# debug_backplane.net
KiCad netlist of a schematic drawn in EAGLE
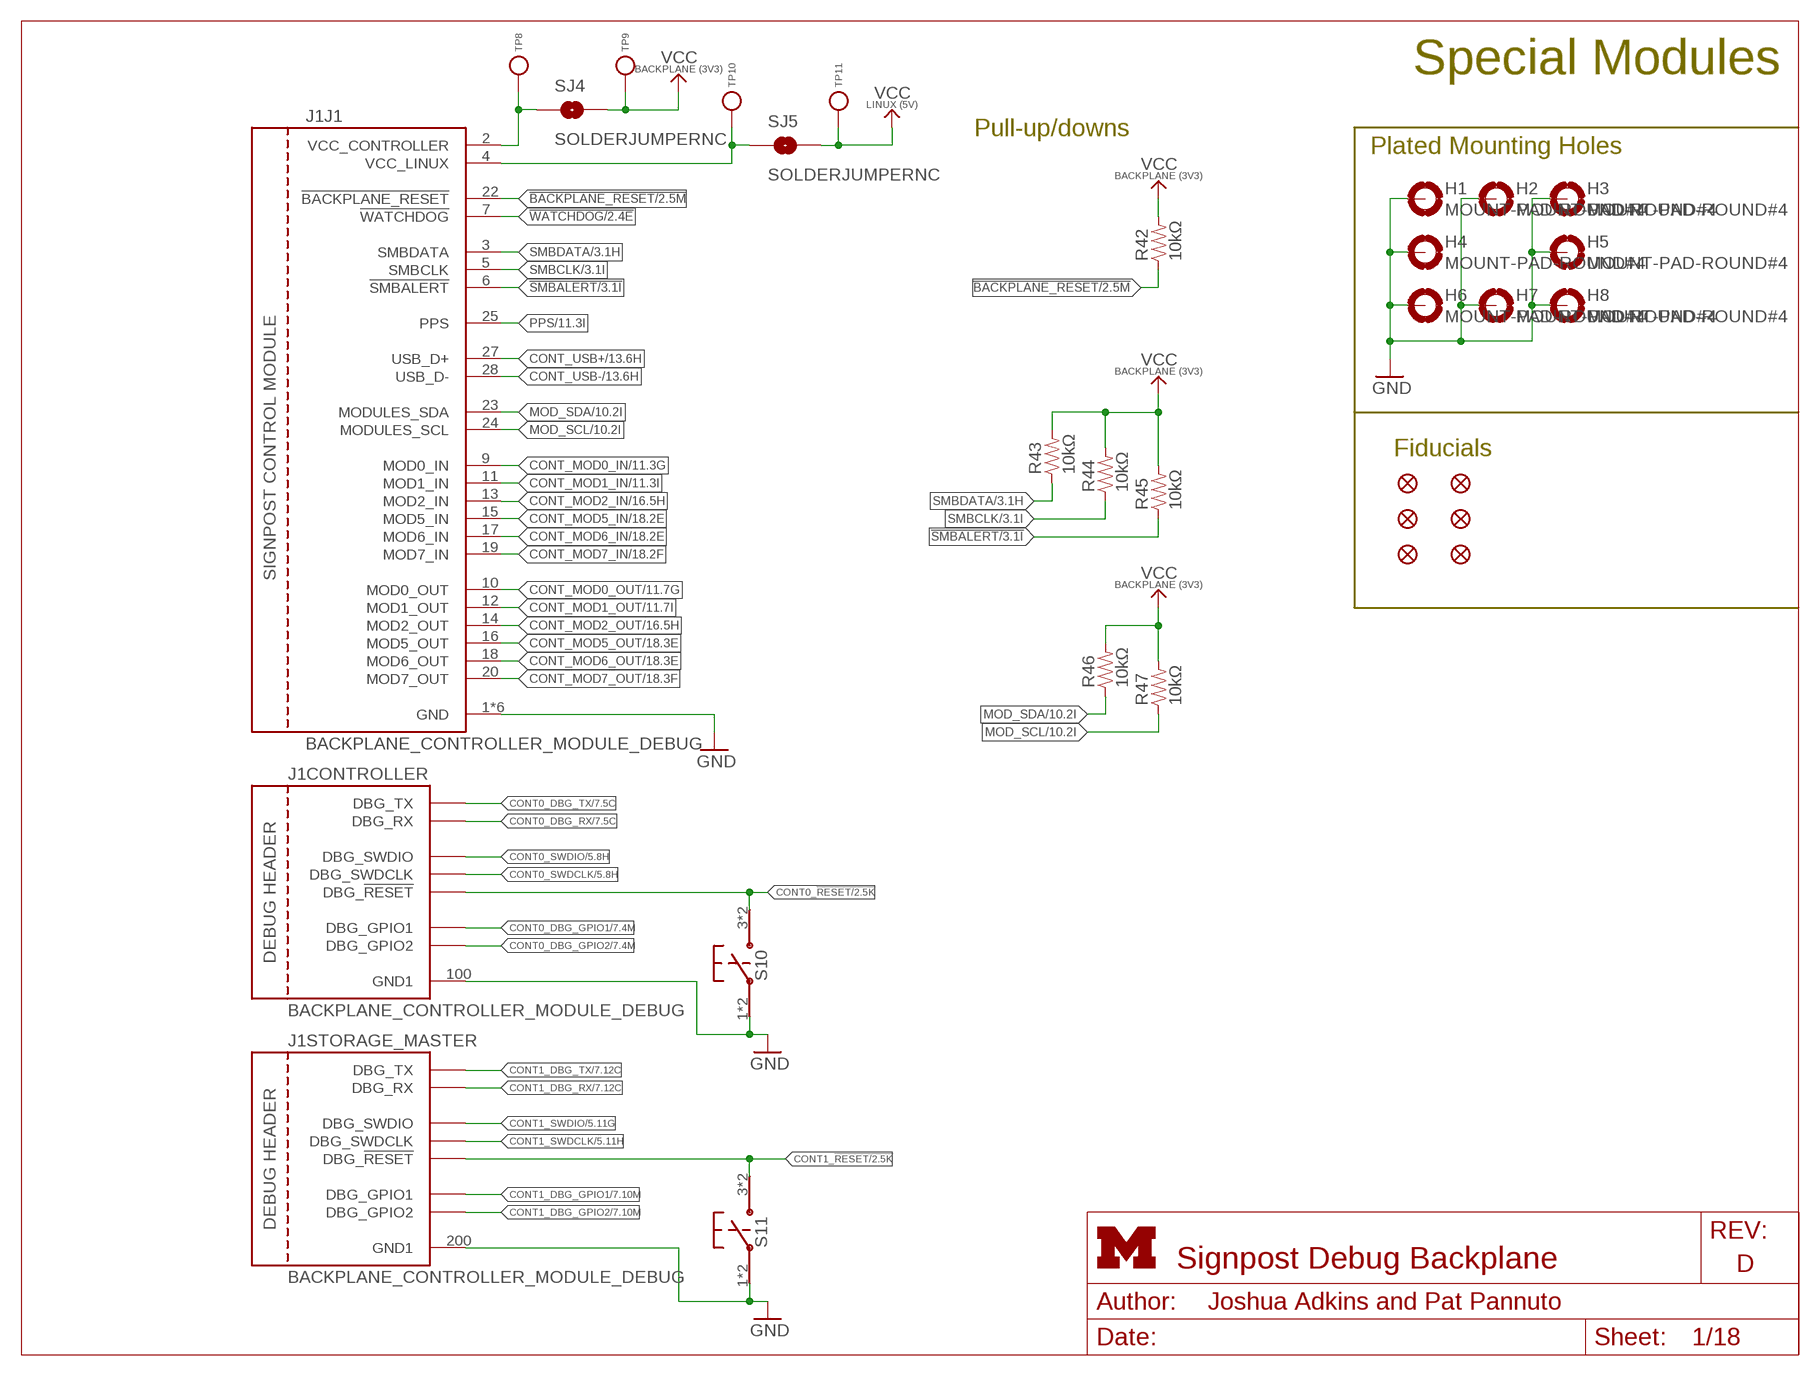
[diagram p0: schematic, sheet 1]
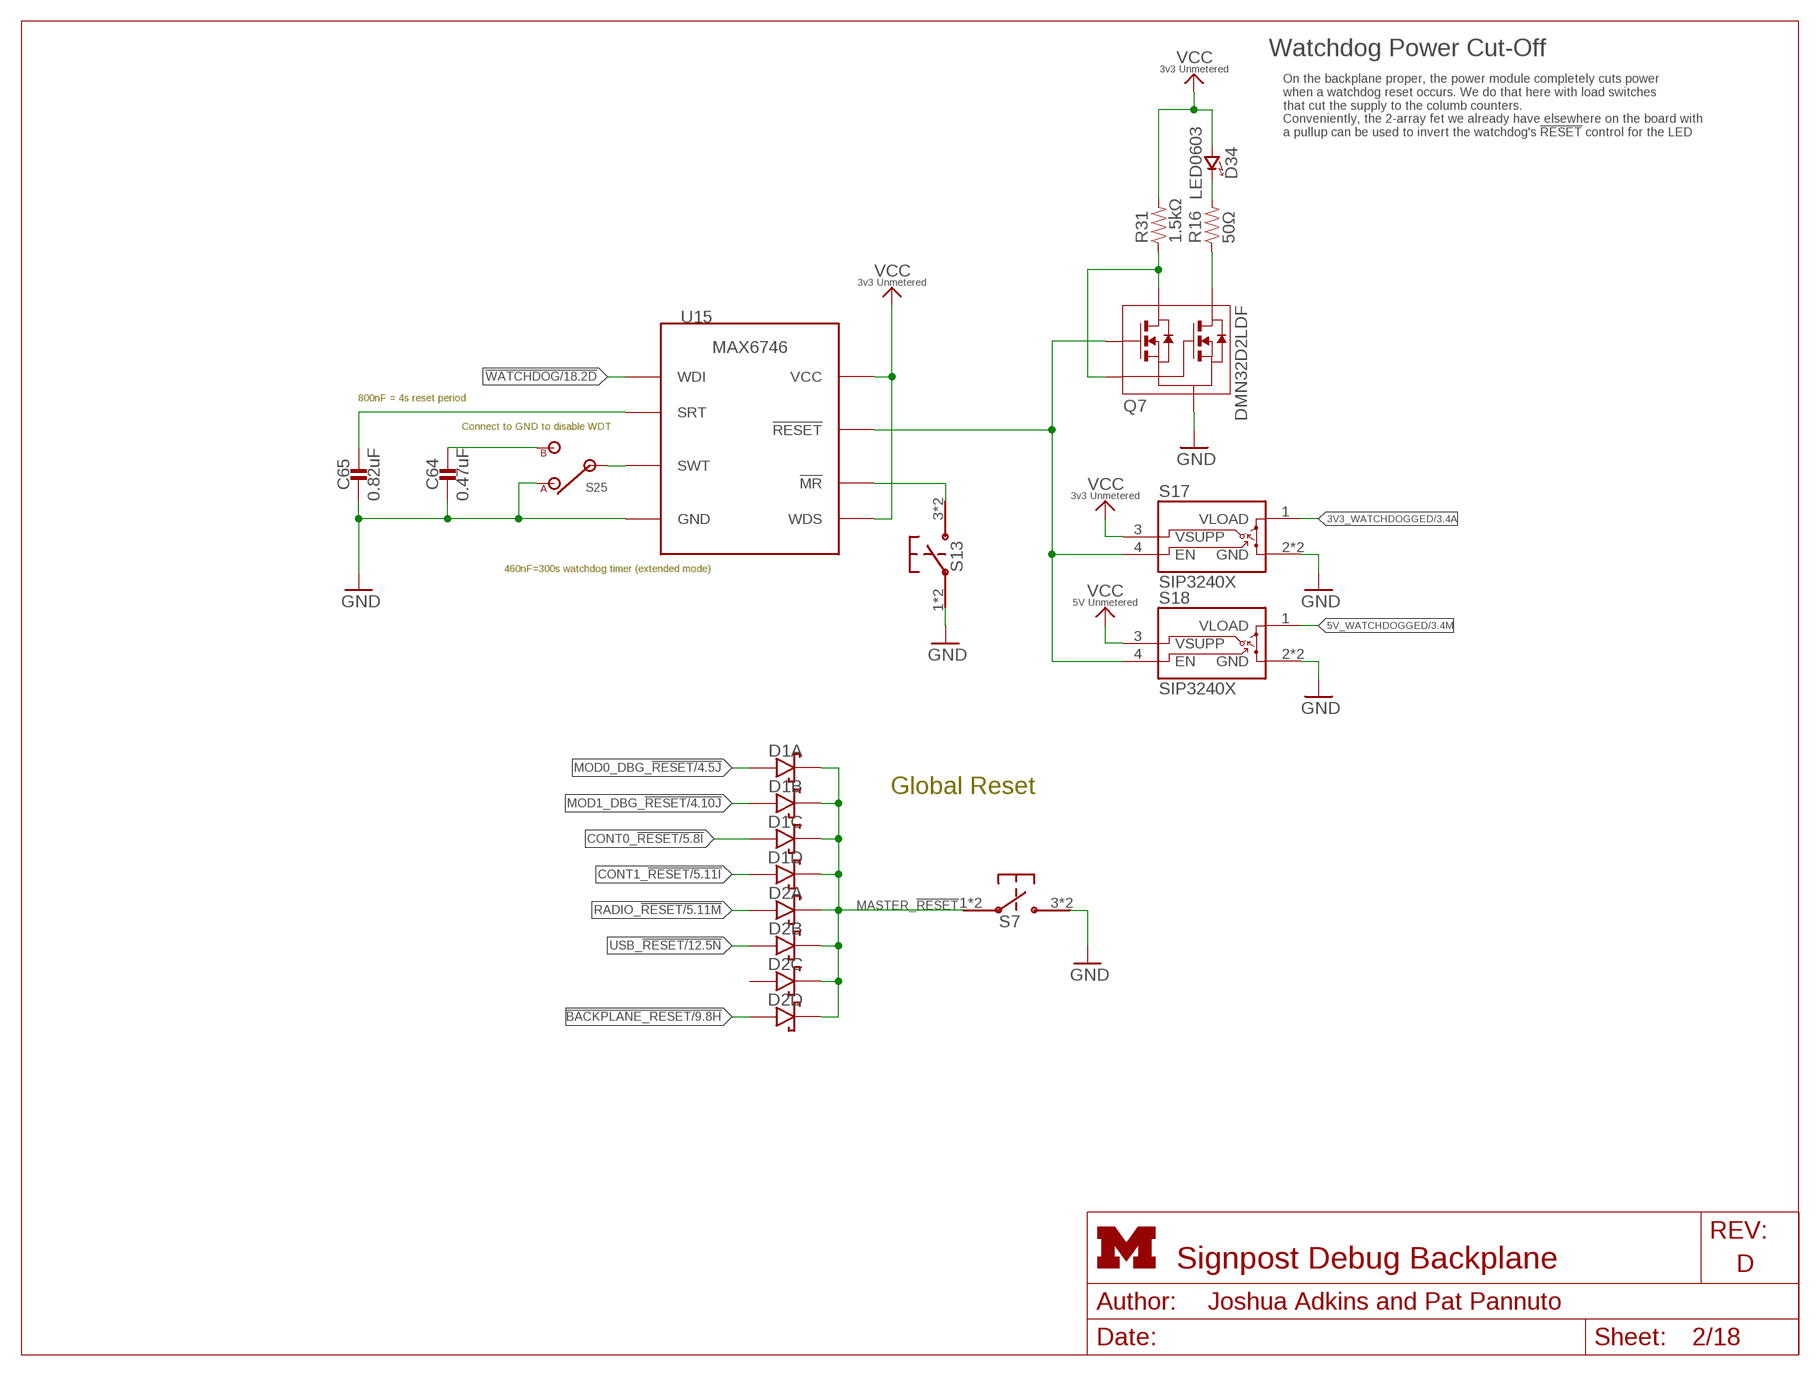
[diagram p1: schematic, sheet 2]
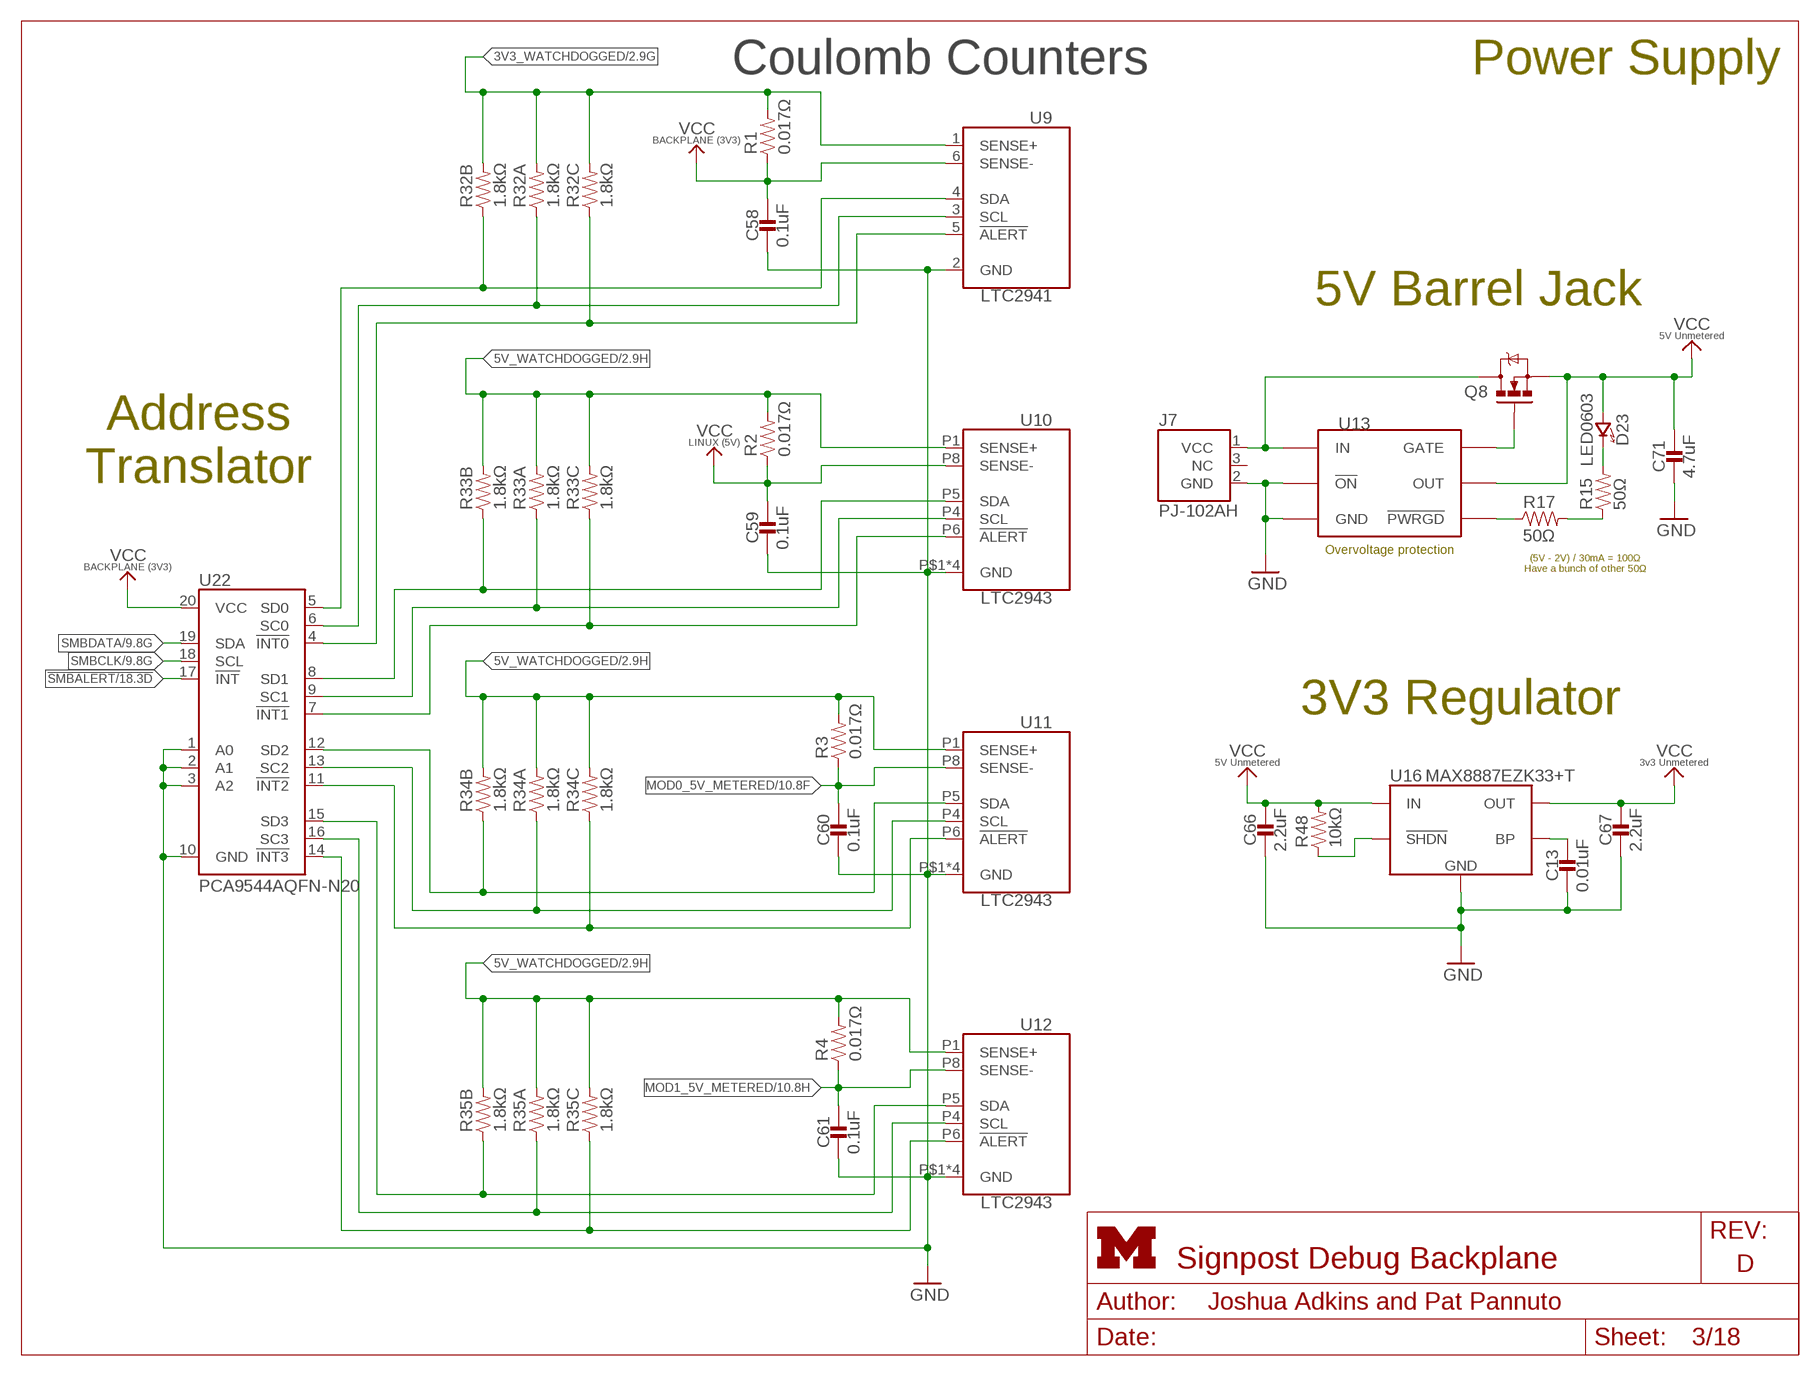
[diagram p2: schematic, sheet 3]
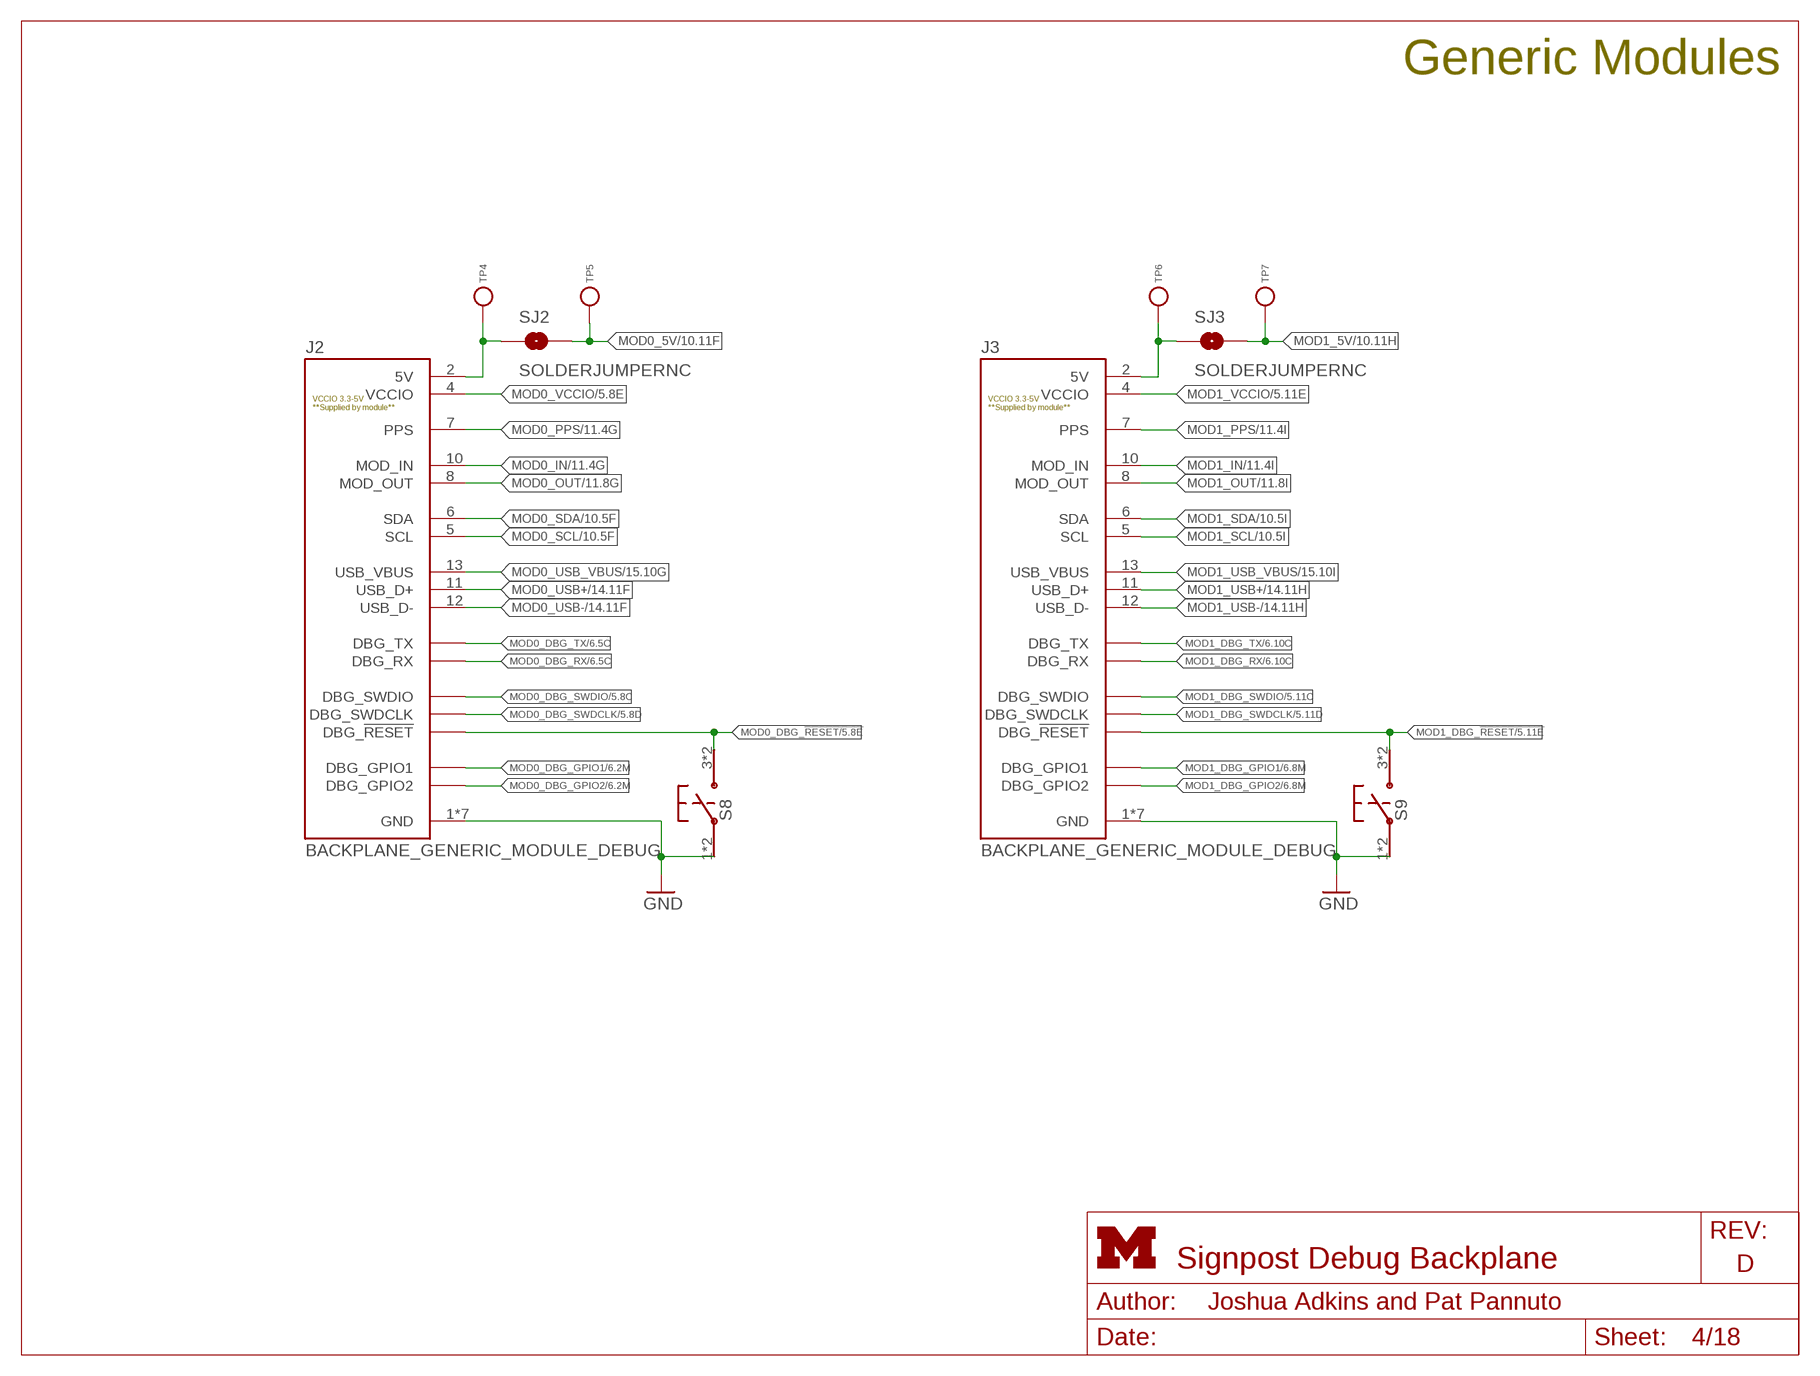
[diagram p3: schematic, sheet 4]
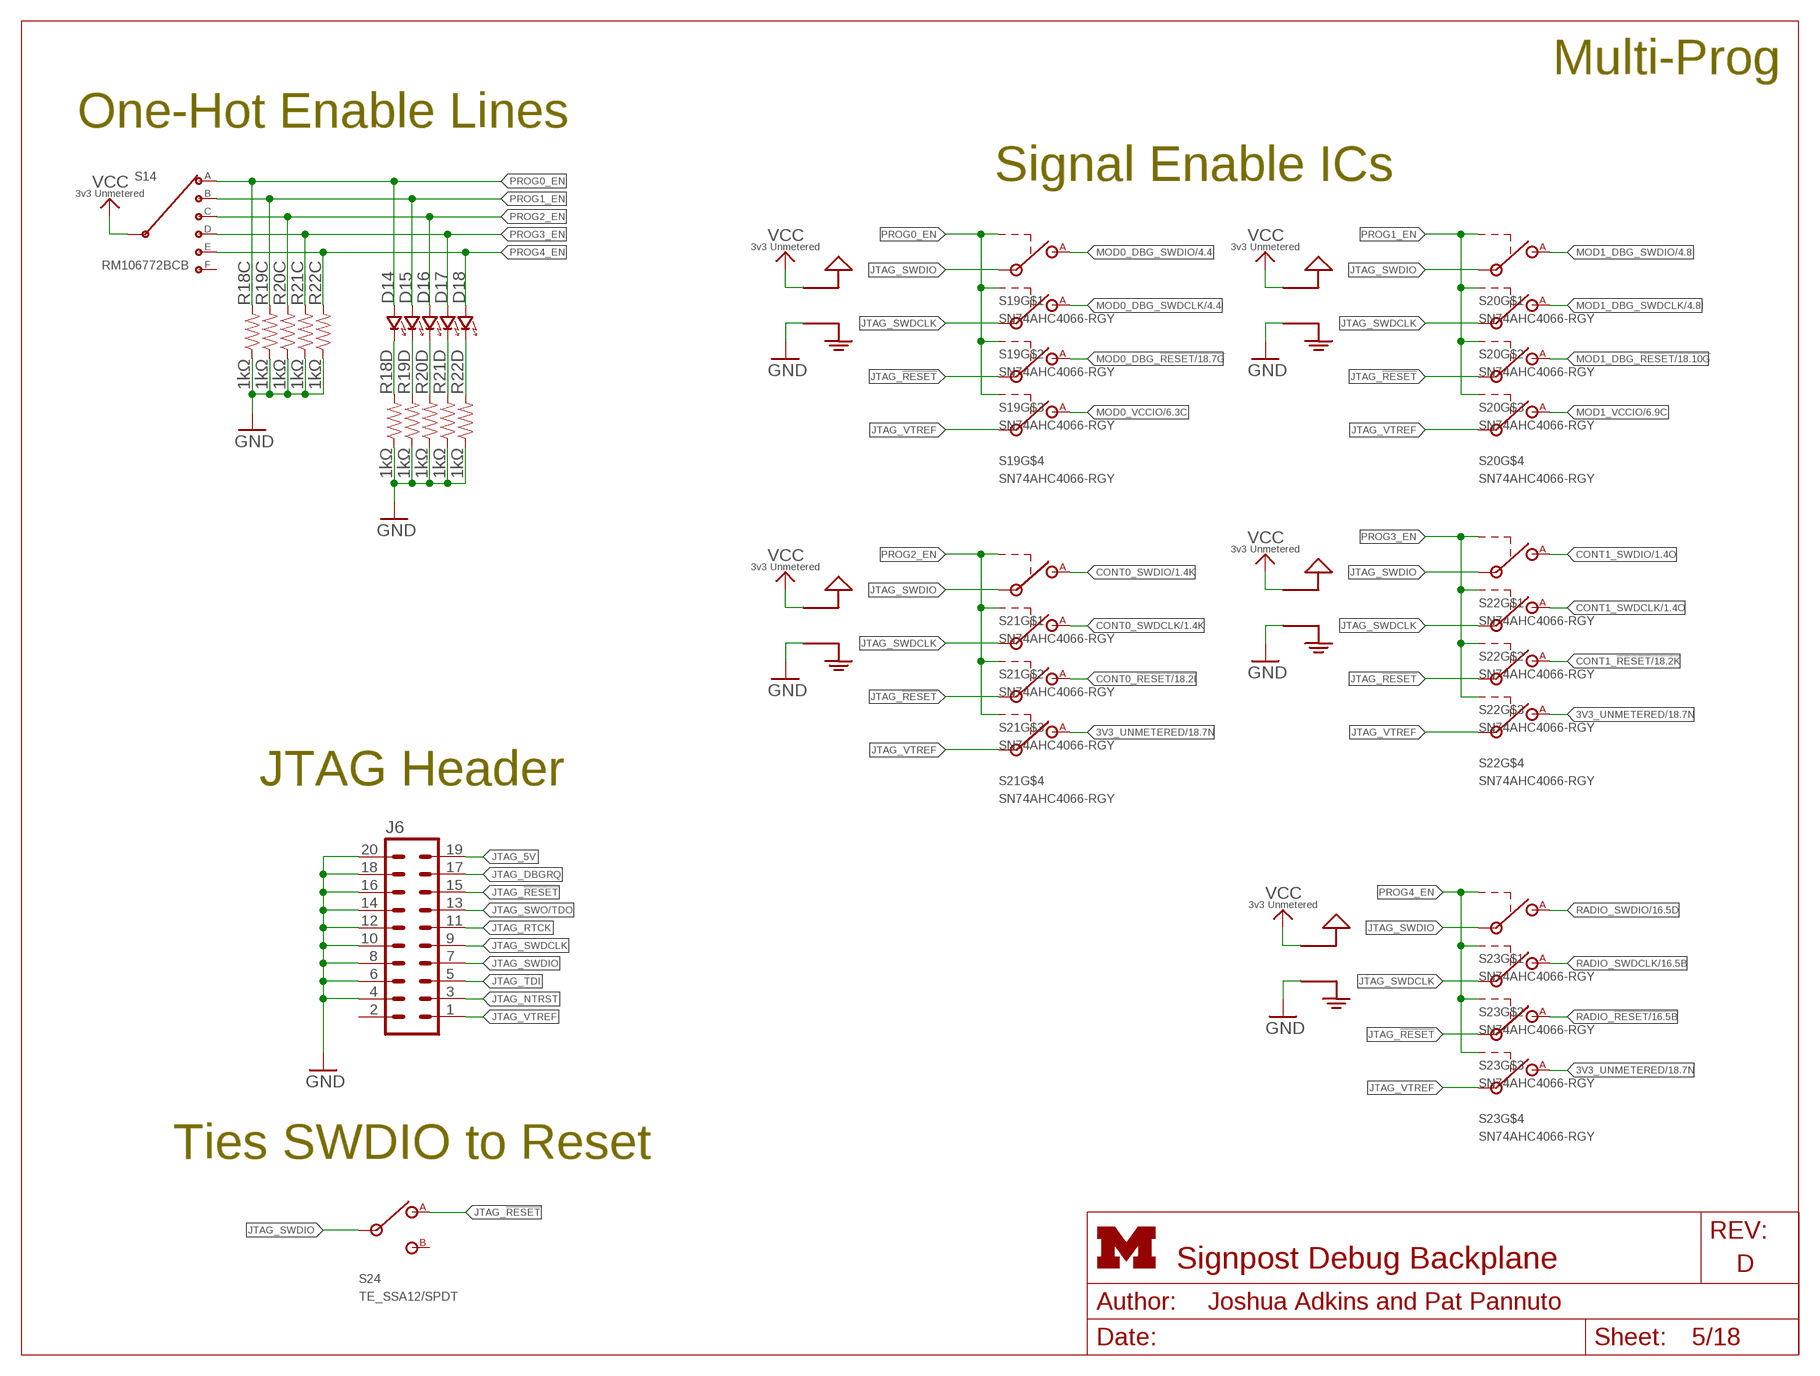
[diagram p4: schematic, sheet 5]
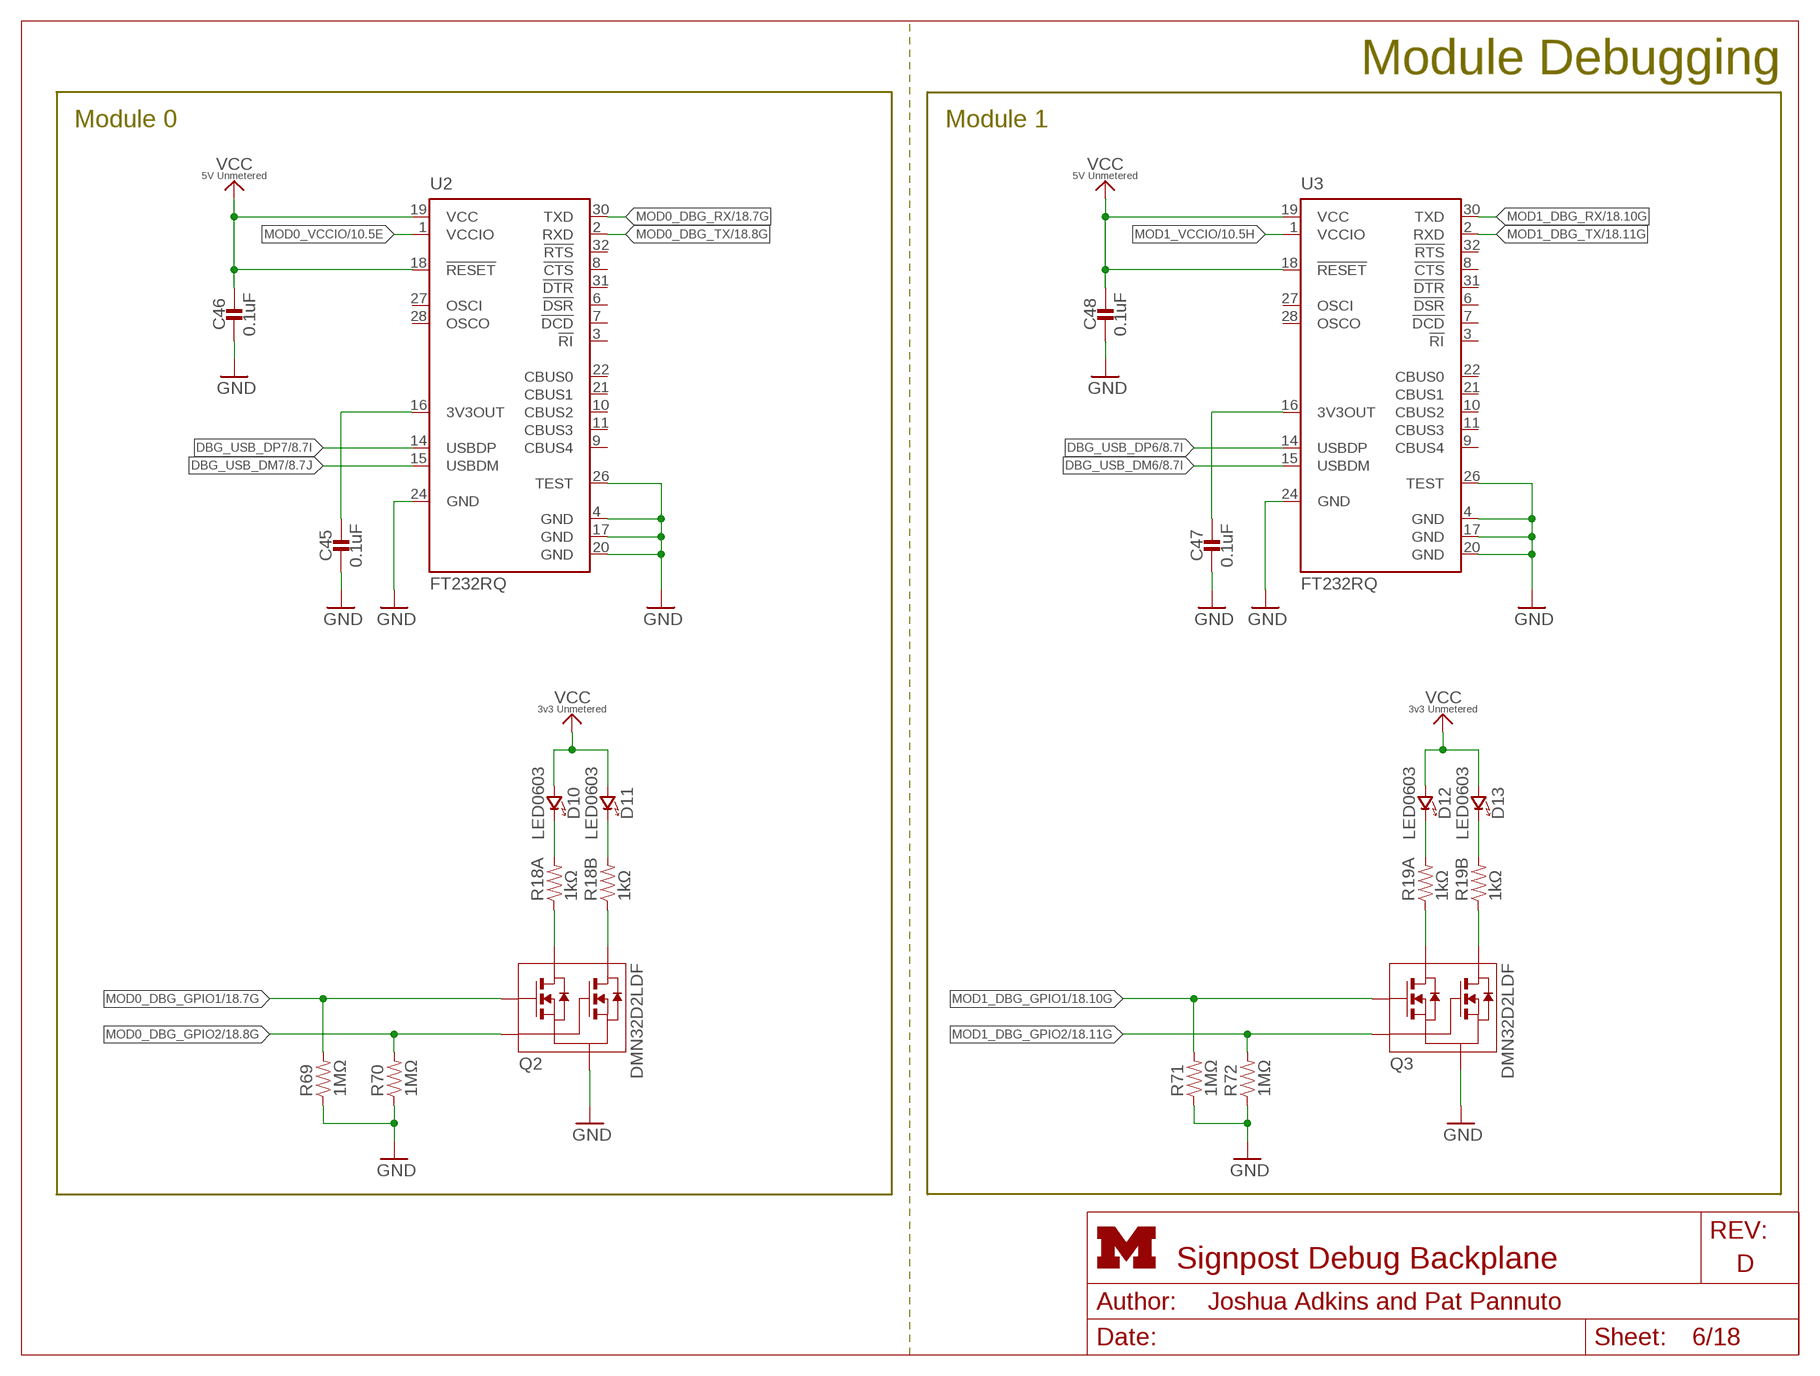
[diagram p5: schematic, sheet 6]
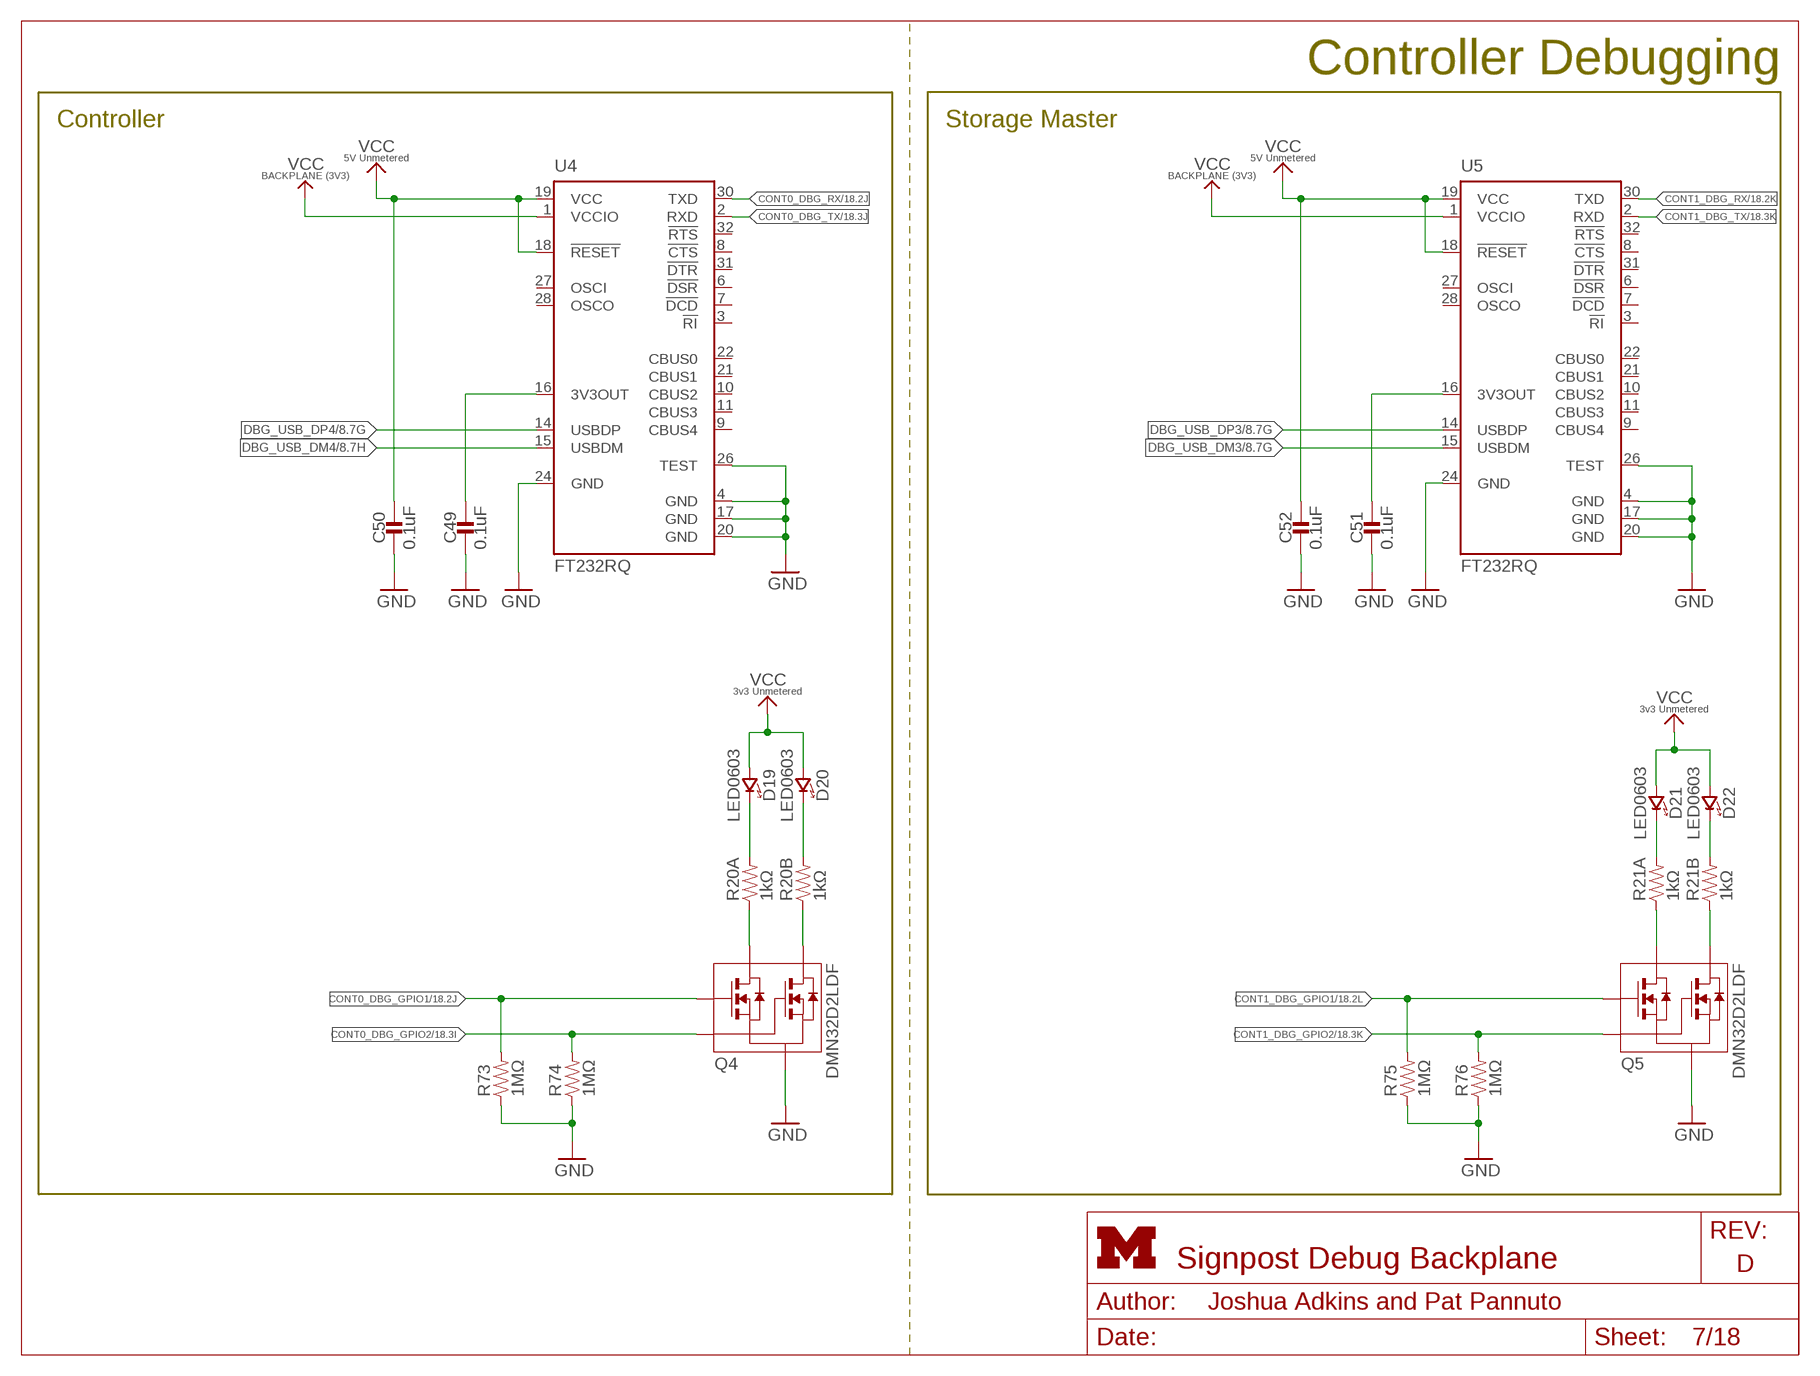
[diagram p6: schematic, sheet 7]
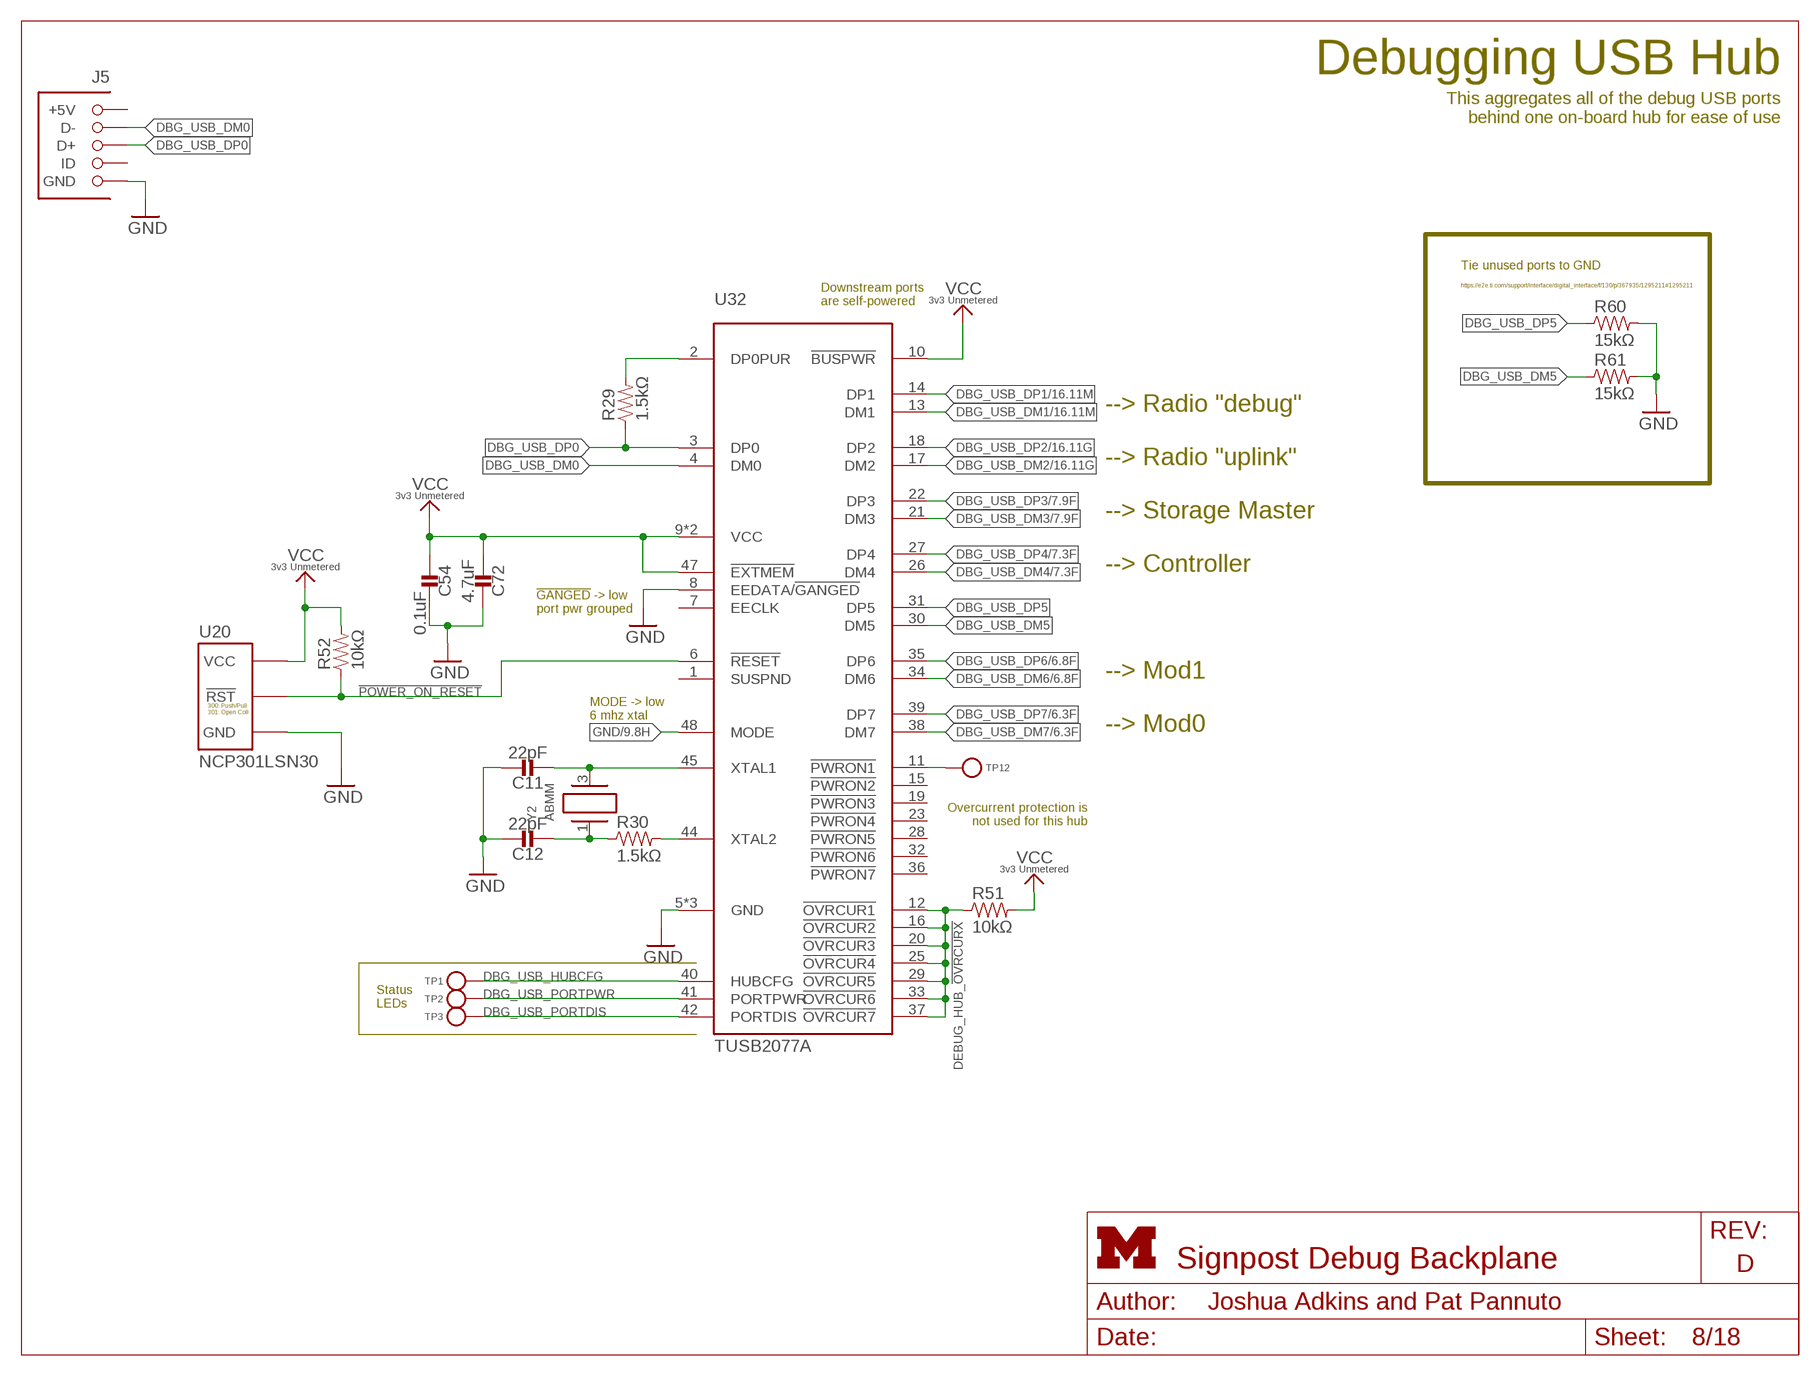
[diagram p7: schematic, sheet 8]
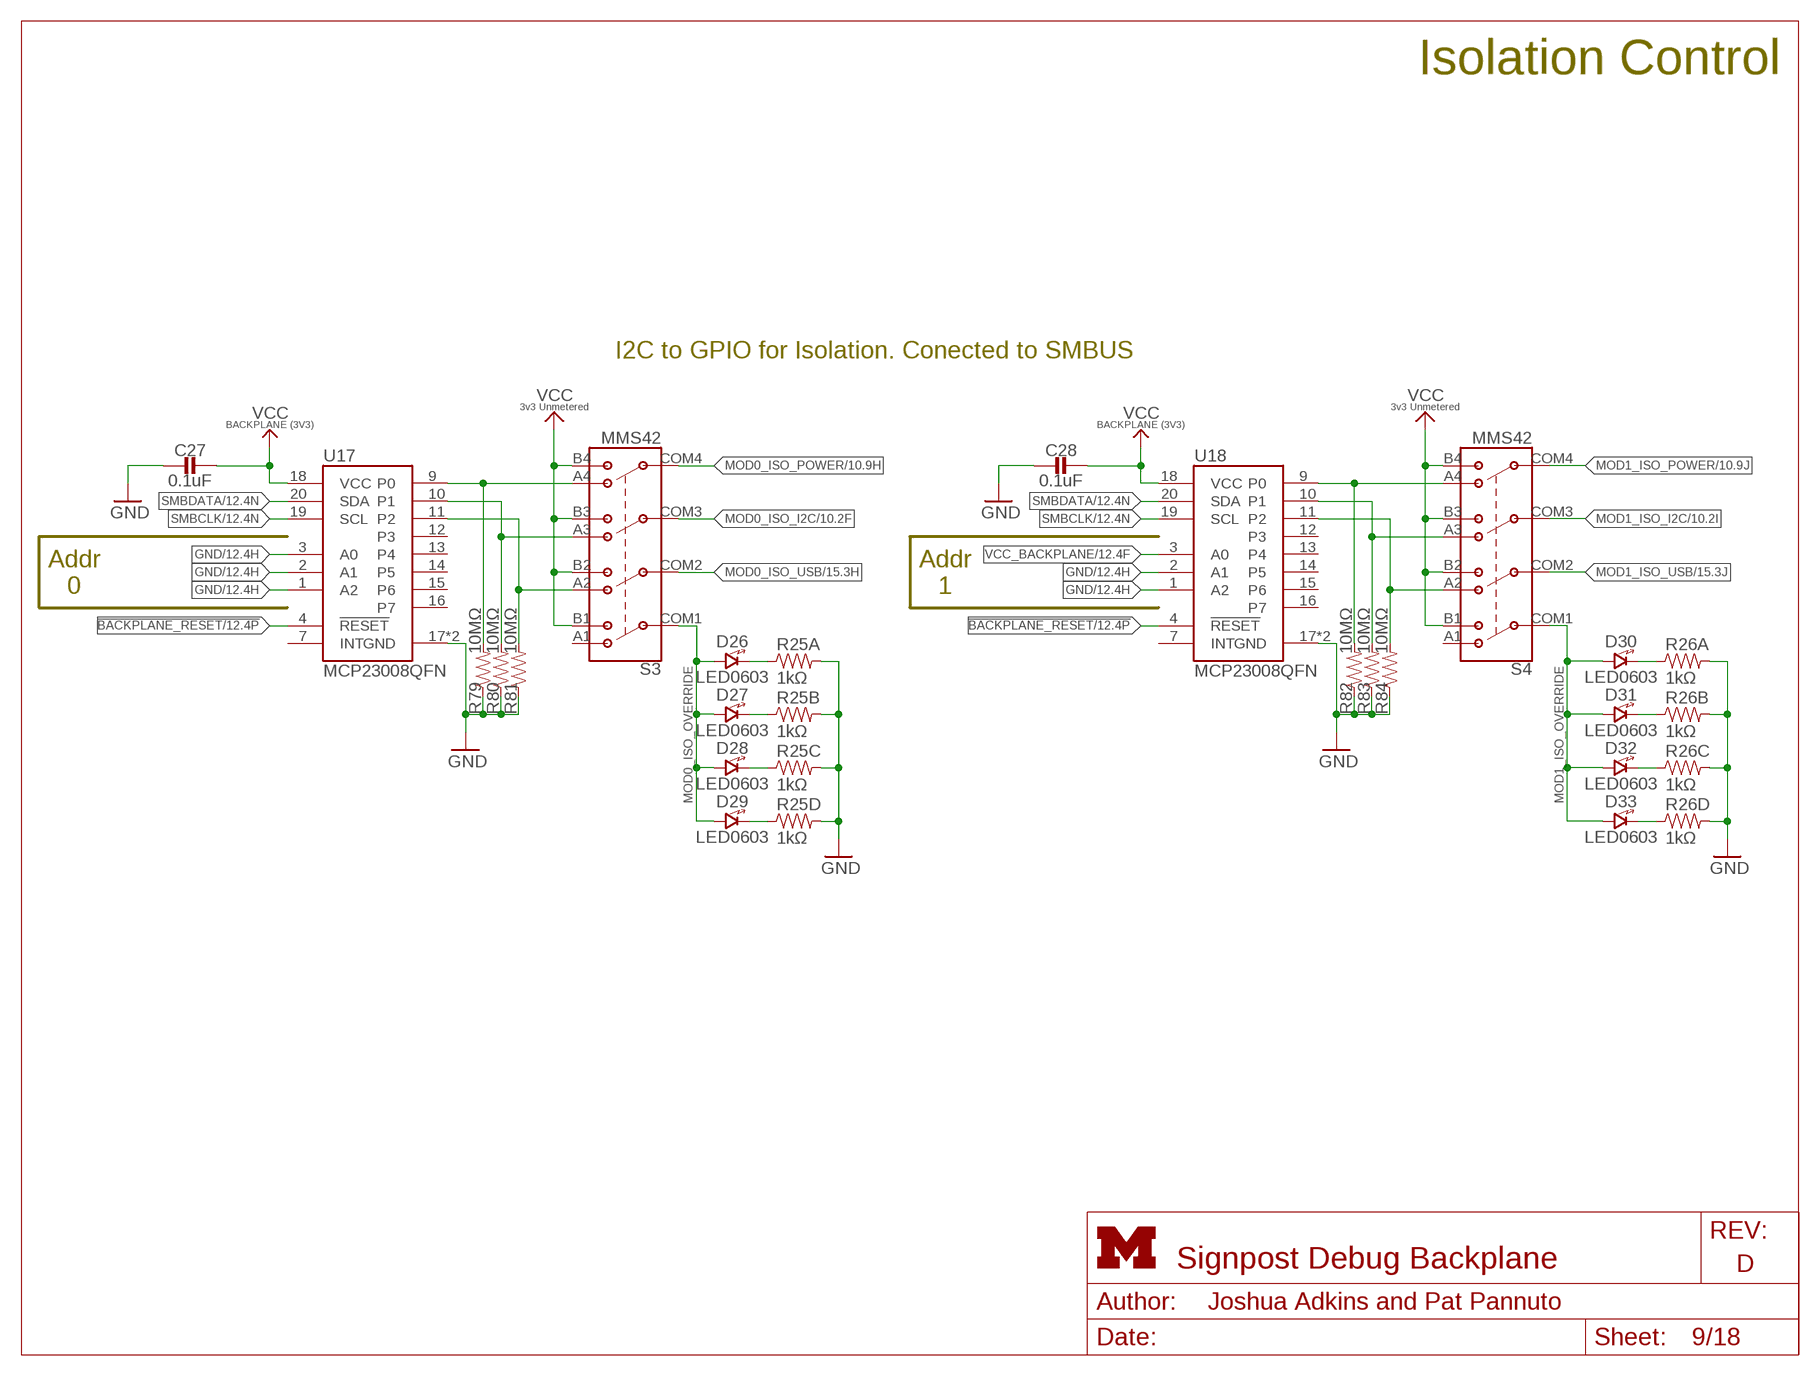
[diagram p8: schematic, sheet 9]
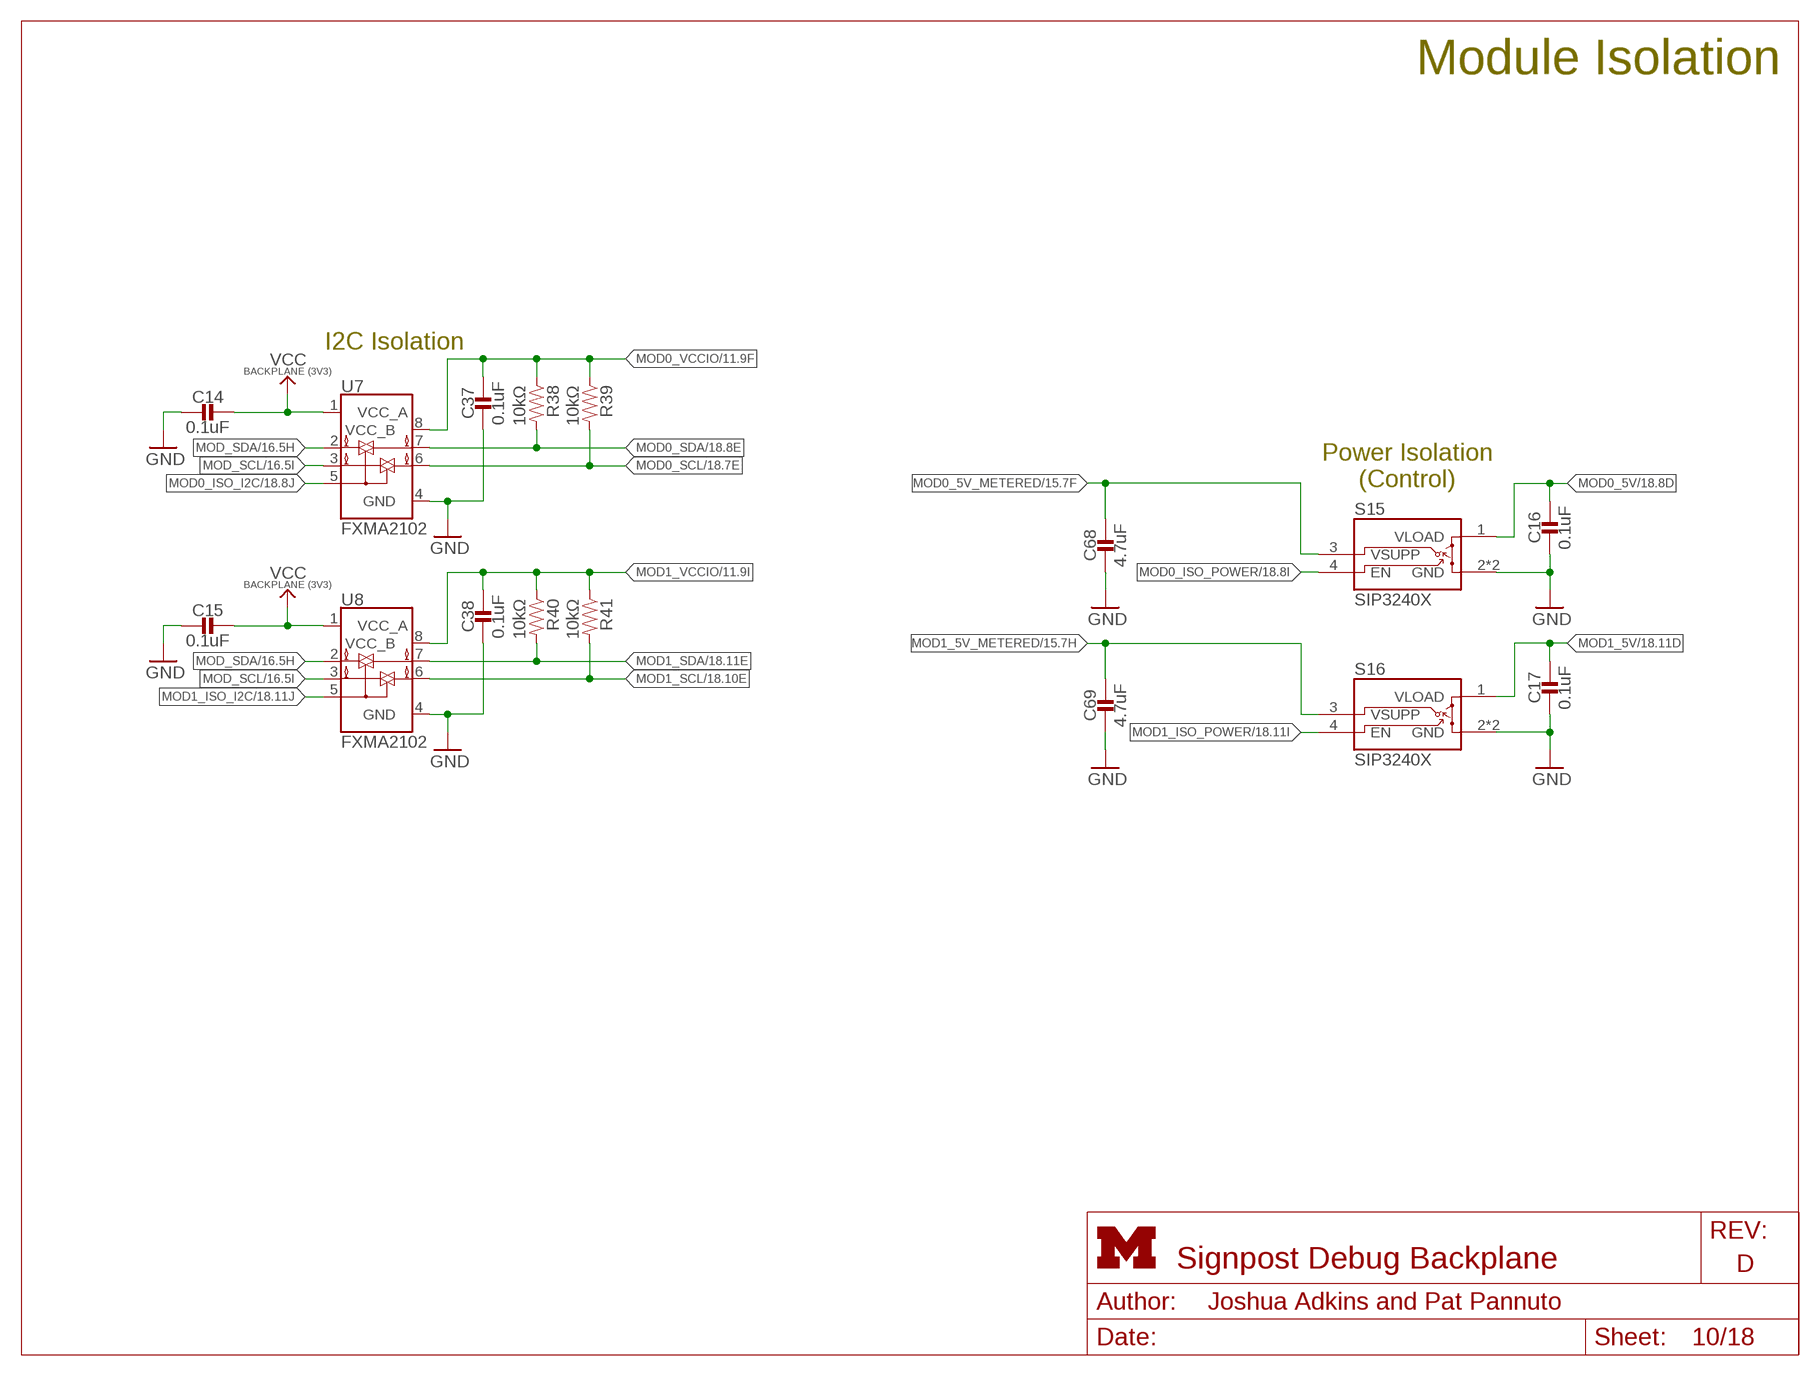
[diagram p9: schematic, sheet 10]
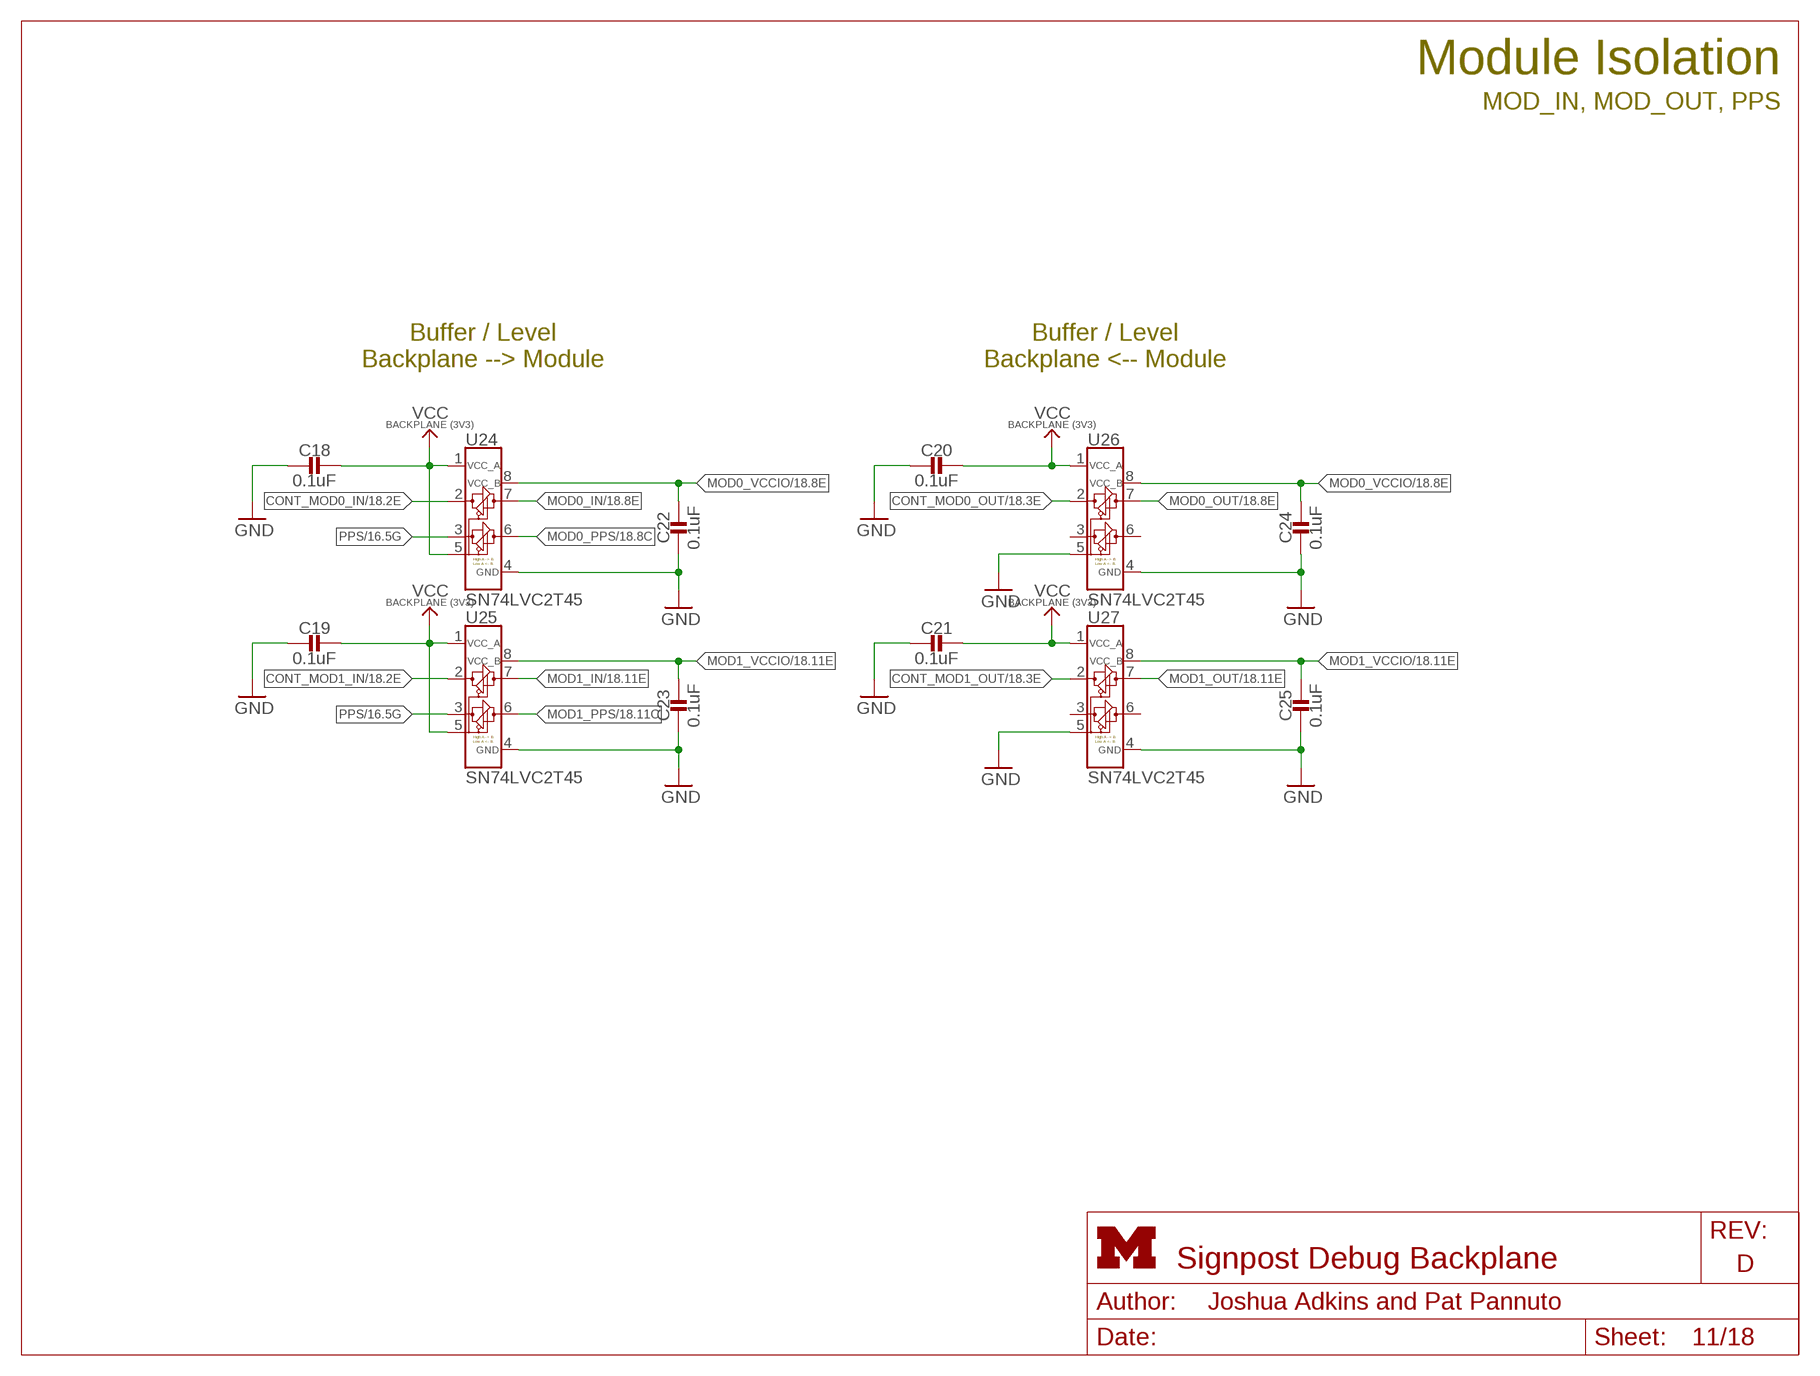
[diagram p10: schematic, sheet 11]
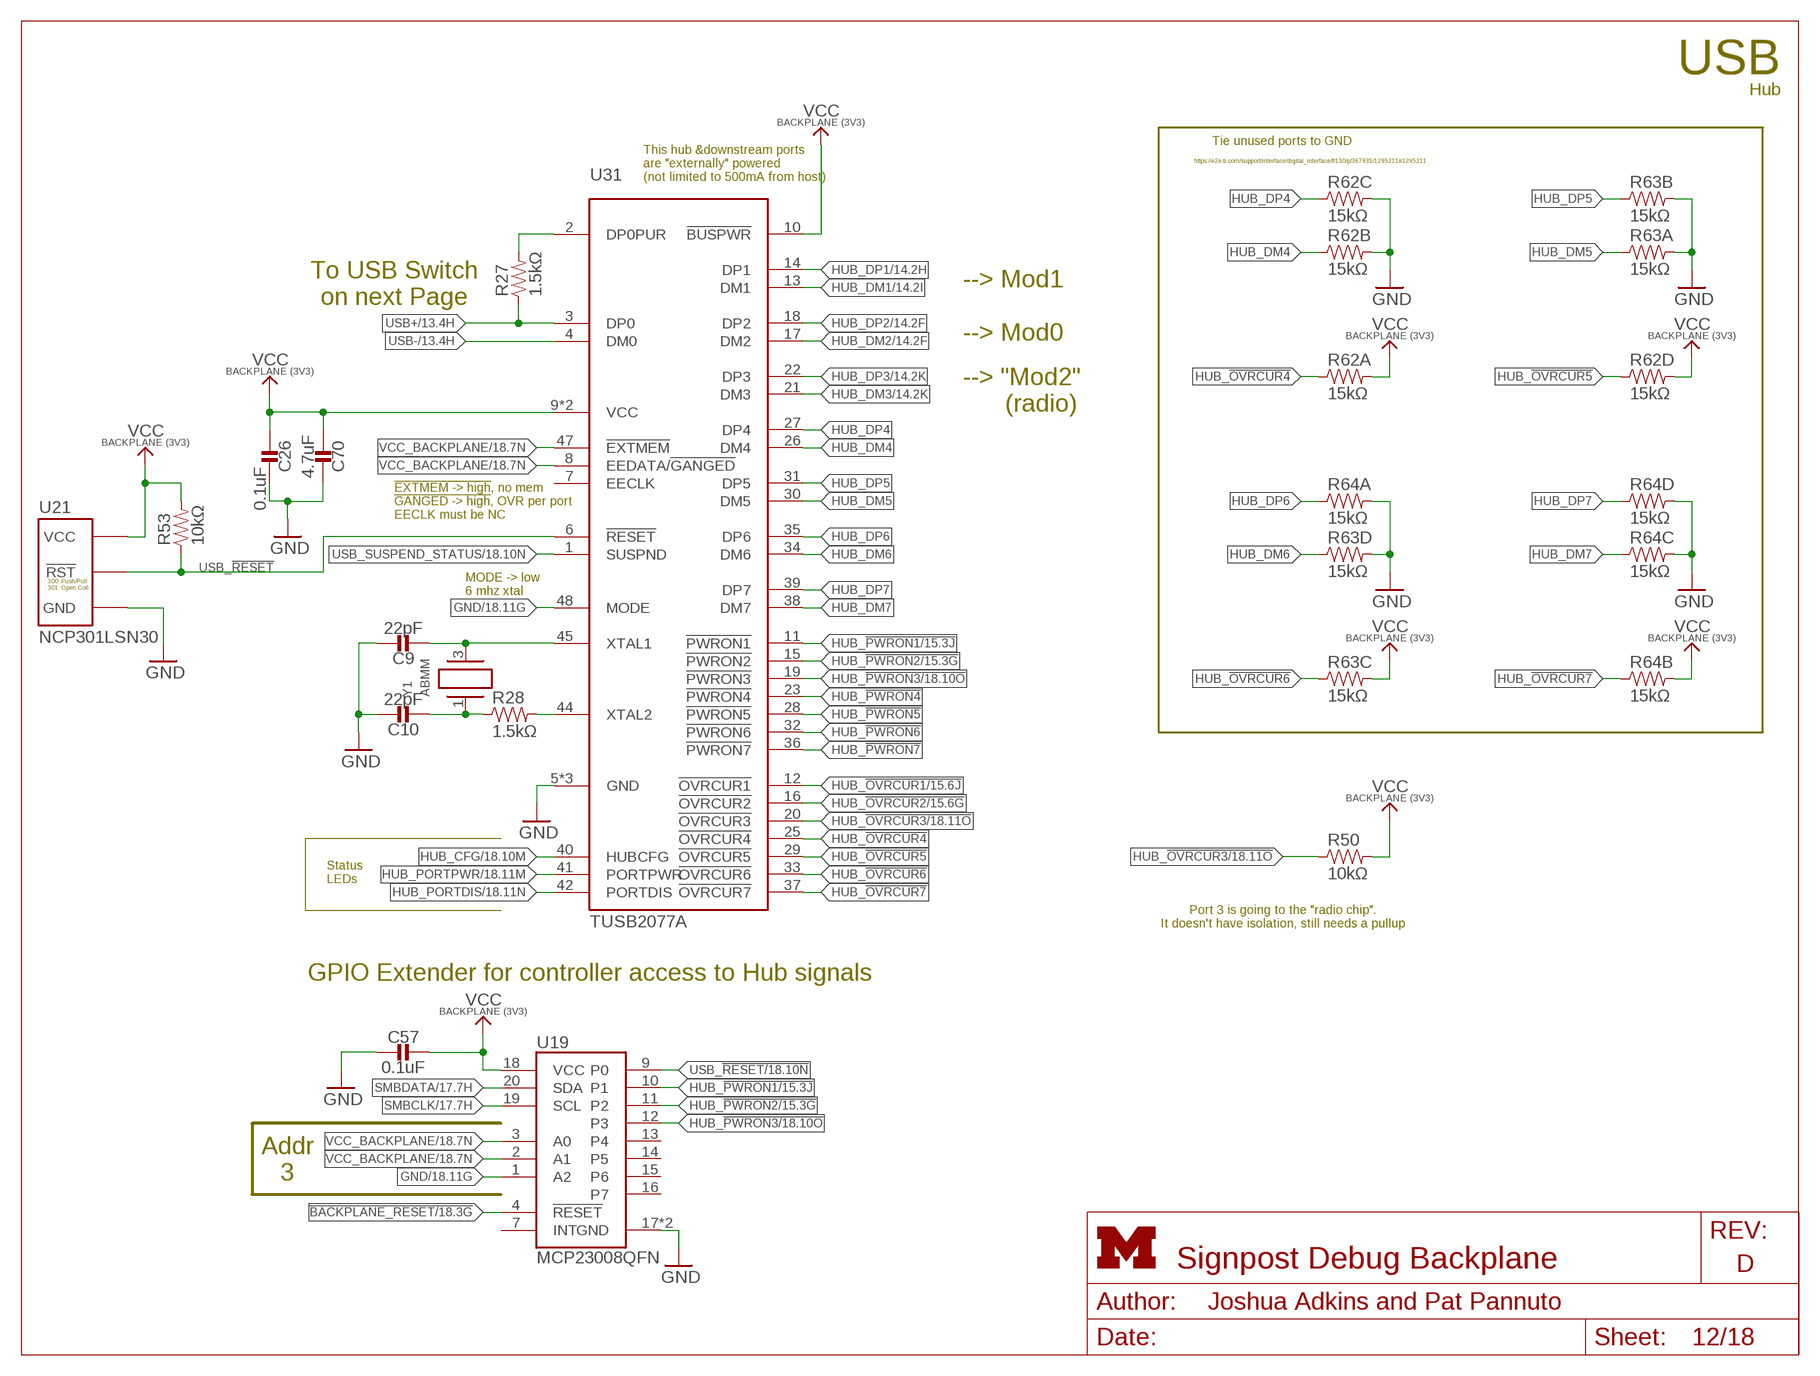
[diagram p11: schematic, sheet 12]
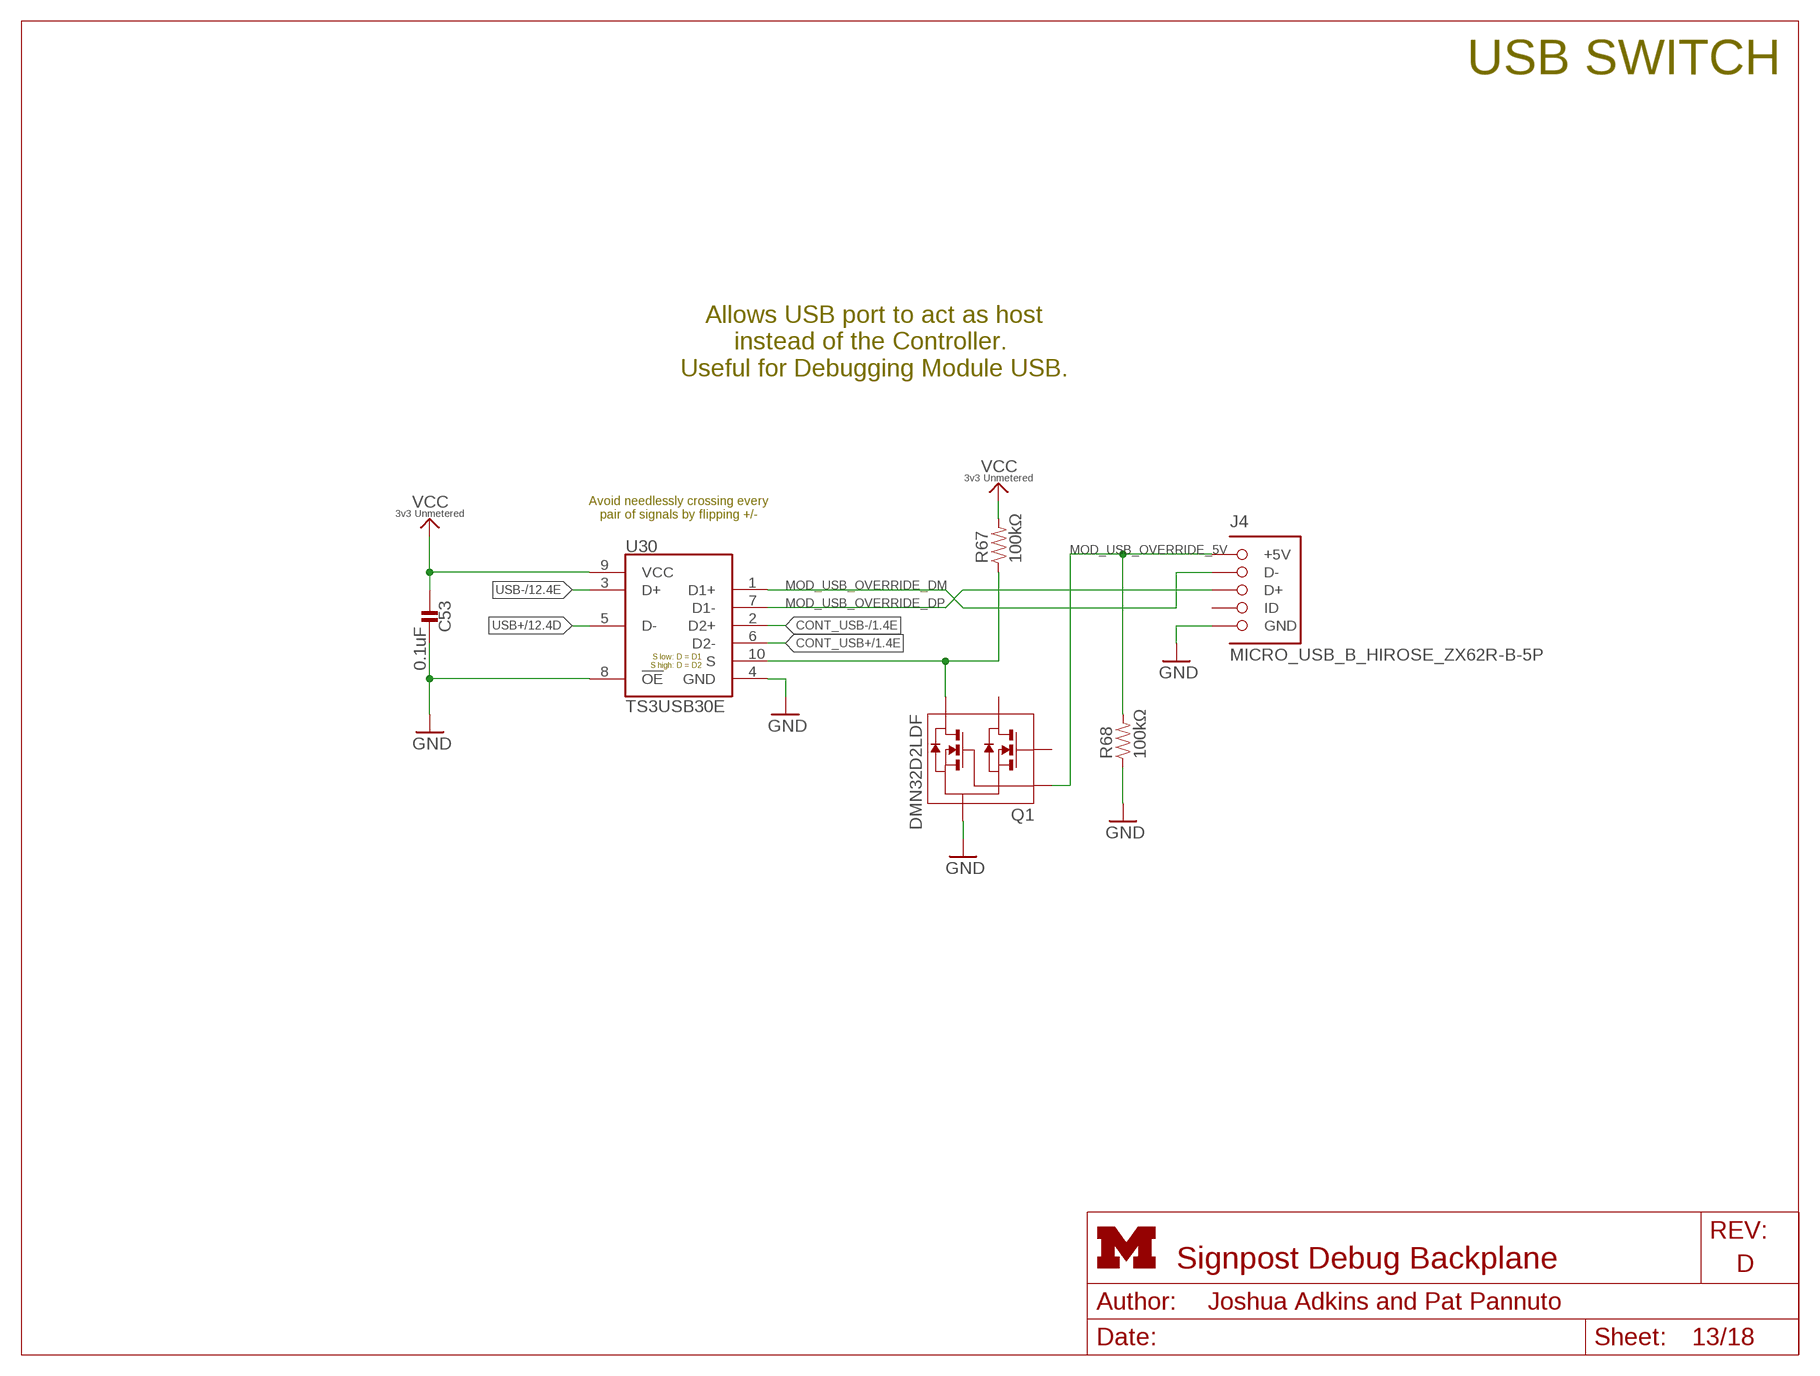
[diagram p12: schematic, sheet 13]
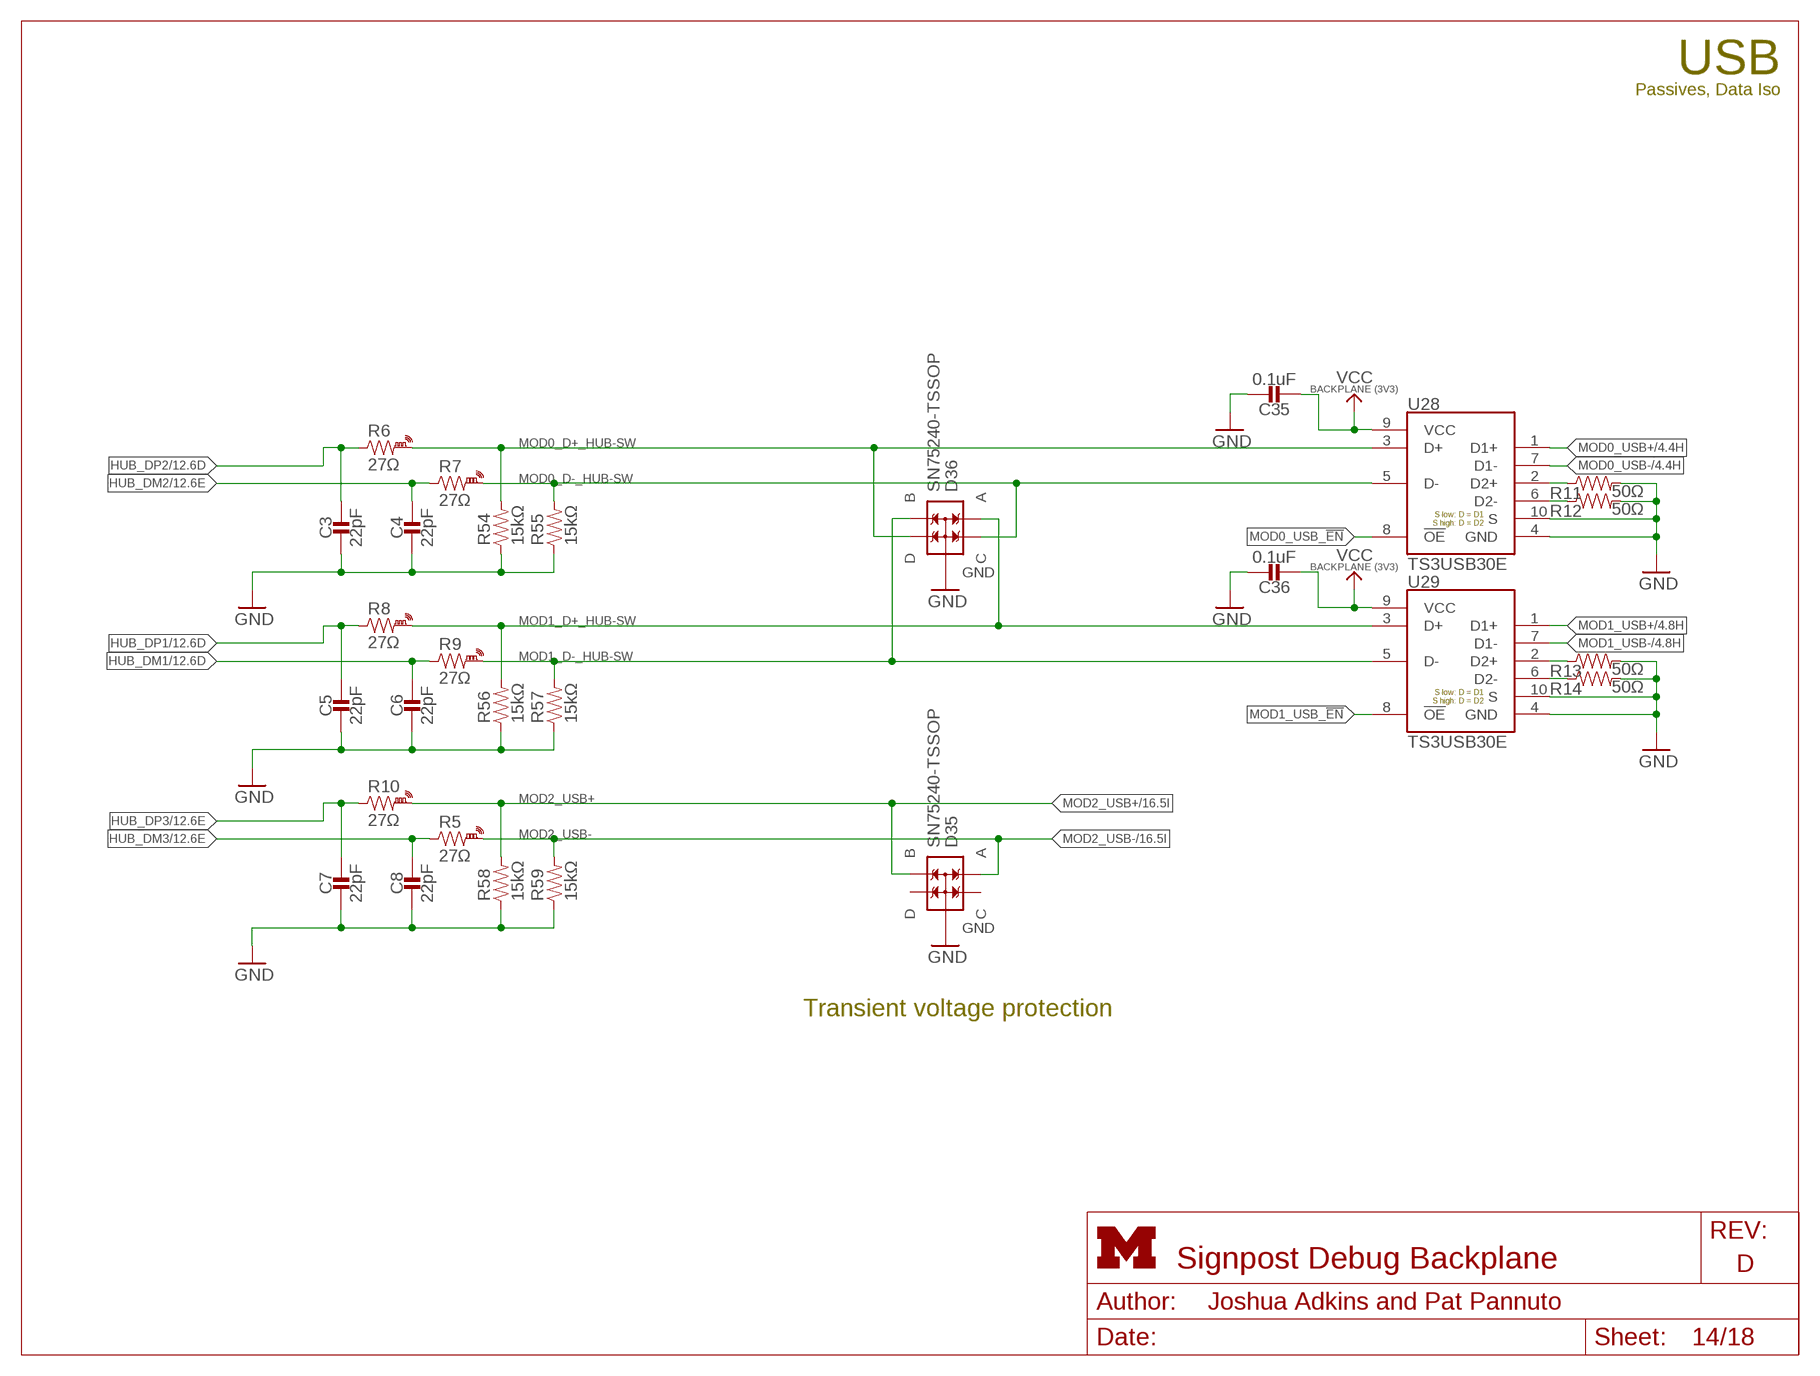
[diagram p13: schematic, sheet 14]
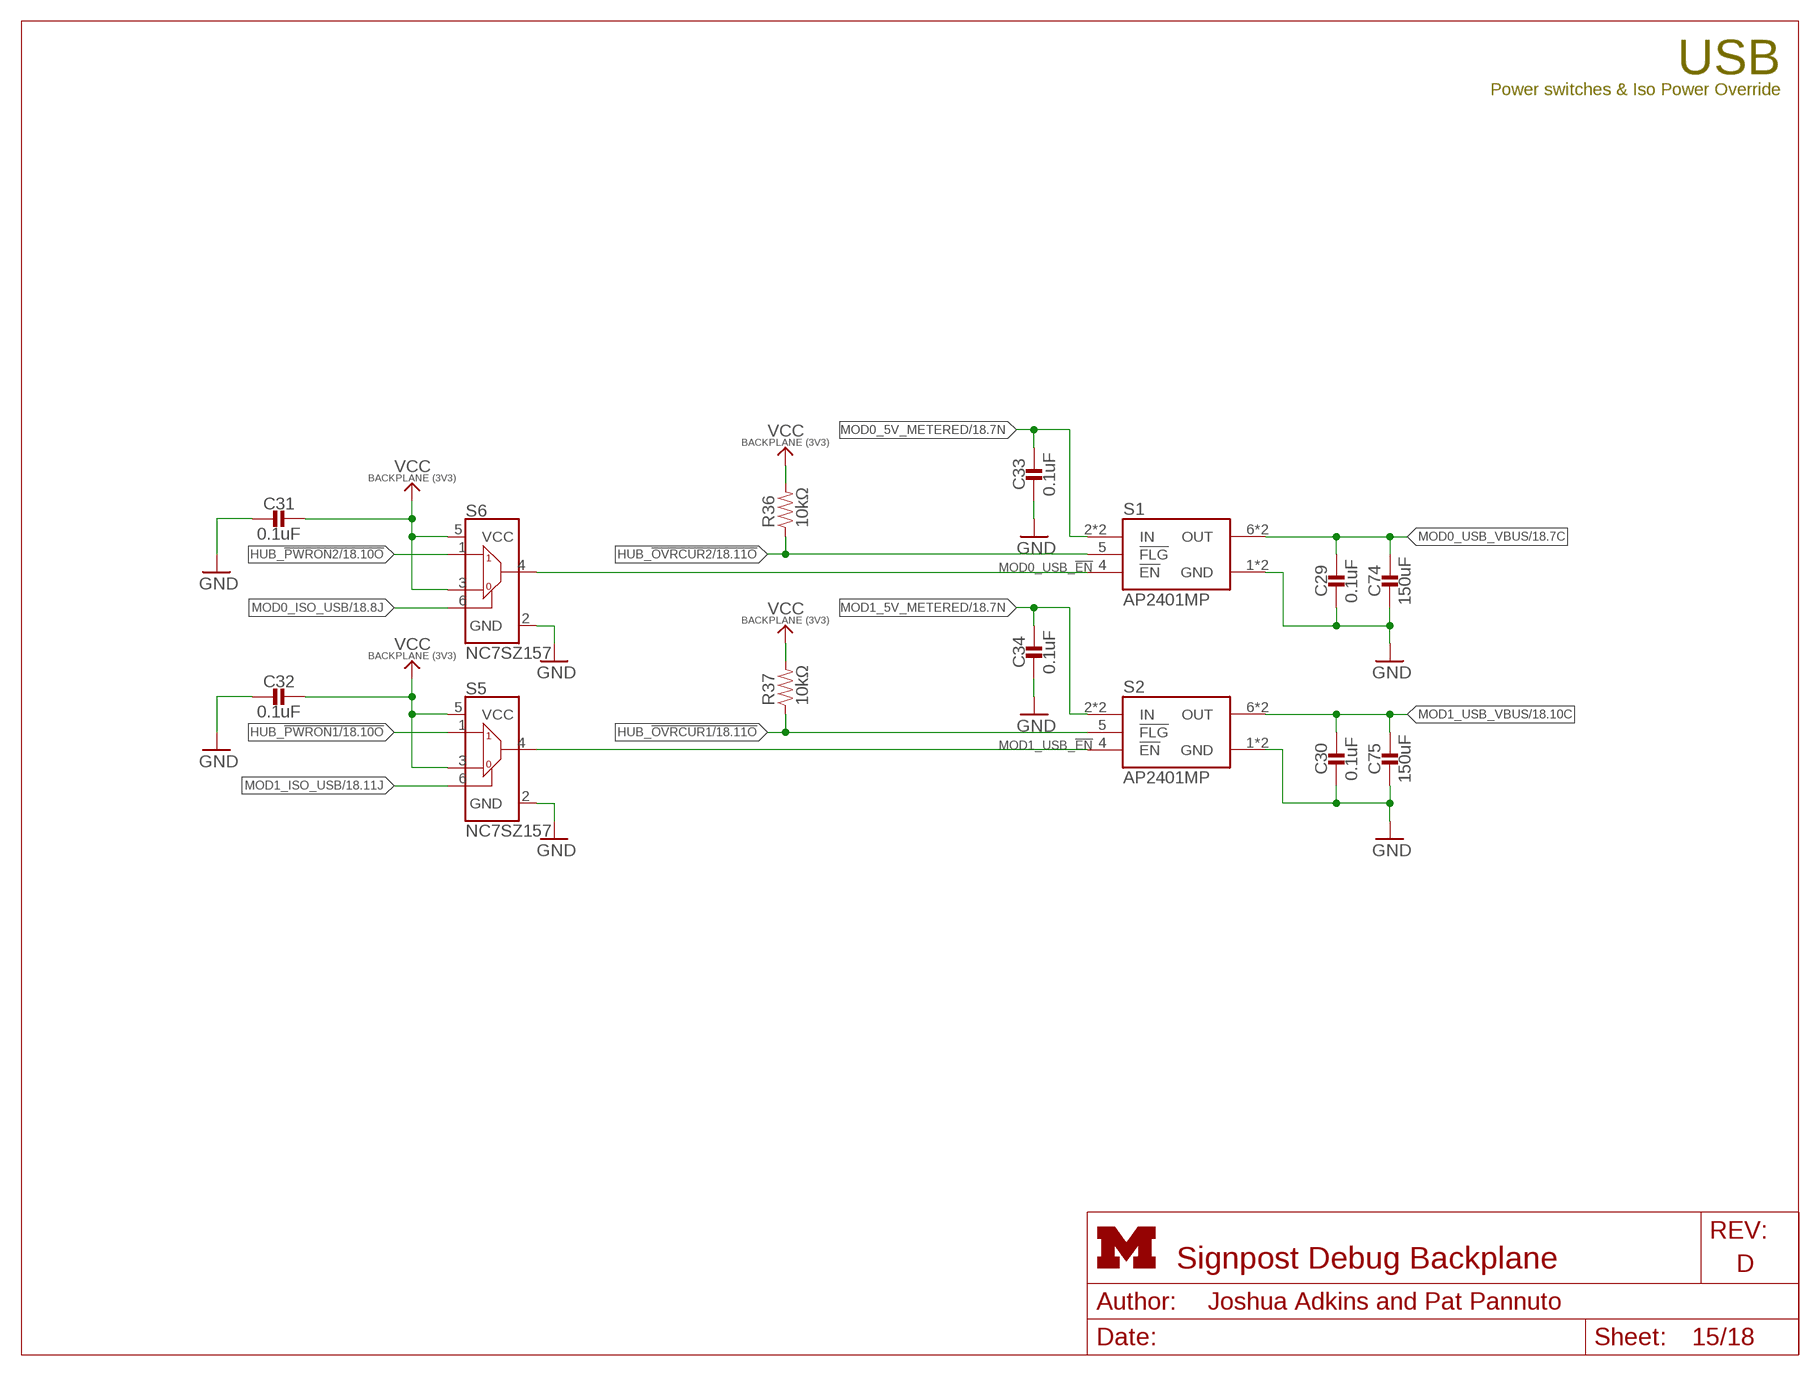
[diagram p14: schematic, sheet 15]
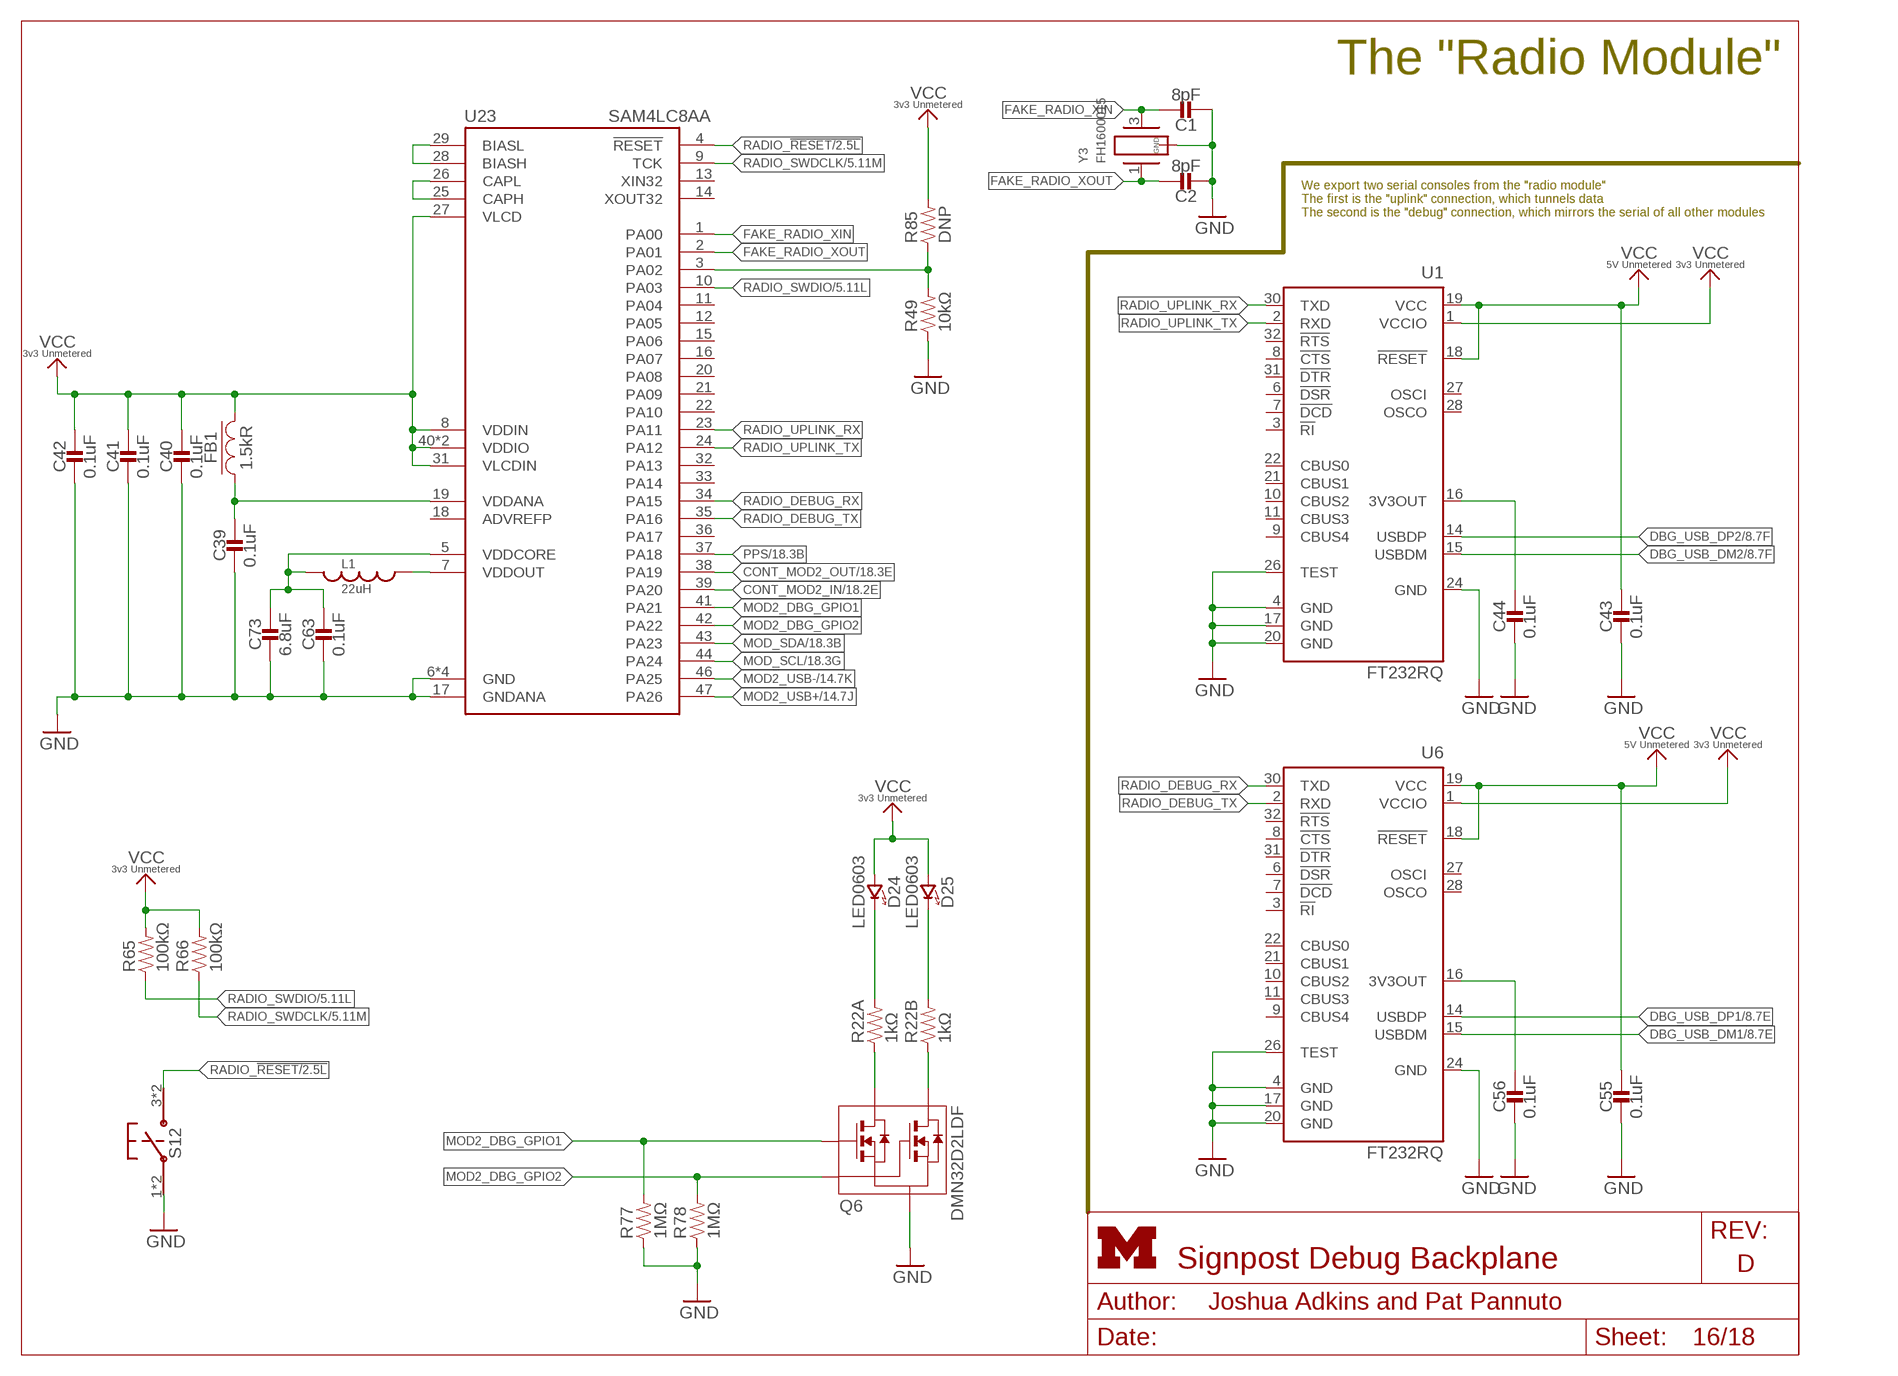
[diagram p15: schematic, sheet 16]
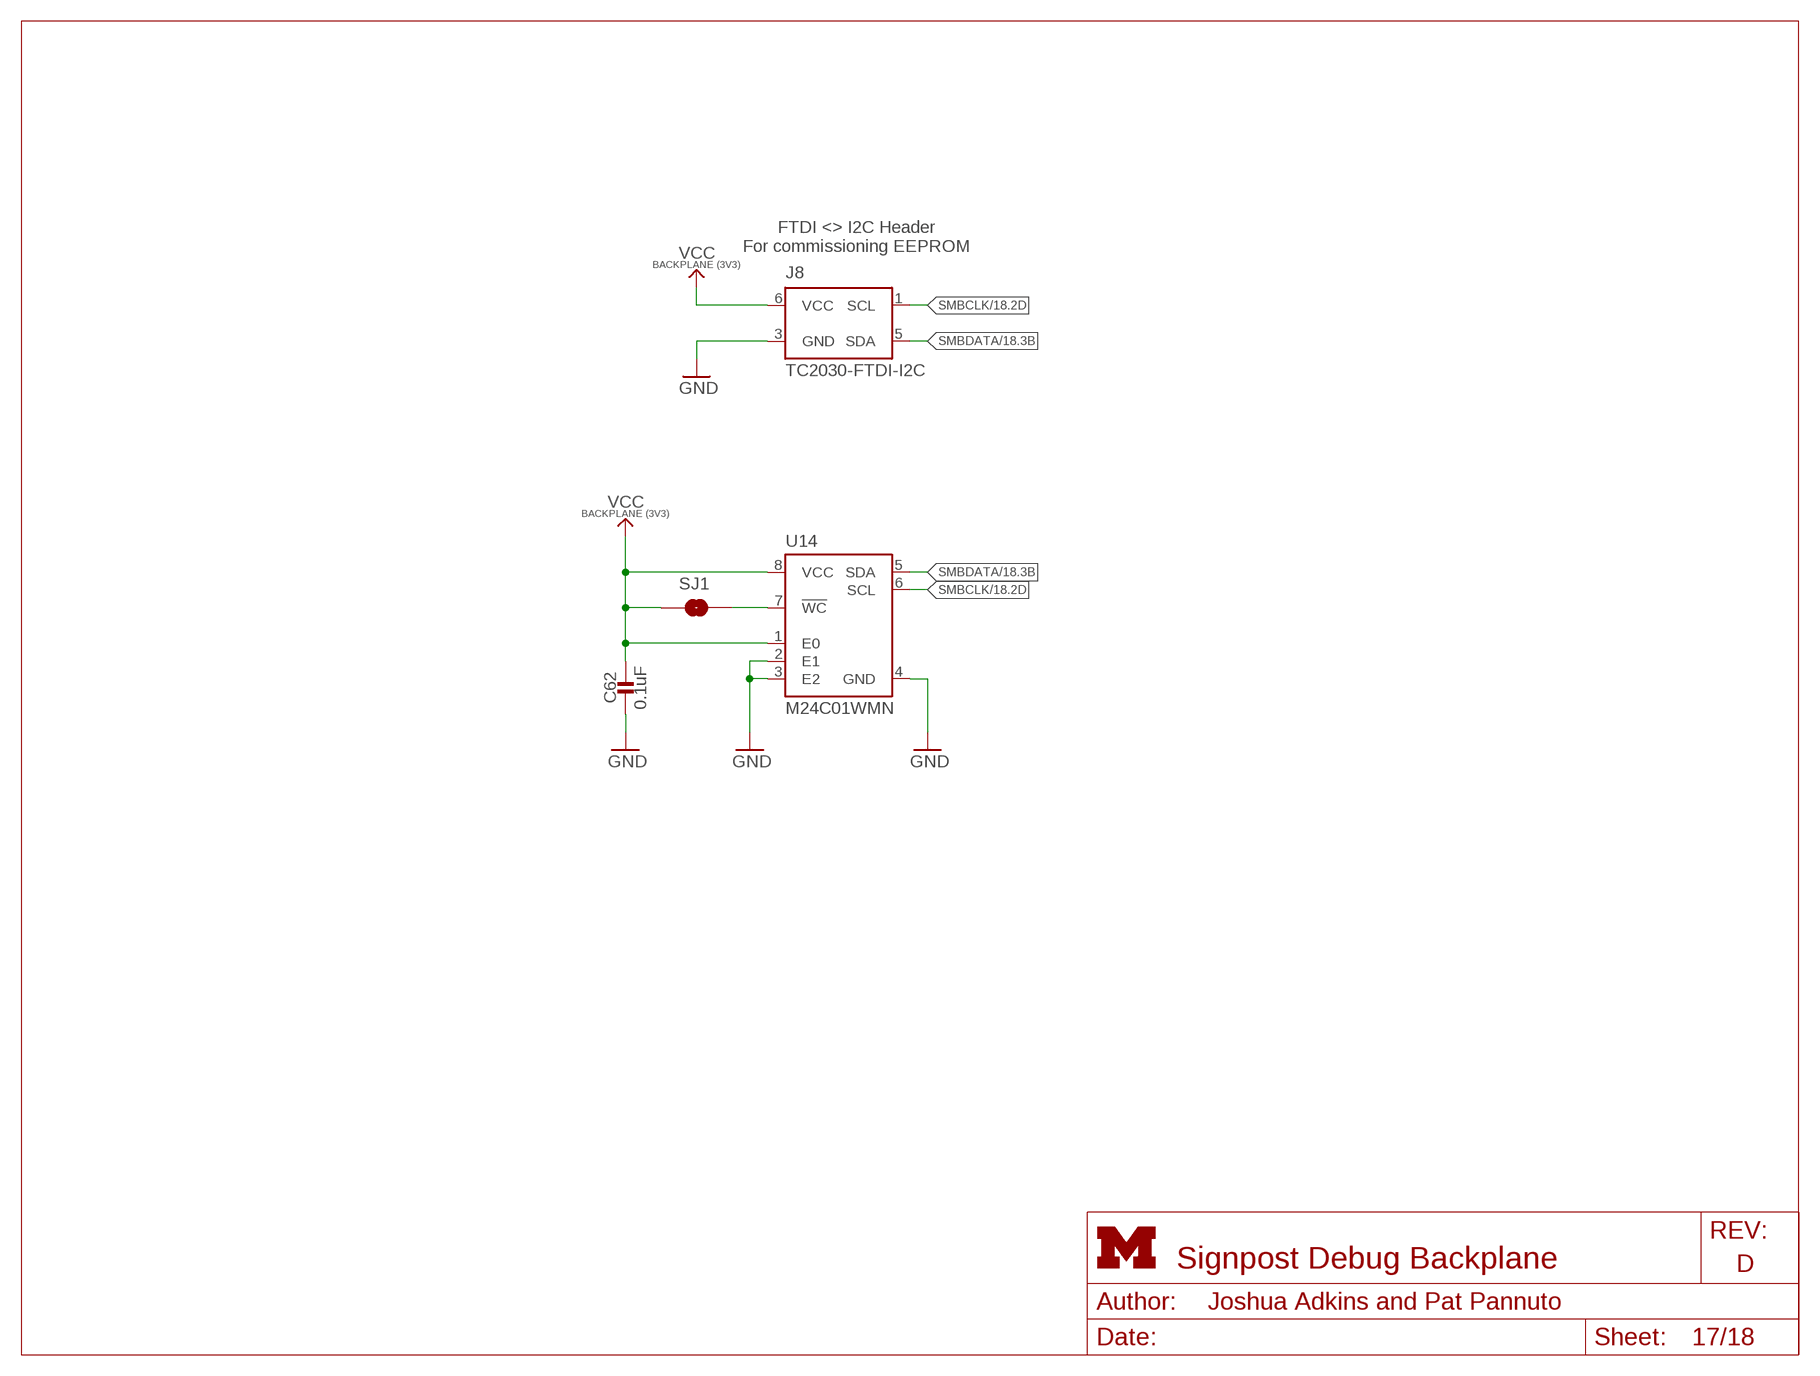
[diagram p16: schematic, sheet 17]
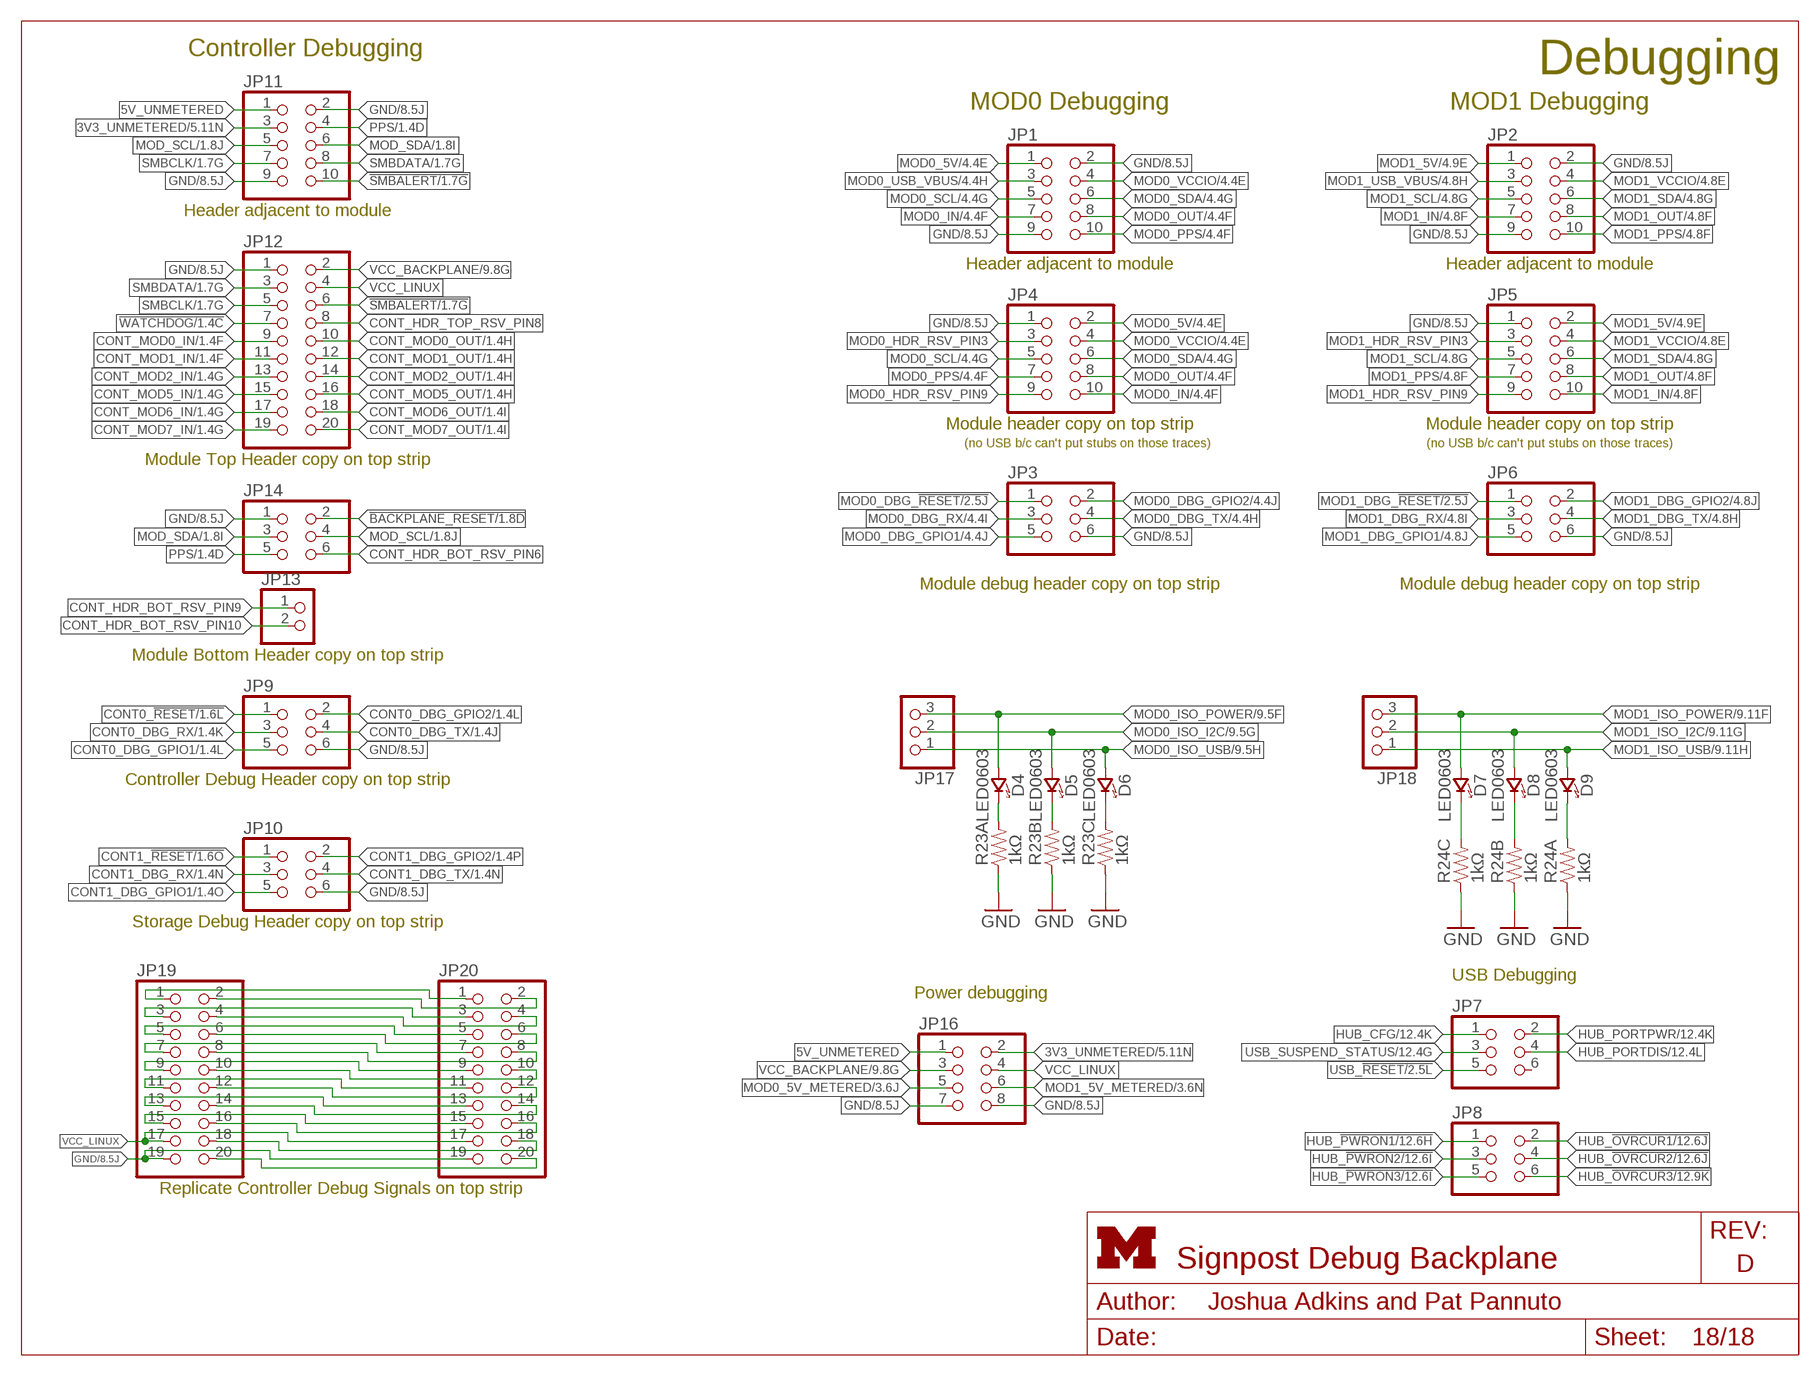
[diagram p17: schematic, sheet 18]

(export (version "E")
  (design (tool "Eeschema 10.0.6"))
  (components
    (comp (ref "C14")
      (value "0.1uF")
      (footprint "eagle-import:0603_CAP")
      (description "CAP CER 0.1UF 16V X7R 0603")
      (fields
        (field (name "DIGIKEY") "490-1532-1-ND")
        (field (name "MANUFACTURER") "Murata")
        (field (name "MPN") "GRM188R71C104KA01D")
      )
      (libsource (lib "eagle-import") (part "CAPACITOR0603_CAP"))
    )
    (comp (ref "C15")
      (value "0.1uF")
      (footprint "eagle-import:0603_CAP")
      (description "CAP CER 0.1UF 16V X7R 0603")
      (fields
        (field (name "DIGIKEY") "490-1532-1-ND")
        (field (name "MANUFACTURER") "Murata")
        (field (name "MPN") "GRM188R71C104KA01D")
      )
      (libsource (lib "eagle-import") (part "CAPACITOR0603_CAP"))
    )
    (comp (ref "C16")
      (value "0.1uF")
      (footprint "eagle-import:0603_CAP")
      (description "CAP CER 0.1UF 16V X7R 0603")
      (fields
        (field (name "DIGIKEY") "490-1532-1-ND")
        (field (name "MANUFACTURER") "Murata")
        (field (name "MPN") "GRM188R71C104KA01D")
      )
      (libsource (lib "eagle-import") (part "CAPACITOR0603_CAP"))
    )
    (comp (ref "C17")
      (value "0.1uF")
      (footprint "eagle-import:0603_CAP")
      (description "CAP CER 0.1UF 16V X7R 0603")
      (fields
        (field (name "DIGIKEY") "490-1532-1-ND")
        (field (name "MANUFACTURER") "Murata")
        (field (name "MPN") "GRM188R71C104KA01D")
      )
      (libsource (lib "eagle-import") (part "CAPACITOR0603_CAP"))
    )
    (comp (ref "C37")
      (value "0.1uF")
      (footprint "eagle-import:0603_CAP")
      (description "CAP CER 0.1UF 16V X7R 0603")
      (fields
        (field (name "DIGIKEY") "490-1532-1-ND")
        (field (name "MANUFACTURER") "Murata")
        (field (name "MPN") "GRM188R71C104KA01D")
      )
      (libsource (lib "eagle-import") (part "CAPACITOR0603_CAP"))
    )
    (comp (ref "C38")
      (value "0.1uF")
      (footprint "eagle-import:0603_CAP")
      (description "CAP CER 0.1UF 16V X7R 0603")
      (fields
        (field (name "DIGIKEY") "490-1532-1-ND")
        (field (name "MANUFACTURER") "Murata")
        (field (name "MPN") "GRM188R71C104KA01D")
      )
      (libsource (lib "eagle-import") (part "CAPACITOR0603_CAP"))
    )
    (comp (ref "C68")
      (value "4.7uF")
      (footprint "eagle-import:0603_CAP")
      (description "CAP CER 4.7UF 6.3V X7R 0603")
      (fields (field (name "MANUFACTURER") "Samsung") (field (name "MPN") "CL10B475KQ8NQNC"))
      (libsource (lib "eagle-import") (part "CAPACITOR0603_CAP"))
    )
    (comp (ref "C69")
      (value "4.7uF")
      (footprint "eagle-import:0603_CAP")
      (description "CAP CER 4.7UF 6.3V X7R 0603")
      (fields
        (field (name "DIGIKEY") "1276-2087-1-ND")
        (field (name "MANUFACTURER") "Samsung")
        (field (name "MPN") "CL10B475KQ8NQNC")
      )
      (libsource (lib "eagle-import") (part "CAPACITOR0603_CAP"))
    )
    (comp (ref "R38")
      (value "10kΩ")
      (footprint "eagle-import:0603-RES")
      (description "RES SMD 10K OHM 5% 1/10W 0603")
      (fields
        (field (name "DIGIKEY") "P10KGCT-ND")
        (field (name "MANUFACTURER") "Panasonic")
        (field (name "MPN") "ERJ-3GEYJ103V")
      )
      (libsource (lib "eagle-import") (part "RESISTOR0603_RES"))
    )
    (comp (ref "R39")
      (value "10kΩ")
      (footprint "eagle-import:0603-RES")
      (description "RES SMD 10K OHM 5% 1/10W 0603")
      (fields
        (field (name "DIGIKEY") "P10KGCT-ND")
        (field (name "MANUFACTURER") "Panasonic")
        (field (name "MPN") "ERJ-3GEYJ103V")
      )
      (libsource (lib "eagle-import") (part "RESISTOR0603_RES"))
    )
    (comp (ref "R40")
      (value "10kΩ")
      (footprint "eagle-import:0603-RES")
      (description "RES SMD 10K OHM 5% 1/10W 0603")
      (fields
        (field (name "DIGIKEY") "P10KGCT-ND")
        (field (name "MANUFACTURER") "Panasonic")
        (field (name "MPN") "ERJ-3GEYJ103V")
      )
      (libsource (lib "eagle-import") (part "RESISTOR0603_RES"))
    )
    (comp (ref "R41")
      (value "10kΩ")
      (footprint "eagle-import:0603-RES")
      (description "RES SMD 10K OHM 5% 1/10W 0603")
      (fields
        (field (name "DIGIKEY") "P10KGCT-ND")
        (field (name "MANUFACTURER") "Panasonic")
        (field (name "MPN") "ERJ-3GEYJ103V")
      )
      (libsource (lib "eagle-import") (part "RESISTOR0603_RES"))
    )
    (comp (ref "S15")
      (value "SIP3240X")
      (footprint "eagle-import:TDFN4")
      (libsource (lib "eagle-import") (part "SIP3240X"))
    )
    (comp (ref "S16")
      (value "SIP3240X")
      (footprint "eagle-import:TDFN4")
      (libsource (lib "eagle-import") (part "SIP3240X"))
    )
    (comp (ref "U7")
      (value "FXMA2102")
      (footprint "eagle-import:UMLP-8")
      (libsource (lib "eagle-import") (part "FXMA2102"))
    )
    (comp (ref "U8")
      (value "FXMA2102")
      (footprint "eagle-import:UMLP-8")
      (libsource (lib "eagle-import") (part "FXMA2102"))
    )
    (comp (ref "D14")
      (value "LED0603")
      (footprint "eagle-import:LED-0603")
      (description "LED BLUE CLEAR 0603 SMD")
      (fields (field (name "MANUFACTURER") "Lite-On") (field (name "MPN") "LTST-C193TBKT-5A"))
      (libsource (lib "eagle-import") (part "LED0603"))
    )
    (comp (ref "D15")
      (value "LED0603")
      (footprint "eagle-import:LED-0603")
      (description "LED BLUE CLEAR 0603 SMD")
      (fields (field (name "MANUFACTURER") "Lite-On") (field (name "MPN") "LTST-C193TBKT-5A"))
      (libsource (lib "eagle-import") (part "LED0603"))
    )
    (comp (ref "D16")
      (value "LED0603")
      (footprint "eagle-import:LED-0603")
      (description "LED BLUE CLEAR 0603 SMD")
      (fields (field (name "MANUFACTURER") "Lite-On") (field (name "MPN") "LTST-C193TBKT-5A"))
      (libsource (lib "eagle-import") (part "LED0603"))
    )
    (comp (ref "D17")
      (value "LED0603")
      (footprint "eagle-import:LED-0603")
      (description "LED BLUE CLEAR 0603 SMD")
      (fields (field (name "MANUFACTURER") "Lite-On") (field (name "MPN") "LTST-C193TBKT-5A"))
      (libsource (lib "eagle-import") (part "LED0603"))
    )
    (comp (ref "D18")
      (value "LED0603")
      (footprint "eagle-import:LED-0603")
      (description "LED BLUE CLEAR 0603 SMD")
      (fields (field (name "MANUFACTURER") "Lite-On") (field (name "MPN") "LTST-C193TBKT-5A"))
      (libsource (lib "eagle-import") (part "LED0603"))
    )
    (comp (ref "J6")
      (value "ML20")
      (footprint "eagle-import:ML20")
      (libsource (lib "eagle-import") (part "ML20"))
    )
    (comp (ref "R18")
      (value "1kΩ")
      (footprint "eagle-import:ARRAY-CONVEX-0603-4")
      (description "RES ARRAY 4 RES 1K OHM 1206")
      (fields
        (field (name "DIGIKEY") "Y9102CT-ND")
        (field (name "MANUFACTURER") "Panasonic")
        (field (name "MPN") "EXB-38V102JV")
      )
      (libsource (lib "eagle-import") (part "RESISTOR-ARRAY-41206"))
    )
    (comp (ref "R19")
      (value "1kΩ")
      (footprint "eagle-import:ARRAY-CONVEX-0603-4")
      (description "RES ARRAY 4 RES 1K OHM 1206")
      (fields
        (field (name "DIGIKEY") "Y9102CT-ND")
        (field (name "MANUFACTURER") "Panasonic")
        (field (name "MPN") "EXB-38V102JV")
      )
      (libsource (lib "eagle-import") (part "RESISTOR-ARRAY-41206"))
    )
    (comp (ref "R20")
      (value "1kΩ")
      (footprint "eagle-import:ARRAY-CONVEX-0603-4")
      (description "RES ARRAY 4 RES 1K OHM 1206")
      (fields
        (field (name "DIGIKEY") "Y9102CT-ND")
        (field (name "MANUFACTURER") "Panasonic")
        (field (name "MPN") "EXB-38V102JV")
      )
      (libsource (lib "eagle-import") (part "RESISTOR-ARRAY-41206"))
    )
    (comp (ref "R21")
      (value "1kΩ")
      (footprint "eagle-import:ARRAY-CONVEX-0603-4")
      (description "RES ARRAY 4 RES 1K OHM 1206")
      (fields
        (field (name "DIGIKEY") "Y9102CT-ND")
        (field (name "MANUFACTURER") "Panasonic")
        (field (name "MPN") "EXB-38V102JV")
      )
      (libsource (lib "eagle-import") (part "RESISTOR-ARRAY-41206"))
    )
    (comp (ref "R22")
      (value "1kΩ")
      (footprint "eagle-import:ARRAY-CONVEX-0603-4")
      (description "RES ARRAY 4 RES 1K OHM 1206")
      (fields
        (field (name "DIGIKEY") "Y9102CT-ND")
        (field (name "MANUFACTURER") "Panasonic")
        (field (name "MPN") "EXB-38V102JV")
      )
      (libsource (lib "eagle-import") (part "RESISTOR-ARRAY-41206"))
    )
    (comp (ref "S14")
      (value "RM106772BCB")
      (footprint "eagle-import:RM-SWITCH")
      (libsource (lib "eagle-import") (part "RM106772BCB"))
    )
    (comp (ref "S19")
      (value "SN74AHC4066-RGY")
      (footprint "eagle-import:S-PVQFN-N14-3.5MM")
      (libsource (lib "eagle-import") (part "SN74AHC4066-RGY"))
    )
    (comp (ref "S20")
      (value "SN74AHC4066-RGY")
      (footprint "eagle-import:S-PVQFN-N14-3.5MM")
      (libsource (lib "eagle-import") (part "SN74AHC4066-RGY"))
    )
    (comp (ref "S21")
      (value "SN74AHC4066-RGY")
      (footprint "eagle-import:S-PVQFN-N14-3.5MM")
      (libsource (lib "eagle-import") (part "SN74AHC4066-RGY"))
    )
    (comp (ref "S22")
      (value "SN74AHC4066-RGY")
      (footprint "eagle-import:S-PVQFN-N14-3.5MM")
      (libsource (lib "eagle-import") (part "SN74AHC4066-RGY"))
    )
    (comp (ref "S23")
      (value "SN74AHC4066-RGY")
      (footprint "eagle-import:S-PVQFN-N14-3.5MM")
      (libsource (lib "eagle-import") (part "SN74AHC4066-RGY"))
    )
    (comp (ref "S24")
      (value "TE_SSA12/SPDT")
      (footprint "eagle-import:TE_SSA12_SPDT")
      (libsource (lib "eagle-import") (part "TE_SSA12/SPDT"))
    )
    (comp (ref "J2")
      (value "BACKPLANE_GENERIC_MODULE_DEBUG")
      (footprint "eagle-import:BACKPLANE_MODULE_14PIN_8PIN")
      (libsource (lib "eagle-import") (part "BACKPLANE_GENERIC_MODULE_DEBUG"))
    )
    (comp (ref "J3")
      (value "BACKPLANE_GENERIC_MODULE_DEBUG")
      (footprint "eagle-import:BACKPLANE_MODULE_14PIN_8PIN")
      (libsource (lib "eagle-import") (part "BACKPLANE_GENERIC_MODULE_DEBUG"))
    )
    (comp (ref "S8")
      (value "PTS645SM43SMTR92")
      (footprint "eagle-import:PTS645")
      (libsource (lib "eagle-import") (part "PTS645SM43SMTR92"))
    )
    (comp (ref "S9")
      (value "PTS645SM43SMTR92")
      (footprint "eagle-import:PTS645")
      (libsource (lib "eagle-import") (part "PTS645SM43SMTR92"))
    )
    (comp (ref "SJ2")
      (value "SOLDERJUMPERNC")
      (footprint "eagle-import:SJ_2S")
      (libsource (lib "eagle-import") (part "SOLDERJUMPERNC"))
    )
    (comp (ref "SJ3")
      (value "SOLDERJUMPERNC")
      (footprint "eagle-import:SJ_2S")
      (libsource (lib "eagle-import") (part "SOLDERJUMPERNC"))
    )
    (comp (ref "TP4")
      (value "TEST_POINT_0.040IN")
      (footprint "eagle-import:TESTPOINT_0.040IN")
      (libsource (lib "eagle-import") (part "TEST_POINT_0.040IN"))
    )
    (comp (ref "TP5")
      (value "TEST_POINT_0.040IN")
      (footprint "eagle-import:TESTPOINT_0.040IN")
      (libsource (lib "eagle-import") (part "TEST_POINT_0.040IN"))
    )
    (comp (ref "TP6")
      (value "TEST_POINT_0.040IN")
      (footprint "eagle-import:TESTPOINT_0.040IN")
      (libsource (lib "eagle-import") (part "TEST_POINT_0.040IN"))
    )
    (comp (ref "TP7")
      (value "TEST_POINT_0.040IN")
      (footprint "eagle-import:TESTPOINT_0.040IN")
      (libsource (lib "eagle-import") (part "TEST_POINT_0.040IN"))
    )
    (comp (ref "C13")
      (value "0.01uF")
      (footprint "eagle-import:0603_CAP")
      (description "CAP CER 10000PF 50V X7R 0603")
      (fields (field (name "MANUFACTURER") "Murata") (field (name "MPN") "GRM188R71H103KA01D"))
      (libsource (lib "eagle-import") (part "CAPACITOR0603_CAP"))
    )
    (comp (ref "C58")
      (value "0.1uF")
      (footprint "eagle-import:0603_CAP")
      (description "CAP CER 0.1UF 16V X7R 0603")
      (fields
        (field (name "DIGIKEY") "490-1532-1-ND")
        (field (name "MANUFACTURER") "Murata")
        (field (name "MPN") "GRM188R71C104KA01D")
      )
      (libsource (lib "eagle-import") (part "CAPACITOR0603_CAP"))
    )
    (comp (ref "C59")
      (value "0.1uF")
      (footprint "eagle-import:0603_CAP")
      (description "CAP CER 0.1UF 16V X7R 0603")
      (fields
        (field (name "DIGIKEY") "490-1532-1-ND")
        (field (name "MANUFACTURER") "Murata")
        (field (name "MPN") "GRM188R71C104KA01D")
      )
      (libsource (lib "eagle-import") (part "CAPACITOR0603_CAP"))
    )
    (comp (ref "C60")
      (value "0.1uF")
      (footprint "eagle-import:0603_CAP")
      (description "CAP CER 0.1UF 16V X7R 0603")
      (fields
        (field (name "DIGIKEY") "490-1532-1-ND")
        (field (name "MANUFACTURER") "Murata")
        (field (name "MPN") "GRM188R71C104KA01D")
      )
      (libsource (lib "eagle-import") (part "CAPACITOR0603_CAP"))
    )
    (comp (ref "C61")
      (value "0.1uF")
      (footprint "eagle-import:0603_CAP")
      (description "CAP CER 0.1UF 16V X7R 0603")
      (fields
        (field (name "DIGIKEY") "490-1532-1-ND")
        (field (name "MANUFACTURER") "Murata")
        (field (name "MPN") "GRM188R71C104KA01D")
      )
      (libsource (lib "eagle-import") (part "CAPACITOR0603_CAP"))
    )
    (comp (ref "C66")
      (value "2.2uF")
      (footprint "eagle-import:0603_CAP")
      (description "CAP CER 2.2UF 16V 10% X5R 0603")
      (fields (field (name "MANUFACTURER") "Murata") (field (name "MPN") "GRM188R61C225KE15D"))
      (libsource (lib "eagle-import") (part "CAPACITOR0603_CAP"))
    )
    (comp (ref "C67")
      (value "2.2uF")
      (footprint "eagle-import:0603_CAP")
      (description "CAP CER 2.2UF 16V 10% X5R 0603")
      (fields (field (name "MANUFACTURER") "Murata") (field (name "MPN") "GRM188R61C225KE15D"))
      (libsource (lib "eagle-import") (part "CAPACITOR0603_CAP"))
    )
    (comp (ref "C71")
      (value "4.7uF")
      (footprint "eagle-import:0603_CAP")
      (description "CAP CER 4.7UF 6.3V X7R 0603")
      (fields
        (field (name "DIGIKEY") "1276-2087-1-ND")
        (field (name "MANUFACTURER") "Samsung")
        (field (name "MPN") "CL10B475KQ8NQNC")
      )
      (libsource (lib "eagle-import") (part "CAPACITOR0603_CAP"))
    )
    (comp (ref "D23")
      (value "LED0603")
      (footprint "eagle-import:LED-0603")
      (description "LED GREEN CLEAR 0603 SMD")
      (fields (field (name "MANUFACTURER") "Lite-On") (field (name "MPN") "LTST-C191KGKT"))
      (libsource (lib "eagle-import") (part "LED0603"))
    )
    (comp (ref "J7")
      (value "PJ-102AH")
      (footprint "eagle-import:PJ-102AH")
      (libsource (lib "eagle-import") (part "PJ-102AH"))
    )
    (comp (ref "Q8")
      (value "MOSFET-NCHANNELSMD")
      (footprint "eagle-import:SOT23-3")
      (description "MOSFET N-CH 20V 2.6A SOT-23")
      (fields (field (name "MANUFACTURER") "Vishay Siliconix") (field (name "MPN") "SI2302CDS-T1-E3"))
      (libsource (lib "eagle-import") (part "MOSFET-NCHANNELSMD"))
    )
    (comp (ref "R1")
      (value "0.017Ω")
      (footprint "eagle-import:0805_RES")
      (description "RES SMD 0.017 OHM 1% 1/2W 0805")
      (fields (field (name "MANUFACTURER") "Vishay Dale") (field (name "MPN") "WSLP0805R0170FEB"))
      (libsource (lib "eagle-import") (part "RESISTOR0805_RES"))
    )
    (comp (ref "R2")
      (value "0.017Ω")
      (footprint "eagle-import:0805_RES")
      (description "RES SMD 0.017 OHM 1% 1/2W 0805")
      (fields
        (field (name "DIGIKEY") "WSLPB-.017CT-ND")
        (field (name "MANUFACTURER") "Vishay Dale")
        (field (name "MPN") "WSLP0805R0170FEB")
      )
      (libsource (lib "eagle-import") (part "RESISTOR0805_RES"))
    )
    (comp (ref "R3")
      (value "0.017Ω")
      (footprint "eagle-import:0805_RES")
      (description "RES SMD 0.017 OHM 1% 1/2W 0805")
      (fields
        (field (name "DIGIKEY") "WSLPB-.017CT-ND")
        (field (name "MANUFACTURER") "Vishay Dale")
        (field (name "MPN") "WSLP0805R0170FEB")
      )
      (libsource (lib "eagle-import") (part "RESISTOR0805_RES"))
    )
    (comp (ref "R4")
      (value "0.017Ω")
      (footprint "eagle-import:0805_RES")
      (description "RES SMD 0.017 OHM 1% 1/2W 0805")
      (fields
        (field (name "DIGIKEY") "WSLPB-.017CT-ND")
        (field (name "MANUFACTURER") "Vishay Dale")
        (field (name "MPN") "WSLP0805R0170FEB")
      )
      (libsource (lib "eagle-import") (part "RESISTOR0805_RES"))
    )
    (comp (ref "R15")
      (value "50Ω")
      (footprint "eagle-import:0603-RES")
      (description "RES SMD 49.9 OHM 1% 1/10W 0603")
      (fields
        (field (name "DIGIKEY") "RHM49.9BJCT-ND")
        (field (name "MANUFACTURER") "Rohm")
        (field (name "MPN") "TRR03EZPF49R9")
      )
      (libsource (lib "eagle-import") (part "RESISTOR0603_RES"))
    )
    (comp (ref "R17")
      (value "50Ω")
      (footprint "eagle-import:0603-RES")
      (description "RES SMD 49.9 OHM 1% 1/10W 0603")
      (fields
        (field (name "DIGIKEY") "RHM49.9BJCT-ND")
        (field (name "MANUFACTURER") "Rohm")
        (field (name "MPN") "TRR03EZPF49R9")
      )
      (libsource (lib "eagle-import") (part "RESISTOR0603_RES"))
    )
    (comp (ref "R32")
      (value "1.8kΩ")
      (footprint "eagle-import:ARRAY-CONVEX-0603-4")
      (description "RES ARRAY 4 RES 1.8K OHM 1206")
      (fields
        (field (name "DIGIKEY") "Y9182CT-ND")
        (field (name "MANUFACTURER") "Panasonic")
        (field (name "MPN") "EXB-38V182JV")
      )
      (libsource (lib "eagle-import") (part "RESISTOR-ARRAY-41206"))
    )
    (comp (ref "R33")
      (value "1.8kΩ")
      (footprint "eagle-import:ARRAY-CONVEX-0603-4")
      (description "RES ARRAY 4 RES 1.8K OHM 1206")
      (fields
        (field (name "MANUFACTURER") "Panasonic")
        (field (name "MPN") "EXB-38V182JV")
        (field (name "DIGIKEY") "Y9182CT-ND")
      )
      (libsource (lib "eagle-import") (part "RESISTOR-ARRAY-41206"))
    )
    (comp (ref "R34")
      (value "1.8kΩ")
      (footprint "eagle-import:ARRAY-CONVEX-0603-4")
      (description "RES ARRAY 4 RES 1.8K OHM 1206")
      (fields
        (field (name "DIGIKEY") "Y9182CT-ND")
        (field (name "MANUFACTURER") "Panasonic")
        (field (name "MPN") "EXB-38V182JV")
      )
      (libsource (lib "eagle-import") (part "RESISTOR-ARRAY-41206"))
    )
    (comp (ref "R35")
      (value "1.8kΩ")
      (footprint "eagle-import:ARRAY-CONVEX-0603-4")
      (description "RES ARRAY 4 RES 1.8K OHM 1206")
      (fields
        (field (name "MANUFACTURER") "Panasonic")
        (field (name "MPN") "EXB-38V182JV")
        (field (name "DIGIKEY") "Y9182CT-ND")
      )
      (libsource (lib "eagle-import") (part "RESISTOR-ARRAY-41206"))
    )
    (comp (ref "R48")
      (value "10kΩ")
      (footprint "eagle-import:0603-RES")
      (description "RES SMD 10K OHM 5% 1/10W 0603")
      (fields
        (field (name "DIGIKEY") "P10KGCT-ND")
        (field (name "MANUFACTURER") "Panasonic")
        (field (name "MPN") "ERJ-3GEYJ103V")
      )
      (libsource (lib "eagle-import") (part "RESISTOR0603_RES"))
    )
    (comp (ref "U9")
      (value "LTC2941")
      (footprint "eagle-import:DFN-6-2MMX3MM")
      (libsource (lib "eagle-import") (part "LTC2941"))
    )
    (comp (ref "U10")
      (value "LTC2943")
      (footprint "eagle-import:DFN-8")
      (libsource (lib "eagle-import") (part "LTC2943"))
    )
    (comp (ref "U11")
      (value "LTC2943")
      (footprint "eagle-import:DFN-8")
      (libsource (lib "eagle-import") (part "LTC2943"))
    )
    (comp (ref "U12")
      (value "LTC2943")
      (footprint "eagle-import:DFN-8")
      (libsource (lib "eagle-import") (part "LTC2943"))
    )
    (comp (ref "U13")
      (value "LTC4360")
      (footprint "eagle-import:SC70-8")
      (libsource (lib "eagle-import") (part "LTC4360"))
    )
    (comp (ref "U16")
      (value "MAX8887EZK33+T")
      (footprint "eagle-import:SOT-23-5")
      (libsource (lib "eagle-import") (part "MAX8887EZK33+T"))
    )
    (comp (ref "U22")
      (value "PCA9544AQFN-N20")
      (footprint "eagle-import:QFN-N20")
      (libsource (lib "eagle-import") (part "PCA9544AQFN-N20"))
    )
    (comp (ref "C49")
      (value "0.1uF")
      (footprint "eagle-import:0603_CAP")
      (description "CAP CER 0.1UF 16V X7R 0603")
      (fields
        (field (name "DIGIKEY") "490-1532-1-ND")
        (field (name "MANUFACTURER") "Murata")
        (field (name "MPN") "GRM188R71C104KA01D")
      )
      (libsource (lib "eagle-import") (part "CAPACITOR0603_CAP"))
    )
    (comp (ref "C50")
      (value "0.1uF")
      (footprint "eagle-import:0603_CAP")
      (description "CAP CER 0.1UF 16V X7R 0603")
      (fields
        (field (name "DIGIKEY") "490-1532-1-ND")
        (field (name "MANUFACTURER") "Murata")
        (field (name "MPN") "GRM188R71C104KA01D")
      )
      (libsource (lib "eagle-import") (part "CAPACITOR0603_CAP"))
    )
    (comp (ref "C51")
      (value "0.1uF")
      (footprint "eagle-import:0603_CAP")
      (description "CAP CER 0.1UF 16V X7R 0603")
      (fields
        (field (name "DIGIKEY") "490-1532-1-ND")
        (field (name "MANUFACTURER") "Murata")
        (field (name "MPN") "GRM188R71C104KA01D")
      )
      (libsource (lib "eagle-import") (part "CAPACITOR0603_CAP"))
    )
    (comp (ref "C52")
      (value "0.1uF")
      (footprint "eagle-import:0603_CAP")
      (description "CAP CER 0.1UF 16V X7R 0603")
      (fields
        (field (name "DIGIKEY") "490-1532-1-ND")
        (field (name "MANUFACTURER") "Murata")
        (field (name "MPN") "GRM188R71C104KA01D")
      )
      (libsource (lib "eagle-import") (part "CAPACITOR0603_CAP"))
    )
    (comp (ref "D19")
      (value "LED0603")
      (footprint "eagle-import:LED-0603")
      (description "LED RED CLEAR 0603 SMD")
      (fields (field (name "MANUFACTURER") "Lite-On") (field (name "MPN") "LTST-C191KRKT"))
      (libsource (lib "eagle-import") (part "LED0603"))
    )
    (comp (ref "D20")
      (value "LED0603")
      (footprint "eagle-import:LED-0603")
      (description "LED GREEN CLEAR 0603 SMD")
      (fields (field (name "MANUFACTURER") "Lite-On") (field (name "MPN") "LTST-C191KGKT"))
      (libsource (lib "eagle-import") (part "LED0603"))
    )
    (comp (ref "D21")
      (value "LED0603")
      (footprint "eagle-import:LED-0603")
      (description "LED RED CLEAR 0603 SMD")
      (fields (field (name "MANUFACTURER") "Lite-On") (field (name "MPN") "LTST-C191KRKT"))
      (libsource (lib "eagle-import") (part "LED0603"))
    )
    (comp (ref "D22")
      (value "LED0603")
      (footprint "eagle-import:LED-0603")
      (description "LED GREEN CLEAR 0603 SMD")
      (fields (field (name "MANUFACTURER") "Lite-On") (field (name "MPN") "LTST-C191KGKT"))
      (libsource (lib "eagle-import") (part "LED0603"))
    )
    (comp (ref "Q4")
      (value "DMN32D2LDF")
      (footprint "eagle-import:SOT353")
      (fields (field (name "MANUFACTURER") "Diodes Incorporated") (field (name "MPN") "DMN32D2LDF-7"))
      (libsource (lib "eagle-import") (part "DMN32D2LDF"))
    )
    (comp (ref "Q5")
      (value "DMN32D2LDF")
      (footprint "eagle-import:SOT353")
      (fields (field (name "MANUFACTURER") "Diodes Incorporated") (field (name "MPN") "DMN32D2LDF-7"))
      (libsource (lib "eagle-import") (part "DMN32D2LDF"))
    )
    (comp (ref "R73")
      (value "1MΩ")
      (footprint "eagle-import:0603-RES")
      (description "RES SMD 1M OHM 5% 1/4W 0603")
      (fields
        (field (name "DIGIKEY") "RHM1MDCT-ND")
        (field (name "MANUFACTURER") "Rohm")
        (field (name "MPN") "ESR03EZPJ105")
      )
      (libsource (lib "eagle-import") (part "RESISTOR0603_RES"))
    )
    (comp (ref "R74")
      (value "1MΩ")
      (footprint "eagle-import:0603-RES")
      (description "RES SMD 1M OHM 5% 1/4W 0603")
      (fields
        (field (name "DIGIKEY") "RHM1MDCT-ND")
        (field (name "MANUFACTURER") "Rohm")
        (field (name "MPN") "ESR03EZPJ105")
      )
      (libsource (lib "eagle-import") (part "RESISTOR0603_RES"))
    )
    (comp (ref "R75")
      (value "1MΩ")
      (footprint "eagle-import:0603-RES")
      (description "RES SMD 1M OHM 5% 1/4W 0603")
      (fields
        (field (name "DIGIKEY") "RHM1MDCT-ND")
        (field (name "MANUFACTURER") "Rohm")
        (field (name "MPN") "ESR03EZPJ105")
      )
      (libsource (lib "eagle-import") (part "RESISTOR0603_RES"))
    )
    (comp (ref "R76")
      (value "1MΩ")
      (footprint "eagle-import:0603-RES")
      (description "RES SMD 1M OHM 5% 1/4W 0603")
      (fields
        (field (name "DIGIKEY") "RHM1MDCT-ND")
        (field (name "MANUFACTURER") "Rohm")
        (field (name "MPN") "ESR03EZPJ105")
      )
      (libsource (lib "eagle-import") (part "RESISTOR0603_RES"))
    )
    (comp (ref "U4")
      (value "FT232RQ")
      (footprint "eagle-import:QFN32")
      (libsource (lib "eagle-import") (part "FT232RQ"))
    )
    (comp (ref "U5")
      (value "FT232RQ")
      (footprint "eagle-import:QFN32")
      (libsource (lib "eagle-import") (part "FT232RQ"))
    )
    (comp (ref "C1")
      (value "8pF")
      (footprint "eagle-import:0603_CAP")
      (description "CAP CER 8PF 50V C0G/NP0 0603")
      (fields (field (name "MANUFACTURER") "Murata") (field (name "MPN") "GRM1885C1H8R0DA01D"))
      (libsource (lib "eagle-import") (part "CAPACITOR0603_CAP"))
    )
    (comp (ref "C2")
      (value "8pF")
      (footprint "eagle-import:0603_CAP")
      (description "CAP CER 8PF 50V C0G/NP0 0603")
      (fields (field (name "MANUFACTURER") "Murata") (field (name "MPN") "GRM1885C1H8R0DA01D"))
      (libsource (lib "eagle-import") (part "CAPACITOR0603_CAP"))
    )
    (comp (ref "C39")
      (value "0.1uF")
      (footprint "eagle-import:0603_CAP")
      (description "CAP CER 0.1UF 16V X7R 0603")
      (fields (field (name "MANUFACTURER") "Murata") (field (name "MPN") "GRM188R71C104KA01D"))
      (libsource (lib "eagle-import") (part "CAPACITOR0603_CAP"))
    )
    (comp (ref "C40")
      (value "0.1uF")
      (footprint "eagle-import:0603_CAP")
      (description "CAP CER 0.1UF 16V X7R 0603")
      (fields (field (name "MANUFACTURER") "Murata") (field (name "MPN") "GRM188R71C104KA01D"))
      (libsource (lib "eagle-import") (part "CAPACITOR0603_CAP"))
    )
    (comp (ref "C41")
      (value "0.1uF")
      (footprint "eagle-import:0603_CAP")
      (description "CAP CER 0.1UF 16V X7R 0603")
      (fields (field (name "MANUFACTURER") "Murata") (field (name "MPN") "GRM188R71C104KA01D"))
      (libsource (lib "eagle-import") (part "CAPACITOR0603_CAP"))
    )
    (comp (ref "C42")
      (value "0.1uF")
      (footprint "eagle-import:0603_CAP")
      (description "CAP CER 0.1UF 16V X7R 0603")
      (fields (field (name "MANUFACTURER") "Murata") (field (name "MPN") "GRM188R71C104KA01D"))
      (libsource (lib "eagle-import") (part "CAPACITOR0603_CAP"))
    )
    (comp (ref "C43")
      (value "0.1uF")
      (footprint "eagle-import:0603_CAP")
      (description "CAP CER 0.1UF 16V X7R 0603")
      (fields (field (name "MANUFACTURER") "Murata") (field (name "MPN") "GRM188R71C104KA01D"))
      (libsource (lib "eagle-import") (part "CAPACITOR0603_CAP"))
    )
    (comp (ref "C44")
      (value "0.1uF")
      (footprint "eagle-import:0603_CAP")
      (description "CAP CER 0.1UF 16V X7R 0603")
      (fields (field (name "MANUFACTURER") "Murata") (field (name "MPN") "GRM188R71C104KA01D"))
      (libsource (lib "eagle-import") (part "CAPACITOR0603_CAP"))
    )
    (comp (ref "C55")
      (value "0.1uF")
      (footprint "eagle-import:0603_CAP")
      (description "CAP CER 0.1UF 16V X7R 0603")
      (fields (field (name "MANUFACTURER") "Murata") (field (name "MPN") "GRM188R71C104KA01D"))
      (libsource (lib "eagle-import") (part "CAPACITOR0603_CAP"))
    )
    (comp (ref "C56")
      (value "0.1uF")
      (footprint "eagle-import:0603_CAP")
      (description "CAP CER 0.1UF 16V X7R 0603")
      (fields (field (name "MANUFACTURER") "Murata") (field (name "MPN") "GRM188R71C104KA01D"))
      (libsource (lib "eagle-import") (part "CAPACITOR0603_CAP"))
    )
    (comp (ref "C63")
      (value "0.1uF")
      (footprint "eagle-import:0603_CAP")
      (description "CAP CER 0.1UF 16V X7R 0603")
      (fields (field (name "MANUFACTURER") "Murata") (field (name "MPN") "GRM188R71C104KA01D"))
      (libsource (lib "eagle-import") (part "CAPACITOR0603_CAP"))
    )
    (comp (ref "C73")
      (value "6.8uF")
      (footprint "eagle-import:0603_CAP")
      (description "CAP CER 6.8UF 6.3V X5R 0603")
      (fields (field (name "MANUFACTURER") "TDK") (field (name "MPN") "C1608X5R0J685K080AB"))
      (libsource (lib "eagle-import") (part "CAPACITOR0603_CAP"))
    )
    (comp (ref "D24")
      (value "LED0603")
      (footprint "eagle-import:LED-0603")
      (description "LED RED CLEAR 0603 SMD")
      (fields (field (name "MANUFACTURER") "Lite-On") (field (name "MPN") "LTST-C191KRKT"))
      (libsource (lib "eagle-import") (part "LED0603"))
    )
    (comp (ref "D25")
      (value "LED0603")
      (footprint "eagle-import:LED-0603")
      (description "LED GREEN CLEAR 0603 SMD")
      (fields (field (name "MANUFACTURER") "Lite-On") (field (name "MPN") "LTST-C191KGKT"))
      (libsource (lib "eagle-import") (part "LED0603"))
    )
    (comp (ref "FB1")
      (value "1.5kR")
      (footprint "eagle-import:0603_CAP")
      (description "FERRITE BEAD 1.5 KOHM 0603 1LN")
      (fields (field (name "MANUFACTURER") "Murata") (field (name "MPN") "BLM18HE152SN1D"))
      (libsource (lib "eagle-import") (part "FERRITE_BEAD0603"))
    )
    (comp (ref "L1")
      (value "22uH")
      (footprint "eagle-import:1212")
      (fields (field (name "MANUFACTURER") "Murata") (field (name "MPN") "LQH3NPN220MJ0L"))
      (libsource (lib "eagle-import") (part "LHQ3NP"))
    )
    (comp (ref "Q6")
      (value "DMN32D2LDF")
      (footprint "eagle-import:SOT353")
      (fields (field (name "MANUFACTURER") "Diodes Incorporated") (field (name "MPN") "DMN32D2LDF-7"))
      (libsource (lib "eagle-import") (part "DMN32D2LDF"))
    )
    (comp (ref "R49")
      (value "10kΩ")
      (footprint "eagle-import:0603-RES")
      (description "RES SMD 10K OHM 5% 1/10W 0603")
      (fields (field (name "MANUFACTURER") "Panasonic") (field (name "MPN") "ERJ-3GEYJ103V"))
      (libsource (lib "eagle-import") (part "RESISTOR0603_RES"))
    )
    (comp (ref "R65")
      (value "100kΩ")
      (footprint "eagle-import:0603-RES")
      (description "RES SMD 100K OHM 1% 1/16W 0402")
      (fields (field (name "MANUFACTURER") "Samsung") (field (name "MPN") "RC1005F104CS"))
      (libsource (lib "eagle-import") (part "RESISTOR0603_RES"))
    )
    (comp (ref "R66")
      (value "100kΩ")
      (footprint "eagle-import:0603-RES")
      (description "RES SMD 100K OHM 1% 1/16W 0402")
      (fields (field (name "MANUFACTURER") "Samsung") (field (name "MPN") "RC1005F104CS"))
      (libsource (lib "eagle-import") (part "RESISTOR0603_RES"))
    )
    (comp (ref "R77")
      (value "1MΩ")
      (footprint "eagle-import:0603-RES")
      (description "RES SMD 1M OHM 5% 1/4W 0603")
      (fields
        (field (name "DIGIKEY") "RHM1MDCT-ND")
        (field (name "MANUFACTURER") "Rohm")
        (field (name "MPN") "ESR03EZPJ105")
      )
      (libsource (lib "eagle-import") (part "RESISTOR0603_RES"))
    )
    (comp (ref "R78")
      (value "1MΩ")
      (footprint "eagle-import:0603-RES")
      (description "RES SMD 1M OHM 5% 1/4W 0603")
      (fields
        (field (name "DIGIKEY") "RHM1MDCT-ND")
        (field (name "MANUFACTURER") "Rohm")
        (field (name "MPN") "ESR03EZPJ105")
      )
      (libsource (lib "eagle-import") (part "RESISTOR0603_RES"))
    )
    (comp (ref "R85")
      (value "DNP")
      (footprint "eagle-import:0603-RES")
      (libsource (lib "eagle-import") (part "RESISTOR0603_RES"))
    )
    (comp (ref "S12")
      (value "PTS645SM43SMTR92")
      (footprint "eagle-import:PTS645")
      (libsource (lib "eagle-import") (part "PTS645SM43SMTR92"))
    )
    (comp (ref "U1")
      (value "FT232RQ")
      (footprint "eagle-import:QFN32")
      (libsource (lib "eagle-import") (part "FT232RQ"))
    )
    (comp (ref "U6")
      (value "FT232RQ")
      (footprint "eagle-import:QFN32")
      (libsource (lib "eagle-import") (part "FT232RQ"))
    )
    (comp (ref "U23")
      (value "SAM4LC8AA")
      (footprint "eagle-import:QFN-48-7MM")
      (libsource (lib "eagle-import") (part "SAM4LC8AA"))
    )
    (comp (ref "Y3")
      (value "FH1600015")
      (footprint "eagle-import:FHXXX")
      (fields (field (name "MANUFACTURER") "Diodes Incorporated"))
      (libsource (lib "eagle-import") (part "FH1600015"))
    )
    (comp (ref "C53")
      (value "0.1uF")
      (footprint "eagle-import:0603_CAP")
      (description "CAP CER 0.1UF 16V X7R 0603")
      (fields
        (field (name "DIGIKEY") "490-1532-1-ND")
        (field (name "MANUFACTURER") "Murata")
        (field (name "MPN") "GRM188R71C104KA01D")
      )
      (libsource (lib "eagle-import") (part "CAPACITOR0603_CAP"))
    )
    (comp (ref "J4")
      (value "MICRO_USB_B_HIROSE_ZX62R-B-5P")
      (footprint "eagle-import:USB_MICRO_B-HIROSE-ZX62R-B-5P")
      (libsource (lib "eagle-import") (part "MICRO_USB_B_HIROSE_ZX62R-B-5P"))
    )
    (comp (ref "Q1")
      (value "DMN32D2LDF")
      (footprint "eagle-import:SOT353")
      (fields (field (name "MANUFACTURER") "Diodes Incorporated") (field (name "MPN") "DMN32D2LDF-7"))
      (libsource (lib "eagle-import") (part "DMN32D2LDF"))
    )
    (comp (ref "R67")
      (value "100kΩ")
      (footprint "eagle-import:0603-RES")
      (description "RES SMD 100K OHM 1% 1/16W 0402")
      (fields
        (field (name "DIGIKEY") "1276-3432-1-ND")
        (field (name "MANUFACTURER") "Samsung")
        (field (name "MPN") "RC1005F104CS")
      )
      (libsource (lib "eagle-import") (part "RESISTOR0603_RES"))
    )
    (comp (ref "R68")
      (value "100kΩ")
      (footprint "eagle-import:0603-RES")
      (description "RES SMD 100K OHM 1% 1/16W 0402")
      (fields
        (field (name "DIGIKEY") "1276-3432-1-ND")
        (field (name "MANUFACTURER") "Samsung")
        (field (name "MPN") "RC1005F104CS")
      )
      (libsource (lib "eagle-import") (part "RESISTOR0603_RES"))
    )
    (comp (ref "U30")
      (value "TS3USB30E")
      (footprint "eagle-import:UQFN-10")
      (libsource (lib "eagle-import") (part "TS3USB30E"))
    )
    (comp (ref "C45")
      (value "0.1uF")
      (footprint "eagle-import:0603_CAP")
      (description "CAP CER 0.1UF 16V X7R 0603")
      (fields
        (field (name "DIGIKEY") "490-1532-1-ND")
        (field (name "MANUFACTURER") "Murata")
        (field (name "MPN") "GRM188R71C104KA01D")
      )
      (libsource (lib "eagle-import") (part "CAPACITOR0603_CAP"))
    )
    (comp (ref "C46")
      (value "0.1uF")
      (footprint "eagle-import:0603_CAP")
      (description "CAP CER 0.1UF 16V X7R 0603")
      (fields
        (field (name "DIGIKEY") "490-1532-1-ND")
        (field (name "MANUFACTURER") "Murata")
        (field (name "MPN") "GRM188R71C104KA01D")
      )
      (libsource (lib "eagle-import") (part "CAPACITOR0603_CAP"))
    )
    (comp (ref "C47")
      (value "0.1uF")
      (footprint "eagle-import:0603_CAP")
      (description "CAP CER 0.1UF 16V X7R 0603")
      (fields
        (field (name "DIGIKEY") "490-1532-1-ND")
        (field (name "MANUFACTURER") "Murata")
        (field (name "MPN") "GRM188R71C104KA01D")
      )
      (libsource (lib "eagle-import") (part "CAPACITOR0603_CAP"))
    )
    (comp (ref "C48")
      (value "0.1uF")
      (footprint "eagle-import:0603_CAP")
      (description "CAP CER 0.1UF 16V X7R 0603")
      (fields
        (field (name "DIGIKEY") "490-1532-1-ND")
        (field (name "MANUFACTURER") "Murata")
        (field (name "MPN") "GRM188R71C104KA01D")
      )
      (libsource (lib "eagle-import") (part "CAPACITOR0603_CAP"))
    )
    (comp (ref "D10")
      (value "LED0603")
      (footprint "eagle-import:LED-0603")
      (description "LED RED CLEAR 0603 SMD")
      (fields (field (name "MANUFACTURER") "Lite-On") (field (name "MPN") "LTST-C191KRKT"))
      (libsource (lib "eagle-import") (part "LED0603"))
    )
    (comp (ref "D11")
      (value "LED0603")
      (footprint "eagle-import:LED-0603")
      (description "LED GREEN CLEAR 0603 SMD")
      (fields (field (name "MANUFACTURER") "Lite-On") (field (name "MPN") "LTST-C191KGKT"))
      (libsource (lib "eagle-import") (part "LED0603"))
    )
    (comp (ref "D12")
      (value "LED0603")
      (footprint "eagle-import:LED-0603")
      (description "LED RED CLEAR 0603 SMD")
      (fields (field (name "MANUFACTURER") "Lite-On") (field (name "MPN") "LTST-C191KRKT"))
      (libsource (lib "eagle-import") (part "LED0603"))
    )
    (comp (ref "D13")
      (value "LED0603")
      (footprint "eagle-import:LED-0603")
      (description "LED GREEN CLEAR 0603 SMD")
      (fields (field (name "MANUFACTURER") "Lite-On") (field (name "MPN") "LTST-C191KGKT"))
      (libsource (lib "eagle-import") (part "LED0603"))
    )
    (comp (ref "Q2")
      (value "DMN32D2LDF")
      (footprint "eagle-import:SOT353")
      (fields (field (name "MANUFACTURER") "Diodes Incorporated") (field (name "MPN") "DMN32D2LDF-7"))
      (libsource (lib "eagle-import") (part "DMN32D2LDF"))
    )
    (comp (ref "Q3")
      (value "DMN32D2LDF")
      (footprint "eagle-import:SOT353")
      (fields (field (name "MANUFACTURER") "Diodes Incorporated") (field (name "MPN") "DMN32D2LDF-7"))
      (libsource (lib "eagle-import") (part "DMN32D2LDF"))
    )
    (comp (ref "R69")
      (value "1MΩ")
      (footprint "eagle-import:0603-RES")
      (description "RES SMD 1M OHM 5% 1/4W 0603")
      (fields (field (name "MANUFACTURER") "Rohm") (field (name "MPN") "ESR03EZPJ105"))
      (libsource (lib "eagle-import") (part "RESISTOR0603_RES"))
    )
    (comp (ref "R70")
      (value "1MΩ")
      (footprint "eagle-import:0603-RES")
      (description "RES SMD 1M OHM 5% 1/4W 0603")
      (fields
        (field (name "DIGIKEY") "RHM1MDCT-ND")
        (field (name "MANUFACTURER") "Rohm")
        (field (name "MPN") "ESR03EZPJ105")
      )
      (libsource (lib "eagle-import") (part "RESISTOR0603_RES"))
    )
    (comp (ref "R71")
      (value "1MΩ")
      (footprint "eagle-import:0603-RES")
      (description "RES SMD 1M OHM 5% 1/4W 0603")
      (fields
        (field (name "DIGIKEY") "RHM1MDCT-ND")
        (field (name "MANUFACTURER") "Rohm")
        (field (name "MPN") "ESR03EZPJ105")
      )
      (libsource (lib "eagle-import") (part "RESISTOR0603_RES"))
    )
    (comp (ref "R72")
      (value "1MΩ")
      (footprint "eagle-import:0603-RES")
      (description "RES SMD 1M OHM 5% 1/4W 0603")
      (fields
        (field (name "DIGIKEY") "RHM1MDCT-ND")
        (field (name "MANUFACTURER") "Rohm")
        (field (name "MPN") "ESR03EZPJ105")
      )
      (libsource (lib "eagle-import") (part "RESISTOR0603_RES"))
    )
    (comp (ref "U2")
      (value "FT232RQ")
      (footprint "eagle-import:QFN32")
      (libsource (lib "eagle-import") (part "FT232RQ"))
    )
    (comp (ref "U3")
      (value "FT232RQ")
      (footprint "eagle-import:QFN32")
      (libsource (lib "eagle-import") (part "FT232RQ"))
    )
    (comp (ref "C11")
      (value "22pF")
      (footprint "eagle-import:0603_CAP")
      (description "CAP CER 22PF 50V C0G/NP0 0603")
      (fields (field (name "MANUFACTURER") "Samsung") (field (name "MPN") "CL10C220JB8NNNC"))
      (libsource (lib "eagle-import") (part "CAPACITOR0603_CAP"))
    )
    (comp (ref "C12")
      (value "22pF")
      (footprint "eagle-import:0603_CAP")
      (description "CAP CER 22PF 50V C0G/NP0 0603")
      (fields (field (name "MANUFACTURER") "Samsung") (field (name "MPN") "CL10C220JB8NNNC"))
      (libsource (lib "eagle-import") (part "CAPACITOR0603_CAP"))
    )
    (comp (ref "C54")
      (value "0.1uF")
      (footprint "eagle-import:0603_CAP")
      (description "CAP CER 0.1UF 16V X7R 0603")
      (fields
        (field (name "DIGIKEY") "490-1532-1-ND")
        (field (name "MANUFACTURER") "Murata")
        (field (name "MPN") "GRM188R71C104KA01D")
      )
      (libsource (lib "eagle-import") (part "CAPACITOR0603_CAP"))
    )
    (comp (ref "C72")
      (value "4.7uF")
      (footprint "eagle-import:0603_CAP")
      (description "CAP CER 4.7UF 6.3V X7R 0603")
      (fields
        (field (name "DIGIKEY") "1276-2087-1-ND")
        (field (name "MANUFACTURER") "Samsung")
        (field (name "MPN") "CL10B475KQ8NQNC")
      )
      (libsource (lib "eagle-import") (part "CAPACITOR0603_CAP"))
    )
    (comp (ref "J5")
      (value "MICRO_USB_B_HIROSE_ZX62R-B-5P")
      (footprint "eagle-import:USB_MICRO_B-HIROSE-ZX62R-B-5P")
      (libsource (lib "eagle-import") (part "MICRO_USB_B_HIROSE_ZX62R-B-5P"))
    )
    (comp (ref "R29")
      (value "1.5kΩ")
      (footprint "eagle-import:0603-RES")
      (description "RES SMD 1.5K OHM 5% 1/10W 0603")
      (fields
        (field (name "DIGIKEY") "311-1.5KGRCT-ND")
        (field (name "MANUFACTURER") "Yageo")
        (field (name "MPN") "RC0603JR-071K5L")
      )
      (libsource (lib "eagle-import") (part "RESISTOR0603_RES"))
    )
    (comp (ref "R30")
      (value "1.5kΩ")
      (footprint "eagle-import:0603-RES")
      (description "RES SMD 1.5K OHM 5% 1/10W 0603")
      (fields
        (field (name "DIGIKEY") "311-1.5KGRCT-ND")
        (field (name "MANUFACTURER") "Yageo")
        (field (name "MPN") "RC0603JR-071K5L")
      )
      (libsource (lib "eagle-import") (part "RESISTOR0603_RES"))
    )
    (comp (ref "R51")
      (value "10kΩ")
      (footprint "eagle-import:0603-RES")
      (description "RES SMD 10K OHM 5% 1/10W 0603")
      (fields
        (field (name "DIGIKEY") "P10KGCT-ND")
        (field (name "MANUFACTURER") "Panasonic")
        (field (name "MPN") "ERJ-3GEYJ103V")
      )
      (libsource (lib "eagle-import") (part "RESISTOR0603_RES"))
    )
    (comp (ref "R52")
      (value "10kΩ")
      (footprint "eagle-import:0603-RES")
      (description "RES SMD 10K OHM 5% 1/10W 0603")
      (fields
        (field (name "DIGIKEY") "P10KGCT-ND")
        (field (name "MANUFACTURER") "Panasonic")
        (field (name "MPN") "ERJ-3GEYJ103V")
      )
      (libsource (lib "eagle-import") (part "RESISTOR0603_RES"))
    )
    (comp (ref "R60")
      (value "15kΩ")
      (footprint "eagle-import:0603-RES")
      (description "RES SMD 15K OHM 1% 1/10W 0603")
      (fields
        (field (name "DIGIKEY") "RHM15.0KCFCT-ND")
        (field (name "MANUFACTURER") "Rohm")
        (field (name "MPN") "MCR03ERTF1502")
      )
      (libsource (lib "eagle-import") (part "RESISTOR0603_RES"))
    )
    (comp (ref "R61")
      (value "15kΩ")
      (footprint "eagle-import:0603-RES")
      (description "RES SMD 15K OHM 1% 1/10W 0603")
      (fields
        (field (name "DIGIKEY") "RHM15.0KCFCT-ND")
        (field (name "MANUFACTURER") "Rohm")
        (field (name "MPN") "MCR03ERTF1502")
      )
      (libsource (lib "eagle-import") (part "RESISTOR0603_RES"))
    )
    (comp (ref "TP1")
      (value "TEST_POINT_0.040IN")
      (footprint "eagle-import:TESTPOINT_0.040IN")
      (libsource (lib "eagle-import") (part "TEST_POINT_0.040IN"))
    )
    (comp (ref "TP2")
      (value "TEST_POINT_0.040IN")
      (footprint "eagle-import:TESTPOINT_0.040IN")
      (libsource (lib "eagle-import") (part "TEST_POINT_0.040IN"))
    )
    (comp (ref "TP3")
      (value "TEST_POINT_0.040IN")
      (footprint "eagle-import:TESTPOINT_0.040IN")
      (libsource (lib "eagle-import") (part "TEST_POINT_0.040IN"))
    )
    (comp (ref "TP12")
      (value "TEST_POINT_0.040IN")
      (footprint "eagle-import:TESTPOINT_0.040IN")
      (libsource (lib "eagle-import") (part "TEST_POINT_0.040IN"))
    )
    (comp (ref "U20")
      (value "NCP301LSN30")
      (footprint "eagle-import:SOT23-5")
      (libsource (lib "eagle-import") (part "NCP301LSN30"))
    )
    (comp (ref "U32")
      (value "TUSB2077A")
      (footprint "eagle-import:LQFP-48")
      (libsource (lib "eagle-import") (part "TUSB2077A"))
    )
    (comp (ref "Y2")
      (value "ABMM")
      (footprint "eagle-import:ABMM")
      (fields (field (name "MANUFACTURER") "Abracon LLC") (field (name "MPN") "ABMM-6.000MHZ-B2-T"))
      (libsource (lib "eagle-import") (part "ABMM"))
    )
    (comp (ref "H1")
      (value "MOUNT-PAD-ROUND#4")
      (footprint "eagle-import:#4-PAD")
      (libsource (lib "eagle-import") (part "MOUNT-PAD-ROUND#4"))
    )
    (comp (ref "H2")
      (value "MOUNT-PAD-ROUND#4")
      (footprint "eagle-import:#4-PAD")
      (libsource (lib "eagle-import") (part "MOUNT-PAD-ROUND#4"))
    )
    (comp (ref "H3")
      (value "MOUNT-PAD-ROUND#4")
      (footprint "eagle-import:#4-PAD")
      (libsource (lib "eagle-import") (part "MOUNT-PAD-ROUND#4"))
    )
    (comp (ref "H4")
      (value "MOUNT-PAD-ROUND#4")
      (footprint "eagle-import:#4-PAD")
      (libsource (lib "eagle-import") (part "MOUNT-PAD-ROUND#4"))
    )
    (comp (ref "H5")
      (value "MOUNT-PAD-ROUND#4")
      (footprint "eagle-import:#4-PAD")
      (libsource (lib "eagle-import") (part "MOUNT-PAD-ROUND#4"))
    )
    (comp (ref "H6")
      (value "MOUNT-PAD-ROUND#4")
      (footprint "eagle-import:#4-PAD")
      (libsource (lib "eagle-import") (part "MOUNT-PAD-ROUND#4"))
    )
    (comp (ref "H7")
      (value "MOUNT-PAD-ROUND#4")
      (footprint "eagle-import:#4-PAD")
      (libsource (lib "eagle-import") (part "MOUNT-PAD-ROUND#4"))
    )
    (comp (ref "H8")
      (value "MOUNT-PAD-ROUND#4")
      (footprint "eagle-import:#4-PAD")
      (libsource (lib "eagle-import") (part "MOUNT-PAD-ROUND#4"))
    )
    (comp (ref "J1")
      (value "BACKPLANE_CONTROLLER_MODULE_DEBUG")
      (footprint "eagle-import:BACKPLANE_MODULE_20PIN_10PIN_DEBUG")
      (libsource (lib "eagle-import") (part "BACKPLANE_CONTROLLER_MODULE_DEBUG"))
    )
    (comp (ref "JP15")
      (value "FIDUCIAL1X2")
      (footprint "eagle-import:FIDUCIAL-1X2")
      (libsource (lib "eagle-import") (part "FIDUCIAL1X2"))
    )
    (comp (ref "JP21")
      (value "FIDUCIAL1X2")
      (footprint "eagle-import:FIDUCIAL-1X2")
      (libsource (lib "eagle-import") (part "FIDUCIAL1X2"))
    )
    (comp (ref "JP22")
      (value "FIDUCIAL1X2")
      (footprint "eagle-import:FIDUCIAL-1X2")
      (libsource (lib "eagle-import") (part "FIDUCIAL1X2"))
    )
    (comp (ref "JP23")
      (value "FIDUCIAL1X2")
      (footprint "eagle-import:FIDUCIAL-1X2")
      (libsource (lib "eagle-import") (part "FIDUCIAL1X2"))
    )
    (comp (ref "JP24")
      (value "FIDUCIAL1X2")
      (footprint "eagle-import:FIDUCIAL-1X2")
      (libsource (lib "eagle-import") (part "FIDUCIAL1X2"))
    )
    (comp (ref "JP25")
      (value "FIDUCIAL1X2")
      (footprint "eagle-import:FIDUCIAL-1X2")
      (libsource (lib "eagle-import") (part "FIDUCIAL1X2"))
    )
    (comp (ref "R42")
      (value "10kΩ")
      (footprint "eagle-import:0603-RES")
      (description "RES SMD 10K OHM 5% 1/10W 0603")
      (fields
        (field (name "DIGIKEY") "P10KGCT-ND")
        (field (name "MANUFACTURER") "Panasonic")
        (field (name "MPN") "ERJ-3GEYJ103V")
      )
      (libsource (lib "eagle-import") (part "RESISTOR0603_RES"))
    )
    (comp (ref "R43")
      (value "10kΩ")
      (footprint "eagle-import:0603-RES")
      (description "RES SMD 10K OHM 5% 1/10W 0603")
      (fields
        (field (name "DIGIKEY") "P10KGCT-ND")
        (field (name "MANUFACTURER") "Panasonic")
        (field (name "MPN") "ERJ-3GEYJ103V")
      )
      (libsource (lib "eagle-import") (part "RESISTOR0603_RES"))
    )
    (comp (ref "R44")
      (value "10kΩ")
      (footprint "eagle-import:0603-RES")
      (description "RES SMD 10K OHM 5% 1/10W 0603")
      (fields
        (field (name "DIGIKEY") "P10KGCT-ND")
        (field (name "MANUFACTURER") "Panasonic")
        (field (name "MPN") "ERJ-3GEYJ103V")
      )
      (libsource (lib "eagle-import") (part "RESISTOR0603_RES"))
    )
    (comp (ref "R45")
      (value "10kΩ")
      (footprint "eagle-import:0603-RES")
      (description "RES SMD 10K OHM 5% 1/10W 0603")
      (fields
        (field (name "DIGIKEY") "P10KGCT-ND")
        (field (name "MANUFACTURER") "Panasonic")
        (field (name "MPN") "ERJ-3GEYJ103V")
      )
      (libsource (lib "eagle-import") (part "RESISTOR0603_RES"))
    )
    (comp (ref "R46")
      (value "10kΩ")
      (footprint "eagle-import:0603-RES")
      (description "RES SMD 10K OHM 5% 1/10W 0603")
      (fields
        (field (name "DIGIKEY") "P10KGCT-ND")
        (field (name "MANUFACTURER") "Panasonic")
        (field (name "MPN") "ERJ-3GEYJ103V")
      )
      (libsource (lib "eagle-import") (part "RESISTOR0603_RES"))
    )
    (comp (ref "R47")
      (value "10kΩ")
      (footprint "eagle-import:0603-RES")
      (description "RES SMD 10K OHM 5% 1/10W 0603")
      (fields
        (field (name "DIGIKEY") "P10KGCT-ND")
        (field (name "MANUFACTURER") "Panasonic")
        (field (name "MPN") "ERJ-3GEYJ103V")
      )
      (libsource (lib "eagle-import") (part "RESISTOR0603_RES"))
    )
    (comp (ref "S10")
      (value "PTS645SM43SMTR92")
      (footprint "eagle-import:PTS645")
      (libsource (lib "eagle-import") (part "PTS645SM43SMTR92"))
    )
    (comp (ref "S11")
      (value "PTS645SM43SMTR92")
      (footprint "eagle-import:PTS645")
      (libsource (lib "eagle-import") (part "PTS645SM43SMTR92"))
    )
    (comp (ref "SJ4")
      (value "SOLDERJUMPERNC")
      (footprint "eagle-import:SJ_2S")
      (libsource (lib "eagle-import") (part "SOLDERJUMPERNC"))
    )
    (comp (ref "SJ5")
      (value "SOLDERJUMPERNC")
      (footprint "eagle-import:SJ_2S")
      (libsource (lib "eagle-import") (part "SOLDERJUMPERNC"))
    )
    (comp (ref "TP8")
      (value "TEST_POINT_0.040IN")
      (footprint "eagle-import:TESTPOINT_0.040IN")
      (libsource (lib "eagle-import") (part "TEST_POINT_0.040IN"))
    )
    (comp (ref "TP9")
      (value "TEST_POINT_0.040IN")
      (footprint "eagle-import:TESTPOINT_0.040IN")
      (libsource (lib "eagle-import") (part "TEST_POINT_0.040IN"))
    )
    (comp (ref "TP10")
      (value "TEST_POINT_0.040IN")
      (footprint "eagle-import:TESTPOINT_0.040IN")
      (libsource (lib "eagle-import") (part "TEST_POINT_0.040IN"))
    )
    (comp (ref "TP11")
      (value "TEST_POINT_0.040IN")
      (footprint "eagle-import:TESTPOINT_0.040IN")
      (libsource (lib "eagle-import") (part "TEST_POINT_0.040IN"))
    )
    (comp (ref "C3")
      (value "22pF")
      (footprint "eagle-import:0402_CAP")
      (description "CAP CER 22PF 50V C0G/NP0 0402")
      (fields (field (name "MANUFACTURER") "Murata") (field (name "MPN") "GRM1555C1H220JA01D"))
      (libsource (lib "eagle-import") (part "CAPACITOR0402_CAP"))
    )
    (comp (ref "C4")
      (value "22pF")
      (footprint "eagle-import:0402_CAP")
      (description "CAP CER 22PF 50V C0G/NP0 0402")
      (fields
        (field (name "DIGIKEY") "490-5868-1-ND")
        (field (name "MANUFACTURER") "Murata")
        (field (name "MPN") "GRM1555C1H220JA01D")
      )
      (libsource (lib "eagle-import") (part "CAPACITOR0402_CAP"))
    )
    (comp (ref "C5")
      (value "22pF")
      (footprint "eagle-import:0402_CAP")
      (description "CAP CER 22PF 50V C0G/NP0 0402")
      (fields
        (field (name "DIGIKEY") "490-5868-1-ND")
        (field (name "MANUFACTURER") "Murata")
        (field (name "MPN") "GRM1555C1H220JA01D")
      )
      (libsource (lib "eagle-import") (part "CAPACITOR0402_CAP"))
    )
    (comp (ref "C6")
      (value "22pF")
      (footprint "eagle-import:0402_CAP")
      (description "CAP CER 22PF 50V C0G/NP0 0402")
      (fields
        (field (name "DIGIKEY") "490-5868-1-ND")
        (field (name "MANUFACTURER") "Murata")
        (field (name "MPN") "GRM1555C1H220JA01D")
      )
      (libsource (lib "eagle-import") (part "CAPACITOR0402_CAP"))
    )
    (comp (ref "C7")
      (value "22pF")
      (footprint "eagle-import:0402_CAP")
      (description "CAP CER 22PF 50V C0G/NP0 0402")
      (fields
        (field (name "DIGIKEY") "490-5868-1-ND")
        (field (name "MANUFACTURER") "Murata")
        (field (name "MPN") "GRM1555C1H220JA01D")
      )
      (libsource (lib "eagle-import") (part "CAPACITOR0402_CAP"))
    )
    (comp (ref "C8")
      (value "22pF")
      (footprint "eagle-import:0402_CAP")
      (description "CAP CER 22PF 50V C0G/NP0 0402")
      (fields
        (field (name "DIGIKEY") "490-5868-1-ND")
        (field (name "MANUFACTURER") "Murata")
        (field (name "MPN") "GRM1555C1H220JA01D")
      )
      (libsource (lib "eagle-import") (part "CAPACITOR0402_CAP"))
    )
    (comp (ref "C35")
      (value "0.1uF")
      (footprint "eagle-import:0603_CAP")
      (description "CAP CER 0.1UF 16V X7R 0603")
      (fields
        (field (name "DIGIKEY") "490-1532-1-ND")
        (field (name "MANUFACTURER") "Murata")
        (field (name "MPN") "GRM188R71C104KA01D")
      )
      (libsource (lib "eagle-import") (part "CAPACITOR0603_CAP"))
    )
    (comp (ref "C36")
      (value "0.1uF")
      (footprint "eagle-import:0603_CAP")
      (description "CAP CER 0.1UF 16V X7R 0603")
      (fields
        (field (name "DIGIKEY") "490-1532-1-ND")
        (field (name "MANUFACTURER") "Murata")
        (field (name "MPN") "GRM188R71C104KA01D")
      )
      (libsource (lib "eagle-import") (part "CAPACITOR0603_CAP"))
    )
    (comp (ref "D35")
      (value "SN75240-TSSOP")
      (footprint "eagle-import:TSSOP-8")
      (fields (field (name "MANUFACTURER") "Texas Instruments") (field (name "MPN") "SN75240PWR"))
      (libsource (lib "eagle-import") (part "SN75240-TSSOP"))
    )
    (comp (ref "D36")
      (value "SN75240-TSSOP")
      (footprint "eagle-import:TSSOP-8")
      (fields (field (name "MANUFACTURER") "Texas Instruments") (field (name "MPN") "SN75240PWR"))
      (libsource (lib "eagle-import") (part "SN75240-TSSOP"))
    )
    (comp (ref "R5")
      (value "27Ω")
      (footprint "eagle-import:0402_RES-HIGH_SPEED")
      (description "RES SMD 27 OHM 5% 1/16W 0402")
      (fields
        (field (name "DIGIKEY") "541-27JCT-ND")
        (field (name "MANUFACTURER") "Vishay Dale")
        (field (name "MPN") "CRCW040227R0JNED")
      )
      (libsource (lib "eagle-import") (part "RESISTOR-HIGH_SPEED0402"))
    )
    (comp (ref "R6")
      (value "27Ω")
      (footprint "eagle-import:0402_RES-HIGH_SPEED")
      (description "RES SMD 27 OHM 5% 1/16W 0402")
      (fields (field (name "MANUFACTURER") "Vishay Dale") (field (name "MPN") "CRCW040227R0JNED"))
      (libsource (lib "eagle-import") (part "RESISTOR-HIGH_SPEED0402"))
    )
    (comp (ref "R7")
      (value "27Ω")
      (footprint "eagle-import:0402_RES-HIGH_SPEED")
      (description "RES SMD 27 OHM 5% 1/16W 0402")
      (fields
        (field (name "DIGIKEY") "541-27JCT-ND")
        (field (name "MANUFACTURER") "Vishay Dale")
        (field (name "MPN") "CRCW040227R0JNED")
      )
      (libsource (lib "eagle-import") (part "RESISTOR-HIGH_SPEED0402"))
    )
    (comp (ref "R8")
      (value "27Ω")
      (footprint "eagle-import:0402_RES-HIGH_SPEED")
      (description "RES SMD 27 OHM 5% 1/16W 0402")
      (fields
        (field (name "DIGIKEY") "541-27JCT-ND")
        (field (name "MANUFACTURER") "Vishay Dale")
        (field (name "MPN") "CRCW040227R0JNED")
      )
      (libsource (lib "eagle-import") (part "RESISTOR-HIGH_SPEED0402"))
    )
    (comp (ref "R9")
      (value "27Ω")
      (footprint "eagle-import:0402_RES-HIGH_SPEED")
      (description "RES SMD 27 OHM 5% 1/16W 0402")
      (fields
        (field (name "DIGIKEY") "541-27JCT-ND")
        (field (name "MANUFACTURER") "Vishay Dale")
        (field (name "MPN") "CRCW040227R0JNED")
      )
      (libsource (lib "eagle-import") (part "RESISTOR-HIGH_SPEED0402"))
    )
    (comp (ref "R10")
      (value "27Ω")
      (footprint "eagle-import:0402_RES-HIGH_SPEED")
      (description "RES SMD 27 OHM 5% 1/16W 0402")
      (fields
        (field (name "DIGIKEY") "541-27JCT-ND")
        (field (name "MANUFACTURER") "Vishay Dale")
        (field (name "MPN") "CRCW040227R0JNED")
      )
      (libsource (lib "eagle-import") (part "RESISTOR-HIGH_SPEED0402"))
    )
    (comp (ref "R11")
      (value "50Ω")
      (footprint "eagle-import:0603-RES")
      (description "RES SMD 49.9 OHM 1% 1/10W 0603")
      (fields (field (name "MANUFACTURER") "Rohm") (field (name "MPN") "TRR03EZPF49R9"))
      (libsource (lib "eagle-import") (part "RESISTOR0603_RES"))
    )
    (comp (ref "R12")
      (value "50Ω")
      (footprint "eagle-import:0603-RES")
      (description "RES SMD 49.9 OHM 1% 1/10W 0603")
      (fields
        (field (name "DIGIKEY") "RHM49.9BJCT-ND")
        (field (name "MANUFACTURER") "Rohm")
        (field (name "MPN") "TRR03EZPF49R9")
      )
      (libsource (lib "eagle-import") (part "RESISTOR0603_RES"))
    )
    (comp (ref "R13")
      (value "50Ω")
      (footprint "eagle-import:0603-RES")
      (description "RES SMD 49.9 OHM 1% 1/10W 0603")
      (fields
        (field (name "DIGIKEY") "RHM49.9BJCT-ND")
        (field (name "MANUFACTURER") "Rohm")
        (field (name "MPN") "TRR03EZPF49R9")
      )
      (libsource (lib "eagle-import") (part "RESISTOR0603_RES"))
    )
    (comp (ref "R14")
      (value "50Ω")
      (footprint "eagle-import:0603-RES")
      (description "RES SMD 49.9 OHM 1% 1/10W 0603")
      (fields
        (field (name "DIGIKEY") "RHM49.9BJCT-ND")
        (field (name "MANUFACTURER") "Rohm")
        (field (name "MPN") "TRR03EZPF49R9")
      )
      (libsource (lib "eagle-import") (part "RESISTOR0603_RES"))
    )
    (comp (ref "R54")
      (value "15kΩ")
      (footprint "eagle-import:0603-RES")
      (description "RES SMD 15K OHM 1% 1/10W 0603")
      (fields (field (name "MANUFACTURER") "Rohm") (field (name "MPN") "MCR03ERTF1502"))
      (libsource (lib "eagle-import") (part "RESISTOR0603_RES"))
    )
    (comp (ref "R55")
      (value "15kΩ")
      (footprint "eagle-import:0603-RES")
      (description "RES SMD 15K OHM 1% 1/10W 0603")
      (fields
        (field (name "DIGIKEY") "RHM15.0KCFCT-ND")
        (field (name "MANUFACTURER") "Rohm")
        (field (name "MPN") "MCR03ERTF1502")
      )
      (libsource (lib "eagle-import") (part "RESISTOR0603_RES"))
    )
    (comp (ref "R56")
      (value "15kΩ")
      (footprint "eagle-import:0603-RES")
      (description "RES SMD 15K OHM 1% 1/10W 0603")
      (fields
        (field (name "DIGIKEY") "RHM15.0KCFCT-ND")
        (field (name "MANUFACTURER") "Rohm")
        (field (name "MPN") "MCR03ERTF1502")
      )
      (libsource (lib "eagle-import") (part "RESISTOR0603_RES"))
    )
    (comp (ref "R57")
      (value "15kΩ")
      (footprint "eagle-import:0603-RES")
      (description "RES SMD 15K OHM 1% 1/10W 0603")
      (fields
        (field (name "DIGIKEY") "RHM15.0KCFCT-ND")
        (field (name "MANUFACTURER") "Rohm")
        (field (name "MPN") "MCR03ERTF1502")
      )
      (libsource (lib "eagle-import") (part "RESISTOR0603_RES"))
    )
    (comp (ref "R58")
      (value "15kΩ")
      (footprint "eagle-import:0603-RES")
      (description "RES SMD 15K OHM 1% 1/10W 0603")
      (fields
        (field (name "DIGIKEY") "RHM15.0KCFCT-ND")
        (field (name "MANUFACTURER") "Rohm")
        (field (name "MPN") "MCR03ERTF1502")
      )
      (libsource (lib "eagle-import") (part "RESISTOR0603_RES"))
    )
    (comp (ref "R59")
      (value "15kΩ")
      (footprint "eagle-import:0603-RES")
      (description "RES SMD 15K OHM 1% 1/10W 0603")
      (fields
        (field (name "DIGIKEY") "RHM15.0KCFCT-ND")
        (field (name "MANUFACTURER") "Rohm")
        (field (name "MPN") "MCR03ERTF1502")
      )
      (libsource (lib "eagle-import") (part "RESISTOR0603_RES"))
    )
    (comp (ref "U28")
      (value "TS3USB30E")
      (footprint "eagle-import:UQFN-10")
      (libsource (lib "eagle-import") (part "TS3USB30E"))
    )
    (comp (ref "U29")
      (value "TS3USB30E")
      (footprint "eagle-import:UQFN-10")
      (libsource (lib "eagle-import") (part "TS3USB30E"))
    )
    (comp (ref "C64")
      (value "0.47uF")
      (footprint "eagle-import:0603_CAP")
      (description "CAP CER 0.47UF 10V X5R 0603")
      (fields (field (name "MANUFACTURER") "Murata") (field (name "MPN") "GRM188R61A474KA61D"))
      (libsource (lib "eagle-import") (part "CAPACITOR0603_CAP"))
    )
    (comp (ref "C65")
      (value "0.82uF")
      (footprint "eagle-import:0603_CAP")
      (description "CAP CER 0.82UF 6.3V X5R 0603")
      (fields (field (name "MANUFACTURER") "Murata") (field (name "MPN") "GRM188R60J824KA01D"))
      (libsource (lib "eagle-import") (part "CAPACITOR0603_CAP"))
    )
    (comp (ref "D1")
      (value "DIODE_SCHOTTKY_ARRAY-4HMD8")
      (footprint "eagle-import:HMD8")
      (fields (field (name "MANUFACTURER") "Rohm Semiconductor") (field (name "MPN") "RB521ZS8A30TE61"))
      (libsource (lib "eagle-import") (part "DIODE_SCHOTTKY_ARRAY-4HMD8"))
    )
    (comp (ref "D2")
      (value "DIODE_SCHOTTKY_ARRAY-4HMD8")
      (footprint "eagle-import:HMD8")
      (fields (field (name "MANUFACTURER") "Rohm Semiconductor") (field (name "MPN") "RB521ZS8A30TE61"))
      (libsource (lib "eagle-import") (part "DIODE_SCHOTTKY_ARRAY-4HMD8"))
    )
    (comp (ref "D34")
      (value "LED0603")
      (footprint "eagle-import:LED-0603")
      (description "LED RED CLEAR 0603 SMD")
      (fields (field (name "MANUFACTURER") "Lite-On") (field (name "MPN") "LTST-C191KRKT"))
      (libsource (lib "eagle-import") (part "LED0603"))
    )
    (comp (ref "Q7")
      (value "DMN32D2LDF")
      (footprint "eagle-import:SOT353")
      (fields (field (name "MANUFACTURER") "Diodes Incorporated") (field (name "MPN") "DMN32D2LDF-7"))
      (libsource (lib "eagle-import") (part "DMN32D2LDF"))
    )
    (comp (ref "R16")
      (value "50Ω")
      (footprint "eagle-import:0603-RES")
      (description "RES SMD 49.9 OHM 1% 1/10W 0603")
      (fields
        (field (name "DIGIKEY") "RHM49.9BJCT-ND")
        (field (name "MANUFACTURER") "Rohm")
        (field (name "MPN") "TRR03EZPF49R9")
      )
      (libsource (lib "eagle-import") (part "RESISTOR0603_RES"))
    )
    (comp (ref "R31")
      (value "1.5kΩ")
      (footprint "eagle-import:0603-RES")
      (description "RES SMD 1.5K OHM 5% 1/10W 0603")
      (fields (field (name "MANUFACTURER") "Yageo") (field (name "MPN") "RC0603JR-071K5L"))
      (libsource (lib "eagle-import") (part "RESISTOR0603_RES"))
    )
    (comp (ref "S7")
      (value "PTS645SM43SMTR92")
      (footprint "eagle-import:PTS645")
      (libsource (lib "eagle-import") (part "PTS645SM43SMTR92"))
    )
    (comp (ref "S13")
      (value "PTS645SM43SMTR92")
      (footprint "eagle-import:PTS645")
      (libsource (lib "eagle-import") (part "PTS645SM43SMTR92"))
    )
    (comp (ref "S17")
      (value "SIP3240X")
      (footprint "eagle-import:TDFN4")
      (libsource (lib "eagle-import") (part "SIP3240X"))
    )
    (comp (ref "S18")
      (value "SIP3240X")
      (footprint "eagle-import:TDFN4")
      (libsource (lib "eagle-import") (part "SIP3240X"))
    )
    (comp (ref "S25")
      (value "TE_SSA12/SPDT")
      (footprint "eagle-import:TE_SSA12_SPDT")
      (libsource (lib "eagle-import") (part "TE_SSA12/SPDT"))
    )
    (comp (ref "U15")
      (value "MAX6746")
      (footprint "eagle-import:SOT-23-8")
      (libsource (lib "eagle-import") (part "MAX6746"))
    )
    (comp (ref "C29")
      (value "0.1uF")
      (footprint "eagle-import:0603_CAP")
      (description "CAP CER 0.1UF 16V X7R 0603")
      (fields
        (field (name "DIGIKEY") "490-1532-1-ND")
        (field (name "MANUFACTURER") "Murata")
        (field (name "MPN") "GRM188R71C104KA01D")
      )
      (libsource (lib "eagle-import") (part "CAPACITOR0603_CAP"))
    )
    (comp (ref "C30")
      (value "0.1uF")
      (footprint "eagle-import:0603_CAP")
      (description "CAP CER 0.1UF 16V X7R 0603")
      (fields
        (field (name "DIGIKEY") "490-1532-1-ND")
        (field (name "MANUFACTURER") "Murata")
        (field (name "MPN") "GRM188R71C104KA01D")
      )
      (libsource (lib "eagle-import") (part "CAPACITOR0603_CAP"))
    )
    (comp (ref "C31")
      (value "0.1uF")
      (footprint "eagle-import:0603_CAP")
      (description "CAP CER 0.1UF 16V X7R 0603")
      (fields
        (field (name "DIGIKEY") "490-1532-1-ND")
        (field (name "MANUFACTURER") "Murata")
        (field (name "MPN") "GRM188R71C104KA01D")
      )
      (libsource (lib "eagle-import") (part "CAPACITOR0603_CAP"))
    )
    (comp (ref "C32")
      (value "0.1uF")
      (footprint "eagle-import:0603_CAP")
      (description "CAP CER 0.1UF 16V X7R 0603")
      (fields
        (field (name "DIGIKEY") "490-1532-1-ND")
        (field (name "MANUFACTURER") "Murata")
        (field (name "MPN") "GRM188R71C104KA01D")
      )
      (libsource (lib "eagle-import") (part "CAPACITOR0603_CAP"))
    )
    (comp (ref "C33")
      (value "0.1uF")
      (footprint "eagle-import:0603_CAP")
      (description "CAP CER 0.1UF 16V X7R 0603")
      (fields
        (field (name "DIGIKEY") "490-1532-1-ND")
        (field (name "MANUFACTURER") "Murata")
        (field (name "MPN") "GRM188R71C104KA01D")
      )
      (libsource (lib "eagle-import") (part "CAPACITOR0603_CAP"))
    )
    (comp (ref "C34")
      (value "0.1uF")
      (footprint "eagle-import:0603_CAP")
      (description "CAP CER 0.1UF 16V X7R 0603")
      (fields
        (field (name "DIGIKEY") "490-1532-1-ND")
        (field (name "MANUFACTURER") "Murata")
        (field (name "MPN") "GRM188R71C104KA01D")
      )
      (libsource (lib "eagle-import") (part "CAPACITOR0603_CAP"))
    )
    (comp (ref "C74")
      (value "150uF")
      (footprint "eagle-import:1210_CAP")
      (description "CAP CER 150UF 6.3V X5R 1210")
      (fields (field (name "MANUFACTURER") "Samsung") (field (name "MPN") "CL32A157MQVNNNE"))
      (libsource (lib "eagle-import") (part "CAPACITOR1210_CAP"))
    )
    (comp (ref "C75")
      (value "150uF")
      (footprint "eagle-import:1210_CAP")
      (description "CAP CER 150UF 6.3V X5R 1210")
      (fields (field (name "MANUFACTURER") "Samsung") (field (name "MPN") "CL32A157MQVNNNE"))
      (libsource (lib "eagle-import") (part "CAPACITOR1210_CAP"))
    )
    (comp (ref "R36")
      (value "10kΩ")
      (footprint "eagle-import:0603-RES")
      (description "RES SMD 10K OHM 5% 1/10W 0603")
      (fields
        (field (name "DIGIKEY") "P10KGCT-ND")
        (field (name "MANUFACTURER") "Panasonic")
        (field (name "MPN") "ERJ-3GEYJ103V")
      )
      (libsource (lib "eagle-import") (part "RESISTOR0603_RES"))
    )
    (comp (ref "R37")
      (value "10kΩ")
      (footprint "eagle-import:0603-RES")
      (description "RES SMD 10K OHM 5% 1/10W 0603")
      (fields
        (field (name "DIGIKEY") "P10KGCT-ND")
        (field (name "MANUFACTURER") "Panasonic")
        (field (name "MPN") "ERJ-3GEYJ103V")
      )
      (libsource (lib "eagle-import") (part "RESISTOR0603_RES"))
    )
    (comp (ref "S1")
      (value "AP2401MP")
      (footprint "eagle-import:MSOP-8EP")
      (libsource (lib "eagle-import") (part "AP2401MP"))
    )
    (comp (ref "S2")
      (value "AP2401MP")
      (footprint "eagle-import:MSOP-8EP")
      (libsource (lib "eagle-import") (part "AP2401MP"))
    )
    (comp (ref "S5")
      (value "NC7SZ157")
      (footprint "eagle-import:SC70-6")
      (libsource (lib "eagle-import") (part "NC7SZ157"))
    )
    (comp (ref "S6")
      (value "NC7SZ157")
      (footprint "eagle-import:SC70-6")
      (libsource (lib "eagle-import") (part "NC7SZ157"))
    )
    (comp (ref "C27")
      (value "0.1uF")
      (footprint "eagle-import:0603_CAP")
      (description "CAP CER 0.1UF 16V X7R 0603")
      (fields
        (field (name "DIGIKEY") "490-1532-1-ND")
        (field (name "MANUFACTURER") "Murata")
        (field (name "MPN") "GRM188R71C104KA01D")
      )
      (libsource (lib "eagle-import") (part "CAPACITOR0603_CAP"))
    )
    (comp (ref "C28")
      (value "0.1uF")
      (footprint "eagle-import:0603_CAP")
      (description "CAP CER 0.1UF 16V X7R 0603")
      (fields
        (field (name "DIGIKEY") "490-1532-1-ND")
        (field (name "MANUFACTURER") "Murata")
        (field (name "MPN") "GRM188R71C104KA01D")
      )
      (libsource (lib "eagle-import") (part "CAPACITOR0603_CAP"))
    )
    (comp (ref "D26")
      (value "LED0603")
      (footprint "eagle-import:LED-0603")
      (description "LED BLUE CLEAR 0603 SMD")
      (fields (field (name "MANUFACTURER") "Lite-On") (field (name "MPN") "LTST-C193TBKT-5A"))
      (libsource (lib "eagle-import") (part "LED0603"))
    )
    (comp (ref "D27")
      (value "LED0603")
      (footprint "eagle-import:LED-0603")
      (description "LED BLUE CLEAR 0603 SMD")
      (fields (field (name "MANUFACTURER") "Lite-On") (field (name "MPN") "LTST-C193TBKT-5A"))
      (libsource (lib "eagle-import") (part "LED0603"))
    )
    (comp (ref "D28")
      (value "LED0603")
      (footprint "eagle-import:LED-0603")
      (description "LED BLUE CLEAR 0603 SMD")
      (fields (field (name "MANUFACTURER") "Lite-On") (field (name "MPN") "LTST-C193TBKT-5A"))
      (libsource (lib "eagle-import") (part "LED0603"))
    )
    (comp (ref "D29")
      (value "LED0603")
      (footprint "eagle-import:LED-0603")
      (description "LED BLUE CLEAR 0603 SMD")
      (fields (field (name "MANUFACTURER") "Lite-On") (field (name "MPN") "LTST-C193TBKT-5A"))
      (libsource (lib "eagle-import") (part "LED0603"))
    )
    (comp (ref "D30")
      (value "LED0603")
      (footprint "eagle-import:LED-0603")
      (description "LED BLUE CLEAR 0603 SMD")
      (fields (field (name "MANUFACTURER") "Lite-On") (field (name "MPN") "LTST-C193TBKT-5A"))
      (libsource (lib "eagle-import") (part "LED0603"))
    )
    (comp (ref "D31")
      (value "LED0603")
      (footprint "eagle-import:LED-0603")
      (description "LED BLUE CLEAR 0603 SMD")
      (fields (field (name "MANUFACTURER") "Lite-On") (field (name "MPN") "LTST-C193TBKT-5A"))
      (libsource (lib "eagle-import") (part "LED0603"))
    )
    (comp (ref "D32")
      (value "LED0603")
      (footprint "eagle-import:LED-0603")
      (description "LED BLUE CLEAR 0603 SMD")
      (fields (field (name "MANUFACTURER") "Lite-On") (field (name "MPN") "LTST-C193TBKT-5A"))
      (libsource (lib "eagle-import") (part "LED0603"))
    )
    (comp (ref "D33")
      (value "LED0603")
      (footprint "eagle-import:LED-0603")
      (description "LED BLUE CLEAR 0603 SMD")
      (fields (field (name "MANUFACTURER") "Lite-On") (field (name "MPN") "LTST-C193TBKT-5A"))
      (libsource (lib "eagle-import") (part "LED0603"))
    )
    (comp (ref "R25")
      (value "1kΩ")
      (footprint "eagle-import:ARRAY-CONVEX-0603-4")
      (description "RES ARRAY 4 RES 1K OHM 1206")
      (fields
        (field (name "MANUFACTURER") "Panasonic")
        (field (name "MPN") "EXB-38V102JV")
        (field (name "DIGIKEY") "Y9102CT-ND")
      )
      (libsource (lib "eagle-import") (part "RESISTOR-ARRAY-41206"))
    )
    (comp (ref "R26")
      (value "1kΩ")
      (footprint "eagle-import:ARRAY-CONVEX-0603-4")
      (description "RES ARRAY 4 RES 1K OHM 1206")
      (fields
        (field (name "DIGIKEY") "Y9102CT-ND")
        (field (name "MANUFACTURER") "Panasonic")
        (field (name "MPN") "EXB-38V102JV")
      )
      (libsource (lib "eagle-import") (part "RESISTOR-ARRAY-41206"))
    )
    (comp (ref "R79")
      (value "10MΩ")
      (footprint "eagle-import:0603-RES")
      (description "RES SMD 10M OHM 5% 1/4W 0603")
      (fields (field (name "MANUFACTURER") "Rohm") (field (name "MPN") "ESR03EZPJ106"))
      (libsource (lib "eagle-import") (part "RESISTOR0603_RES"))
    )
    (comp (ref "R80")
      (value "10MΩ")
      (footprint "eagle-import:0603-RES")
      (description "RES SMD 10M OHM 5% 1/4W 0603")
      (fields
        (field (name "DIGIKEY") "RHM10MDCT-ND")
        (field (name "MANUFACTURER") "Rohm")
        (field (name "MPN") "ESR03EZPJ106")
      )
      (libsource (lib "eagle-import") (part "RESISTOR0603_RES"))
    )
    (comp (ref "R81")
      (value "10MΩ")
      (footprint "eagle-import:0603-RES")
      (description "RES SMD 10M OHM 5% 1/4W 0603")
      (fields
        (field (name "DIGIKEY") "RHM10MDCT-ND")
        (field (name "MANUFACTURER") "Rohm")
        (field (name "MPN") "ESR03EZPJ106")
      )
      (libsource (lib "eagle-import") (part "RESISTOR0603_RES"))
    )
    (comp (ref "R82")
      (value "10MΩ")
      (footprint "eagle-import:0603-RES")
      (description "RES SMD 10M OHM 5% 1/4W 0603")
      (fields
        (field (name "DIGIKEY") "RHM10MDCT-ND")
        (field (name "MANUFACTURER") "Rohm")
        (field (name "MPN") "ESR03EZPJ106")
      )
      (libsource (lib "eagle-import") (part "RESISTOR0603_RES"))
    )
    (comp (ref "R83")
      (value "10MΩ")
      (footprint "eagle-import:0603-RES")
      (description "RES SMD 10M OHM 5% 1/4W 0603")
      (fields
        (field (name "DIGIKEY") "RHM10MDCT-ND")
        (field (name "MANUFACTURER") "Rohm")
        (field (name "MPN") "ESR03EZPJ106")
      )
      (libsource (lib "eagle-import") (part "RESISTOR0603_RES"))
    )
    (comp (ref "R84")
      (value "10MΩ")
      (footprint "eagle-import:0603-RES")
      (description "RES SMD 10M OHM 5% 1/4W 0603")
      (fields
        (field (name "DIGIKEY") "RHM10MDCT-ND")
        (field (name "MANUFACTURER") "Rohm")
        (field (name "MPN") "ESR03EZPJ106")
      )
      (libsource (lib "eagle-import") (part "RESISTOR0603_RES"))
    )
    (comp (ref "S3")
      (value "MMS42")
      (footprint "eagle-import:MMS42")
      (libsource (lib "eagle-import") (part "MMS42"))
    )
    (comp (ref "S4")
      (value "MMS42")
      (footprint "eagle-import:MMS42")
      (libsource (lib "eagle-import") (part "MMS42"))
    )
    (comp (ref "U17")
      (value "MCP23008QFN")
      (footprint "eagle-import:QFN-20-4MM")
      (libsource (lib "eagle-import") (part "MCP23008QFN"))
    )
    (comp (ref "U18")
      (value "MCP23008QFN")
      (footprint "eagle-import:QFN-20-4MM")
      (libsource (lib "eagle-import") (part "MCP23008QFN"))
    )
    (comp (ref "C62")
      (value "0.1uF")
      (footprint "eagle-import:0603_CAP")
      (description "CAP CER 0.1UF 16V X7R 0603")
      (fields (field (name "MANUFACTURER") "Murata") (field (name "MPN") "GRM188R71C104KA01D"))
      (libsource (lib "eagle-import") (part "CAPACITOR0603_CAP"))
    )
    (comp (ref "J8")
      (value "TC2030-FTDI-I2C")
      (footprint "eagle-import:TC2030-IDC-NL")
      (libsource (lib "eagle-import") (part "TC2030-FTDI-I2C"))
    )
    (comp (ref "SJ1")
      (value "SOLDERJUMPERNO")
      (footprint "eagle-import:SJ_2S-NO")
      (libsource (lib "eagle-import") (part "SOLDERJUMPERNO"))
    )
    (comp (ref "U14")
      (value "M24C01WMN")
      (footprint "eagle-import:SOIC-8")
      (libsource (lib "eagle-import") (part "M24C01WMN"))
    )
    (comp (ref "D4")
      (value "LED0603")
      (footprint "eagle-import:LED-0603")
      (description "LED GREEN CLEAR 0603 SMD")
      (fields (field (name "MANUFACTURER") "Lite-On") (field (name "MPN") "LTST-C191KGKT"))
      (libsource (lib "eagle-import") (part "LED0603"))
    )
    (comp (ref "D5")
      (value "LED0603")
      (footprint "eagle-import:LED-0603")
      (description "LED GREEN CLEAR 0603 SMD")
      (fields (field (name "MANUFACTURER") "Lite-On") (field (name "MPN") "LTST-C191KGKT"))
      (libsource (lib "eagle-import") (part "LED0603"))
    )
    (comp (ref "D6")
      (value "LED0603")
      (footprint "eagle-import:LED-0603")
      (description "LED GREEN CLEAR 0603 SMD")
      (fields (field (name "MANUFACTURER") "Lite-On") (field (name "MPN") "LTST-C191KGKT"))
      (libsource (lib "eagle-import") (part "LED0603"))
    )
    (comp (ref "D7")
      (value "LED0603")
      (footprint "eagle-import:LED-0603")
      (description "LED GREEN CLEAR 0603 SMD")
      (fields (field (name "MANUFACTURER") "Lite-On") (field (name "MPN") "LTST-C191KGKT"))
      (libsource (lib "eagle-import") (part "LED0603"))
    )
    (comp (ref "D8")
      (value "LED0603")
      (footprint "eagle-import:LED-0603")
      (description "LED GREEN CLEAR 0603 SMD")
      (fields (field (name "MANUFACTURER") "Lite-On") (field (name "MPN") "LTST-C191KGKT"))
      (libsource (lib "eagle-import") (part "LED0603"))
    )
    (comp (ref "D9")
      (value "LED0603")
      (footprint "eagle-import:LED-0603")
      (description "LED GREEN CLEAR 0603 SMD")
      (fields (field (name "MANUFACTURER") "Lite-On") (field (name "MPN") "LTST-C191KGKT"))
      (libsource (lib "eagle-import") (part "LED0603"))
    )
    (comp (ref "JP1")
      (value "PINHD-2X5")
      (footprint "eagle-import:2X05")
      (libsource (lib "eagle-import") (part "PINHD-2X5"))
    )
    (comp (ref "JP2")
      (value "PINHD-2X5")
      (footprint "eagle-import:2X05")
      (libsource (lib "eagle-import") (part "PINHD-2X5"))
    )
    (comp (ref "JP3")
      (value "PINHD-2X3")
      (footprint "eagle-import:2X03")
      (libsource (lib "eagle-import") (part "PINHD-2X3"))
    )
    (comp (ref "JP4")
      (value "PINHD-2X5")
      (footprint "eagle-import:2X05")
      (libsource (lib "eagle-import") (part "PINHD-2X5"))
    )
    (comp (ref "JP5")
      (value "PINHD-2X5")
      (footprint "eagle-import:2X05")
      (libsource (lib "eagle-import") (part "PINHD-2X5"))
    )
    (comp (ref "JP6")
      (value "PINHD-2X3")
      (footprint "eagle-import:2X03")
      (libsource (lib "eagle-import") (part "PINHD-2X3"))
    )
    (comp (ref "JP7")
      (value "PINHD-2X3")
      (footprint "eagle-import:2X03")
      (libsource (lib "eagle-import") (part "PINHD-2X3"))
    )
    (comp (ref "JP8")
      (value "PINHD-2X3")
      (footprint "eagle-import:2X03")
      (libsource (lib "eagle-import") (part "PINHD-2X3"))
    )
    (comp (ref "JP9")
      (value "PINHD-2X3")
      (footprint "eagle-import:2X03")
      (libsource (lib "eagle-import") (part "PINHD-2X3"))
    )
    (comp (ref "JP10")
      (value "PINHD-2X3")
      (footprint "eagle-import:2X03")
      (libsource (lib "eagle-import") (part "PINHD-2X3"))
    )
    (comp (ref "JP11")
      (value "PINHD-2X5")
      (footprint "eagle-import:2X05")
      (libsource (lib "eagle-import") (part "PINHD-2X5"))
    )
    (comp (ref "JP12")
      (value "PINHD-2X10")
      (footprint "eagle-import:2X10")
      (libsource (lib "eagle-import") (part "PINHD-2X10"))
    )
    (comp (ref "JP13")
      (value "PINHD-1X2")
      (footprint "eagle-import:1X02")
      (libsource (lib "eagle-import") (part "PINHD-1X2"))
    )
    (comp (ref "JP14")
      (value "PINHD-2X3")
      (footprint "eagle-import:2X03")
      (libsource (lib "eagle-import") (part "PINHD-2X3"))
    )
    (comp (ref "JP16")
      (value "PINHD-2X4")
      (footprint "eagle-import:2X04")
      (libsource (lib "eagle-import") (part "PINHD-2X4"))
    )
    (comp (ref "JP17")
      (value "PINHD-1X3")
      (footprint "eagle-import:1X03")
      (libsource (lib "eagle-import") (part "PINHD-1X3"))
    )
    (comp (ref "JP18")
      (value "PINHD-1X3")
      (footprint "eagle-import:1X03")
      (libsource (lib "eagle-import") (part "PINHD-1X3"))
    )
    (comp (ref "JP19")
      (value "PINHD-2X10")
      (footprint "eagle-import:2X10")
      (libsource (lib "eagle-import") (part "PINHD-2X10"))
    )
    (comp (ref "JP20")
      (value "PINHD-2X10")
      (footprint "eagle-import:2X10")
      (libsource (lib "eagle-import") (part "PINHD-2X10"))
    )
    (comp (ref "R23")
      (value "1kΩ")
      (footprint "eagle-import:ARRAY-CONVEX-0603-4")
      (description "RES ARRAY 4 RES 1K OHM 1206")
      (fields
        (field (name "DIGIKEY") "Y9102CT-ND")
        (field (name "MANUFACTURER") "Panasonic")
        (field (name "MPN") "EXB-38V102JV")
      )
      (libsource (lib "eagle-import") (part "RESISTOR-ARRAY-41206"))
    )
    (comp (ref "R24")
      (value "1kΩ")
      (footprint "eagle-import:ARRAY-CONVEX-0603-4")
      (description "RES ARRAY 4 RES 1K OHM 1206")
      (fields
        (field (name "DIGIKEY") "Y9102CT-ND")
        (field (name "MANUFACTURER") "Panasonic")
        (field (name "MPN") "EXB-38V102JV")
      )
      (libsource (lib "eagle-import") (part "RESISTOR-ARRAY-41206"))
    )
    (comp (ref "C18")
      (value "0.1uF")
      (footprint "eagle-import:0603_CAP")
      (description "CAP CER 0.1UF 16V X7R 0603")
      (fields
        (field (name "DIGIKEY") "490-1532-1-ND")
        (field (name "MANUFACTURER") "Murata")
        (field (name "MPN") "GRM188R71C104KA01D")
      )
      (libsource (lib "eagle-import") (part "CAPACITOR0603_CAP"))
    )
    (comp (ref "C19")
      (value "0.1uF")
      (footprint "eagle-import:0603_CAP")
      (description "CAP CER 0.1UF 16V X7R 0603")
      (fields
        (field (name "DIGIKEY") "490-1532-1-ND")
        (field (name "MANUFACTURER") "Murata")
        (field (name "MPN") "GRM188R71C104KA01D")
      )
      (libsource (lib "eagle-import") (part "CAPACITOR0603_CAP"))
    )
    (comp (ref "C20")
      (value "0.1uF")
      (footprint "eagle-import:0603_CAP")
      (description "CAP CER 0.1UF 16V X7R 0603")
      (fields
        (field (name "DIGIKEY") "490-1532-1-ND")
        (field (name "MANUFACTURER") "Murata")
        (field (name "MPN") "GRM188R71C104KA01D")
      )
      (libsource (lib "eagle-import") (part "CAPACITOR0603_CAP"))
    )
    (comp (ref "C21")
      (value "0.1uF")
      (footprint "eagle-import:0603_CAP")
      (description "CAP CER 0.1UF 16V X7R 0603")
      (fields
        (field (name "DIGIKEY") "490-1532-1-ND")
        (field (name "MANUFACTURER") "Murata")
        (field (name "MPN") "GRM188R71C104KA01D")
      )
      (libsource (lib "eagle-import") (part "CAPACITOR0603_CAP"))
    )
    (comp (ref "C22")
      (value "0.1uF")
      (footprint "eagle-import:0603_CAP")
      (description "CAP CER 0.1UF 16V X7R 0603")
      (fields
        (field (name "DIGIKEY") "490-1532-1-ND")
        (field (name "MANUFACTURER") "Murata")
        (field (name "MPN") "GRM188R71C104KA01D")
      )
      (libsource (lib "eagle-import") (part "CAPACITOR0603_CAP"))
    )
    (comp (ref "C23")
      (value "0.1uF")
      (footprint "eagle-import:0603_CAP")
      (description "CAP CER 0.1UF 16V X7R 0603")
      (fields
        (field (name "DIGIKEY") "490-1532-1-ND")
        (field (name "MANUFACTURER") "Murata")
        (field (name "MPN") "GRM188R71C104KA01D")
      )
      (libsource (lib "eagle-import") (part "CAPACITOR0603_CAP"))
    )
    (comp (ref "C24")
      (value "0.1uF")
      (footprint "eagle-import:0603_CAP")
      (description "CAP CER 0.1UF 16V X7R 0603")
      (fields
        (field (name "DIGIKEY") "490-1532-1-ND")
        (field (name "MANUFACTURER") "Murata")
        (field (name "MPN") "GRM188R71C104KA01D")
      )
      (libsource (lib "eagle-import") (part "CAPACITOR0603_CAP"))
    )
    (comp (ref "C25")
      (value "0.1uF")
      (footprint "eagle-import:0603_CAP")
      (description "CAP CER 0.1UF 16V X7R 0603")
      (fields
        (field (name "DIGIKEY") "490-1532-1-ND")
        (field (name "MANUFACTURER") "Murata")
        (field (name "MPN") "GRM188R71C104KA01D")
      )
      (libsource (lib "eagle-import") (part "CAPACITOR0603_CAP"))
    )
    (comp (ref "U24")
      (value "SN74LVC2T45")
      (footprint "eagle-import:VFSOP-8")
      (libsource (lib "eagle-import") (part "SN74LVC2T45"))
    )
    (comp (ref "U25")
      (value "SN74LVC2T45")
      (footprint "eagle-import:VFSOP-8")
      (libsource (lib "eagle-import") (part "SN74LVC2T45"))
    )
    (comp (ref "U26")
      (value "SN74LVC2T45")
      (footprint "eagle-import:VFSOP-8")
      (libsource (lib "eagle-import") (part "SN74LVC2T45"))
    )
    (comp (ref "U27")
      (value "SN74LVC2T45")
      (footprint "eagle-import:VFSOP-8")
      (libsource (lib "eagle-import") (part "SN74LVC2T45"))
    )
    (comp (ref "C9")
      (value "22pF")
      (footprint "eagle-import:0603_CAP")
      (description "CAP CER 22PF 50V C0G/NP0 0603")
      (fields (field (name "MANUFACTURER") "Samsung") (field (name "MPN") "CL10C220JB8NNNC"))
      (libsource (lib "eagle-import") (part "CAPACITOR0603_CAP"))
    )
    (comp (ref "C10")
      (value "22pF")
      (footprint "eagle-import:0603_CAP")
      (description "CAP CER 22PF 50V C0G/NP0 0603")
      (fields (field (name "MANUFACTURER") "Samsung") (field (name "MPN") "CL10C220JB8NNNC"))
      (libsource (lib "eagle-import") (part "CAPACITOR0603_CAP"))
    )
    (comp (ref "C26")
      (value "0.1uF")
      (footprint "eagle-import:0603_CAP")
      (description "CAP CER 0.1UF 16V X7R 0603")
      (fields
        (field (name "DIGIKEY") "490-1532-1-ND")
        (field (name "MANUFACTURER") "Murata")
        (field (name "MPN") "GRM188R71C104KA01D")
      )
      (libsource (lib "eagle-import") (part "CAPACITOR0603_CAP"))
    )
    (comp (ref "C57")
      (value "0.1uF")
      (footprint "eagle-import:0603_CAP")
      (description "CAP CER 0.1UF 16V X7R 0603")
      (fields
        (field (name "DIGIKEY") "490-1532-1-ND")
        (field (name "MANUFACTURER") "Murata")
        (field (name "MPN") "GRM188R71C104KA01D")
      )
      (libsource (lib "eagle-import") (part "CAPACITOR0603_CAP"))
    )
    (comp (ref "C70")
      (value "4.7uF")
      (footprint "eagle-import:0603_CAP")
      (description "CAP CER 4.7UF 6.3V X7R 0603")
      (fields
        (field (name "DIGIKEY") "1276-2087-1-ND")
        (field (name "MANUFACTURER") "Samsung")
        (field (name "MPN") "CL10B475KQ8NQNC")
      )
      (libsource (lib "eagle-import") (part "CAPACITOR0603_CAP"))
    )
    (comp (ref "R27")
      (value "1.5kΩ")
      (footprint "eagle-import:0603-RES")
      (description "RES SMD 1.5K OHM 5% 1/10W 0603")
      (fields (field (name "MANUFACTURER") "Yageo") (field (name "MPN") "RC0603JR-071K5L"))
      (libsource (lib "eagle-import") (part "RESISTOR0603_RES"))
    )
    (comp (ref "R28")
      (value "1.5kΩ")
      (footprint "eagle-import:0603-RES")
      (description "RES SMD 1.5K OHM 5% 1/10W 0603")
      (fields
        (field (name "DIGIKEY") "311-1.5KGRCT-ND")
        (field (name "MANUFACTURER") "Yageo")
        (field (name "MPN") "RC0603JR-071K5L")
      )
      (libsource (lib "eagle-import") (part "RESISTOR0603_RES"))
    )
    (comp (ref "R50")
      (value "10kΩ")
      (footprint "eagle-import:0603-RES")
      (description "RES SMD 10K OHM 5% 1/10W 0603")
      (fields
        (field (name "DIGIKEY") "P10KGCT-ND")
        (field (name "MANUFACTURER") "Panasonic")
        (field (name "MPN") "ERJ-3GEYJ103V")
      )
      (libsource (lib "eagle-import") (part "RESISTOR0603_RES"))
    )
    (comp (ref "R53")
      (value "10kΩ")
      (footprint "eagle-import:0603-RES")
      (description "RES SMD 10K OHM 5% 1/10W 0603")
      (fields
        (field (name "DIGIKEY") "P10KGCT-ND")
        (field (name "MANUFACTURER") "Panasonic")
        (field (name "MPN") "ERJ-3GEYJ103V")
      )
      (libsource (lib "eagle-import") (part "RESISTOR0603_RES"))
    )
    (comp (ref "R62")
      (value "15kΩ")
      (footprint "eagle-import:ARRAY-CONVEX-0603-4")
      (description "RES ARRAY 4 RES 15K OHM 1206")
      (fields
        (field (name "DIGIKEY") "Y9153CT-ND")
        (field (name "MANUFACTURER") "Panasonic")
        (field (name "MPN") "EXB-38V153JV")
      )
      (libsource (lib "eagle-import") (part "RESISTOR-ARRAY-41206"))
    )
    (comp (ref "R63")
      (value "15kΩ")
      (footprint "eagle-import:ARRAY-CONVEX-0603-4")
      (description "RES ARRAY 4 RES 15K OHM 1206")
      (fields
        (field (name "DIGIKEY") "Y9153CT-ND")
        (field (name "MANUFACTURER") "Panasonic")
        (field (name "MPN") "EXB-38V153JV")
      )
      (libsource (lib "eagle-import") (part "RESISTOR-ARRAY-41206"))
    )
    (comp (ref "R64")
      (value "15kΩ")
      (footprint "eagle-import:ARRAY-CONVEX-0603-4")
      (description "RES ARRAY 4 RES 15K OHM 1206")
      (fields
        (field (name "MANUFACTURER") "Panasonic")
        (field (name "MPN") "EXB-38V153JV")
        (field (name "DIGIKEY") "Y9153CT-ND")
      )
      (libsource (lib "eagle-import") (part "RESISTOR-ARRAY-41206"))
    )
    (comp (ref "U19")
      (value "MCP23008QFN")
      (footprint "eagle-import:QFN-20-4MM")
      (libsource (lib "eagle-import") (part "MCP23008QFN"))
    )
    (comp (ref "U21")
      (value "NCP301LSN30")
      (footprint "eagle-import:SOT23-5")
      (libsource (lib "eagle-import") (part "NCP301LSN30"))
    )
    (comp (ref "U31")
      (value "TUSB2077A")
      (footprint "eagle-import:LQFP-48")
      (libsource (lib "eagle-import") (part "TUSB2077A"))
    )
    (comp (ref "Y1")
      (value "ABMM")
      (footprint "eagle-import:ABMM")
      (fields (field (name "MANUFACTURER") "Abracon LLC") (field (name "MPN") "ABMM-6.000MHZ-B2-T"))
      (libsource (lib "eagle-import") (part "ABMM"))
    )
  )
  (nets
    (net (code "1") (name "3V3_UNMETERED") (class "Default")
      (node (ref "C40") (pin "1") (pinfunction "1_1") (pintype "bidirectional"))
      (node (ref "C41") (pin "1") (pinfunction "1_1") (pintype "bidirectional"))
      (node (ref "C42") (pin "1") (pinfunction "1_1") (pintype "bidirectional"))
      (node (ref "C53") (pin "2") (pinfunction "2_2") (pintype "bidirectional"))
      (node (ref "C54") (pin "2") (pinfunction "2_2") (pintype "bidirectional"))
      (node (ref "C67") (pin "1") (pinfunction "1_1") (pintype "bidirectional"))
      (node (ref "C72") (pin "2") (pinfunction "2_2") (pintype "bidirectional"))
      (node (ref "D10") (pin "A") (pinfunction "ANODE_A") (pintype "bidirectional"))
      (node (ref "D11") (pin "A") (pinfunction "ANODE_A") (pintype "bidirectional"))
      (node (ref "D12") (pin "A") (pinfunction "ANODE_A") (pintype "bidirectional"))
      (node (ref "D13") (pin "A") (pinfunction "ANODE_A") (pintype "bidirectional"))
      (node (ref "D19") (pin "A") (pinfunction "ANODE_A") (pintype "bidirectional"))
      (node (ref "D20") (pin "A") (pinfunction "ANODE_A") (pintype "bidirectional"))
      (node (ref "D21") (pin "A") (pinfunction "ANODE_A") (pintype "bidirectional"))
      (node (ref "D22") (pin "A") (pinfunction "ANODE_A") (pintype "bidirectional"))
      (node (ref "D24") (pin "A") (pinfunction "ANODE_A") (pintype "bidirectional"))
      (node (ref "D25") (pin "A") (pinfunction "ANODE_A") (pintype "bidirectional"))
      (node (ref "D34") (pin "A") (pinfunction "ANODE_A") (pintype "bidirectional"))
      (node (ref "FB1") (pin "2") (pinfunction "P$2_2") (pintype "bidirectional"))
      (node (ref "JP11") (pin "3") (pinfunction "3_3") (pintype "passive"))
      (node (ref "JP16") (pin "2") (pinfunction "2_2") (pintype "passive"))
      (node (ref "R31") (pin "2") (pinfunction "2_2") (pintype "passive"))
      (node (ref "R51") (pin "2") (pinfunction "2_2") (pintype "passive"))
      (node (ref "R52") (pin "2") (pinfunction "2_2") (pintype "passive"))
      (node (ref "R65") (pin "2") (pinfunction "2_2") (pintype "passive"))
      (node (ref "R66") (pin "2") (pinfunction "2_2") (pintype "passive"))
      (node (ref "R67") (pin "2") (pinfunction "2_2") (pintype "passive"))
      (node (ref "R85") (pin "2") (pinfunction "2_2") (pintype "passive"))
      (node (ref "S14") (pin "C") (pinfunction "INPUT_C") (pintype "bidirectional"))
      (node (ref "S17") (pin "3") (pinfunction "VSUPP_3") (pintype "bidirectional"))
      (node (ref "S19") (pin "14") (pinfunction "VCC_14") (pintype "bidirectional"))
      (node (ref "S20") (pin "14") (pinfunction "VCC_14") (pintype "bidirectional"))
      (node (ref "S21") (pin "10") (pinfunction "A_10") (pintype "bidirectional"))
      (node (ref "S21") (pin "14") (pinfunction "VCC_14") (pintype "bidirectional"))
      (node (ref "S22") (pin "10") (pinfunction "A_10") (pintype "bidirectional"))
      (node (ref "S22") (pin "14") (pinfunction "VCC_14") (pintype "bidirectional"))
      (node (ref "S23") (pin "10") (pinfunction "A_10") (pintype "bidirectional"))
      (node (ref "S23") (pin "14") (pinfunction "VCC_14") (pintype "bidirectional"))
      (node (ref "S3") (pin "B1") (pinfunction "1TB_B1") (pintype "bidirectional"))
      (node (ref "S3") (pin "B2") (pinfunction "2TB_B2") (pintype "bidirectional"))
      (node (ref "S3") (pin "B3") (pinfunction "3TB_B3") (pintype "bidirectional"))
      (node (ref "S3") (pin "B4") (pinfunction "4TB_B4") (pintype "bidirectional"))
      (node (ref "S4") (pin "B1") (pinfunction "1TB_B1") (pintype "bidirectional"))
      (node (ref "S4") (pin "B2") (pinfunction "2TB_B2") (pintype "bidirectional"))
      (node (ref "S4") (pin "B3") (pinfunction "3TB_B3") (pintype "bidirectional"))
      (node (ref "S4") (pin "B4") (pinfunction "4TB_B4") (pintype "bidirectional"))
      (node (ref "U1") (pin "1") (pinfunction "VCCIO_1") (pintype "power_in"))
      (node (ref "U15") (pin "5") (pinfunction "WDS_5") (pintype "bidirectional"))
      (node (ref "U15") (pin "8") (pinfunction "VCC_8") (pintype "bidirectional"))
      (node (ref "U16") (pin "5") (pinfunction "OUT_5") (pintype "bidirectional"))
      (node (ref "U20") (pin "2") (pinfunction "VCC_2") (pintype "bidirectional"))
      (node (ref "U23") (pin "27") (pinfunction "VLCD_27") (pintype "bidirectional"))
      (node (ref "U23") (pin "31") (pinfunction "VLCDIN_31") (pintype "power_in"))
      (node (ref "U23") (pin "40") (pinfunction "VDDIO_40") (pintype "power_in"))
      (node (ref "U23") (pin "45") (pinfunction "VDDIO_45") (pintype "power_in"))
      (node (ref "U23") (pin "8") (pinfunction "VDDIN_8") (pintype "power_in"))
      (node (ref "U30") (pin "9") (pinfunction "VCC_9") (pintype "bidirectional"))
      (node (ref "U32") (pin "10") (pinfunction "~{BUSPWR}_10") (pintype "bidirectional"))
      (node (ref "U32") (pin "46") (pinfunction "VCC_46") (pintype "bidirectional"))
      (node (ref "U32") (pin "47") (pinfunction "~{EXTMEM}_47") (pintype "bidirectional"))
      (node (ref "U32") (pin "9") (pinfunction "VCC_9") (pintype "bidirectional"))
      (node (ref "U6") (pin "1") (pinfunction "VCCIO_1") (pintype "power_in"))
    )
    (net (code "2") (name "3V3_WATCHDOGGED") (class "Default")
      (node (ref "R1") (pin "2") (pinfunction "2_2") (pintype "passive"))
      (node (ref "R32") (pin "A2") (pinfunction "2_A2") (pintype "passive"))
      (node (ref "R32") (pin "B2") (pinfunction "2_B2") (pintype "passive"))
      (node (ref "R32") (pin "C2") (pinfunction "2_C2") (pintype "passive"))
      (node (ref "S17") (pin "1") (pinfunction "VLOAD_1") (pintype "bidirectional"))
      (node (ref "U9") (pin "1") (pinfunction "SENSE+_1") (pintype "open_collector"))
    )
    (net (code "3") (name "5V_UNMETERED") (class "Default")
      (node (ref "C43") (pin "1") (pinfunction "1_1") (pintype "bidirectional"))
      (node (ref "C46") (pin "1") (pinfunction "1_1") (pintype "bidirectional"))
      (node (ref "C48") (pin "1") (pinfunction "1_1") (pintype "bidirectional"))
      (node (ref "C50") (pin "1") (pinfunction "1_1") (pintype "bidirectional"))
      (node (ref "C52") (pin "1") (pinfunction "1_1") (pintype "bidirectional"))
      (node (ref "C55") (pin "1") (pinfunction "1_1") (pintype "bidirectional"))
      (node (ref "C66") (pin "1") (pinfunction "1_1") (pintype "bidirectional"))
      (node (ref "C71") (pin "1") (pinfunction "1_1") (pintype "bidirectional"))
      (node (ref "D23") (pin "A") (pinfunction "ANODE_A") (pintype "bidirectional"))
      (node (ref "JP11") (pin "1") (pinfunction "1_1") (pintype "passive"))
      (node (ref "JP16") (pin "1") (pinfunction "1_1") (pintype "passive"))
      (node (ref "Q8") (pin "2") (pinfunction "S_2") (pintype "passive"))
      (node (ref "R48") (pin "2") (pinfunction "2_2") (pintype "passive"))
      (node (ref "S18") (pin "3") (pinfunction "VSUPP_3") (pintype "bidirectional"))
      (node (ref "U1") (pin "18") (pinfunction "~{RESET}_18") (pintype "input"))
      (node (ref "U1") (pin "19") (pinfunction "VCC_19") (pintype "power_in"))
      (node (ref "U13") (pin "7") (pinfunction "OUT_7") (pintype "bidirectional"))
      (node (ref "U16") (pin "1") (pinfunction "IN_1") (pintype "bidirectional"))
      (node (ref "U2") (pin "18") (pinfunction "~{RESET}_18") (pintype "input"))
      (node (ref "U2") (pin "19") (pinfunction "VCC_19") (pintype "power_in"))
      (node (ref "U3") (pin "18") (pinfunction "~{RESET}_18") (pintype "input"))
      (node (ref "U3") (pin "19") (pinfunction "VCC_19") (pintype "power_in"))
      (node (ref "U4") (pin "18") (pinfunction "~{RESET}_18") (pintype "input"))
      (node (ref "U4") (pin "19") (pinfunction "VCC_19") (pintype "power_in"))
      (node (ref "U5") (pin "18") (pinfunction "~{RESET}_18") (pintype "input"))
      (node (ref "U5") (pin "19") (pinfunction "VCC_19") (pintype "power_in"))
      (node (ref "U6") (pin "18") (pinfunction "~{RESET}_18") (pintype "input"))
      (node (ref "U6") (pin "19") (pinfunction "VCC_19") (pintype "power_in"))
    )
    (net (code "4") (name "5V_WATCHDOGGED") (class "Default")
      (node (ref "R2") (pin "2") (pinfunction "2_2") (pintype "passive"))
      (node (ref "R3") (pin "2") (pinfunction "2_2") (pintype "passive"))
      (node (ref "R33") (pin "A2") (pinfunction "2_A2") (pintype "passive"))
      (node (ref "R33") (pin "B2") (pinfunction "2_B2") (pintype "passive"))
      (node (ref "R33") (pin "C2") (pinfunction "2_C2") (pintype "passive"))
      (node (ref "R34") (pin "A2") (pinfunction "2_A2") (pintype "passive"))
      (node (ref "R34") (pin "B2") (pinfunction "2_B2") (pintype "passive"))
      (node (ref "R34") (pin "C2") (pinfunction "2_C2") (pintype "passive"))
      (node (ref "R35") (pin "A2") (pinfunction "2_A2") (pintype "passive"))
      (node (ref "R35") (pin "B2") (pinfunction "2_B2") (pintype "passive"))
      (node (ref "R35") (pin "C2") (pinfunction "2_C2") (pintype "passive"))
      (node (ref "R4") (pin "2") (pinfunction "2_2") (pintype "passive"))
      (node (ref "S18") (pin "1") (pinfunction "VLOAD_1") (pintype "bidirectional"))
      (node (ref "U10") (pin "P1") (pinfunction "SENSE+_P1") (pintype "open_collector"))
      (node (ref "U11") (pin "P1") (pinfunction "SENSE+_P1") (pintype "open_collector"))
      (node (ref "U12") (pin "P1") (pinfunction "SENSE+_P1") (pintype "open_collector"))
    )
    (net (code "5") (name "CONT0_DBG_GPIO1") (class "Default")
      (node (ref "J1") (pin "101") (pinfunction "DBG_GPIO1_101") (pintype "bidirectional"))
      (node (ref "JP9") (pin "5") (pinfunction "5_5") (pintype "passive"))
      (node (ref "Q4") (pin "G1") (pinfunction "G1_G1") (pintype "input"))
      (node (ref "R73") (pin "2") (pinfunction "2_2") (pintype "passive"))
    )
    (net (code "6") (name "CONT0_DBG_GPIO2") (class "Default")
      (node (ref "J1") (pin "104") (pinfunction "DBG_GPIO2_104") (pintype "bidirectional"))
      (node (ref "JP9") (pin "2") (pinfunction "2_2") (pintype "passive"))
      (node (ref "Q4") (pin "G2") (pinfunction "G2_G2") (pintype "input"))
      (node (ref "R74") (pin "2") (pinfunction "2_2") (pintype "passive"))
    )
    (net (code "7") (name "CONT0_DBG_RX") (class "Default")
      (node (ref "J1") (pin "103") (pinfunction "DBG_RX_103") (pintype "bidirectional"))
      (node (ref "JP9") (pin "3") (pinfunction "3_3") (pintype "passive"))
      (node (ref "U4") (pin "30") (pinfunction "TXD_30") (pintype "output"))
    )
    (net (code "8") (name "CONT0_DBG_TX") (class "Default")
      (node (ref "J1") (pin "102") (pinfunction "DBG_TX_102") (pintype "bidirectional"))
      (node (ref "JP9") (pin "4") (pinfunction "4_4") (pintype "passive"))
      (node (ref "U4") (pin "2") (pinfunction "RXD_2") (pintype "input"))
    )
    (net (code "9") (name "CONT0_SWDCLK") (class "Default")
      (node (ref "J1") (pin "106") (pinfunction "DBG_SWDCLK_106") (pintype "bidirectional"))
      (node (ref "S21") (pin "3") (pinfunction "A_3") (pintype "bidirectional"))
    )
    (net (code "10") (name "CONT0_SWDIO") (class "Default")
      (node (ref "J1") (pin "107") (pinfunction "DBG_SWDIO_107") (pintype "bidirectional"))
      (node (ref "S21") (pin "2") (pinfunction "A_2") (pintype "bidirectional"))
    )
    (net (code "11") (name "CONT0_~{RESET}") (class "Default")
      (node (ref "D1") (pin "3A") (pinfunction "ANODE_3A") (pintype "bidirectional"))
      (node (ref "J1") (pin "105") (pinfunction "DBG_~{RESET}_105") (pintype "bidirectional"))
      (node (ref "JP9") (pin "1") (pinfunction "1_1") (pintype "passive"))
      (node (ref "S10") (pin "3") (pinfunction "P$2_3") (pintype "passive"))
      (node (ref "S10") (pin "4") (pinfunction "P$2_4") (pintype "passive"))
      (node (ref "S21") (pin "9") (pinfunction "A_9") (pintype "bidirectional"))
    )
    (net (code "12") (name "CONT1_DBG_GPIO1") (class "Default")
      (node (ref "J1") (pin "201") (pinfunction "DBG_GPIO1_201") (pintype "bidirectional"))
      (node (ref "JP10") (pin "5") (pinfunction "5_5") (pintype "passive"))
      (node (ref "Q5") (pin "G1") (pinfunction "G1_G1") (pintype "input"))
      (node (ref "R75") (pin "2") (pinfunction "2_2") (pintype "passive"))
    )
    (net (code "13") (name "CONT1_DBG_GPIO2") (class "Default")
      (node (ref "J1") (pin "204") (pinfunction "DBG_GPIO2_204") (pintype "bidirectional"))
      (node (ref "JP10") (pin "2") (pinfunction "2_2") (pintype "passive"))
      (node (ref "Q5") (pin "G2") (pinfunction "G2_G2") (pintype "input"))
      (node (ref "R76") (pin "2") (pinfunction "2_2") (pintype "passive"))
    )
    (net (code "14") (name "CONT1_DBG_RX") (class "Default")
      (node (ref "J1") (pin "203") (pinfunction "DBG_RX_203") (pintype "bidirectional"))
      (node (ref "JP10") (pin "3") (pinfunction "3_3") (pintype "passive"))
      (node (ref "U5") (pin "30") (pinfunction "TXD_30") (pintype "output"))
    )
    (net (code "15") (name "CONT1_DBG_TX") (class "Default")
      (node (ref "J1") (pin "202") (pinfunction "DBG_TX_202") (pintype "bidirectional"))
      (node (ref "JP10") (pin "4") (pinfunction "4_4") (pintype "passive"))
      (node (ref "U5") (pin "2") (pinfunction "RXD_2") (pintype "input"))
    )
    (net (code "16") (name "CONT1_SWDCLK") (class "Default")
      (node (ref "J1") (pin "206") (pinfunction "DBG_SWDCLK_206") (pintype "bidirectional"))
      (node (ref "S22") (pin "3") (pinfunction "A_3") (pintype "bidirectional"))
    )
    (net (code "17") (name "CONT1_SWDIO") (class "Default")
      (node (ref "J1") (pin "207") (pinfunction "DBG_SWDIO_207") (pintype "bidirectional"))
      (node (ref "S22") (pin "2") (pinfunction "A_2") (pintype "bidirectional"))
    )
    (net (code "18") (name "CONT1_~{RESET}") (class "Default")
      (node (ref "D1") (pin "4A") (pinfunction "ANODE_4A") (pintype "bidirectional"))
      (node (ref "J1") (pin "205") (pinfunction "DBG_~{RESET}_205") (pintype "bidirectional"))
      (node (ref "JP10") (pin "1") (pinfunction "1_1") (pintype "passive"))
      (node (ref "S11") (pin "3") (pinfunction "P$2_3") (pintype "passive"))
      (node (ref "S11") (pin "4") (pinfunction "P$2_4") (pintype "passive"))
      (node (ref "S22") (pin "9") (pinfunction "A_9") (pintype "bidirectional"))
    )
    (net (code "19") (name "CONT_HDR_BOT_RSV_PIN6") (class "Default")
      (node (ref "JP14") (pin "6") (pinfunction "6_6") (pintype "passive"))
    )
    (net (code "20") (name "CONT_HDR_BOT_RSV_PIN9") (class "Default")
      (node (ref "JP13") (pin "1") (pinfunction "1_1") (pintype "passive"))
    )
    (net (code "21") (name "CONT_HDR_BOT_RSV_PIN10") (class "Default")
      (node (ref "JP13") (pin "2") (pinfunction "2_2") (pintype "passive"))
    )
    (net (code "22") (name "CONT_HDR_TOP_RSV_PIN8") (class "Default")
      (node (ref "JP12") (pin "8") (pinfunction "8_8") (pintype "passive"))
    )
    (net (code "23") (name "CONT_MOD0_IN") (class "Default")
      (node (ref "J1") (pin "9") (pinfunction "MOD0_IN_9") (pintype "bidirectional"))
      (node (ref "JP12") (pin "9") (pinfunction "9_9") (pintype "passive"))
      (node (ref "U24") (pin "2") (pinfunction "A1_2") (pintype "bidirectional"))
    )
    (net (code "24") (name "CONT_MOD0_OUT") (class "Default")
      (node (ref "J1") (pin "10") (pinfunction "MOD0_OUT_10") (pintype "bidirectional"))
      (node (ref "JP12") (pin "10") (pinfunction "10_10") (pintype "passive"))
      (node (ref "U26") (pin "2") (pinfunction "A1_2") (pintype "bidirectional"))
    )
    (net (code "25") (name "CONT_MOD1_IN") (class "Default")
      (node (ref "J1") (pin "11") (pinfunction "MOD1_IN_11") (pintype "bidirectional"))
      (node (ref "JP12") (pin "11") (pinfunction "11_11") (pintype "passive"))
      (node (ref "U25") (pin "2") (pinfunction "A1_2") (pintype "bidirectional"))
    )
    (net (code "26") (name "CONT_MOD1_OUT") (class "Default")
      (node (ref "J1") (pin "12") (pinfunction "MOD1_OUT_12") (pintype "bidirectional"))
      (node (ref "JP12") (pin "12") (pinfunction "12_12") (pintype "passive"))
      (node (ref "U27") (pin "2") (pinfunction "A1_2") (pintype "bidirectional"))
    )
    (net (code "27") (name "CONT_MOD2_IN") (class "Default")
      (node (ref "J1") (pin "13") (pinfunction "MOD2_IN_13") (pintype "bidirectional"))
      (node (ref "JP12") (pin "13") (pinfunction "13_13") (pintype "passive"))
      (node (ref "U23") (pin "39") (pinfunction "PA20_39") (pintype "bidirectional"))
    )
    (net (code "28") (name "CONT_MOD2_OUT") (class "Default")
      (node (ref "J1") (pin "14") (pinfunction "MOD2_OUT_14") (pintype "bidirectional"))
      (node (ref "JP12") (pin "14") (pinfunction "14_14") (pintype "passive"))
      (node (ref "U23") (pin "38") (pinfunction "PA19_38") (pintype "bidirectional"))
    )
    (net (code "29") (name "CONT_MOD5_IN") (class "Default")
      (node (ref "J1") (pin "15") (pinfunction "MOD5_IN_15") (pintype "bidirectional"))
      (node (ref "JP12") (pin "15") (pinfunction "15_15") (pintype "passive"))
    )
    (net (code "30") (name "CONT_MOD5_OUT") (class "Default")
      (node (ref "J1") (pin "16") (pinfunction "MOD5_OUT_16") (pintype "bidirectional"))
      (node (ref "JP12") (pin "16") (pinfunction "16_16") (pintype "passive"))
    )
    (net (code "31") (name "CONT_MOD6_IN") (class "Default")
      (node (ref "J1") (pin "17") (pinfunction "MOD6_IN_17") (pintype "bidirectional"))
      (node (ref "JP12") (pin "17") (pinfunction "17_17") (pintype "passive"))
    )
    (net (code "32") (name "CONT_MOD6_OUT") (class "Default")
      (node (ref "J1") (pin "18") (pinfunction "MOD6_OUT_18") (pintype "bidirectional"))
      (node (ref "JP12") (pin "18") (pinfunction "18_18") (pintype "passive"))
    )
    (net (code "33") (name "CONT_MOD7_IN") (class "Default")
      (node (ref "J1") (pin "19") (pinfunction "MOD7_IN_19") (pintype "bidirectional"))
      (node (ref "JP12") (pin "19") (pinfunction "19_19") (pintype "passive"))
    )
    (net (code "34") (name "CONT_MOD7_OUT") (class "Default")
      (node (ref "J1") (pin "20") (pinfunction "MOD7_OUT_20") (pintype "bidirectional"))
      (node (ref "JP12") (pin "20") (pinfunction "20_20") (pintype "passive"))
    )
    (net (code "35") (name "CONT_USB+") (class "Default")
      (node (ref "J1") (pin "27") (pinfunction "USB_D+_27") (pintype "bidirectional"))
      (node (ref "U30") (pin "6") (pinfunction "D2-_6") (pintype "bidirectional"))
    )
    (net (code "36") (name "CONT_USB-") (class "Default")
      (node (ref "J1") (pin "28") (pinfunction "USB_D-_28") (pintype "bidirectional"))
      (node (ref "U30") (pin "2") (pinfunction "D2+_2") (pintype "bidirectional"))
    )
    (net (code "37") (name "DBG_USB_DM0") (class "Default")
      (node (ref "J5") (pin "2") (pinfunction "D-_2") (pintype "bidirectional"))
      (node (ref "U32") (pin "4") (pinfunction "DM0_4") (pintype "bidirectional"))
    )
    (net (code "38") (name "DBG_USB_DM1") (class "Default")
      (node (ref "U32") (pin "13") (pinfunction "DM1_13") (pintype "bidirectional"))
      (node (ref "U6") (pin "15") (pinfunction "USBDM_15") (pintype "bidirectional"))
    )
    (net (code "39") (name "DBG_USB_DM2") (class "Default")
      (node (ref "U1") (pin "15") (pinfunction "USBDM_15") (pintype "bidirectional"))
      (node (ref "U32") (pin "17") (pinfunction "DM2_17") (pintype "bidirectional"))
    )
    (net (code "40") (name "DBG_USB_DM3") (class "Default")
      (node (ref "U32") (pin "21") (pinfunction "DM3_21") (pintype "bidirectional"))
      (node (ref "U5") (pin "15") (pinfunction "USBDM_15") (pintype "bidirectional"))
    )
    (net (code "41") (name "DBG_USB_DM4") (class "Default")
      (node (ref "U32") (pin "26") (pinfunction "DM4_26") (pintype "bidirectional"))
      (node (ref "U4") (pin "15") (pinfunction "USBDM_15") (pintype "bidirectional"))
    )
    (net (code "42") (name "DBG_USB_DM5") (class "Default")
      (node (ref "R61") (pin "1") (pinfunction "1_1") (pintype "passive"))
      (node (ref "U32") (pin "30") (pinfunction "DM5_30") (pintype "bidirectional"))
    )
    (net (code "43") (name "DBG_USB_DM6") (class "Default")
      (node (ref "U3") (pin "15") (pinfunction "USBDM_15") (pintype "bidirectional"))
      (node (ref "U32") (pin "34") (pinfunction "DM6_34") (pintype "bidirectional"))
    )
    (net (code "44") (name "DBG_USB_DM7") (class "Default")
      (node (ref "U2") (pin "15") (pinfunction "USBDM_15") (pintype "bidirectional"))
      (node (ref "U32") (pin "38") (pinfunction "DM7_38") (pintype "bidirectional"))
    )
    (net (code "45") (name "DBG_USB_DP0") (class "Default")
      (node (ref "J5") (pin "3") (pinfunction "D+_3") (pintype "bidirectional"))
      (node (ref "R29") (pin "1") (pinfunction "1_1") (pintype "passive"))
      (node (ref "U32") (pin "3") (pinfunction "DP0_3") (pintype "bidirectional"))
    )
    (net (code "46") (name "DBG_USB_DP1") (class "Default")
      (node (ref "U32") (pin "14") (pinfunction "DP1_14") (pintype "bidirectional"))
      (node (ref "U6") (pin "14") (pinfunction "USBDP_14") (pintype "bidirectional"))
    )
    (net (code "47") (name "DBG_USB_DP2") (class "Default")
      (node (ref "U1") (pin "14") (pinfunction "USBDP_14") (pintype "bidirectional"))
      (node (ref "U32") (pin "18") (pinfunction "DP2_18") (pintype "bidirectional"))
    )
    (net (code "48") (name "DBG_USB_DP3") (class "Default")
      (node (ref "U32") (pin "22") (pinfunction "DP3_22") (pintype "bidirectional"))
      (node (ref "U5") (pin "14") (pinfunction "USBDP_14") (pintype "bidirectional"))
    )
    (net (code "49") (name "DBG_USB_DP4") (class "Default")
      (node (ref "U32") (pin "27") (pinfunction "DP4_27") (pintype "bidirectional"))
      (node (ref "U4") (pin "14") (pinfunction "USBDP_14") (pintype "bidirectional"))
    )
    (net (code "50") (name "DBG_USB_DP5") (class "Default")
      (node (ref "R60") (pin "1") (pinfunction "1_1") (pintype "passive"))
      (node (ref "U32") (pin "31") (pinfunction "DP5_31") (pintype "bidirectional"))
    )
    (net (code "51") (name "DBG_USB_DP6") (class "Default")
      (node (ref "U3") (pin "14") (pinfunction "USBDP_14") (pintype "bidirectional"))
      (node (ref "U32") (pin "35") (pinfunction "DP6_35") (pintype "bidirectional"))
    )
    (net (code "52") (name "DBG_USB_DP7") (class "Default")
      (node (ref "U2") (pin "14") (pinfunction "USBDP_14") (pintype "bidirectional"))
      (node (ref "U32") (pin "39") (pinfunction "DP7_39") (pintype "bidirectional"))
    )
    (net (code "53") (name "DBG_USB_HUBCFG") (class "Default")
      (node (ref "TP1") (pin "TESTPOINT") (pinfunction "TESTPOINT_TESTPOINT") (pintype "bidirectional"))
      (node (ref "U32") (pin "40") (pinfunction "HUBCFG_40") (pintype "bidirectional"))
    )
    (net (code "54") (name "DBG_USB_PORTDIS") (class "Default")
      (node (ref "TP3") (pin "TESTPOINT") (pinfunction "TESTPOINT_TESTPOINT") (pintype "bidirectional"))
      (node (ref "U32") (pin "42") (pinfunction "PORTDIS_42") (pintype "bidirectional"))
    )
    (net (code "55") (name "DBG_USB_PORTPWR") (class "Default")
      (node (ref "TP2") (pin "TESTPOINT") (pinfunction "TESTPOINT_TESTPOINT") (pintype "bidirectional"))
      (node (ref "U32") (pin "41") (pinfunction "PORTPWR_41") (pintype "bidirectional"))
    )
    (net (code "56") (name "DEBUG_HUB_~{OVRCURX}") (class "Default")
      (node (ref "R51") (pin "1") (pinfunction "1_1") (pintype "passive"))
      (node (ref "U32") (pin "12") (pinfunction "~{OVRCUR1}_12") (pintype "bidirectional"))
      (node (ref "U32") (pin "16") (pinfunction "~{OVRCUR2}_16") (pintype "bidirectional"))
      (node (ref "U32") (pin "20") (pinfunction "~{OVRCUR3}_20") (pintype "bidirectional"))
      (node (ref "U32") (pin "25") (pinfunction "~{OVRCUR4}_25") (pintype "bidirectional"))
      (node (ref "U32") (pin "29") (pinfunction "~{OVRCUR5}_29") (pintype "bidirectional"))
      (node (ref "U32") (pin "33") (pinfunction "~{OVRCUR6}_33") (pintype "bidirectional"))
      (node (ref "U32") (pin "37") (pinfunction "~{OVRCUR7}_37") (pintype "bidirectional"))
    )
    (net (code "57") (name "FAKE_RADIO_XIN") (class "Default")
      (node (ref "C1") (pin "1") (pinfunction "1_1") (pintype "bidirectional"))
      (node (ref "U23") (pin "1") (pinfunction "PA00_1") (pintype "bidirectional"))
      (node (ref "Y3") (pin "3") (pinfunction "2_3") (pintype "bidirectional"))
    )
    (net (code "58") (name "FAKE_RADIO_XOUT") (class "Default")
      (node (ref "C2") (pin "1") (pinfunction "1_1") (pintype "bidirectional"))
      (node (ref "U23") (pin "2") (pinfunction "PA01_2") (pintype "bidirectional"))
      (node (ref "Y3") (pin "1") (pinfunction "1_1") (pintype "bidirectional"))
    )
    (net (code "59") (name "GND") (class "Default")
      (node (ref "C1") (pin "2") (pinfunction "2_2") (pintype "bidirectional"))
      (node (ref "C10") (pin "1") (pinfunction "1_1") (pintype "bidirectional"))
      (node (ref "C11") (pin "1") (pinfunction "1_1") (pintype "bidirectional"))
      (node (ref "C12") (pin "1") (pinfunction "1_1") (pintype "bidirectional"))
      (node (ref "C13") (pin "2") (pinfunction "2_2") (pintype "bidirectional"))
      (node (ref "C14") (pin "2") (pinfunction "2_2") (pintype "bidirectional"))
      (node (ref "C15") (pin "2") (pinfunction "2_2") (pintype "bidirectional"))
      (node (ref "C16") (pin "2") (pinfunction "2_2") (pintype "bidirectional"))
      (node (ref "C17") (pin "2") (pinfunction "2_2") (pintype "bidirectional"))
      (node (ref "C18") (pin "2") (pinfunction "2_2") (pintype "bidirectional"))
      (node (ref "C19") (pin "2") (pinfunction "2_2") (pintype "bidirectional"))
      (node (ref "C2") (pin "2") (pinfunction "2_2") (pintype "bidirectional"))
      (node (ref "C20") (pin "2") (pinfunction "2_2") (pintype "bidirectional"))
      (node (ref "C21") (pin "2") (pinfunction "2_2") (pintype "bidirectional"))
      (node (ref "C22") (pin "2") (pinfunction "2_2") (pintype "bidirectional"))
      (node (ref "C23") (pin "2") (pinfunction "2_2") (pintype "bidirectional"))
      (node (ref "C24") (pin "2") (pinfunction "2_2") (pintype "bidirectional"))
      (node (ref "C25") (pin "2") (pinfunction "2_2") (pintype "bidirectional"))
      (node (ref "C26") (pin "1") (pinfunction "1_1") (pintype "bidirectional"))
      (node (ref "C27") (pin "2") (pinfunction "2_2") (pintype "bidirectional"))
      (node (ref "C28") (pin "2") (pinfunction "2_2") (pintype "bidirectional"))
      (node (ref "C29") (pin "2") (pinfunction "2_2") (pintype "bidirectional"))
      (node (ref "C3") (pin "2") (pinfunction "2_2") (pintype "bidirectional"))
      (node (ref "C30") (pin "2") (pinfunction "2_2") (pintype "bidirectional"))
      (node (ref "C31") (pin "2") (pinfunction "2_2") (pintype "bidirectional"))
      (node (ref "C32") (pin "2") (pinfunction "2_2") (pintype "bidirectional"))
      (node (ref "C33") (pin "2") (pinfunction "2_2") (pintype "bidirectional"))
      (node (ref "C34") (pin "2") (pinfunction "2_2") (pintype "bidirectional"))
      (node (ref "C35") (pin "1") (pinfunction "1_1") (pintype "bidirectional"))
      (node (ref "C36") (pin "1") (pinfunction "1_1") (pintype "bidirectional"))
      (node (ref "C37") (pin "2") (pinfunction "2_2") (pintype "bidirectional"))
      (node (ref "C38") (pin "2") (pinfunction "2_2") (pintype "bidirectional"))
      (node (ref "C39") (pin "2") (pinfunction "2_2") (pintype "bidirectional"))
      (node (ref "C4") (pin "2") (pinfunction "2_2") (pintype "bidirectional"))
      (node (ref "C40") (pin "2") (pinfunction "2_2") (pintype "bidirectional"))
      (node (ref "C41") (pin "2") (pinfunction "2_2") (pintype "bidirectional"))
      (node (ref "C42") (pin "2") (pinfunction "2_2") (pintype "bidirectional"))
      (node (ref "C43") (pin "2") (pinfunction "2_2") (pintype "bidirectional"))
      (node (ref "C44") (pin "2") (pinfunction "2_2") (pintype "bidirectional"))
      (node (ref "C45") (pin "2") (pinfunction "2_2") (pintype "bidirectional"))
      (node (ref "C46") (pin "2") (pinfunction "2_2") (pintype "bidirectional"))
      (node (ref "C47") (pin "2") (pinfunction "2_2") (pintype "bidirectional"))
      (node (ref "C48") (pin "2") (pinfunction "2_2") (pintype "bidirectional"))
      (node (ref "C49") (pin "2") (pinfunction "2_2") (pintype "bidirectional"))
      (node (ref "C5") (pin "2") (pinfunction "2_2") (pintype "bidirectional"))
      (node (ref "C50") (pin "2") (pinfunction "2_2") (pintype "bidirectional"))
      (node (ref "C51") (pin "2") (pinfunction "2_2") (pintype "bidirectional"))
      (node (ref "C52") (pin "2") (pinfunction "2_2") (pintype "bidirectional"))
      (node (ref "C53") (pin "1") (pinfunction "1_1") (pintype "bidirectional"))
      (node (ref "C54") (pin "1") (pinfunction "1_1") (pintype "bidirectional"))
      (node (ref "C55") (pin "2") (pinfunction "2_2") (pintype "bidirectional"))
      (node (ref "C56") (pin "2") (pinfunction "2_2") (pintype "bidirectional"))
      (node (ref "C57") (pin "2") (pinfunction "2_2") (pintype "bidirectional"))
      (node (ref "C58") (pin "2") (pinfunction "2_2") (pintype "bidirectional"))
      (node (ref "C59") (pin "2") (pinfunction "2_2") (pintype "bidirectional"))
      (node (ref "C6") (pin "2") (pinfunction "2_2") (pintype "bidirectional"))
      (node (ref "C60") (pin "2") (pinfunction "2_2") (pintype "bidirectional"))
      (node (ref "C61") (pin "2") (pinfunction "2_2") (pintype "bidirectional"))
      (node (ref "C62") (pin "2") (pinfunction "2_2") (pintype "bidirectional"))
      (node (ref "C63") (pin "2") (pinfunction "2_2") (pintype "bidirectional"))
      (node (ref "C64") (pin "2") (pinfunction "2_2") (pintype "bidirectional"))
      (node (ref "C65") (pin "2") (pinfunction "2_2") (pintype "bidirectional"))
      (node (ref "C66") (pin "2") (pinfunction "2_2") (pintype "bidirectional"))
      (node (ref "C67") (pin "2") (pinfunction "2_2") (pintype "bidirectional"))
      (node (ref "C68") (pin "2") (pinfunction "2_2") (pintype "bidirectional"))
      (node (ref "C69") (pin "2") (pinfunction "2_2") (pintype "bidirectional"))
      (node (ref "C7") (pin "2") (pinfunction "2_2") (pintype "bidirectional"))
      (node (ref "C70") (pin "1") (pinfunction "1_1") (pintype "bidirectional"))
      (node (ref "C71") (pin "2") (pinfunction "2_2") (pintype "bidirectional"))
      (node (ref "C72") (pin "1") (pinfunction "1_1") (pintype "bidirectional"))
      (node (ref "C73") (pin "2") (pinfunction "2_2") (pintype "bidirectional"))
      (node (ref "C74") (pin "2") (pinfunction "2_2") (pintype "bidirectional"))
      (node (ref "C75") (pin "2") (pinfunction "2_2") (pintype "bidirectional"))
      (node (ref "C8") (pin "2") (pinfunction "2_2") (pintype "bidirectional"))
      (node (ref "C9") (pin "1") (pinfunction "1_1") (pintype "bidirectional"))
      (node (ref "D35") (pin "1") (pinfunction "GND_1") (pintype "bidirectional"))
      (node (ref "D35") (pin "3") (pinfunction "GND_3") (pintype "bidirectional"))
      (node (ref "D35") (pin "5") (pinfunction "GND_5") (pintype "bidirectional"))
      (node (ref "D35") (pin "7") (pinfunction "GND_7") (pintype "bidirectional"))
      (node (ref "D36") (pin "1") (pinfunction "GND_1") (pintype "bidirectional"))
      (node (ref "D36") (pin "3") (pinfunction "GND_3") (pintype "bidirectional"))
      (node (ref "D36") (pin "5") (pinfunction "GND_5") (pintype "bidirectional"))
      (node (ref "D36") (pin "7") (pinfunction "GND_7") (pintype "bidirectional"))
      (node (ref "H1") (pin "B#4") (pinfunction "MOUNT_B#4") (pintype "passive"))
      (node (ref "H2") (pin "B#4") (pinfunction "MOUNT_B#4") (pintype "passive"))
      (node (ref "H3") (pin "B#4") (pinfunction "MOUNT_B#4") (pintype "passive"))
      (node (ref "H4") (pin "B#4") (pinfunction "MOUNT_B#4") (pintype "passive"))
      (node (ref "H5") (pin "B#4") (pinfunction "MOUNT_B#4") (pintype "passive"))
      (node (ref "H6") (pin "B#4") (pinfunction "MOUNT_B#4") (pintype "passive"))
      (node (ref "H7") (pin "B#4") (pinfunction "MOUNT_B#4") (pintype "passive"))
      (node (ref "H8") (pin "B#4") (pinfunction "MOUNT_B#4") (pintype "passive"))
      (node (ref "J1") (pin "1") (pinfunction "GND_1") (pintype "bidirectional"))
      (node (ref "J1") (pin "100") (pinfunction "GND1_100") (pintype "bidirectional"))
      (node (ref "J1") (pin "200") (pinfunction "GND1_200") (pintype "bidirectional"))
      (node (ref "J1") (pin "21") (pinfunction "GND_21") (pintype "bidirectional"))
      (node (ref "J1") (pin "MNT1") (pinfunction "GND_MNT1") (pintype "bidirectional"))
      (node (ref "J1") (pin "MNT2") (pinfunction "GND_MNT2") (pintype "bidirectional"))
      (node (ref "J1") (pin "MNT3") (pinfunction "GND_MNT3") (pintype "bidirectional"))
      (node (ref "J1") (pin "MNT4") (pinfunction "GND_MNT4") (pintype "bidirectional"))
      (node (ref "J2") (pin "1") (pinfunction "GND_1") (pintype "bidirectional"))
      (node (ref "J2") (pin "14") (pinfunction "GND_14") (pintype "bidirectional"))
      (node (ref "J2") (pin "15") (pinfunction "GND_15") (pintype "bidirectional"))
      (node (ref "J2") (pin "MNT1") (pinfunction "GND_MNT1") (pintype "bidirectional"))
      (node (ref "J2") (pin "MNT2") (pinfunction "GND_MNT2") (pintype "bidirectional"))
      (node (ref "J2") (pin "MNT3") (pinfunction "GND_MNT3") (pintype "bidirectional"))
      (node (ref "J2") (pin "MNT4") (pinfunction "GND_MNT4") (pintype "bidirectional"))
      (node (ref "J3") (pin "1") (pinfunction "GND_1") (pintype "bidirectional"))
      (node (ref "J3") (pin "14") (pinfunction "GND_14") (pintype "bidirectional"))
      (node (ref "J3") (pin "15") (pinfunction "GND_15") (pintype "bidirectional"))
      (node (ref "J3") (pin "MNT1") (pinfunction "GND_MNT1") (pintype "bidirectional"))
      (node (ref "J3") (pin "MNT2") (pinfunction "GND_MNT2") (pintype "bidirectional"))
      (node (ref "J3") (pin "MNT3") (pinfunction "GND_MNT3") (pintype "bidirectional"))
      (node (ref "J3") (pin "MNT4") (pinfunction "GND_MNT4") (pintype "bidirectional"))
      (node (ref "J4") (pin "5") (pinfunction "GND_5") (pintype "bidirectional"))
      (node (ref "J5") (pin "5") (pinfunction "GND_5") (pintype "bidirectional"))
      (node (ref "J6") (pin "10") (pinfunction "10_10") (pintype "passive"))
      (node (ref "J6") (pin "12") (pinfunction "12_12") (pintype "passive"))
      (node (ref "J6") (pin "14") (pinfunction "14_14") (pintype "passive"))
      (node (ref "J6") (pin "16") (pinfunction "16_16") (pintype "passive"))
      (node (ref "J6") (pin "18") (pinfunction "18_18") (pintype "passive"))
      (node (ref "J6") (pin "20") (pinfunction "20_20") (pintype "passive"))
      (node (ref "J6") (pin "4") (pinfunction "4_4") (pintype "passive"))
      (node (ref "J6") (pin "6") (pinfunction "6_6") (pintype "passive"))
      (node (ref "J6") (pin "8") (pinfunction "8_8") (pintype "passive"))
      (node (ref "J7") (pin "2") (pinfunction "GND_2") (pintype "bidirectional"))
      (node (ref "J8") (pin "3") (pinfunction "GND_3") (pintype "bidirectional"))
      (node (ref "JP1") (pin "2") (pinfunction "2_2") (pintype "passive"))
      (node (ref "JP1") (pin "9") (pinfunction "9_9") (pintype "passive"))
      (node (ref "JP10") (pin "6") (pinfunction "6_6") (pintype "passive"))
      (node (ref "JP11") (pin "2") (pinfunction "2_2") (pintype "passive"))
      (node (ref "JP11") (pin "9") (pinfunction "9_9") (pintype "passive"))
      (node (ref "JP12") (pin "1") (pinfunction "1_1") (pintype "passive"))
      (node (ref "JP14") (pin "1") (pinfunction "1_1") (pintype "passive"))
      (node (ref "JP16") (pin "7") (pinfunction "7_7") (pintype "passive"))
      (node (ref "JP16") (pin "8") (pinfunction "8_8") (pintype "passive"))
      (node (ref "JP19") (pin "19") (pinfunction "19_19") (pintype "passive"))
      (node (ref "JP2") (pin "2") (pinfunction "2_2") (pintype "passive"))
      (node (ref "JP2") (pin "9") (pinfunction "9_9") (pintype "passive"))
      (node (ref "JP20") (pin "19") (pinfunction "19_19") (pintype "passive"))
      (node (ref "JP3") (pin "6") (pinfunction "6_6") (pintype "passive"))
      (node (ref "JP4") (pin "1") (pinfunction "1_1") (pintype "passive"))
      (node (ref "JP5") (pin "1") (pinfunction "1_1") (pintype "passive"))
      (node (ref "JP6") (pin "6") (pinfunction "6_6") (pintype "passive"))
      (node (ref "JP9") (pin "6") (pinfunction "6_6") (pintype "passive"))
      (node (ref "Q1") (pin "S") (pinfunction "S_S") (pintype "bidirectional"))
      (node (ref "Q2") (pin "S") (pinfunction "S_S") (pintype "bidirectional"))
      (node (ref "Q3") (pin "S") (pinfunction "S_S") (pintype "bidirectional"))
      (node (ref "Q4") (pin "S") (pinfunction "S_S") (pintype "bidirectional"))
      (node (ref "Q5") (pin "S") (pinfunction "S_S") (pintype "bidirectional"))
      (node (ref "Q6") (pin "S") (pinfunction "S_S") (pintype "bidirectional"))
      (node (ref "Q7") (pin "S") (pinfunction "S_S") (pintype "bidirectional"))
      (node (ref "R11") (pin "2") (pinfunction "2_2") (pintype "passive"))
      (node (ref "R12") (pin "2") (pinfunction "2_2") (pintype "passive"))
      (node (ref "R13") (pin "2") (pinfunction "2_2") (pintype "passive"))
      (node (ref "R14") (pin "2") (pinfunction "2_2") (pintype "passive"))
      (node (ref "R18") (pin "C1") (pinfunction "1_C1") (pintype "passive"))
      (node (ref "R18") (pin "D1") (pinfunction "1_D1") (pintype "passive"))
      (node (ref "R19") (pin "C1") (pinfunction "1_C1") (pintype "passive"))
      (node (ref "R19") (pin "D1") (pinfunction "1_D1") (pintype "passive"))
      (node (ref "R20") (pin "C1") (pinfunction "1_C1") (pintype "passive"))
      (node (ref "R20") (pin "D1") (pinfunction "1_D1") (pintype "passive"))
      (node (ref "R21") (pin "C1") (pinfunction "1_C1") (pintype "passive"))
      (node (ref "R21") (pin "D1") (pinfunction "1_D1") (pintype "passive"))
      (node (ref "R22") (pin "C1") (pinfunction "1_C1") (pintype "passive"))
      (node (ref "R22") (pin "D1") (pinfunction "1_D1") (pintype "passive"))
      (node (ref "R23") (pin "A1") (pinfunction "1_A1") (pintype "passive"))
      (node (ref "R23") (pin "B1") (pinfunction "1_B1") (pintype "passive"))
      (node (ref "R23") (pin "C1") (pinfunction "1_C1") (pintype "passive"))
      (node (ref "R24") (pin "A1") (pinfunction "1_A1") (pintype "passive"))
      (node (ref "R24") (pin "B1") (pinfunction "1_B1") (pintype "passive"))
      (node (ref "R24") (pin "C1") (pinfunction "1_C1") (pintype "passive"))
      (node (ref "R25") (pin "A2") (pinfunction "2_A2") (pintype "passive"))
      (node (ref "R25") (pin "B2") (pinfunction "2_B2") (pintype "passive"))
      (node (ref "R25") (pin "C2") (pinfunction "2_C2") (pintype "passive"))
      (node (ref "R25") (pin "D2") (pinfunction "2_D2") (pintype "passive"))
      (node (ref "R26") (pin "A2") (pinfunction "2_A2") (pintype "passive"))
      (node (ref "R26") (pin "B2") (pinfunction "2_B2") (pintype "passive"))
      (node (ref "R26") (pin "C2") (pinfunction "2_C2") (pintype "passive"))
      (node (ref "R26") (pin "D2") (pinfunction "2_D2") (pintype "passive"))
      (node (ref "R49") (pin "1") (pinfunction "1_1") (pintype "passive"))
      (node (ref "R54") (pin "1") (pinfunction "1_1") (pintype "passive"))
      (node (ref "R55") (pin "1") (pinfunction "1_1") (pintype "passive"))
      (node (ref "R56") (pin "1") (pinfunction "1_1") (pintype "passive"))
      (node (ref "R57") (pin "1") (pinfunction "1_1") (pintype "passive"))
      (node (ref "R58") (pin "1") (pinfunction "1_1") (pintype "passive"))
      (node (ref "R59") (pin "1") (pinfunction "1_1") (pintype "passive"))
      (node (ref "R60") (pin "2") (pinfunction "2_2") (pintype "passive"))
      (node (ref "R61") (pin "2") (pinfunction "2_2") (pintype "passive"))
      (node (ref "R62") (pin "B2") (pinfunction "2_B2") (pintype "passive"))
      (node (ref "R62") (pin "C2") (pinfunction "2_C2") (pintype "passive"))
      (node (ref "R63") (pin "A2") (pinfunction "2_A2") (pintype "passive"))
      (node (ref "R63") (pin "B2") (pinfunction "2_B2") (pintype "passive"))
      (node (ref "R63") (pin "D2") (pinfunction "2_D2") (pintype "passive"))
      (node (ref "R64") (pin "A2") (pinfunction "2_A2") (pintype "passive"))
      (node (ref "R64") (pin "C2") (pinfunction "2_C2") (pintype "passive"))
      (node (ref "R64") (pin "D2") (pinfunction "2_D2") (pintype "passive"))
      (node (ref "R68") (pin "1") (pinfunction "1_1") (pintype "passive"))
      (node (ref "R69") (pin "1") (pinfunction "1_1") (pintype "passive"))
      (node (ref "R70") (pin "1") (pinfunction "1_1") (pintype "passive"))
      (node (ref "R71") (pin "1") (pinfunction "1_1") (pintype "passive"))
      (node (ref "R72") (pin "1") (pinfunction "1_1") (pintype "passive"))
      (node (ref "R73") (pin "1") (pinfunction "1_1") (pintype "passive"))
      (node (ref "R74") (pin "1") (pinfunction "1_1") (pintype "passive"))
      (node (ref "R75") (pin "1") (pinfunction "1_1") (pintype "passive"))
      (node (ref "R76") (pin "1") (pinfunction "1_1") (pintype "passive"))
      (node (ref "R77") (pin "1") (pinfunction "1_1") (pintype "passive"))
      (node (ref "R78") (pin "1") (pinfunction "1_1") (pintype "passive"))
      (node (ref "R79") (pin "1") (pinfunction "1_1") (pintype "passive"))
      (node (ref "R80") (pin "1") (pinfunction "1_1") (pintype "passive"))
      (node (ref "R81") (pin "1") (pinfunction "1_1") (pintype "passive"))
      (node (ref "R82") (pin "1") (pinfunction "1_1") (pintype "passive"))
      (node (ref "R83") (pin "1") (pinfunction "1_1") (pintype "passive"))
      (node (ref "R84") (pin "1") (pinfunction "1_1") (pintype "passive"))
      (node (ref "S1") (pin "1") (pinfunction "GND_1") (pintype "bidirectional"))
      (node (ref "S1") (pin "PAD") (pinfunction "GND_PAD") (pintype "bidirectional"))
      (node (ref "S10") (pin "1") (pinfunction "P$1_1") (pintype "passive"))
      (node (ref "S10") (pin "2") (pinfunction "P$1_2") (pintype "passive"))
      (node (ref "S11") (pin "1") (pinfunction "P$1_1") (pintype "passive"))
      (node (ref "S11") (pin "2") (pinfunction "P$1_2") (pintype "passive"))
      (node (ref "S12") (pin "1") (pinfunction "P$1_1") (pintype "passive"))
      (node (ref "S12") (pin "2") (pinfunction "P$1_2") (pintype "passive"))
      (node (ref "S13") (pin "1") (pinfunction "P$1_1") (pintype "passive"))
      (node (ref "S13") (pin "2") (pinfunction "P$1_2") (pintype "passive"))
      (node (ref "S15") (pin "2") (pinfunction "GND_2") (pintype "bidirectional"))
      (node (ref "S15") (pin "PAD") (pinfunction "GND_PAD") (pintype "bidirectional"))
      (node (ref "S16") (pin "2") (pinfunction "GND_2") (pintype "bidirectional"))
      (node (ref "S16") (pin "PAD") (pinfunction "GND_PAD") (pintype "bidirectional"))
      (node (ref "S17") (pin "2") (pinfunction "GND_2") (pintype "bidirectional"))
      (node (ref "S17") (pin "PAD") (pinfunction "GND_PAD") (pintype "bidirectional"))
      (node (ref "S18") (pin "2") (pinfunction "GND_2") (pintype "bidirectional"))
      (node (ref "S18") (pin "PAD") (pinfunction "GND_PAD") (pintype "bidirectional"))
      (node (ref "S19") (pin "7") (pinfunction "GND_7") (pintype "bidirectional"))
      (node (ref "S2") (pin "1") (pinfunction "GND_1") (pintype "bidirectional"))
      (node (ref "S2") (pin "PAD") (pinfunction "GND_PAD") (pintype "bidirectional"))
      (node (ref "S20") (pin "7") (pinfunction "GND_7") (pintype "bidirectional"))
      (node (ref "S21") (pin "7") (pinfunction "GND_7") (pintype "bidirectional"))
      (node (ref "S22") (pin "7") (pinfunction "GND_7") (pintype "bidirectional"))
      (node (ref "S23") (pin "7") (pinfunction "GND_7") (pintype "bidirectional"))
      (node (ref "S25") (pin "1") (pinfunction "A_1") (pintype "bidirectional"))
      (node (ref "S5") (pin "2") (pinfunction "GND_2") (pintype "bidirectional"))
      (node (ref "S6") (pin "2") (pinfunction "GND_2") (pintype "bidirectional"))
      (node (ref "S7") (pin "3") (pinfunction "P$2_3") (pintype "passive"))
      (node (ref "S7") (pin "4") (pinfunction "P$2_4") (pintype "passive"))
      (node (ref "S8") (pin "1") (pinfunction "P$1_1") (pintype "passive"))
      (node (ref "S8") (pin "2") (pinfunction "P$1_2") (pintype "passive"))
      (node (ref "S9") (pin "1") (pinfunction "P$1_1") (pintype "passive"))
      (node (ref "S9") (pin "2") (pinfunction "P$1_2") (pintype "passive"))
      (node (ref "U1") (pin "17") (pinfunction "GND_17") (pintype "power_in"))
      (node (ref "U1") (pin "20") (pinfunction "GND_20") (pintype "power_in"))
      (node (ref "U1") (pin "24") (pinfunction "GND_24") (pintype "power_in"))
      (node (ref "U1") (pin "26") (pinfunction "TEST_26") (pintype "input"))
      (node (ref "U1") (pin "4") (pinfunction "GND_4") (pintype "power_in"))
      (node (ref "U10") (pin "P$1") (pinfunction "GND_P$1") (pintype "open_collector"))
      (node (ref "U10") (pin "P2") (pinfunction "GND_P2") (pintype "open_collector"))
      (node (ref "U10") (pin "P3") (pinfunction "GND_P3") (pintype "open_collector"))
      (node (ref "U10") (pin "P7") (pinfunction "GND_P7") (pintype "open_collector"))
      (node (ref "U11") (pin "P$1") (pinfunction "GND_P$1") (pintype "open_collector"))
      (node (ref "U11") (pin "P2") (pinfunction "GND_P2") (pintype "open_collector"))
      (node (ref "U11") (pin "P3") (pinfunction "GND_P3") (pintype "open_collector"))
      (node (ref "U11") (pin "P7") (pinfunction "GND_P7") (pintype "open_collector"))
      (node (ref "U12") (pin "P$1") (pinfunction "GND_P$1") (pintype "open_collector"))
      (node (ref "U12") (pin "P2") (pinfunction "GND_P2") (pintype "open_collector"))
      (node (ref "U12") (pin "P3") (pinfunction "GND_P3") (pintype "open_collector"))
      (node (ref "U12") (pin "P7") (pinfunction "GND_P7") (pintype "open_collector"))
      (node (ref "U13") (pin "2") (pinfunction "GND_2") (pintype "bidirectional"))
      (node (ref "U13") (pin "3") (pinfunction "GND_3") (pintype "bidirectional"))
      (node (ref "U13") (pin "4") (pinfunction "GND_4") (pintype "bidirectional"))
      (node (ref "U13") (pin "6") (pinfunction "~{ON}_6") (pintype "bidirectional"))
      (node (ref "U14") (pin "2") (pinfunction "E1_2") (pintype "bidirectional"))
      (node (ref "U14") (pin "3") (pinfunction "E2_3") (pintype "bidirectional"))
      (node (ref "U14") (pin "4") (pinfunction "GND_4") (pintype "bidirectional"))
      (node (ref "U15") (pin "4") (pinfunction "GND_4") (pintype "bidirectional"))
      (node (ref "U16") (pin "2") (pinfunction "GND_2") (pintype "bidirectional"))
      (node (ref "U17") (pin "1") (pinfunction "A2_1") (pintype "bidirectional"))
      (node (ref "U17") (pin "17") (pinfunction "GND_17") (pintype "bidirectional"))
      (node (ref "U17") (pin "2") (pinfunction "A1_2") (pintype "bidirectional"))
      (node (ref "U17") (pin "3") (pinfunction "A0_3") (pintype "bidirectional"))
      (node (ref "U17") (pin "GND") (pinfunction "GND_GND") (pintype "bidirectional"))
      (node (ref "U18") (pin "1") (pinfunction "A2_1") (pintype "bidirectional"))
      (node (ref "U18") (pin "17") (pinfunction "GND_17") (pintype "bidirectional"))
      (node (ref "U18") (pin "2") (pinfunction "A1_2") (pintype "bidirectional"))
      (node (ref "U18") (pin "GND") (pinfunction "GND_GND") (pintype "bidirectional"))
      (node (ref "U19") (pin "1") (pinfunction "A2_1") (pintype "bidirectional"))
      (node (ref "U19") (pin "17") (pinfunction "GND_17") (pintype "bidirectional"))
      (node (ref "U19") (pin "GND") (pinfunction "GND_GND") (pintype "bidirectional"))
      (node (ref "U2") (pin "17") (pinfunction "GND_17") (pintype "power_in"))
      (node (ref "U2") (pin "20") (pinfunction "GND_20") (pintype "power_in"))
      (node (ref "U2") (pin "24") (pinfunction "GND_24") (pintype "power_in"))
      (node (ref "U2") (pin "26") (pinfunction "TEST_26") (pintype "input"))
      (node (ref "U2") (pin "4") (pinfunction "GND_4") (pintype "power_in"))
      (node (ref "U20") (pin "3") (pinfunction "GND_3") (pintype "bidirectional"))
      (node (ref "U21") (pin "3") (pinfunction "GND_3") (pintype "bidirectional"))
      (node (ref "U22") (pin "1") (pinfunction "A0_1") (pintype "bidirectional"))
      (node (ref "U22") (pin "10") (pinfunction "GND_10") (pintype "bidirectional"))
      (node (ref "U22") (pin "2") (pinfunction "A1_2") (pintype "bidirectional"))
      (node (ref "U22") (pin "3") (pinfunction "A2_3") (pintype "bidirectional"))
      (node (ref "U23") (pin "17") (pinfunction "GNDANA_17") (pintype "power_in"))
      (node (ref "U23") (pin "30") (pinfunction "GND_30") (pintype "power_in"))
      (node (ref "U23") (pin "48") (pinfunction "GND_48") (pintype "power_in"))
      (node (ref "U23") (pin "6") (pinfunction "GND_6") (pintype "power_in"))
      (node (ref "U23") (pin "THERMAL") (pinfunction "GND_THERMAL") (pintype "power_in"))
      (node (ref "U24") (pin "4") (pinfunction "GND_4") (pintype "bidirectional"))
      (node (ref "U25") (pin "4") (pinfunction "GND_4") (pintype "bidirectional"))
      (node (ref "U26") (pin "4") (pinfunction "GND_4") (pintype "bidirectional"))
      (node (ref "U26") (pin "5") (pinfunction "DIR_5") (pintype "bidirectional"))
      (node (ref "U27") (pin "4") (pinfunction "GND_4") (pintype "bidirectional"))
      (node (ref "U27") (pin "5") (pinfunction "DIR_5") (pintype "bidirectional"))
      (node (ref "U28") (pin "10") (pinfunction "S_10") (pintype "bidirectional"))
      (node (ref "U28") (pin "4") (pinfunction "GND_4") (pintype "bidirectional"))
      (node (ref "U29") (pin "10") (pinfunction "S_10") (pintype "bidirectional"))
      (node (ref "U29") (pin "4") (pinfunction "GND_4") (pintype "bidirectional"))
      (node (ref "U3") (pin "17") (pinfunction "GND_17") (pintype "power_in"))
      (node (ref "U3") (pin "20") (pinfunction "GND_20") (pintype "power_in"))
      (node (ref "U3") (pin "24") (pinfunction "GND_24") (pintype "power_in"))
      (node (ref "U3") (pin "26") (pinfunction "TEST_26") (pintype "input"))
      (node (ref "U3") (pin "4") (pinfunction "GND_4") (pintype "power_in"))
      (node (ref "U30") (pin "4") (pinfunction "GND_4") (pintype "bidirectional"))
      (node (ref "U30") (pin "8") (pinfunction "~{OE}_8") (pintype "bidirectional"))
      (node (ref "U31") (pin "24") (pinfunction "GND_24") (pintype "bidirectional"))
      (node (ref "U31") (pin "43") (pinfunction "GND_43") (pintype "bidirectional"))
      (node (ref "U31") (pin "48") (pinfunction "MODE_48") (pintype "bidirectional"))
      (node (ref "U31") (pin "5") (pinfunction "GND_5") (pintype "bidirectional"))
      (node (ref "U32") (pin "24") (pinfunction "GND_24") (pintype "bidirectional"))
      (node (ref "U32") (pin "43") (pinfunction "GND_43") (pintype "bidirectional"))
      (node (ref "U32") (pin "48") (pinfunction "MODE_48") (pintype "bidirectional"))
      (node (ref "U32") (pin "5") (pinfunction "GND_5") (pintype "bidirectional"))
      (node (ref "U32") (pin "8") (pinfunction "EEDATA/~{GANGED}_8") (pintype "bidirectional"))
      (node (ref "U4") (pin "17") (pinfunction "GND_17") (pintype "power_in"))
      (node (ref "U4") (pin "20") (pinfunction "GND_20") (pintype "power_in"))
      (node (ref "U4") (pin "24") (pinfunction "GND_24") (pintype "power_in"))
      (node (ref "U4") (pin "26") (pinfunction "TEST_26") (pintype "input"))
      (node (ref "U4") (pin "4") (pinfunction "GND_4") (pintype "power_in"))
      (node (ref "U5") (pin "17") (pinfunction "GND_17") (pintype "power_in"))
      (node (ref "U5") (pin "20") (pinfunction "GND_20") (pintype "power_in"))
      (node (ref "U5") (pin "24") (pinfunction "GND_24") (pintype "power_in"))
      (node (ref "U5") (pin "26") (pinfunction "TEST_26") (pintype "input"))
      (node (ref "U5") (pin "4") (pinfunction "GND_4") (pintype "power_in"))
      (node (ref "U6") (pin "17") (pinfunction "GND_17") (pintype "power_in"))
      (node (ref "U6") (pin "20") (pinfunction "GND_20") (pintype "power_in"))
      (node (ref "U6") (pin "24") (pinfunction "GND_24") (pintype "power_in"))
      (node (ref "U6") (pin "26") (pinfunction "TEST_26") (pintype "input"))
      (node (ref "U6") (pin "4") (pinfunction "GND_4") (pintype "power_in"))
      (node (ref "U7") (pin "4") (pinfunction "GND_4") (pintype "bidirectional"))
      (node (ref "U8") (pin "4") (pinfunction "GND_4") (pintype "bidirectional"))
      (node (ref "U9") (pin "2") (pinfunction "GND_2") (pintype "open_collector"))
      (node (ref "Y3") (pin "2") (pinfunction "GND_2") (pintype "bidirectional"))
      (node (ref "Y3") (pin "4") (pinfunction "GND_4") (pintype "bidirectional"))
    )
    (net (code "60") (name "HUB_CFG") (class "Default")
      (node (ref "JP7") (pin "1") (pinfunction "1_1") (pintype "passive"))
      (node (ref "U31") (pin "40") (pinfunction "HUBCFG_40") (pintype "bidirectional"))
    )
    (net (code "61") (name "HUB_DM1") (class "Default")
      (node (ref "C6") (pin "1") (pinfunction "1_1") (pintype "bidirectional"))
      (node (ref "R9") (pin "2") (pinfunction "P$2_2") (pintype "passive"))
      (node (ref "U31") (pin "13") (pinfunction "DM1_13") (pintype "bidirectional"))
    )
    (net (code "62") (name "HUB_DM2") (class "Default")
      (node (ref "C4") (pin "1") (pinfunction "1_1") (pintype "bidirectional"))
      (node (ref "R7") (pin "2") (pinfunction "P$2_2") (pintype "passive"))
      (node (ref "U31") (pin "17") (pinfunction "DM2_17") (pintype "bidirectional"))
    )
    (net (code "63") (name "HUB_DM3") (class "Default")
      (node (ref "C8") (pin "1") (pinfunction "1_1") (pintype "bidirectional"))
      (node (ref "R5") (pin "2") (pinfunction "P$2_2") (pintype "passive"))
      (node (ref "U31") (pin "21") (pinfunction "DM3_21") (pintype "bidirectional"))
    )
    (net (code "64") (name "HUB_DM4") (class "Default")
      (node (ref "R62") (pin "B1") (pinfunction "1_B1") (pintype "passive"))
      (node (ref "U31") (pin "26") (pinfunction "DM4_26") (pintype "bidirectional"))
    )
    (net (code "65") (name "HUB_DM5") (class "Default")
      (node (ref "R63") (pin "A1") (pinfunction "1_A1") (pintype "passive"))
      (node (ref "U31") (pin "30") (pinfunction "DM5_30") (pintype "bidirectional"))
    )
    (net (code "66") (name "HUB_DM6") (class "Default")
      (node (ref "R63") (pin "D1") (pinfunction "1_D1") (pintype "passive"))
      (node (ref "U31") (pin "34") (pinfunction "DM6_34") (pintype "bidirectional"))
    )
    (net (code "67") (name "HUB_DM7") (class "Default")
      (node (ref "R64") (pin "C1") (pinfunction "1_C1") (pintype "passive"))
      (node (ref "U31") (pin "38") (pinfunction "DM7_38") (pintype "bidirectional"))
    )
    (net (code "68") (name "HUB_DP1") (class "Default")
      (node (ref "C5") (pin "1") (pinfunction "1_1") (pintype "bidirectional"))
      (node (ref "R8") (pin "2") (pinfunction "P$2_2") (pintype "passive"))
      (node (ref "U31") (pin "14") (pinfunction "DP1_14") (pintype "bidirectional"))
    )
    (net (code "69") (name "HUB_DP2") (class "Default")
      (node (ref "C3") (pin "1") (pinfunction "1_1") (pintype "bidirectional"))
      (node (ref "R6") (pin "2") (pinfunction "P$2_2") (pintype "passive"))
      (node (ref "U31") (pin "18") (pinfunction "DP2_18") (pintype "bidirectional"))
    )
    (net (code "70") (name "HUB_DP3") (class "Default")
      (node (ref "C7") (pin "1") (pinfunction "1_1") (pintype "bidirectional"))
      (node (ref "R10") (pin "2") (pinfunction "P$2_2") (pintype "passive"))
      (node (ref "U31") (pin "22") (pinfunction "DP3_22") (pintype "bidirectional"))
    )
    (net (code "71") (name "HUB_DP4") (class "Default")
      (node (ref "R62") (pin "C1") (pinfunction "1_C1") (pintype "passive"))
      (node (ref "U31") (pin "27") (pinfunction "DP4_27") (pintype "bidirectional"))
    )
    (net (code "72") (name "HUB_DP5") (class "Default")
      (node (ref "R63") (pin "B1") (pinfunction "1_B1") (pintype "passive"))
      (node (ref "U31") (pin "31") (pinfunction "DP5_31") (pintype "bidirectional"))
    )
    (net (code "73") (name "HUB_DP6") (class "Default")
      (node (ref "R64") (pin "A1") (pinfunction "1_A1") (pintype "passive"))
      (node (ref "U31") (pin "35") (pinfunction "DP6_35") (pintype "bidirectional"))
    )
    (net (code "74") (name "HUB_DP7") (class "Default")
      (node (ref "R64") (pin "D1") (pinfunction "1_D1") (pintype "passive"))
      (node (ref "U31") (pin "39") (pinfunction "DP7_39") (pintype "bidirectional"))
    )
    (net (code "75") (name "HUB_PORTDIS") (class "Default")
      (node (ref "JP7") (pin "4") (pinfunction "4_4") (pintype "passive"))
      (node (ref "U31") (pin "42") (pinfunction "PORTDIS_42") (pintype "bidirectional"))
    )
    (net (code "76") (name "HUB_PORTPWR") (class "Default")
      (node (ref "JP7") (pin "2") (pinfunction "2_2") (pintype "passive"))
      (node (ref "U31") (pin "41") (pinfunction "PORTPWR_41") (pintype "bidirectional"))
    )
    (net (code "77") (name "HUB_~{OVRCUR1}") (class "Default")
      (node (ref "JP8") (pin "2") (pinfunction "2_2") (pintype "passive"))
      (node (ref "R37") (pin "1") (pinfunction "1_1") (pintype "passive"))
      (node (ref "S2") (pin "5") (pinfunction "~{FLG}_5") (pintype "bidirectional"))
      (node (ref "U31") (pin "12") (pinfunction "~{OVRCUR1}_12") (pintype "bidirectional"))
    )
    (net (code "78") (name "HUB_~{OVRCUR2}") (class "Default")
      (node (ref "JP8") (pin "4") (pinfunction "4_4") (pintype "passive"))
      (node (ref "R36") (pin "1") (pinfunction "1_1") (pintype "passive"))
      (node (ref "S1") (pin "5") (pinfunction "~{FLG}_5") (pintype "bidirectional"))
      (node (ref "U31") (pin "16") (pinfunction "~{OVRCUR2}_16") (pintype "bidirectional"))
    )
    (net (code "79") (name "HUB_~{OVRCUR3}") (class "Default")
      (node (ref "JP8") (pin "6") (pinfunction "6_6") (pintype "passive"))
      (node (ref "R50") (pin "1") (pinfunction "1_1") (pintype "passive"))
      (node (ref "U31") (pin "20") (pinfunction "~{OVRCUR3}_20") (pintype "bidirectional"))
    )
    (net (code "80") (name "HUB_~{OVRCUR4}") (class "Default")
      (node (ref "R62") (pin "A1") (pinfunction "1_A1") (pintype "passive"))
      (node (ref "U31") (pin "25") (pinfunction "~{OVRCUR4}_25") (pintype "bidirectional"))
    )
    (net (code "81") (name "HUB_~{OVRCUR5}") (class "Default")
      (node (ref "R62") (pin "D1") (pinfunction "1_D1") (pintype "passive"))
      (node (ref "U31") (pin "29") (pinfunction "~{OVRCUR5}_29") (pintype "bidirectional"))
    )
    (net (code "82") (name "HUB_~{OVRCUR6}") (class "Default")
      (node (ref "R63") (pin "C1") (pinfunction "1_C1") (pintype "passive"))
      (node (ref "U31") (pin "33") (pinfunction "~{OVRCUR6}_33") (pintype "bidirectional"))
    )
    (net (code "83") (name "HUB_~{OVRCUR7}") (class "Default")
      (node (ref "R64") (pin "B1") (pinfunction "1_B1") (pintype "passive"))
      (node (ref "U31") (pin "37") (pinfunction "~{OVRCUR7}_37") (pintype "bidirectional"))
    )
    (net (code "84") (name "HUB_~{PWRON1}") (class "Default")
      (node (ref "JP8") (pin "1") (pinfunction "1_1") (pintype "passive"))
      (node (ref "S5") (pin "1") (pinfunction "I1_1") (pintype "bidirectional"))
      (node (ref "U19") (pin "10") (pinfunction "P1_10") (pintype "bidirectional"))
      (node (ref "U31") (pin "11") (pinfunction "~{PWRON1}_11") (pintype "bidirectional"))
    )
    (net (code "85") (name "HUB_~{PWRON2}") (class "Default")
      (node (ref "JP8") (pin "3") (pinfunction "3_3") (pintype "passive"))
      (node (ref "S6") (pin "1") (pinfunction "I1_1") (pintype "bidirectional"))
      (node (ref "U19") (pin "11") (pinfunction "P2_11") (pintype "bidirectional"))
      (node (ref "U31") (pin "15") (pinfunction "~{PWRON2}_15") (pintype "bidirectional"))
    )
    (net (code "86") (name "HUB_~{PWRON3}") (class "Default")
      (node (ref "JP8") (pin "5") (pinfunction "5_5") (pintype "passive"))
      (node (ref "U19") (pin "12") (pinfunction "P3_12") (pintype "bidirectional"))
      (node (ref "U31") (pin "19") (pinfunction "~{PWRON3}_19") (pintype "bidirectional"))
    )
    (net (code "87") (name "HUB_~{PWRON4}") (class "Default")
      (node (ref "U31") (pin "23") (pinfunction "~{PWRON4}_23") (pintype "bidirectional"))
    )
    (net (code "88") (name "HUB_~{PWRON5}") (class "Default")
      (node (ref "U31") (pin "28") (pinfunction "~{PWRON5}_28") (pintype "bidirectional"))
    )
    (net (code "89") (name "HUB_~{PWRON6}") (class "Default")
      (node (ref "U31") (pin "32") (pinfunction "~{PWRON6}_32") (pintype "bidirectional"))
    )
    (net (code "90") (name "HUB_~{PWRON7}") (class "Default")
      (node (ref "U31") (pin "36") (pinfunction "~{PWRON7}_36") (pintype "bidirectional"))
    )
    (net (code "91") (name "JTAG_5V") (class "Default")
      (node (ref "J6") (pin "19") (pinfunction "19_19") (pintype "passive"))
    )
    (net (code "92") (name "JTAG_DBGRQ") (class "Default")
      (node (ref "J6") (pin "17") (pinfunction "17_17") (pintype "passive"))
    )
    (net (code "93") (name "JTAG_NTRST") (class "Default")
      (node (ref "J6") (pin "3") (pinfunction "3_3") (pintype "passive"))
    )
    (net (code "94") (name "JTAG_RTCK") (class "Default")
      (node (ref "J6") (pin "11") (pinfunction "11_11") (pintype "passive"))
    )
    (net (code "95") (name "JTAG_SWDCLK") (class "Default")
      (node (ref "J6") (pin "9") (pinfunction "9_9") (pintype "passive"))
      (node (ref "S19") (pin "4") (pinfunction "IN_4") (pintype "bidirectional"))
      (node (ref "S20") (pin "4") (pinfunction "IN_4") (pintype "bidirectional"))
      (node (ref "S21") (pin "4") (pinfunction "IN_4") (pintype "bidirectional"))
      (node (ref "S22") (pin "4") (pinfunction "IN_4") (pintype "bidirectional"))
      (node (ref "S23") (pin "4") (pinfunction "IN_4") (pintype "bidirectional"))
    )
    (net (code "96") (name "JTAG_SWDIO") (class "Default")
      (node (ref "J6") (pin "7") (pinfunction "7_7") (pintype "passive"))
      (node (ref "S19") (pin "1") (pinfunction "IN_1") (pintype "bidirectional"))
      (node (ref "S20") (pin "1") (pinfunction "IN_1") (pintype "bidirectional"))
      (node (ref "S21") (pin "1") (pinfunction "IN_1") (pintype "bidirectional"))
      (node (ref "S22") (pin "1") (pinfunction "IN_1") (pintype "bidirectional"))
      (node (ref "S23") (pin "1") (pinfunction "IN_1") (pintype "bidirectional"))
      (node (ref "S24") (pin "IN") (pinfunction "IN_IN") (pintype "bidirectional"))
    )
    (net (code "97") (name "JTAG_SWO{slash}TDO") (class "Default")
      (node (ref "J6") (pin "13") (pinfunction "13_13") (pintype "passive"))
    )
    (net (code "98") (name "JTAG_TDI") (class "Default")
      (node (ref "J6") (pin "5") (pinfunction "5_5") (pintype "passive"))
    )
    (net (code "99") (name "JTAG_VTREF") (class "Default")
      (node (ref "J6") (pin "1") (pinfunction "1_1") (pintype "passive"))
      (node (ref "S19") (pin "11") (pinfunction "IN_11") (pintype "bidirectional"))
      (node (ref "S20") (pin "11") (pinfunction "IN_11") (pintype "bidirectional"))
      (node (ref "S21") (pin "11") (pinfunction "IN_11") (pintype "bidirectional"))
      (node (ref "S22") (pin "11") (pinfunction "IN_11") (pintype "bidirectional"))
      (node (ref "S23") (pin "11") (pinfunction "IN_11") (pintype "bidirectional"))
    )
    (net (code "100") (name "JTAG_~{RESET}") (class "Default")
      (node (ref "J6") (pin "15") (pinfunction "15_15") (pintype "passive"))
      (node (ref "S19") (pin "8") (pinfunction "IN_8") (pintype "bidirectional"))
      (node (ref "S20") (pin "8") (pinfunction "IN_8") (pintype "bidirectional"))
      (node (ref "S21") (pin "8") (pinfunction "IN_8") (pintype "bidirectional"))
      (node (ref "S22") (pin "8") (pinfunction "IN_8") (pintype "bidirectional"))
      (node (ref "S23") (pin "8") (pinfunction "IN_8") (pintype "bidirectional"))
      (node (ref "S24") (pin "1") (pinfunction "A_1") (pintype "bidirectional"))
    )
    (net (code "101") (name "MASTER_~{RESET}") (class "Default")
      (node (ref "D1") (pin "1K") (pinfunction "CATHODE_1K") (pintype "bidirectional"))
      (node (ref "D1") (pin "2K") (pinfunction "CATHODE_2K") (pintype "bidirectional"))
      (node (ref "D1") (pin "3K") (pinfunction "CATHODE_3K") (pintype "bidirectional"))
      (node (ref "D1") (pin "4K") (pinfunction "CATHODE_4K") (pintype "bidirectional"))
      (node (ref "D2") (pin "1K") (pinfunction "CATHODE_1K") (pintype "bidirectional"))
      (node (ref "D2") (pin "2K") (pinfunction "CATHODE_2K") (pintype "bidirectional"))
      (node (ref "D2") (pin "3K") (pinfunction "CATHODE_3K") (pintype "bidirectional"))
      (node (ref "D2") (pin "4K") (pinfunction "CATHODE_4K") (pintype "bidirectional"))
      (node (ref "S7") (pin "1") (pinfunction "P$1_1") (pintype "passive"))
      (node (ref "S7") (pin "2") (pinfunction "P$1_2") (pintype "passive"))
    )
    (net (code "102") (name "MOD0_5V") (class "Default")
      (node (ref "C16") (pin "1") (pinfunction "1_1") (pintype "bidirectional"))
      (node (ref "JP1") (pin "1") (pinfunction "1_1") (pintype "passive"))
      (node (ref "JP4") (pin "2") (pinfunction "2_2") (pintype "passive"))
      (node (ref "S15") (pin "1") (pinfunction "VLOAD_1") (pintype "bidirectional"))
      (node (ref "SJ2") (pin "2") (pinfunction "2_2") (pintype "passive"))
      (node (ref "TP5") (pin "TESTPOINT") (pinfunction "TESTPOINT_TESTPOINT") (pintype "bidirectional"))
    )
    (net (code "103") (name "MOD0_5V_METERED") (class "Default")
      (node (ref "C33") (pin "1") (pinfunction "1_1") (pintype "bidirectional"))
      (node (ref "C60") (pin "1") (pinfunction "1_1") (pintype "bidirectional"))
      (node (ref "C68") (pin "1") (pinfunction "1_1") (pintype "bidirectional"))
      (node (ref "JP16") (pin "5") (pinfunction "5_5") (pintype "passive"))
      (node (ref "R3") (pin "1") (pinfunction "1_1") (pintype "passive"))
      (node (ref "S1") (pin "2") (pinfunction "IN_2") (pintype "bidirectional"))
      (node (ref "S1") (pin "3") (pinfunction "IN_3") (pintype "bidirectional"))
      (node (ref "S15") (pin "3") (pinfunction "VSUPP_3") (pintype "bidirectional"))
      (node (ref "U11") (pin "P8") (pinfunction "SENSE-_P8") (pintype "open_collector"))
    )
    (net (code "104") (name "MOD0_D+_HUB-SW") (class "Default")
      (node (ref "D36") (pin "4") (pinfunction "D_4") (pintype "bidirectional"))
      (node (ref "R54") (pin "2") (pinfunction "2_2") (pintype "passive"))
      (node (ref "R6") (pin "1") (pinfunction "P$1_1") (pintype "passive"))
      (node (ref "U28") (pin "3") (pinfunction "D+_3") (pintype "bidirectional"))
    )
    (net (code "105") (name "MOD0_D-_HUB-SW") (class "Default")
      (node (ref "D36") (pin "2") (pinfunction "C_2") (pintype "bidirectional"))
      (node (ref "R55") (pin "2") (pinfunction "2_2") (pintype "passive"))
      (node (ref "R7") (pin "1") (pinfunction "P$1_1") (pintype "passive"))
      (node (ref "U28") (pin "5") (pinfunction "D-_5") (pintype "bidirectional"))
    )
    (net (code "106") (name "MOD0_DBG_GPIO1") (class "Default")
      (node (ref "J2") (pin "16") (pinfunction "DBG_GPIO1_16") (pintype "bidirectional"))
      (node (ref "JP3") (pin "5") (pinfunction "5_5") (pintype "passive"))
      (node (ref "Q2") (pin "G1") (pinfunction "G1_G1") (pintype "input"))
      (node (ref "R69") (pin "2") (pinfunction "2_2") (pintype "passive"))
    )
    (net (code "107") (name "MOD0_DBG_GPIO2") (class "Default")
      (node (ref "J2") (pin "19") (pinfunction "DBG_GPIO2_19") (pintype "bidirectional"))
      (node (ref "JP3") (pin "2") (pinfunction "2_2") (pintype "passive"))
      (node (ref "Q2") (pin "G2") (pinfunction "G2_G2") (pintype "input"))
      (node (ref "R70") (pin "2") (pinfunction "2_2") (pintype "passive"))
    )
    (net (code "108") (name "MOD0_DBG_RX") (class "Default")
      (node (ref "J2") (pin "18") (pinfunction "DBG_RX_18") (pintype "bidirectional"))
      (node (ref "JP3") (pin "3") (pinfunction "3_3") (pintype "passive"))
      (node (ref "U2") (pin "30") (pinfunction "TXD_30") (pintype "output"))
    )
    (net (code "109") (name "MOD0_DBG_SWDCLK") (class "Default")
      (node (ref "J2") (pin "21") (pinfunction "DBG_SWDCLK_21") (pintype "bidirectional"))
      (node (ref "S19") (pin "3") (pinfunction "A_3") (pintype "bidirectional"))
    )
    (net (code "110") (name "MOD0_DBG_SWDIO") (class "Default")
      (node (ref "J2") (pin "22") (pinfunction "DBG_SWDIO_22") (pintype "bidirectional"))
      (node (ref "S19") (pin "2") (pinfunction "A_2") (pintype "bidirectional"))
    )
    (net (code "111") (name "MOD0_DBG_TX") (class "Default")
      (node (ref "J2") (pin "17") (pinfunction "DBG_TX_17") (pintype "bidirectional"))
      (node (ref "JP3") (pin "4") (pinfunction "4_4") (pintype "passive"))
      (node (ref "U2") (pin "2") (pinfunction "RXD_2") (pintype "input"))
    )
    (net (code "112") (name "MOD0_DBG_~{RESET}") (class "Default")
      (node (ref "D1") (pin "1A") (pinfunction "ANODE_1A") (pintype "bidirectional"))
      (node (ref "J2") (pin "20") (pinfunction "DBG_~{RESET}_20") (pintype "bidirectional"))
      (node (ref "JP3") (pin "1") (pinfunction "1_1") (pintype "passive"))
      (node (ref "S19") (pin "9") (pinfunction "A_9") (pintype "bidirectional"))
      (node (ref "S8") (pin "3") (pinfunction "P$2_3") (pintype "passive"))
      (node (ref "S8") (pin "4") (pinfunction "P$2_4") (pintype "passive"))
    )
    (net (code "113") (name "MOD0_HDR_RSV_PIN3") (class "Default")
      (node (ref "JP4") (pin "3") (pinfunction "3_3") (pintype "passive"))
    )
    (net (code "114") (name "MOD0_HDR_RSV_PIN9") (class "Default")
      (node (ref "JP4") (pin "9") (pinfunction "9_9") (pintype "passive"))
    )
    (net (code "115") (name "MOD0_IN") (class "Default")
      (node (ref "J2") (pin "10") (pinfunction "MOD_IN_10") (pintype "bidirectional"))
      (node (ref "JP1") (pin "7") (pinfunction "7_7") (pintype "passive"))
      (node (ref "JP4") (pin "10") (pinfunction "10_10") (pintype "passive"))
      (node (ref "U24") (pin "7") (pinfunction "B1_7") (pintype "bidirectional"))
    )
    (net (code "116") (name "MOD0_ISO_I2C") (class "Default")
      (node (ref "D5") (pin "A") (pinfunction "ANODE_A") (pintype "bidirectional"))
      (node (ref "JP17") (pin "2") (pinfunction "2_2") (pintype "passive"))
      (node (ref "S3") (pin "COM3") (pinfunction "3P_COM3") (pintype "bidirectional"))
      (node (ref "U7") (pin "5") (pinfunction "OE_5") (pintype "bidirectional"))
    )
    (net (code "117") (name "MOD0_ISO_OVERRIDE") (class "Default")
      (node (ref "D26") (pin "A") (pinfunction "ANODE_A") (pintype "bidirectional"))
      (node (ref "D27") (pin "A") (pinfunction "ANODE_A") (pintype "bidirectional"))
      (node (ref "D28") (pin "A") (pinfunction "ANODE_A") (pintype "bidirectional"))
      (node (ref "D29") (pin "A") (pinfunction "ANODE_A") (pintype "bidirectional"))
      (node (ref "S3") (pin "COM1") (pinfunction "1P_COM1") (pintype "bidirectional"))
    )
    (net (code "118") (name "MOD0_ISO_POWER") (class "Default")
      (node (ref "D4") (pin "A") (pinfunction "ANODE_A") (pintype "bidirectional"))
      (node (ref "JP17") (pin "3") (pinfunction "3_3") (pintype "passive"))
      (node (ref "S15") (pin "4") (pinfunction "EN_4") (pintype "bidirectional"))
      (node (ref "S3") (pin "COM4") (pinfunction "4P_COM4") (pintype "bidirectional"))
    )
    (net (code "119") (name "MOD0_ISO_USB") (class "Default")
      (node (ref "D6") (pin "A") (pinfunction "ANODE_A") (pintype "bidirectional"))
      (node (ref "JP17") (pin "1") (pinfunction "1_1") (pintype "passive"))
      (node (ref "S3") (pin "COM2") (pinfunction "2P_COM2") (pintype "bidirectional"))
      (node (ref "S6") (pin "6") (pinfunction "S_6") (pintype "bidirectional"))
    )
    (net (code "120") (name "MOD0_OUT") (class "Default")
      (node (ref "J2") (pin "8") (pinfunction "MOD_OUT_8") (pintype "bidirectional"))
      (node (ref "JP1") (pin "8") (pinfunction "8_8") (pintype "passive"))
      (node (ref "JP4") (pin "8") (pinfunction "8_8") (pintype "passive"))
      (node (ref "U26") (pin "7") (pinfunction "B1_7") (pintype "bidirectional"))
    )
    (net (code "121") (name "MOD0_PPS") (class "Default")
      (node (ref "J2") (pin "7") (pinfunction "PPS_7") (pintype "bidirectional"))
      (node (ref "JP1") (pin "10") (pinfunction "10_10") (pintype "passive"))
      (node (ref "JP4") (pin "7") (pinfunction "7_7") (pintype "passive"))
      (node (ref "U24") (pin "6") (pinfunction "B2_6") (pintype "bidirectional"))
    )
    (net (code "122") (name "MOD0_SCL") (class "Default")
      (node (ref "J2") (pin "5") (pinfunction "SCL_5") (pintype "bidirectional"))
      (node (ref "JP1") (pin "5") (pinfunction "5_5") (pintype "passive"))
      (node (ref "JP4") (pin "5") (pinfunction "5_5") (pintype "passive"))
      (node (ref "R39") (pin "2") (pinfunction "2_2") (pintype "passive"))
      (node (ref "U7") (pin "6") (pinfunction "B1_6") (pintype "bidirectional"))
    )
    (net (code "123") (name "MOD0_SDA") (class "Default")
      (node (ref "J2") (pin "6") (pinfunction "SDA_6") (pintype "bidirectional"))
      (node (ref "JP1") (pin "6") (pinfunction "6_6") (pintype "passive"))
      (node (ref "JP4") (pin "6") (pinfunction "6_6") (pintype "passive"))
      (node (ref "R38") (pin "2") (pinfunction "2_2") (pintype "passive"))
      (node (ref "U7") (pin "7") (pinfunction "B0_7") (pintype "bidirectional"))
    )
    (net (code "124") (name "MOD0_USB+") (class "Default")
      (node (ref "J2") (pin "11") (pinfunction "USB_D+_11") (pintype "bidirectional"))
      (node (ref "U28") (pin "1") (pinfunction "D1+_1") (pintype "bidirectional"))
    )
    (net (code "125") (name "MOD0_USB-") (class "Default")
      (node (ref "J2") (pin "12") (pinfunction "USB_D-_12") (pintype "bidirectional"))
      (node (ref "U28") (pin "7") (pinfunction "D1-_7") (pintype "bidirectional"))
    )
    (net (code "126") (name "MOD0_USB_VBUS") (class "Default")
      (node (ref "C29") (pin "1") (pinfunction "1_1") (pintype "bidirectional"))
      (node (ref "C74") (pin "1") (pinfunction "1_1") (pintype "bidirectional"))
      (node (ref "J2") (pin "13") (pinfunction "USB_VBUS_13") (pintype "bidirectional"))
      (node (ref "JP1") (pin "3") (pinfunction "3_3") (pintype "passive"))
      (node (ref "S1") (pin "6") (pinfunction "OUT_6") (pintype "bidirectional"))
      (node (ref "S1") (pin "7") (pinfunction "OUT_7") (pintype "bidirectional"))
    )
    (net (code "127") (name "MOD0_USB_~{EN}") (class "Default")
      (node (ref "S1") (pin "4") (pinfunction "~{EN}_4") (pintype "bidirectional"))
      (node (ref "S6") (pin "4") (pinfunction "Z_4") (pintype "bidirectional"))
      (node (ref "U28") (pin "8") (pinfunction "~{OE}_8") (pintype "bidirectional"))
    )
    (net (code "128") (name "MOD0_VCCIO") (class "Default")
      (node (ref "C22") (pin "1") (pinfunction "1_1") (pintype "bidirectional"))
      (node (ref "C24") (pin "1") (pinfunction "1_1") (pintype "bidirectional"))
      (node (ref "C37") (pin "1") (pinfunction "1_1") (pintype "bidirectional"))
      (node (ref "J2") (pin "4") (pinfunction "VCCIO_4") (pintype "bidirectional"))
      (node (ref "JP1") (pin "4") (pinfunction "4_4") (pintype "passive"))
      (node (ref "JP4") (pin "4") (pinfunction "4_4") (pintype "passive"))
      (node (ref "R38") (pin "1") (pinfunction "1_1") (pintype "passive"))
      (node (ref "R39") (pin "1") (pinfunction "1_1") (pintype "passive"))
      (node (ref "S19") (pin "10") (pinfunction "A_10") (pintype "bidirectional"))
      (node (ref "U2") (pin "1") (pinfunction "VCCIO_1") (pintype "power_in"))
      (node (ref "U24") (pin "8") (pinfunction "VCC_B_8") (pintype "bidirectional"))
      (node (ref "U26") (pin "8") (pinfunction "VCC_B_8") (pintype "bidirectional"))
      (node (ref "U7") (pin "8") (pinfunction "VCC_B_8") (pintype "bidirectional"))
    )
    (net (code "129") (name "MOD1_5V") (class "Default")
      (node (ref "C17") (pin "1") (pinfunction "1_1") (pintype "bidirectional"))
      (node (ref "JP2") (pin "1") (pinfunction "1_1") (pintype "passive"))
      (node (ref "JP5") (pin "2") (pinfunction "2_2") (pintype "passive"))
      (node (ref "S16") (pin "1") (pinfunction "VLOAD_1") (pintype "bidirectional"))
      (node (ref "SJ3") (pin "2") (pinfunction "2_2") (pintype "passive"))
      (node (ref "TP7") (pin "TESTPOINT") (pinfunction "TESTPOINT_TESTPOINT") (pintype "bidirectional"))
    )
    (net (code "130") (name "MOD1_5V_METERED") (class "Default")
      (node (ref "C34") (pin "1") (pinfunction "1_1") (pintype "bidirectional"))
      (node (ref "C61") (pin "1") (pinfunction "1_1") (pintype "bidirectional"))
      (node (ref "C69") (pin "1") (pinfunction "1_1") (pintype "bidirectional"))
      (node (ref "JP16") (pin "6") (pinfunction "6_6") (pintype "passive"))
      (node (ref "R4") (pin "1") (pinfunction "1_1") (pintype "passive"))
      (node (ref "S16") (pin "3") (pinfunction "VSUPP_3") (pintype "bidirectional"))
      (node (ref "S2") (pin "2") (pinfunction "IN_2") (pintype "bidirectional"))
      (node (ref "S2") (pin "3") (pinfunction "IN_3") (pintype "bidirectional"))
      (node (ref "U12") (pin "P8") (pinfunction "SENSE-_P8") (pintype "open_collector"))
    )
    (net (code "131") (name "MOD1_D+_HUB-SW") (class "Default")
      (node (ref "D36") (pin "8") (pinfunction "A_8") (pintype "bidirectional"))
      (node (ref "R56") (pin "2") (pinfunction "2_2") (pintype "passive"))
      (node (ref "R8") (pin "1") (pinfunction "P$1_1") (pintype "passive"))
      (node (ref "U29") (pin "3") (pinfunction "D+_3") (pintype "bidirectional"))
    )
    (net (code "132") (name "MOD1_D-_HUB-SW") (class "Default")
      (node (ref "D36") (pin "6") (pinfunction "B_6") (pintype "bidirectional"))
      (node (ref "R57") (pin "2") (pinfunction "2_2") (pintype "passive"))
      (node (ref "R9") (pin "1") (pinfunction "P$1_1") (pintype "passive"))
      (node (ref "U29") (pin "5") (pinfunction "D-_5") (pintype "bidirectional"))
    )
    (net (code "133") (name "MOD1_DBG_GPIO1") (class "Default")
      (node (ref "J3") (pin "16") (pinfunction "DBG_GPIO1_16") (pintype "bidirectional"))
      (node (ref "JP6") (pin "5") (pinfunction "5_5") (pintype "passive"))
      (node (ref "Q3") (pin "G1") (pinfunction "G1_G1") (pintype "input"))
      (node (ref "R71") (pin "2") (pinfunction "2_2") (pintype "passive"))
    )
    (net (code "134") (name "MOD1_DBG_GPIO2") (class "Default")
      (node (ref "J3") (pin "19") (pinfunction "DBG_GPIO2_19") (pintype "bidirectional"))
      (node (ref "JP6") (pin "2") (pinfunction "2_2") (pintype "passive"))
      (node (ref "Q3") (pin "G2") (pinfunction "G2_G2") (pintype "input"))
      (node (ref "R72") (pin "2") (pinfunction "2_2") (pintype "passive"))
    )
    (net (code "135") (name "MOD1_DBG_RX") (class "Default")
      (node (ref "J3") (pin "18") (pinfunction "DBG_RX_18") (pintype "bidirectional"))
      (node (ref "JP6") (pin "3") (pinfunction "3_3") (pintype "passive"))
      (node (ref "U3") (pin "30") (pinfunction "TXD_30") (pintype "output"))
    )
    (net (code "136") (name "MOD1_DBG_SWDCLK") (class "Default")
      (node (ref "J3") (pin "21") (pinfunction "DBG_SWDCLK_21") (pintype "bidirectional"))
      (node (ref "S20") (pin "3") (pinfunction "A_3") (pintype "bidirectional"))
    )
    (net (code "137") (name "MOD1_DBG_SWDIO") (class "Default")
      (node (ref "J3") (pin "22") (pinfunction "DBG_SWDIO_22") (pintype "bidirectional"))
      (node (ref "S20") (pin "2") (pinfunction "A_2") (pintype "bidirectional"))
    )
    (net (code "138") (name "MOD1_DBG_TX") (class "Default")
      (node (ref "J3") (pin "17") (pinfunction "DBG_TX_17") (pintype "bidirectional"))
      (node (ref "JP6") (pin "4") (pinfunction "4_4") (pintype "passive"))
      (node (ref "U3") (pin "2") (pinfunction "RXD_2") (pintype "input"))
    )
    (net (code "139") (name "MOD1_DBG_~{RESET}") (class "Default")
      (node (ref "D1") (pin "2A") (pinfunction "ANODE_2A") (pintype "bidirectional"))
      (node (ref "J3") (pin "20") (pinfunction "DBG_~{RESET}_20") (pintype "bidirectional"))
      (node (ref "JP6") (pin "1") (pinfunction "1_1") (pintype "passive"))
      (node (ref "S20") (pin "9") (pinfunction "A_9") (pintype "bidirectional"))
      (node (ref "S9") (pin "3") (pinfunction "P$2_3") (pintype "passive"))
      (node (ref "S9") (pin "4") (pinfunction "P$2_4") (pintype "passive"))
    )
    (net (code "140") (name "MOD1_HDR_RSV_PIN3") (class "Default")
      (node (ref "JP5") (pin "3") (pinfunction "3_3") (pintype "passive"))
    )
    (net (code "141") (name "MOD1_HDR_RSV_PIN9") (class "Default")
      (node (ref "JP5") (pin "9") (pinfunction "9_9") (pintype "passive"))
    )
    (net (code "142") (name "MOD1_IN") (class "Default")
      (node (ref "J3") (pin "10") (pinfunction "MOD_IN_10") (pintype "bidirectional"))
      (node (ref "JP2") (pin "7") (pinfunction "7_7") (pintype "passive"))
      (node (ref "JP5") (pin "10") (pinfunction "10_10") (pintype "passive"))
      (node (ref "U25") (pin "7") (pinfunction "B1_7") (pintype "bidirectional"))
    )
    (net (code "143") (name "MOD1_ISO_I2C") (class "Default")
      (node (ref "D8") (pin "A") (pinfunction "ANODE_A") (pintype "bidirectional"))
      (node (ref "JP18") (pin "2") (pinfunction "2_2") (pintype "passive"))
      (node (ref "S4") (pin "COM3") (pinfunction "3P_COM3") (pintype "bidirectional"))
      (node (ref "U8") (pin "5") (pinfunction "OE_5") (pintype "bidirectional"))
    )
    (net (code "144") (name "MOD1_ISO_OVERRIDE") (class "Default")
      (node (ref "D30") (pin "A") (pinfunction "ANODE_A") (pintype "bidirectional"))
      (node (ref "D31") (pin "A") (pinfunction "ANODE_A") (pintype "bidirectional"))
      (node (ref "D32") (pin "A") (pinfunction "ANODE_A") (pintype "bidirectional"))
      (node (ref "D33") (pin "A") (pinfunction "ANODE_A") (pintype "bidirectional"))
      (node (ref "S4") (pin "COM1") (pinfunction "1P_COM1") (pintype "bidirectional"))
    )
    (net (code "145") (name "MOD1_ISO_POWER") (class "Default")
      (node (ref "D7") (pin "A") (pinfunction "ANODE_A") (pintype "bidirectional"))
      (node (ref "JP18") (pin "3") (pinfunction "3_3") (pintype "passive"))
      (node (ref "S16") (pin "4") (pinfunction "EN_4") (pintype "bidirectional"))
      (node (ref "S4") (pin "COM4") (pinfunction "4P_COM4") (pintype "bidirectional"))
    )
    (net (code "146") (name "MOD1_ISO_USB") (class "Default")
      (node (ref "D9") (pin "A") (pinfunction "ANODE_A") (pintype "bidirectional"))
      (node (ref "JP18") (pin "1") (pinfunction "1_1") (pintype "passive"))
      (node (ref "S4") (pin "COM2") (pinfunction "2P_COM2") (pintype "bidirectional"))
      (node (ref "S5") (pin "6") (pinfunction "S_6") (pintype "bidirectional"))
    )
    (net (code "147") (name "MOD1_OUT") (class "Default")
      (node (ref "J3") (pin "8") (pinfunction "MOD_OUT_8") (pintype "bidirectional"))
      (node (ref "JP2") (pin "8") (pinfunction "8_8") (pintype "passive"))
      (node (ref "JP5") (pin "8") (pinfunction "8_8") (pintype "passive"))
      (node (ref "U27") (pin "7") (pinfunction "B1_7") (pintype "bidirectional"))
    )
    (net (code "148") (name "MOD1_PPS") (class "Default")
      (node (ref "J3") (pin "7") (pinfunction "PPS_7") (pintype "bidirectional"))
      (node (ref "JP2") (pin "10") (pinfunction "10_10") (pintype "passive"))
      (node (ref "JP5") (pin "7") (pinfunction "7_7") (pintype "passive"))
      (node (ref "U25") (pin "6") (pinfunction "B2_6") (pintype "bidirectional"))
    )
    (net (code "149") (name "MOD1_SCL") (class "Default")
      (node (ref "J3") (pin "5") (pinfunction "SCL_5") (pintype "bidirectional"))
      (node (ref "JP2") (pin "5") (pinfunction "5_5") (pintype "passive"))
      (node (ref "JP5") (pin "5") (pinfunction "5_5") (pintype "passive"))
      (node (ref "R41") (pin "2") (pinfunction "2_2") (pintype "passive"))
      (node (ref "U8") (pin "6") (pinfunction "B1_6") (pintype "bidirectional"))
    )
    (net (code "150") (name "MOD1_SDA") (class "Default")
      (node (ref "J3") (pin "6") (pinfunction "SDA_6") (pintype "bidirectional"))
      (node (ref "JP2") (pin "6") (pinfunction "6_6") (pintype "passive"))
      (node (ref "JP5") (pin "6") (pinfunction "6_6") (pintype "passive"))
      (node (ref "R40") (pin "2") (pinfunction "2_2") (pintype "passive"))
      (node (ref "U8") (pin "7") (pinfunction "B0_7") (pintype "bidirectional"))
    )
    (net (code "151") (name "MOD1_USB+") (class "Default")
      (node (ref "J3") (pin "11") (pinfunction "USB_D+_11") (pintype "bidirectional"))
      (node (ref "U29") (pin "1") (pinfunction "D1+_1") (pintype "bidirectional"))
    )
    (net (code "152") (name "MOD1_USB-") (class "Default")
      (node (ref "J3") (pin "12") (pinfunction "USB_D-_12") (pintype "bidirectional"))
      (node (ref "U29") (pin "7") (pinfunction "D1-_7") (pintype "bidirectional"))
    )
    (net (code "153") (name "MOD1_USB_VBUS") (class "Default")
      (node (ref "C30") (pin "1") (pinfunction "1_1") (pintype "bidirectional"))
      (node (ref "C75") (pin "1") (pinfunction "1_1") (pintype "bidirectional"))
      (node (ref "J3") (pin "13") (pinfunction "USB_VBUS_13") (pintype "bidirectional"))
      (node (ref "JP2") (pin "3") (pinfunction "3_3") (pintype "passive"))
      (node (ref "S2") (pin "6") (pinfunction "OUT_6") (pintype "bidirectional"))
      (node (ref "S2") (pin "7") (pinfunction "OUT_7") (pintype "bidirectional"))
    )
    (net (code "154") (name "MOD1_USB_~{EN}") (class "Default")
      (node (ref "S2") (pin "4") (pinfunction "~{EN}_4") (pintype "bidirectional"))
      (node (ref "S5") (pin "4") (pinfunction "Z_4") (pintype "bidirectional"))
      (node (ref "U29") (pin "8") (pinfunction "~{OE}_8") (pintype "bidirectional"))
    )
    (net (code "155") (name "MOD1_VCCIO") (class "Default")
      (node (ref "C23") (pin "1") (pinfunction "1_1") (pintype "bidirectional"))
      (node (ref "C25") (pin "1") (pinfunction "1_1") (pintype "bidirectional"))
      (node (ref "C38") (pin "1") (pinfunction "1_1") (pintype "bidirectional"))
      (node (ref "J3") (pin "4") (pinfunction "VCCIO_4") (pintype "bidirectional"))
      (node (ref "JP2") (pin "4") (pinfunction "4_4") (pintype "passive"))
      (node (ref "JP5") (pin "4") (pinfunction "4_4") (pintype "passive"))
      (node (ref "R40") (pin "1") (pinfunction "1_1") (pintype "passive"))
      (node (ref "R41") (pin "1") (pinfunction "1_1") (pintype "passive"))
      (node (ref "S20") (pin "10") (pinfunction "A_10") (pintype "bidirectional"))
      (node (ref "U25") (pin "8") (pinfunction "VCC_B_8") (pintype "bidirectional"))
      (node (ref "U27") (pin "8") (pinfunction "VCC_B_8") (pintype "bidirectional"))
      (node (ref "U3") (pin "1") (pinfunction "VCCIO_1") (pintype "power_in"))
      (node (ref "U8") (pin "8") (pinfunction "VCC_B_8") (pintype "bidirectional"))
    )
    (net (code "156") (name "MOD2_DBG_GPIO1") (class "Default")
      (node (ref "Q6") (pin "G1") (pinfunction "G1_G1") (pintype "input"))
      (node (ref "R77") (pin "2") (pinfunction "2_2") (pintype "passive"))
      (node (ref "U23") (pin "41") (pinfunction "PA21_41") (pintype "bidirectional"))
    )
    (net (code "157") (name "MOD2_DBG_GPIO2") (class "Default")
      (node (ref "Q6") (pin "G2") (pinfunction "G2_G2") (pintype "input"))
      (node (ref "R78") (pin "2") (pinfunction "2_2") (pintype "passive"))
      (node (ref "U23") (pin "42") (pinfunction "PA22_42") (pintype "bidirectional"))
    )
    (net (code "158") (name "MOD2_USB+") (class "Default")
      (node (ref "D35") (pin "6") (pinfunction "B_6") (pintype "bidirectional"))
      (node (ref "R10") (pin "1") (pinfunction "P$1_1") (pintype "passive"))
      (node (ref "R58") (pin "2") (pinfunction "2_2") (pintype "passive"))
      (node (ref "U23") (pin "47") (pinfunction "PA26_47") (pintype "bidirectional"))
    )
    (net (code "159") (name "MOD2_USB-") (class "Default")
      (node (ref "D35") (pin "8") (pinfunction "A_8") (pintype "bidirectional"))
      (node (ref "R5") (pin "1") (pinfunction "P$1_1") (pintype "passive"))
      (node (ref "R59") (pin "2") (pinfunction "2_2") (pintype "passive"))
      (node (ref "U23") (pin "46") (pinfunction "PA25_46") (pintype "bidirectional"))
    )
    (net (code "160") (name "MOD_SCL") (class "Default")
      (node (ref "J1") (pin "24") (pinfunction "MODULES_SCL_24") (pintype "bidirectional"))
      (node (ref "JP11") (pin "5") (pinfunction "5_5") (pintype "passive"))
      (node (ref "JP14") (pin "4") (pinfunction "4_4") (pintype "passive"))
      (node (ref "R47") (pin "1") (pinfunction "1_1") (pintype "passive"))
      (node (ref "U23") (pin "44") (pinfunction "PA24_44") (pintype "bidirectional"))
      (node (ref "U7") (pin "3") (pinfunction "A1_3") (pintype "bidirectional"))
      (node (ref "U8") (pin "3") (pinfunction "A1_3") (pintype "bidirectional"))
    )
    (net (code "161") (name "MOD_SDA") (class "Default")
      (node (ref "J1") (pin "23") (pinfunction "MODULES_SDA_23") (pintype "bidirectional"))
      (node (ref "JP11") (pin "6") (pinfunction "6_6") (pintype "passive"))
      (node (ref "JP14") (pin "3") (pinfunction "3_3") (pintype "passive"))
      (node (ref "R46") (pin "1") (pinfunction "1_1") (pintype "passive"))
      (node (ref "U23") (pin "43") (pinfunction "PA23_43") (pintype "bidirectional"))
      (node (ref "U7") (pin "2") (pinfunction "A0_2") (pintype "bidirectional"))
      (node (ref "U8") (pin "2") (pinfunction "A0_2") (pintype "bidirectional"))
    )
    (net (code "162") (name "MOD_USB_OVERRIDE_5V") (class "Default")
      (node (ref "J4") (pin "1") (pinfunction "+5V_1") (pintype "bidirectional"))
      (node (ref "Q1") (pin "G2") (pinfunction "G2_G2") (pintype "input"))
      (node (ref "R68") (pin "2") (pinfunction "2_2") (pintype "passive"))
    )
    (net (code "163") (name "MOD_USB_OVERRIDE_DM") (class "Default")
      (node (ref "J4") (pin "2") (pinfunction "D-_2") (pintype "bidirectional"))
      (node (ref "U30") (pin "1") (pinfunction "D1+_1") (pintype "bidirectional"))
    )
    (net (code "164") (name "MOD_USB_OVERRIDE_DP") (class "Default")
      (node (ref "J4") (pin "3") (pinfunction "D+_3") (pintype "bidirectional"))
      (node (ref "U30") (pin "7") (pinfunction "D1-_7") (pintype "bidirectional"))
    )
    (net (code "165") (name "Net-(C10-Pad2)") (class "Default")
      (node (ref "C10") (pin "2") (pinfunction "2_2") (pintype "bidirectional"))
      (node (ref "R28") (pin "1") (pinfunction "1_1") (pintype "passive"))
      (node (ref "Y1") (pin "1") (pinfunction "1_1") (pintype "bidirectional"))
    )
    (net (code "166") (name "Net-(C12-Pad2)") (class "Default")
      (node (ref "C12") (pin "2") (pinfunction "2_2") (pintype "bidirectional"))
      (node (ref "R30") (pin "1") (pinfunction "1_1") (pintype "passive"))
      (node (ref "Y2") (pin "1") (pinfunction "1_1") (pintype "bidirectional"))
    )
    (net (code "167") (name "Net-(D4-CATHODE)") (class "Default")
      (node (ref "D4") (pin "C") (pinfunction "CATHODE_C") (pintype "bidirectional"))
      (node (ref "R23") (pin "A2") (pinfunction "2_A2") (pintype "passive"))
    )
    (net (code "168") (name "Net-(D5-CATHODE)") (class "Default")
      (node (ref "D5") (pin "C") (pinfunction "CATHODE_C") (pintype "bidirectional"))
      (node (ref "R23") (pin "B2") (pinfunction "2_B2") (pintype "passive"))
    )
    (net (code "169") (name "Net-(D6-CATHODE)") (class "Default")
      (node (ref "D6") (pin "C") (pinfunction "CATHODE_C") (pintype "bidirectional"))
      (node (ref "R23") (pin "C2") (pinfunction "2_C2") (pintype "passive"))
    )
    (net (code "170") (name "Net-(D7-CATHODE)") (class "Default")
      (node (ref "D7") (pin "C") (pinfunction "CATHODE_C") (pintype "bidirectional"))
      (node (ref "R24") (pin "C2") (pinfunction "2_C2") (pintype "passive"))
    )
    (net (code "171") (name "Net-(D8-CATHODE)") (class "Default")
      (node (ref "D8") (pin "C") (pinfunction "CATHODE_C") (pintype "bidirectional"))
      (node (ref "R24") (pin "B2") (pinfunction "2_B2") (pintype "passive"))
    )
    (net (code "172") (name "Net-(D9-CATHODE)") (class "Default")
      (node (ref "D9") (pin "C") (pinfunction "CATHODE_C") (pintype "bidirectional"))
      (node (ref "R24") (pin "A2") (pinfunction "2_A2") (pintype "passive"))
    )
    (net (code "173") (name "Net-(D10-CATHODE)") (class "Default")
      (node (ref "D10") (pin "C") (pinfunction "CATHODE_C") (pintype "bidirectional"))
      (node (ref "R18") (pin "A2") (pinfunction "2_A2") (pintype "passive"))
    )
    (net (code "174") (name "Net-(D11-CATHODE)") (class "Default")
      (node (ref "D11") (pin "C") (pinfunction "CATHODE_C") (pintype "bidirectional"))
      (node (ref "R18") (pin "B2") (pinfunction "2_B2") (pintype "passive"))
    )
    (net (code "175") (name "Net-(D12-CATHODE)") (class "Default")
      (node (ref "D12") (pin "C") (pinfunction "CATHODE_C") (pintype "bidirectional"))
      (node (ref "R19") (pin "A2") (pinfunction "2_A2") (pintype "passive"))
    )
    (net (code "176") (name "Net-(D13-CATHODE)") (class "Default")
      (node (ref "D13") (pin "C") (pinfunction "CATHODE_C") (pintype "bidirectional"))
      (node (ref "R19") (pin "B2") (pinfunction "2_B2") (pintype "passive"))
    )
    (net (code "177") (name "Net-(D14-CATHODE)") (class "Default")
      (node (ref "D14") (pin "C") (pinfunction "CATHODE_C") (pintype "bidirectional"))
      (node (ref "R18") (pin "D2") (pinfunction "2_D2") (pintype "passive"))
    )
    (net (code "178") (name "Net-(D15-CATHODE)") (class "Default")
      (node (ref "D15") (pin "C") (pinfunction "CATHODE_C") (pintype "bidirectional"))
      (node (ref "R19") (pin "D2") (pinfunction "2_D2") (pintype "passive"))
    )
    (net (code "179") (name "Net-(D16-CATHODE)") (class "Default")
      (node (ref "D16") (pin "C") (pinfunction "CATHODE_C") (pintype "bidirectional"))
      (node (ref "R20") (pin "D2") (pinfunction "2_D2") (pintype "passive"))
    )
    (net (code "180") (name "Net-(D17-CATHODE)") (class "Default")
      (node (ref "D17") (pin "C") (pinfunction "CATHODE_C") (pintype "bidirectional"))
      (node (ref "R21") (pin "D2") (pinfunction "2_D2") (pintype "passive"))
    )
    (net (code "181") (name "Net-(D18-CATHODE)") (class "Default")
      (node (ref "D18") (pin "C") (pinfunction "CATHODE_C") (pintype "bidirectional"))
      (node (ref "R22") (pin "D2") (pinfunction "2_D2") (pintype "passive"))
    )
    (net (code "182") (name "Net-(D19-CATHODE)") (class "Default")
      (node (ref "D19") (pin "C") (pinfunction "CATHODE_C") (pintype "bidirectional"))
      (node (ref "R20") (pin "A2") (pinfunction "2_A2") (pintype "passive"))
    )
    (net (code "183") (name "Net-(D20-CATHODE)") (class "Default")
      (node (ref "D20") (pin "C") (pinfunction "CATHODE_C") (pintype "bidirectional"))
      (node (ref "R20") (pin "B2") (pinfunction "2_B2") (pintype "passive"))
    )
    (net (code "184") (name "Net-(D21-CATHODE)") (class "Default")
      (node (ref "D21") (pin "C") (pinfunction "CATHODE_C") (pintype "bidirectional"))
      (node (ref "R21") (pin "A2") (pinfunction "2_A2") (pintype "passive"))
    )
    (net (code "185") (name "Net-(D22-CATHODE)") (class "Default")
      (node (ref "D22") (pin "C") (pinfunction "CATHODE_C") (pintype "bidirectional"))
      (node (ref "R21") (pin "B2") (pinfunction "2_B2") (pintype "passive"))
    )
    (net (code "186") (name "Net-(D23-CATHODE)") (class "Default")
      (node (ref "D23") (pin "C") (pinfunction "CATHODE_C") (pintype "bidirectional"))
      (node (ref "R15") (pin "2") (pinfunction "2_2") (pintype "passive"))
    )
    (net (code "187") (name "Net-(D24-CATHODE)") (class "Default")
      (node (ref "D24") (pin "C") (pinfunction "CATHODE_C") (pintype "bidirectional"))
      (node (ref "R22") (pin "A2") (pinfunction "2_A2") (pintype "passive"))
    )
    (net (code "188") (name "Net-(D25-CATHODE)") (class "Default")
      (node (ref "D25") (pin "C") (pinfunction "CATHODE_C") (pintype "bidirectional"))
      (node (ref "R22") (pin "B2") (pinfunction "2_B2") (pintype "passive"))
    )
    (net (code "189") (name "Net-(D26-CATHODE)") (class "Default")
      (node (ref "D26") (pin "C") (pinfunction "CATHODE_C") (pintype "bidirectional"))
      (node (ref "R25") (pin "A1") (pinfunction "1_A1") (pintype "passive"))
    )
    (net (code "190") (name "Net-(D27-CATHODE)") (class "Default")
      (node (ref "D27") (pin "C") (pinfunction "CATHODE_C") (pintype "bidirectional"))
      (node (ref "R25") (pin "B1") (pinfunction "1_B1") (pintype "passive"))
    )
    (net (code "191") (name "Net-(D28-CATHODE)") (class "Default")
      (node (ref "D28") (pin "C") (pinfunction "CATHODE_C") (pintype "bidirectional"))
      (node (ref "R25") (pin "C1") (pinfunction "1_C1") (pintype "passive"))
    )
    (net (code "192") (name "Net-(D29-CATHODE)") (class "Default")
      (node (ref "D29") (pin "C") (pinfunction "CATHODE_C") (pintype "bidirectional"))
      (node (ref "R25") (pin "D1") (pinfunction "1_D1") (pintype "passive"))
    )
    (net (code "193") (name "Net-(D30-CATHODE)") (class "Default")
      (node (ref "D30") (pin "C") (pinfunction "CATHODE_C") (pintype "bidirectional"))
      (node (ref "R26") (pin "A1") (pinfunction "1_A1") (pintype "passive"))
    )
    (net (code "194") (name "Net-(D31-CATHODE)") (class "Default")
      (node (ref "D31") (pin "C") (pinfunction "CATHODE_C") (pintype "bidirectional"))
      (node (ref "R26") (pin "B1") (pinfunction "1_B1") (pintype "passive"))
    )
    (net (code "195") (name "Net-(D32-CATHODE)") (class "Default")
      (node (ref "D32") (pin "C") (pinfunction "CATHODE_C") (pintype "bidirectional"))
      (node (ref "R26") (pin "C1") (pinfunction "1_C1") (pintype "passive"))
    )
    (net (code "196") (name "Net-(D33-CATHODE)") (class "Default")
      (node (ref "D33") (pin "C") (pinfunction "CATHODE_C") (pintype "bidirectional"))
      (node (ref "R26") (pin "D1") (pinfunction "1_D1") (pintype "passive"))
    )
    (net (code "197") (name "Net-(D34-CATHODE)") (class "Default")
      (node (ref "D34") (pin "C") (pinfunction "CATHODE_C") (pintype "bidirectional"))
      (node (ref "R16") (pin "2") (pinfunction "2_2") (pintype "passive"))
    )
    (net (code "198") (name "Net-(FB1-P$1)") (class "Default")
      (node (ref "C39") (pin "1") (pinfunction "1_1") (pintype "bidirectional"))
      (node (ref "FB1") (pin "1") (pinfunction "P$1_1") (pintype "bidirectional"))
      (node (ref "U23") (pin "19") (pinfunction "VDDANA_19") (pintype "power_in"))
    )
    (net (code "199") (name "Net-(J1B-VCC_CONTROLLER)") (class "Default")
      (node (ref "J1") (pin "2") (pinfunction "VCC_CONTROLLER_2") (pintype "bidirectional"))
      (node (ref "SJ4") (pin "1") (pinfunction "1_1") (pintype "passive"))
      (node (ref "TP8") (pin "TESTPOINT") (pinfunction "TESTPOINT_TESTPOINT") (pintype "bidirectional"))
    )
    (net (code "200") (name "Net-(J1B-VCC_LINUX)") (class "Default")
      (node (ref "J1") (pin "4") (pinfunction "VCC_LINUX_4") (pintype "bidirectional"))
      (node (ref "SJ5") (pin "1") (pinfunction "1_1") (pintype "passive"))
      (node (ref "TP10") (pin "TESTPOINT") (pinfunction "TESTPOINT_TESTPOINT") (pintype "bidirectional"))
    )
    (net (code "201") (name "Net-(J2-5V)") (class "Default")
      (node (ref "J2") (pin "2") (pinfunction "5V_2") (pintype "bidirectional"))
      (node (ref "SJ2") (pin "1") (pinfunction "1_1") (pintype "passive"))
      (node (ref "TP4") (pin "TESTPOINT") (pinfunction "TESTPOINT_TESTPOINT") (pintype "bidirectional"))
    )
    (net (code "202") (name "Net-(J3-5V)") (class "Default")
      (node (ref "J3") (pin "2") (pinfunction "5V_2") (pintype "bidirectional"))
      (node (ref "SJ3") (pin "1") (pinfunction "1_1") (pintype "passive"))
      (node (ref "TP6") (pin "TESTPOINT") (pinfunction "TESTPOINT_TESTPOINT") (pintype "bidirectional"))
    )
    (net (code "203") (name "Net-(J7-VCC)") (class "Default")
      (node (ref "J7") (pin "1") (pinfunction "VCC_1") (pintype "bidirectional"))
      (node (ref "Q8") (pin "3") (pinfunction "D_3") (pintype "passive"))
      (node (ref "U13") (pin "1") (pinfunction "IN_1") (pintype "bidirectional"))
    )
    (net (code "204") (name "Net-(JP19-Pad1)") (class "Default")
      (node (ref "JP19") (pin "1") (pinfunction "1_1") (pintype "passive"))
      (node (ref "JP20") (pin "1") (pinfunction "1_1") (pintype "passive"))
    )
    (net (code "205") (name "Net-(JP19-Pad2)") (class "Default")
      (node (ref "JP19") (pin "2") (pinfunction "2_2") (pintype "passive"))
      (node (ref "JP20") (pin "2") (pinfunction "2_2") (pintype "passive"))
    )
    (net (code "206") (name "Net-(JP19-Pad3)") (class "Default")
      (node (ref "JP19") (pin "3") (pinfunction "3_3") (pintype "passive"))
      (node (ref "JP20") (pin "3") (pinfunction "3_3") (pintype "passive"))
    )
    (net (code "207") (name "Net-(JP19-Pad4)") (class "Default")
      (node (ref "JP19") (pin "4") (pinfunction "4_4") (pintype "passive"))
      (node (ref "JP20") (pin "4") (pinfunction "4_4") (pintype "passive"))
    )
    (net (code "208") (name "Net-(JP19-Pad5)") (class "Default")
      (node (ref "JP19") (pin "5") (pinfunction "5_5") (pintype "passive"))
      (node (ref "JP20") (pin "5") (pinfunction "5_5") (pintype "passive"))
    )
    (net (code "209") (name "Net-(JP19-Pad6)") (class "Default")
      (node (ref "JP19") (pin "6") (pinfunction "6_6") (pintype "passive"))
      (node (ref "JP20") (pin "6") (pinfunction "6_6") (pintype "passive"))
    )
    (net (code "210") (name "Net-(JP19-Pad7)") (class "Default")
      (node (ref "JP19") (pin "7") (pinfunction "7_7") (pintype "passive"))
      (node (ref "JP20") (pin "7") (pinfunction "7_7") (pintype "passive"))
    )
    (net (code "211") (name "Net-(JP19-Pad8)") (class "Default")
      (node (ref "JP19") (pin "8") (pinfunction "8_8") (pintype "passive"))
      (node (ref "JP20") (pin "8") (pinfunction "8_8") (pintype "passive"))
    )
    (net (code "212") (name "Net-(JP19-Pad9)") (class "Default")
      (node (ref "JP19") (pin "9") (pinfunction "9_9") (pintype "passive"))
      (node (ref "JP20") (pin "9") (pinfunction "9_9") (pintype "passive"))
    )
    (net (code "213") (name "Net-(JP19-Pad10)") (class "Default")
      (node (ref "JP19") (pin "10") (pinfunction "10_10") (pintype "passive"))
      (node (ref "JP20") (pin "10") (pinfunction "10_10") (pintype "passive"))
    )
    (net (code "214") (name "Net-(JP19-Pad11)") (class "Default")
      (node (ref "JP19") (pin "11") (pinfunction "11_11") (pintype "passive"))
      (node (ref "JP20") (pin "11") (pinfunction "11_11") (pintype "passive"))
    )
    (net (code "215") (name "Net-(JP19-Pad12)") (class "Default")
      (node (ref "JP19") (pin "12") (pinfunction "12_12") (pintype "passive"))
      (node (ref "JP20") (pin "12") (pinfunction "12_12") (pintype "passive"))
    )
    (net (code "216") (name "Net-(JP19-Pad13)") (class "Default")
      (node (ref "JP19") (pin "13") (pinfunction "13_13") (pintype "passive"))
      (node (ref "JP20") (pin "13") (pinfunction "13_13") (pintype "passive"))
    )
    (net (code "217") (name "Net-(JP19-Pad14)") (class "Default")
      (node (ref "JP19") (pin "14") (pinfunction "14_14") (pintype "passive"))
      (node (ref "JP20") (pin "14") (pinfunction "14_14") (pintype "passive"))
    )
    (net (code "218") (name "Net-(JP19-Pad15)") (class "Default")
      (node (ref "JP19") (pin "15") (pinfunction "15_15") (pintype "passive"))
      (node (ref "JP20") (pin "15") (pinfunction "15_15") (pintype "passive"))
    )
    (net (code "219") (name "Net-(JP19-Pad16)") (class "Default")
      (node (ref "JP19") (pin "16") (pinfunction "16_16") (pintype "passive"))
      (node (ref "JP20") (pin "16") (pinfunction "16_16") (pintype "passive"))
    )
    (net (code "220") (name "Net-(JP19-Pad18)") (class "Default")
      (node (ref "JP19") (pin "18") (pinfunction "18_18") (pintype "passive"))
      (node (ref "JP20") (pin "18") (pinfunction "18_18") (pintype "passive"))
    )
    (net (code "221") (name "Net-(JP19-Pad20)") (class "Default")
      (node (ref "JP19") (pin "20") (pinfunction "20_20") (pintype "passive"))
      (node (ref "JP20") (pin "20") (pinfunction "20_20") (pintype "passive"))
    )
    (net (code "222") (name "Net-(L1-1)") (class "Default")
      (node (ref "L1") (pin "P$1") (pinfunction "1_P$1") (pintype "bidirectional"))
      (node (ref "U23") (pin "7") (pinfunction "VDDOUT_7") (pintype "power_in"))
    )
    (net (code "223") (name "Net-(L1-2)") (class "Default")
      (node (ref "C63") (pin "1") (pinfunction "1_1") (pintype "bidirectional"))
      (node (ref "C73") (pin "1") (pinfunction "1_1") (pintype "bidirectional"))
      (node (ref "L1") (pin "P$2") (pinfunction "2_P$2") (pintype "bidirectional"))
      (node (ref "U23") (pin "5") (pinfunction "VDDCORE_5") (pintype "power_in"))
    )
    (net (code "224") (name "Net-(Q7-PadD1)") (class "Default")
      (node (ref "Q7") (pin "D1") (pinfunction "D1_D1") (pintype "bidirectional"))
      (node (ref "Q7") (pin "G2") (pinfunction "G2_G2") (pintype "input"))
      (node (ref "R31") (pin "1") (pinfunction "1_1") (pintype "passive"))
    )
    (net (code "225") (name "Net-(Q7-PadD2)") (class "Default")
      (node (ref "Q7") (pin "D2") (pinfunction "D2_D2") (pintype "bidirectional"))
      (node (ref "R16") (pin "1") (pinfunction "1_1") (pintype "passive"))
    )
    (net (code "226") (name "Net-(Q8-G)") (class "Default")
      (node (ref "Q8") (pin "1") (pinfunction "G_1") (pintype "passive"))
      (node (ref "U13") (pin "8") (pinfunction "GATE_8") (pintype "bidirectional"))
    )
    (net (code "227") (name "Net-(R15-Pad1)") (class "Default")
      (node (ref "R15") (pin "1") (pinfunction "1_1") (pintype "passive"))
      (node (ref "R17") (pin "2") (pinfunction "2_2") (pintype "passive"))
    )
    (net (code "228") (name "Net-(R18A-1)") (class "Default")
      (node (ref "Q2") (pin "D1") (pinfunction "D1_D1") (pintype "bidirectional"))
      (node (ref "R18") (pin "A1") (pinfunction "1_A1") (pintype "passive"))
    )
    (net (code "229") (name "Net-(R18B-1)") (class "Default")
      (node (ref "Q2") (pin "D2") (pinfunction "D2_D2") (pintype "bidirectional"))
      (node (ref "R18") (pin "B1") (pinfunction "1_B1") (pintype "passive"))
    )
    (net (code "230") (name "Net-(R19A-1)") (class "Default")
      (node (ref "Q3") (pin "D1") (pinfunction "D1_D1") (pintype "bidirectional"))
      (node (ref "R19") (pin "A1") (pinfunction "1_A1") (pintype "passive"))
    )
    (net (code "231") (name "Net-(R19B-1)") (class "Default")
      (node (ref "Q3") (pin "D2") (pinfunction "D2_D2") (pintype "bidirectional"))
      (node (ref "R19") (pin "B1") (pinfunction "1_B1") (pintype "passive"))
    )
    (net (code "232") (name "Net-(R20A-1)") (class "Default")
      (node (ref "Q4") (pin "D1") (pinfunction "D1_D1") (pintype "bidirectional"))
      (node (ref "R20") (pin "A1") (pinfunction "1_A1") (pintype "passive"))
    )
    (net (code "233") (name "Net-(R20B-1)") (class "Default")
      (node (ref "Q4") (pin "D2") (pinfunction "D2_D2") (pintype "bidirectional"))
      (node (ref "R20") (pin "B1") (pinfunction "1_B1") (pintype "passive"))
    )
    (net (code "234") (name "Net-(R21A-1)") (class "Default")
      (node (ref "Q5") (pin "D1") (pinfunction "D1_D1") (pintype "bidirectional"))
      (node (ref "R21") (pin "A1") (pinfunction "1_A1") (pintype "passive"))
    )
    (net (code "235") (name "Net-(R21B-1)") (class "Default")
      (node (ref "Q5") (pin "D2") (pinfunction "D2_D2") (pintype "bidirectional"))
      (node (ref "R21") (pin "B1") (pinfunction "1_B1") (pintype "passive"))
    )
    (net (code "236") (name "Net-(R22A-1)") (class "Default")
      (node (ref "Q6") (pin "D1") (pinfunction "D1_D1") (pintype "bidirectional"))
      (node (ref "R22") (pin "A1") (pinfunction "1_A1") (pintype "passive"))
    )
    (net (code "237") (name "Net-(R22B-1)") (class "Default")
      (node (ref "Q6") (pin "D2") (pinfunction "D2_D2") (pintype "bidirectional"))
      (node (ref "R22") (pin "B1") (pinfunction "1_B1") (pintype "passive"))
    )
    (net (code "238") (name "Net-(R32A-1)") (class "Default")
      (node (ref "R32") (pin "A1") (pinfunction "1_A1") (pintype "passive"))
      (node (ref "U22") (pin "6") (pinfunction "SC0_6") (pintype "bidirectional"))
      (node (ref "U9") (pin "3") (pinfunction "SCL_3") (pintype "open_collector"))
    )
    (net (code "239") (name "Net-(R32B-1)") (class "Default")
      (node (ref "R32") (pin "B1") (pinfunction "1_B1") (pintype "passive"))
      (node (ref "U22") (pin "5") (pinfunction "SD0_5") (pintype "bidirectional"))
      (node (ref "U9") (pin "4") (pinfunction "SDA_4") (pintype "open_collector"))
    )
    (net (code "240") (name "Net-(R32C-1)") (class "Default")
      (node (ref "R32") (pin "C1") (pinfunction "1_C1") (pintype "passive"))
      (node (ref "U22") (pin "4") (pinfunction "~{INT0}_4") (pintype "bidirectional"))
      (node (ref "U9") (pin "5") (pinfunction "~{ALERT}_5") (pintype "open_collector"))
    )
    (net (code "241") (name "Net-(R33A-1)") (class "Default")
      (node (ref "R33") (pin "A1") (pinfunction "1_A1") (pintype "passive"))
      (node (ref "U10") (pin "P4") (pinfunction "SCL_P4") (pintype "open_collector"))
      (node (ref "U22") (pin "9") (pinfunction "SC1_9") (pintype "bidirectional"))
    )
    (net (code "242") (name "Net-(R33B-1)") (class "Default")
      (node (ref "R33") (pin "B1") (pinfunction "1_B1") (pintype "passive"))
      (node (ref "U10") (pin "P5") (pinfunction "SDA_P5") (pintype "open_collector"))
      (node (ref "U22") (pin "8") (pinfunction "SD1_8") (pintype "bidirectional"))
    )
    (net (code "243") (name "Net-(R33C-1)") (class "Default")
      (node (ref "R33") (pin "C1") (pinfunction "1_C1") (pintype "passive"))
      (node (ref "U10") (pin "P6") (pinfunction "~{ALERT}_P6") (pintype "open_collector"))
      (node (ref "U22") (pin "7") (pinfunction "~{INT1}_7") (pintype "bidirectional"))
    )
    (net (code "244") (name "Net-(R34A-1)") (class "Default")
      (node (ref "R34") (pin "A1") (pinfunction "1_A1") (pintype "passive"))
      (node (ref "U11") (pin "P4") (pinfunction "SCL_P4") (pintype "open_collector"))
      (node (ref "U22") (pin "13") (pinfunction "SC2_13") (pintype "bidirectional"))
    )
    (net (code "245") (name "Net-(R34B-1)") (class "Default")
      (node (ref "R34") (pin "B1") (pinfunction "1_B1") (pintype "passive"))
      (node (ref "U11") (pin "P5") (pinfunction "SDA_P5") (pintype "open_collector"))
      (node (ref "U22") (pin "12") (pinfunction "SD2_12") (pintype "bidirectional"))
    )
    (net (code "246") (name "Net-(R34C-1)") (class "Default")
      (node (ref "R34") (pin "C1") (pinfunction "1_C1") (pintype "passive"))
      (node (ref "U11") (pin "P6") (pinfunction "~{ALERT}_P6") (pintype "open_collector"))
      (node (ref "U22") (pin "11") (pinfunction "~{INT2}_11") (pintype "bidirectional"))
    )
    (net (code "247") (name "Net-(R35A-1)") (class "Default")
      (node (ref "R35") (pin "A1") (pinfunction "1_A1") (pintype "passive"))
      (node (ref "U12") (pin "P4") (pinfunction "SCL_P4") (pintype "open_collector"))
      (node (ref "U22") (pin "16") (pinfunction "SC3_16") (pintype "bidirectional"))
    )
    (net (code "248") (name "Net-(R35B-1)") (class "Default")
      (node (ref "R35") (pin "B1") (pinfunction "1_B1") (pintype "passive"))
      (node (ref "U12") (pin "P5") (pinfunction "SDA_P5") (pintype "open_collector"))
      (node (ref "U22") (pin "15") (pinfunction "SD3_15") (pintype "bidirectional"))
    )
    (net (code "249") (name "Net-(R35C-1)") (class "Default")
      (node (ref "R35") (pin "C1") (pinfunction "1_C1") (pintype "passive"))
      (node (ref "U12") (pin "P6") (pinfunction "~{ALERT}_P6") (pintype "open_collector"))
      (node (ref "U22") (pin "14") (pinfunction "~{INT3}_14") (pintype "bidirectional"))
    )
    (net (code "250") (name "Net-(S3-2TA)") (class "Default")
      (node (ref "R81") (pin "2") (pinfunction "2_2") (pintype "passive"))
      (node (ref "S3") (pin "A2") (pinfunction "2TA_A2") (pintype "bidirectional"))
      (node (ref "U17") (pin "11") (pinfunction "P2_11") (pintype "bidirectional"))
    )
    (net (code "251") (name "Net-(S3-3TA)") (class "Default")
      (node (ref "R80") (pin "2") (pinfunction "2_2") (pintype "passive"))
      (node (ref "S3") (pin "A3") (pinfunction "3TA_A3") (pintype "bidirectional"))
      (node (ref "U17") (pin "10") (pinfunction "P1_10") (pintype "bidirectional"))
    )
    (net (code "252") (name "Net-(S3-4TA)") (class "Default")
      (node (ref "R79") (pin "2") (pinfunction "2_2") (pintype "passive"))
      (node (ref "S3") (pin "A4") (pinfunction "4TA_A4") (pintype "bidirectional"))
      (node (ref "U17") (pin "9") (pinfunction "P0_9") (pintype "bidirectional"))
    )
    (net (code "253") (name "Net-(S4-2TA)") (class "Default")
      (node (ref "R84") (pin "2") (pinfunction "2_2") (pintype "passive"))
      (node (ref "S4") (pin "A2") (pinfunction "2TA_A2") (pintype "bidirectional"))
      (node (ref "U18") (pin "11") (pinfunction "P2_11") (pintype "bidirectional"))
    )
    (net (code "254") (name "Net-(S4-3TA)") (class "Default")
      (node (ref "R83") (pin "2") (pinfunction "2_2") (pintype "passive"))
      (node (ref "S4") (pin "A3") (pinfunction "3TA_A3") (pintype "bidirectional"))
      (node (ref "U18") (pin "10") (pinfunction "P1_10") (pintype "bidirectional"))
    )
    (net (code "255") (name "Net-(S4-4TA)") (class "Default")
      (node (ref "R82") (pin "2") (pinfunction "2_2") (pintype "passive"))
      (node (ref "S4") (pin "A4") (pinfunction "4TA_A4") (pintype "bidirectional"))
      (node (ref "U18") (pin "9") (pinfunction "P0_9") (pintype "bidirectional"))
    )
    (net (code "256") (name "Net-(S17-EN)") (class "Default")
      (node (ref "Q7") (pin "G1") (pinfunction "G1_G1") (pintype "input"))
      (node (ref "S17") (pin "4") (pinfunction "EN_4") (pintype "bidirectional"))
      (node (ref "S18") (pin "4") (pinfunction "EN_4") (pintype "bidirectional"))
      (node (ref "U15") (pin "7") (pinfunction "~{RESET}_7") (pintype "bidirectional"))
    )
    (net (code "257") (name "Net-(S25-B)") (class "Default")
      (node (ref "C64") (pin "1") (pinfunction "1_1") (pintype "bidirectional"))
      (node (ref "S25") (pin "2") (pinfunction "B_2") (pintype "bidirectional"))
    )
    (net (code "258") (name "Net-(U1-3V3OUT)") (class "Default")
      (node (ref "C44") (pin "1") (pinfunction "1_1") (pintype "bidirectional"))
      (node (ref "U1") (pin "16") (pinfunction "3V3OUT_16") (pintype "output"))
    )
    (net (code "259") (name "Net-(U2-3V3OUT)") (class "Default")
      (node (ref "C45") (pin "1") (pinfunction "1_1") (pintype "bidirectional"))
      (node (ref "U2") (pin "16") (pinfunction "3V3OUT_16") (pintype "output"))
    )
    (net (code "260") (name "Net-(U3-3V3OUT)") (class "Default")
      (node (ref "C47") (pin "1") (pinfunction "1_1") (pintype "bidirectional"))
      (node (ref "U3") (pin "16") (pinfunction "3V3OUT_16") (pintype "output"))
    )
    (net (code "261") (name "Net-(U4-3V3OUT)") (class "Default")
      (node (ref "C49") (pin "1") (pinfunction "1_1") (pintype "bidirectional"))
      (node (ref "U4") (pin "16") (pinfunction "3V3OUT_16") (pintype "output"))
    )
    (net (code "262") (name "Net-(U5-3V3OUT)") (class "Default")
      (node (ref "C51") (pin "1") (pinfunction "1_1") (pintype "bidirectional"))
      (node (ref "U5") (pin "16") (pinfunction "3V3OUT_16") (pintype "output"))
    )
    (net (code "263") (name "Net-(U6-3V3OUT)") (class "Default")
      (node (ref "C56") (pin "1") (pinfunction "1_1") (pintype "bidirectional"))
      (node (ref "U6") (pin "16") (pinfunction "3V3OUT_16") (pintype "output"))
    )
    (net (code "264") (name "Net-(U13-~{PWRGD})") (class "Default")
      (node (ref "R17") (pin "1") (pinfunction "1_1") (pintype "passive"))
      (node (ref "U13") (pin "5") (pinfunction "~{PWRGD}_5") (pintype "bidirectional"))
    )
    (net (code "265") (name "Net-(U14-~{WC})") (class "Default")
      (node (ref "SJ1") (pin "2") (pinfunction "2_2") (pintype "passive"))
      (node (ref "U14") (pin "7") (pinfunction "~{WC}_7") (pintype "bidirectional"))
    )
    (net (code "266") (name "Net-(U15-SRT)") (class "Default")
      (node (ref "C65") (pin "1") (pinfunction "1_1") (pintype "bidirectional"))
      (node (ref "U15") (pin "3") (pinfunction "SRT_3") (pintype "bidirectional"))
    )
    (net (code "267") (name "Net-(U15-SWT)") (class "Default")
      (node (ref "S25") (pin "IN") (pinfunction "IN_IN") (pintype "bidirectional"))
      (node (ref "U15") (pin "2") (pinfunction "SWT_2") (pintype "bidirectional"))
    )
    (net (code "268") (name "Net-(U15-~{MR})") (class "Default")
      (node (ref "S13") (pin "3") (pinfunction "P$2_3") (pintype "passive"))
      (node (ref "S13") (pin "4") (pinfunction "P$2_4") (pintype "passive"))
      (node (ref "U15") (pin "1") (pinfunction "~{MR}_1") (pintype "bidirectional"))
    )
    (net (code "269") (name "Net-(U16-BP)") (class "Default")
      (node (ref "C13") (pin "1") (pinfunction "1_1") (pintype "bidirectional"))
      (node (ref "U16") (pin "4") (pinfunction "BP_4") (pintype "bidirectional"))
    )
    (net (code "270") (name "Net-(U16-~{SHDN})") (class "Default")
      (node (ref "R48") (pin "1") (pinfunction "1_1") (pintype "passive"))
      (node (ref "U16") (pin "3") (pinfunction "~{SHDN}_3") (pintype "bidirectional"))
    )
    (net (code "271") (name "Net-(U23-BIASH)") (class "Default")
      (node (ref "U23") (pin "28") (pinfunction "BIASH_28") (pintype "bidirectional"))
      (node (ref "U23") (pin "29") (pinfunction "BIASL_29") (pintype "bidirectional"))
    )
    (net (code "272") (name "Net-(U23-CAPH)") (class "Default")
      (node (ref "U23") (pin "25") (pinfunction "CAPH_25") (pintype "bidirectional"))
      (node (ref "U23") (pin "26") (pinfunction "CAPL_26") (pintype "bidirectional"))
    )
    (net (code "273") (name "Net-(U23-PA02)") (class "Default")
      (node (ref "R49") (pin "2") (pinfunction "2_2") (pintype "passive"))
      (node (ref "R85") (pin "1") (pinfunction "1_1") (pintype "passive"))
      (node (ref "U23") (pin "3") (pinfunction "PA02_3") (pintype "bidirectional"))
    )
    (net (code "274") (name "Net-(U28-D2+)") (class "Default")
      (node (ref "R11") (pin "1") (pinfunction "1_1") (pintype "passive"))
      (node (ref "U28") (pin "2") (pinfunction "D2+_2") (pintype "bidirectional"))
    )
    (net (code "275") (name "Net-(U28-D2-)") (class "Default")
      (node (ref "R12") (pin "1") (pinfunction "1_1") (pintype "passive"))
      (node (ref "U28") (pin "6") (pinfunction "D2-_6") (pintype "bidirectional"))
    )
    (net (code "276") (name "Net-(U29-D2+)") (class "Default")
      (node (ref "R13") (pin "1") (pinfunction "1_1") (pintype "passive"))
      (node (ref "U29") (pin "2") (pinfunction "D2+_2") (pintype "bidirectional"))
    )
    (net (code "277") (name "Net-(U29-D2-)") (class "Default")
      (node (ref "R14") (pin "1") (pinfunction "1_1") (pintype "passive"))
      (node (ref "U29") (pin "6") (pinfunction "D2-_6") (pintype "bidirectional"))
    )
    (net (code "278") (name "Net-(U30-S)") (class "Default")
      (node (ref "Q1") (pin "D2") (pinfunction "D2_D2") (pintype "bidirectional"))
      (node (ref "R67") (pin "1") (pinfunction "1_1") (pintype "passive"))
      (node (ref "U30") (pin "10") (pinfunction "S_10") (pintype "bidirectional"))
    )
    (net (code "279") (name "Net-(U31-DP0PUR)") (class "Default")
      (node (ref "R27") (pin "2") (pinfunction "2_2") (pintype "passive"))
      (node (ref "U31") (pin "2") (pinfunction "DP0PUR_2") (pintype "bidirectional"))
    )
    (net (code "280") (name "Net-(U31-XTAL1)") (class "Default")
      (node (ref "C9") (pin "2") (pinfunction "2_2") (pintype "bidirectional"))
      (node (ref "U31") (pin "45") (pinfunction "XTAL1_45") (pintype "bidirectional"))
      (node (ref "Y1") (pin "3") (pinfunction "2_3") (pintype "bidirectional"))
    )
    (net (code "281") (name "Net-(U31-XTAL2)") (class "Default")
      (node (ref "R28") (pin "2") (pinfunction "2_2") (pintype "passive"))
      (node (ref "U31") (pin "44") (pinfunction "XTAL2_44") (pintype "bidirectional"))
    )
    (net (code "282") (name "Net-(U32-DP0PUR)") (class "Default")
      (node (ref "R29") (pin "2") (pinfunction "2_2") (pintype "passive"))
      (node (ref "U32") (pin "2") (pinfunction "DP0PUR_2") (pintype "bidirectional"))
    )
    (net (code "283") (name "Net-(U32-XTAL1)") (class "Default")
      (node (ref "C11") (pin "2") (pinfunction "2_2") (pintype "bidirectional"))
      (node (ref "U32") (pin "45") (pinfunction "XTAL1_45") (pintype "bidirectional"))
      (node (ref "Y2") (pin "3") (pinfunction "2_3") (pintype "bidirectional"))
    )
    (net (code "284") (name "Net-(U32-XTAL2)") (class "Default")
      (node (ref "R30") (pin "2") (pinfunction "2_2") (pintype "passive"))
      (node (ref "U32") (pin "44") (pinfunction "XTAL2_44") (pintype "bidirectional"))
    )
    (net (code "285") (name "Net-(U32-~{PWRON1})") (class "Default")
      (node (ref "TP12") (pin "TESTPOINT") (pinfunction "TESTPOINT_TESTPOINT") (pintype "bidirectional"))
      (node (ref "U32") (pin "11") (pinfunction "~{PWRON1}_11") (pintype "bidirectional"))
    )
    (net (code "286") (name "PPS") (class "Default")
      (node (ref "J1") (pin "25") (pinfunction "PPS_25") (pintype "bidirectional"))
      (node (ref "JP11") (pin "4") (pinfunction "4_4") (pintype "passive"))
      (node (ref "JP14") (pin "5") (pinfunction "5_5") (pintype "passive"))
      (node (ref "U23") (pin "37") (pinfunction "PA18_37") (pintype "bidirectional"))
      (node (ref "U24") (pin "3") (pinfunction "A2_3") (pintype "bidirectional"))
      (node (ref "U25") (pin "3") (pinfunction "A2_3") (pintype "bidirectional"))
    )
    (net (code "287") (name "PROG0_EN") (class "Default")
      (node (ref "D14") (pin "A") (pinfunction "ANODE_A") (pintype "bidirectional"))
      (node (ref "R18") (pin "C2") (pinfunction "2_C2") (pintype "passive"))
      (node (ref "S14") (pin "1") (pinfunction "A_1") (pintype "bidirectional"))
      (node (ref "S19") (pin "12") (pinfunction "CTRL_12") (pintype "bidirectional"))
      (node (ref "S19") (pin "13") (pinfunction "CTRL_13") (pintype "bidirectional"))
      (node (ref "S19") (pin "5") (pinfunction "CTRL_5") (pintype "bidirectional"))
      (node (ref "S19") (pin "6") (pinfunction "CTRL_6") (pintype "bidirectional"))
    )
    (net (code "288") (name "PROG1_EN") (class "Default")
      (node (ref "D15") (pin "A") (pinfunction "ANODE_A") (pintype "bidirectional"))
      (node (ref "R19") (pin "C2") (pinfunction "2_C2") (pintype "passive"))
      (node (ref "S14") (pin "2") (pinfunction "B_2") (pintype "bidirectional"))
      (node (ref "S20") (pin "12") (pinfunction "CTRL_12") (pintype "bidirectional"))
      (node (ref "S20") (pin "13") (pinfunction "CTRL_13") (pintype "bidirectional"))
      (node (ref "S20") (pin "5") (pinfunction "CTRL_5") (pintype "bidirectional"))
      (node (ref "S20") (pin "6") (pinfunction "CTRL_6") (pintype "bidirectional"))
    )
    (net (code "289") (name "PROG2_EN") (class "Default")
      (node (ref "D16") (pin "A") (pinfunction "ANODE_A") (pintype "bidirectional"))
      (node (ref "R20") (pin "C2") (pinfunction "2_C2") (pintype "passive"))
      (node (ref "S14") (pin "3") (pinfunction "C_3") (pintype "bidirectional"))
      (node (ref "S21") (pin "12") (pinfunction "CTRL_12") (pintype "bidirectional"))
      (node (ref "S21") (pin "13") (pinfunction "CTRL_13") (pintype "bidirectional"))
      (node (ref "S21") (pin "5") (pinfunction "CTRL_5") (pintype "bidirectional"))
      (node (ref "S21") (pin "6") (pinfunction "CTRL_6") (pintype "bidirectional"))
    )
    (net (code "290") (name "PROG3_EN") (class "Default")
      (node (ref "D17") (pin "A") (pinfunction "ANODE_A") (pintype "bidirectional"))
      (node (ref "R21") (pin "C2") (pinfunction "2_C2") (pintype "passive"))
      (node (ref "S14") (pin "4") (pinfunction "D_4") (pintype "bidirectional"))
      (node (ref "S22") (pin "12") (pinfunction "CTRL_12") (pintype "bidirectional"))
      (node (ref "S22") (pin "13") (pinfunction "CTRL_13") (pintype "bidirectional"))
      (node (ref "S22") (pin "5") (pinfunction "CTRL_5") (pintype "bidirectional"))
      (node (ref "S22") (pin "6") (pinfunction "CTRL_6") (pintype "bidirectional"))
    )
    (net (code "291") (name "PROG4_EN") (class "Default")
      (node (ref "D18") (pin "A") (pinfunction "ANODE_A") (pintype "bidirectional"))
      (node (ref "R22") (pin "C2") (pinfunction "2_C2") (pintype "passive"))
      (node (ref "S14") (pin "5") (pinfunction "E_5") (pintype "bidirectional"))
      (node (ref "S23") (pin "12") (pinfunction "CTRL_12") (pintype "bidirectional"))
      (node (ref "S23") (pin "13") (pinfunction "CTRL_13") (pintype "bidirectional"))
      (node (ref "S23") (pin "5") (pinfunction "CTRL_5") (pintype "bidirectional"))
      (node (ref "S23") (pin "6") (pinfunction "CTRL_6") (pintype "bidirectional"))
    )
    (net (code "292") (name "RADIO_DEBUG_RX") (class "Default")
      (node (ref "U23") (pin "34") (pinfunction "PA15_34") (pintype "bidirectional"))
      (node (ref "U6") (pin "30") (pinfunction "TXD_30") (pintype "output"))
    )
    (net (code "293") (name "RADIO_DEBUG_TX") (class "Default")
      (node (ref "U23") (pin "35") (pinfunction "PA16_35") (pintype "bidirectional"))
      (node (ref "U6") (pin "2") (pinfunction "RXD_2") (pintype "input"))
    )
    (net (code "294") (name "RADIO_SWDCLK") (class "Default")
      (node (ref "R66") (pin "1") (pinfunction "1_1") (pintype "passive"))
      (node (ref "S23") (pin "3") (pinfunction "A_3") (pintype "bidirectional"))
      (node (ref "U23") (pin "9") (pinfunction "TCK_9") (pintype "bidirectional"))
    )
    (net (code "295") (name "RADIO_SWDIO") (class "Default")
      (node (ref "R65") (pin "1") (pinfunction "1_1") (pintype "passive"))
      (node (ref "S23") (pin "2") (pinfunction "A_2") (pintype "bidirectional"))
      (node (ref "U23") (pin "10") (pinfunction "PA03_10") (pintype "bidirectional"))
    )
    (net (code "296") (name "RADIO_UPLINK_RX") (class "Default")
      (node (ref "U1") (pin "30") (pinfunction "TXD_30") (pintype "output"))
      (node (ref "U23") (pin "23") (pinfunction "PA11_23") (pintype "bidirectional"))
    )
    (net (code "297") (name "RADIO_UPLINK_TX") (class "Default")
      (node (ref "U1") (pin "2") (pinfunction "RXD_2") (pintype "input"))
      (node (ref "U23") (pin "24") (pinfunction "PA12_24") (pintype "bidirectional"))
    )
    (net (code "298") (name "RADIO_~{RESET}") (class "Default")
      (node (ref "D2") (pin "1A") (pinfunction "ANODE_1A") (pintype "bidirectional"))
      (node (ref "S12") (pin "3") (pinfunction "P$2_3") (pintype "passive"))
      (node (ref "S12") (pin "4") (pinfunction "P$2_4") (pintype "passive"))
      (node (ref "S23") (pin "9") (pinfunction "A_9") (pintype "bidirectional"))
      (node (ref "U23") (pin "4") (pinfunction "~{RESET}_4") (pintype "bidirectional"))
    )
    (net (code "299") (name "SMBCLK") (class "Default")
      (node (ref "J1") (pin "5") (pinfunction "SMBCLK_5") (pintype "bidirectional"))
      (node (ref "J8") (pin "1") (pinfunction "SCL_1") (pintype "bidirectional"))
      (node (ref "JP11") (pin "7") (pinfunction "7_7") (pintype "passive"))
      (node (ref "JP12") (pin "5") (pinfunction "5_5") (pintype "passive"))
      (node (ref "R44") (pin "1") (pinfunction "1_1") (pintype "passive"))
      (node (ref "U14") (pin "6") (pinfunction "SCL_6") (pintype "bidirectional"))
      (node (ref "U17") (pin "19") (pinfunction "SCL_19") (pintype "bidirectional"))
      (node (ref "U18") (pin "19") (pinfunction "SCL_19") (pintype "bidirectional"))
      (node (ref "U19") (pin "19") (pinfunction "SCL_19") (pintype "bidirectional"))
      (node (ref "U22") (pin "18") (pinfunction "SCL_18") (pintype "bidirectional"))
    )
    (net (code "300") (name "SMBDATA") (class "Default")
      (node (ref "J1") (pin "3") (pinfunction "SMBDATA_3") (pintype "bidirectional"))
      (node (ref "J8") (pin "5") (pinfunction "SDA_5") (pintype "bidirectional"))
      (node (ref "JP11") (pin "8") (pinfunction "8_8") (pintype "passive"))
      (node (ref "JP12") (pin "3") (pinfunction "3_3") (pintype "passive"))
      (node (ref "R43") (pin "1") (pinfunction "1_1") (pintype "passive"))
      (node (ref "U14") (pin "5") (pinfunction "SDA_5") (pintype "bidirectional"))
      (node (ref "U17") (pin "20") (pinfunction "SDA_20") (pintype "bidirectional"))
      (node (ref "U18") (pin "20") (pinfunction "SDA_20") (pintype "bidirectional"))
      (node (ref "U19") (pin "20") (pinfunction "SDA_20") (pintype "bidirectional"))
      (node (ref "U22") (pin "19") (pinfunction "SDA_19") (pintype "bidirectional"))
    )
    (net (code "301") (name "USB+") (class "Default")
      (node (ref "R27") (pin "1") (pinfunction "1_1") (pintype "passive"))
      (node (ref "U30") (pin "5") (pinfunction "D-_5") (pintype "bidirectional"))
      (node (ref "U31") (pin "3") (pinfunction "DP0_3") (pintype "bidirectional"))
    )
    (net (code "302") (name "USB-") (class "Default")
      (node (ref "U30") (pin "3") (pinfunction "D+_3") (pintype "bidirectional"))
      (node (ref "U31") (pin "4") (pinfunction "DM0_4") (pintype "bidirectional"))
    )
    (net (code "303") (name "USB_SUSPEND_STATUS") (class "Default")
      (node (ref "JP7") (pin "3") (pinfunction "3_3") (pintype "passive"))
      (node (ref "U31") (pin "1") (pinfunction "SUSPND_1") (pintype "bidirectional"))
    )
    (net (code "304") (name "USB_~{RESET}") (class "Default")
      (node (ref "D2") (pin "2A") (pinfunction "ANODE_2A") (pintype "bidirectional"))
      (node (ref "JP7") (pin "5") (pinfunction "5_5") (pintype "passive"))
      (node (ref "R53") (pin "1") (pinfunction "1_1") (pintype "passive"))
      (node (ref "U19") (pin "9") (pinfunction "P0_9") (pintype "bidirectional"))
      (node (ref "U21") (pin "1") (pinfunction "~{RST}_1") (pintype "bidirectional"))
      (node (ref "U31") (pin "6") (pinfunction "~{RESET}_6") (pintype "bidirectional"))
    )
    (net (code "305") (name "VCC_BACKPLANE") (class "Default")
      (node (ref "C14") (pin "1") (pinfunction "1_1") (pintype "bidirectional"))
      (node (ref "C15") (pin "1") (pinfunction "1_1") (pintype "bidirectional"))
      (node (ref "C18") (pin "1") (pinfunction "1_1") (pintype "bidirectional"))
      (node (ref "C19") (pin "1") (pinfunction "1_1") (pintype "bidirectional"))
      (node (ref "C20") (pin "1") (pinfunction "1_1") (pintype "bidirectional"))
      (node (ref "C21") (pin "1") (pinfunction "1_1") (pintype "bidirectional"))
      (node (ref "C26") (pin "2") (pinfunction "2_2") (pintype "bidirectional"))
      (node (ref "C27") (pin "1") (pinfunction "1_1") (pintype "bidirectional"))
      (node (ref "C28") (pin "1") (pinfunction "1_1") (pintype "bidirectional"))
      (node (ref "C31") (pin "1") (pinfunction "1_1") (pintype "bidirectional"))
      (node (ref "C32") (pin "1") (pinfunction "1_1") (pintype "bidirectional"))
      (node (ref "C35") (pin "2") (pinfunction "2_2") (pintype "bidirectional"))
      (node (ref "C36") (pin "2") (pinfunction "2_2") (pintype "bidirectional"))
      (node (ref "C57") (pin "1") (pinfunction "1_1") (pintype "bidirectional"))
      (node (ref "C58") (pin "1") (pinfunction "1_1") (pintype "bidirectional"))
      (node (ref "C62") (pin "1") (pinfunction "1_1") (pintype "bidirectional"))
      (node (ref "C70") (pin "2") (pinfunction "2_2") (pintype "bidirectional"))
      (node (ref "J8") (pin "6") (pinfunction "VCC_6") (pintype "bidirectional"))
      (node (ref "JP12") (pin "2") (pinfunction "2_2") (pintype "passive"))
      (node (ref "JP16") (pin "3") (pinfunction "3_3") (pintype "passive"))
      (node (ref "R1") (pin "1") (pinfunction "1_1") (pintype "passive"))
      (node (ref "R36") (pin "2") (pinfunction "2_2") (pintype "passive"))
      (node (ref "R37") (pin "2") (pinfunction "2_2") (pintype "passive"))
      (node (ref "R42") (pin "2") (pinfunction "2_2") (pintype "passive"))
      (node (ref "R43") (pin "2") (pinfunction "2_2") (pintype "passive"))
      (node (ref "R44") (pin "2") (pinfunction "2_2") (pintype "passive"))
      (node (ref "R45") (pin "2") (pinfunction "2_2") (pintype "passive"))
      (node (ref "R46") (pin "2") (pinfunction "2_2") (pintype "passive"))
      (node (ref "R47") (pin "2") (pinfunction "2_2") (pintype "passive"))
      (node (ref "R50") (pin "2") (pinfunction "2_2") (pintype "passive"))
      (node (ref "R53") (pin "2") (pinfunction "2_2") (pintype "passive"))
      (node (ref "R62") (pin "A2") (pinfunction "2_A2") (pintype "passive"))
      (node (ref "R62") (pin "D2") (pinfunction "2_D2") (pintype "passive"))
      (node (ref "R63") (pin "C2") (pinfunction "2_C2") (pintype "passive"))
      (node (ref "R64") (pin "B2") (pinfunction "2_B2") (pintype "passive"))
      (node (ref "S5") (pin "3") (pinfunction "I0_3") (pintype "bidirectional"))
      (node (ref "S5") (pin "5") (pinfunction "VCC_5") (pintype "bidirectional"))
      (node (ref "S6") (pin "3") (pinfunction "I0_3") (pintype "bidirectional"))
      (node (ref "S6") (pin "5") (pinfunction "VCC_5") (pintype "bidirectional"))
      (node (ref "SJ1") (pin "1") (pinfunction "1_1") (pintype "passive"))
      (node (ref "SJ4") (pin "2") (pinfunction "2_2") (pintype "passive"))
      (node (ref "TP9") (pin "TESTPOINT") (pinfunction "TESTPOINT_TESTPOINT") (pintype "bidirectional"))
      (node (ref "U14") (pin "1") (pinfunction "E0_1") (pintype "bidirectional"))
      (node (ref "U14") (pin "8") (pinfunction "VCC_8") (pintype "bidirectional"))
      (node (ref "U17") (pin "18") (pinfunction "VCC_18") (pintype "bidirectional"))
      (node (ref "U18") (pin "18") (pinfunction "VCC_18") (pintype "bidirectional"))
      (node (ref "U18") (pin "3") (pinfunction "A0_3") (pintype "bidirectional"))
      (node (ref "U19") (pin "18") (pinfunction "VCC_18") (pintype "bidirectional"))
      (node (ref "U19") (pin "2") (pinfunction "A1_2") (pintype "bidirectional"))
      (node (ref "U19") (pin "3") (pinfunction "A0_3") (pintype "bidirectional"))
      (node (ref "U21") (pin "2") (pinfunction "VCC_2") (pintype "bidirectional"))
      (node (ref "U22") (pin "20") (pinfunction "VCC_20") (pintype "bidirectional"))
      (node (ref "U24") (pin "1") (pinfunction "VCC_A_1") (pintype "bidirectional"))
      (node (ref "U24") (pin "5") (pinfunction "DIR_5") (pintype "bidirectional"))
      (node (ref "U25") (pin "1") (pinfunction "VCC_A_1") (pintype "bidirectional"))
      (node (ref "U25") (pin "5") (pinfunction "DIR_5") (pintype "bidirectional"))
      (node (ref "U26") (pin "1") (pinfunction "VCC_A_1") (pintype "bidirectional"))
      (node (ref "U27") (pin "1") (pinfunction "VCC_A_1") (pintype "bidirectional"))
      (node (ref "U28") (pin "9") (pinfunction "VCC_9") (pintype "bidirectional"))
      (node (ref "U29") (pin "9") (pinfunction "VCC_9") (pintype "bidirectional"))
      (node (ref "U31") (pin "10") (pinfunction "~{BUSPWR}_10") (pintype "bidirectional"))
      (node (ref "U31") (pin "46") (pinfunction "VCC_46") (pintype "bidirectional"))
      (node (ref "U31") (pin "47") (pinfunction "~{EXTMEM}_47") (pintype "bidirectional"))
      (node (ref "U31") (pin "8") (pinfunction "EEDATA/~{GANGED}_8") (pintype "bidirectional"))
      (node (ref "U31") (pin "9") (pinfunction "VCC_9") (pintype "bidirectional"))
      (node (ref "U4") (pin "1") (pinfunction "VCCIO_1") (pintype "power_in"))
      (node (ref "U5") (pin "1") (pinfunction "VCCIO_1") (pintype "power_in"))
      (node (ref "U7") (pin "1") (pinfunction "VCC_A_1") (pintype "bidirectional"))
      (node (ref "U8") (pin "1") (pinfunction "VCC_A_1") (pintype "bidirectional"))
      (node (ref "U9") (pin "6") (pinfunction "SENSE-_6") (pintype "open_collector"))
    )
    (net (code "306") (name "VCC_LINUX") (class "Default")
      (node (ref "C59") (pin "1") (pinfunction "1_1") (pintype "bidirectional"))
      (node (ref "JP12") (pin "4") (pinfunction "4_4") (pintype "passive"))
      (node (ref "JP16") (pin "4") (pinfunction "4_4") (pintype "passive"))
      (node (ref "JP19") (pin "17") (pinfunction "17_17") (pintype "passive"))
      (node (ref "JP20") (pin "17") (pinfunction "17_17") (pintype "passive"))
      (node (ref "R2") (pin "1") (pinfunction "1_1") (pintype "passive"))
      (node (ref "SJ5") (pin "2") (pinfunction "2_2") (pintype "passive"))
      (node (ref "TP11") (pin "TESTPOINT") (pinfunction "TESTPOINT_TESTPOINT") (pintype "bidirectional"))
      (node (ref "U10") (pin "P8") (pinfunction "SENSE-_P8") (pintype "open_collector"))
    )
    (net (code "307") (name "unconnected-(D2C-ANODE-Pad3A)") (class "Default")
      (node (ref "D2") (pin "3A") (pinfunction "ANODE_3A") (pintype "bidirectional"))
    )
    (net (code "308") (name "unconnected-(D35-C-Pad2)") (class "Default")
      (node (ref "D35") (pin "2") (pinfunction "C_2") (pintype "bidirectional"))
    )
    (net (code "309") (name "unconnected-(D35-D-Pad4)") (class "Default")
      (node (ref "D35") (pin "4") (pinfunction "D_4") (pintype "bidirectional"))
    )
    (net (code "310") (name "unconnected-(J4-ID-Pad4)") (class "Default")
      (node (ref "J4") (pin "4") (pinfunction "ID_4") (pintype "bidirectional"))
    )
    (net (code "311") (name "unconnected-(J5-+5V-Pad1)") (class "Default")
      (node (ref "J5") (pin "1") (pinfunction "+5V_1") (pintype "bidirectional"))
    )
    (net (code "312") (name "unconnected-(J5-ID-Pad4)") (class "Default")
      (node (ref "J5") (pin "4") (pinfunction "ID_4") (pintype "bidirectional"))
    )
    (net (code "313") (name "unconnected-(J6-Pad2)") (class "Default")
      (node (ref "J6") (pin "2") (pinfunction "2_2") (pintype "passive"))
    )
    (net (code "314") (name "unconnected-(J7-NC-Pad3)") (class "Default")
      (node (ref "J7") (pin "3") (pinfunction "NC_3") (pintype "bidirectional"))
    )
    (net (code "315") (name "unconnected-(JP7-Pad6)") (class "Default")
      (node (ref "JP7") (pin "6") (pinfunction "6_6") (pintype "passive"))
    )
    (net (code "316") (name "unconnected-(Q1-PadD1)") (class "Default")
      (node (ref "Q1") (pin "D1") (pinfunction "D1_D1") (pintype "bidirectional"))
    )
    (net (code "317") (name "unconnected-(Q1-PadG1)") (class "Default")
      (node (ref "Q1") (pin "G1") (pinfunction "G1_G1") (pintype "input"))
    )
    (net (code "318") (name "unconnected-(S3-1TA-PadA1)") (class "Default")
      (node (ref "S3") (pin "A1") (pinfunction "1TA_A1") (pintype "bidirectional"))
    )
    (net (code "319") (name "unconnected-(S4-1TA-PadA1)") (class "Default")
      (node (ref "S4") (pin "A1") (pinfunction "1TA_A1") (pintype "bidirectional"))
    )
    (net (code "320") (name "unconnected-(S14-F-Pad6)") (class "Default")
      (node (ref "S14") (pin "6") (pinfunction "F_6") (pintype "bidirectional"))
    )
    (net (code "321") (name "unconnected-(S24-B-Pad2)") (class "Default")
      (node (ref "S24") (pin "2") (pinfunction "B_2") (pintype "bidirectional"))
    )
    (net (code "322") (name "unconnected-(U1-CBUS0-Pad22)") (class "Default")
      (node (ref "U1") (pin "22") (pinfunction "CBUS0_22") (pintype "bidirectional"))
    )
    (net (code "323") (name "unconnected-(U1-CBUS1-Pad21)") (class "Default")
      (node (ref "U1") (pin "21") (pinfunction "CBUS1_21") (pintype "bidirectional"))
    )
    (net (code "324") (name "unconnected-(U1-CBUS2-Pad10)") (class "Default")
      (node (ref "U1") (pin "10") (pinfunction "CBUS2_10") (pintype "bidirectional"))
    )
    (net (code "325") (name "unconnected-(U1-CBUS3-Pad11)") (class "Default")
      (node (ref "U1") (pin "11") (pinfunction "CBUS3_11") (pintype "bidirectional"))
    )
    (net (code "326") (name "unconnected-(U1-CBUS4-Pad9)") (class "Default")
      (node (ref "U1") (pin "9") (pinfunction "CBUS4_9") (pintype "bidirectional"))
    )
    (net (code "327") (name "unconnected-(U1-OSCI-Pad27)") (class "Default")
      (node (ref "U1") (pin "27") (pinfunction "OSCI_27") (pintype "input"))
    )
    (net (code "328") (name "unconnected-(U1-OSCO-Pad28)") (class "Default")
      (node (ref "U1") (pin "28") (pinfunction "OSCO_28") (pintype "output"))
    )
    (net (code "329") (name "unconnected-(U1-~{CTS}-Pad8)") (class "Default")
      (node (ref "U1") (pin "8") (pinfunction "~{CTS}_8") (pintype "input"))
    )
    (net (code "330") (name "unconnected-(U1-~{DCD}-Pad7)") (class "Default")
      (node (ref "U1") (pin "7") (pinfunction "~{DCD}_7") (pintype "input"))
    )
    (net (code "331") (name "unconnected-(U1-~{DSR}-Pad6)") (class "Default")
      (node (ref "U1") (pin "6") (pinfunction "~{DSR}_6") (pintype "input"))
    )
    (net (code "332") (name "unconnected-(U1-~{DTR}-Pad31)") (class "Default")
      (node (ref "U1") (pin "31") (pinfunction "~{DTR}_31") (pintype "output"))
    )
    (net (code "333") (name "unconnected-(U1-~{RI}-Pad3)") (class "Default")
      (node (ref "U1") (pin "3") (pinfunction "~{RI}_3") (pintype "input"))
    )
    (net (code "334") (name "unconnected-(U1-~{RTS}-Pad32)") (class "Default")
      (node (ref "U1") (pin "32") (pinfunction "~{RTS}_32") (pintype "output"))
    )
    (net (code "335") (name "unconnected-(U2-CBUS0-Pad22)") (class "Default")
      (node (ref "U2") (pin "22") (pinfunction "CBUS0_22") (pintype "bidirectional"))
    )
    (net (code "336") (name "unconnected-(U2-CBUS1-Pad21)") (class "Default")
      (node (ref "U2") (pin "21") (pinfunction "CBUS1_21") (pintype "bidirectional"))
    )
    (net (code "337") (name "unconnected-(U2-CBUS2-Pad10)") (class "Default")
      (node (ref "U2") (pin "10") (pinfunction "CBUS2_10") (pintype "bidirectional"))
    )
    (net (code "338") (name "unconnected-(U2-CBUS3-Pad11)") (class "Default")
      (node (ref "U2") (pin "11") (pinfunction "CBUS3_11") (pintype "bidirectional"))
    )
    (net (code "339") (name "unconnected-(U2-CBUS4-Pad9)") (class "Default")
      (node (ref "U2") (pin "9") (pinfunction "CBUS4_9") (pintype "bidirectional"))
    )
    (net (code "340") (name "unconnected-(U2-OSCI-Pad27)") (class "Default")
      (node (ref "U2") (pin "27") (pinfunction "OSCI_27") (pintype "input"))
    )
    (net (code "341") (name "unconnected-(U2-OSCO-Pad28)") (class "Default")
      (node (ref "U2") (pin "28") (pinfunction "OSCO_28") (pintype "output"))
    )
    (net (code "342") (name "unconnected-(U2-~{CTS}-Pad8)") (class "Default")
      (node (ref "U2") (pin "8") (pinfunction "~{CTS}_8") (pintype "input"))
    )
    (net (code "343") (name "unconnected-(U2-~{DCD}-Pad7)") (class "Default")
      (node (ref "U2") (pin "7") (pinfunction "~{DCD}_7") (pintype "input"))
    )
    (net (code "344") (name "unconnected-(U2-~{DSR}-Pad6)") (class "Default")
      (node (ref "U2") (pin "6") (pinfunction "~{DSR}_6") (pintype "input"))
    )
    (net (code "345") (name "unconnected-(U2-~{DTR}-Pad31)") (class "Default")
      (node (ref "U2") (pin "31") (pinfunction "~{DTR}_31") (pintype "output"))
    )
    (net (code "346") (name "unconnected-(U2-~{RI}-Pad3)") (class "Default")
      (node (ref "U2") (pin "3") (pinfunction "~{RI}_3") (pintype "input"))
    )
    (net (code "347") (name "unconnected-(U2-~{RTS}-Pad32)") (class "Default")
      (node (ref "U2") (pin "32") (pinfunction "~{RTS}_32") (pintype "output"))
    )
    (net (code "348") (name "unconnected-(U3-CBUS0-Pad22)") (class "Default")
      (node (ref "U3") (pin "22") (pinfunction "CBUS0_22") (pintype "bidirectional"))
    )
    (net (code "349") (name "unconnected-(U3-CBUS1-Pad21)") (class "Default")
      (node (ref "U3") (pin "21") (pinfunction "CBUS1_21") (pintype "bidirectional"))
    )
    (net (code "350") (name "unconnected-(U3-CBUS2-Pad10)") (class "Default")
      (node (ref "U3") (pin "10") (pinfunction "CBUS2_10") (pintype "bidirectional"))
    )
    (net (code "351") (name "unconnected-(U3-CBUS3-Pad11)") (class "Default")
      (node (ref "U3") (pin "11") (pinfunction "CBUS3_11") (pintype "bidirectional"))
    )
    (net (code "352") (name "unconnected-(U3-CBUS4-Pad9)") (class "Default")
      (node (ref "U3") (pin "9") (pinfunction "CBUS4_9") (pintype "bidirectional"))
    )
    (net (code "353") (name "unconnected-(U3-OSCI-Pad27)") (class "Default")
      (node (ref "U3") (pin "27") (pinfunction "OSCI_27") (pintype "input"))
    )
    (net (code "354") (name "unconnected-(U3-OSCO-Pad28)") (class "Default")
      (node (ref "U3") (pin "28") (pinfunction "OSCO_28") (pintype "output"))
    )
    (net (code "355") (name "unconnected-(U3-~{CTS}-Pad8)") (class "Default")
      (node (ref "U3") (pin "8") (pinfunction "~{CTS}_8") (pintype "input"))
    )
    (net (code "356") (name "unconnected-(U3-~{DCD}-Pad7)") (class "Default")
      (node (ref "U3") (pin "7") (pinfunction "~{DCD}_7") (pintype "input"))
    )
    (net (code "357") (name "unconnected-(U3-~{DSR}-Pad6)") (class "Default")
      (node (ref "U3") (pin "6") (pinfunction "~{DSR}_6") (pintype "input"))
    )
    (net (code "358") (name "unconnected-(U3-~{DTR}-Pad31)") (class "Default")
      (node (ref "U3") (pin "31") (pinfunction "~{DTR}_31") (pintype "output"))
    )
    (net (code "359") (name "unconnected-(U3-~{RI}-Pad3)") (class "Default")
      (node (ref "U3") (pin "3") (pinfunction "~{RI}_3") (pintype "input"))
    )
    (net (code "360") (name "unconnected-(U3-~{RTS}-Pad32)") (class "Default")
      (node (ref "U3") (pin "32") (pinfunction "~{RTS}_32") (pintype "output"))
    )
    (net (code "361") (name "unconnected-(U4-CBUS0-Pad22)") (class "Default")
      (node (ref "U4") (pin "22") (pinfunction "CBUS0_22") (pintype "bidirectional"))
    )
    (net (code "362") (name "unconnected-(U4-CBUS1-Pad21)") (class "Default")
      (node (ref "U4") (pin "21") (pinfunction "CBUS1_21") (pintype "bidirectional"))
    )
    (net (code "363") (name "unconnected-(U4-CBUS2-Pad10)") (class "Default")
      (node (ref "U4") (pin "10") (pinfunction "CBUS2_10") (pintype "bidirectional"))
    )
    (net (code "364") (name "unconnected-(U4-CBUS3-Pad11)") (class "Default")
      (node (ref "U4") (pin "11") (pinfunction "CBUS3_11") (pintype "bidirectional"))
    )
    (net (code "365") (name "unconnected-(U4-CBUS4-Pad9)") (class "Default")
      (node (ref "U4") (pin "9") (pinfunction "CBUS4_9") (pintype "bidirectional"))
    )
    (net (code "366") (name "unconnected-(U4-OSCI-Pad27)") (class "Default")
      (node (ref "U4") (pin "27") (pinfunction "OSCI_27") (pintype "input"))
    )
    (net (code "367") (name "unconnected-(U4-OSCO-Pad28)") (class "Default")
      (node (ref "U4") (pin "28") (pinfunction "OSCO_28") (pintype "output"))
    )
    (net (code "368") (name "unconnected-(U4-~{CTS}-Pad8)") (class "Default")
      (node (ref "U4") (pin "8") (pinfunction "~{CTS}_8") (pintype "input"))
    )
    (net (code "369") (name "unconnected-(U4-~{DCD}-Pad7)") (class "Default")
      (node (ref "U4") (pin "7") (pinfunction "~{DCD}_7") (pintype "input"))
    )
    (net (code "370") (name "unconnected-(U4-~{DSR}-Pad6)") (class "Default")
      (node (ref "U4") (pin "6") (pinfunction "~{DSR}_6") (pintype "input"))
    )
    (net (code "371") (name "unconnected-(U4-~{DTR}-Pad31)") (class "Default")
      (node (ref "U4") (pin "31") (pinfunction "~{DTR}_31") (pintype "output"))
    )
    (net (code "372") (name "unconnected-(U4-~{RI}-Pad3)") (class "Default")
      (node (ref "U4") (pin "3") (pinfunction "~{RI}_3") (pintype "input"))
    )
    (net (code "373") (name "unconnected-(U4-~{RTS}-Pad32)") (class "Default")
      (node (ref "U4") (pin "32") (pinfunction "~{RTS}_32") (pintype "output"))
    )
    (net (code "374") (name "unconnected-(U5-CBUS0-Pad22)") (class "Default")
      (node (ref "U5") (pin "22") (pinfunction "CBUS0_22") (pintype "bidirectional"))
    )
    (net (code "375") (name "unconnected-(U5-CBUS1-Pad21)") (class "Default")
      (node (ref "U5") (pin "21") (pinfunction "CBUS1_21") (pintype "bidirectional"))
    )
    (net (code "376") (name "unconnected-(U5-CBUS2-Pad10)") (class "Default")
      (node (ref "U5") (pin "10") (pinfunction "CBUS2_10") (pintype "bidirectional"))
    )
    (net (code "377") (name "unconnected-(U5-CBUS3-Pad11)") (class "Default")
      (node (ref "U5") (pin "11") (pinfunction "CBUS3_11") (pintype "bidirectional"))
    )
    (net (code "378") (name "unconnected-(U5-CBUS4-Pad9)") (class "Default")
      (node (ref "U5") (pin "9") (pinfunction "CBUS4_9") (pintype "bidirectional"))
    )
    (net (code "379") (name "unconnected-(U5-OSCI-Pad27)") (class "Default")
      (node (ref "U5") (pin "27") (pinfunction "OSCI_27") (pintype "input"))
    )
    (net (code "380") (name "unconnected-(U5-OSCO-Pad28)") (class "Default")
      (node (ref "U5") (pin "28") (pinfunction "OSCO_28") (pintype "output"))
    )
    (net (code "381") (name "unconnected-(U5-~{CTS}-Pad8)") (class "Default")
      (node (ref "U5") (pin "8") (pinfunction "~{CTS}_8") (pintype "input"))
    )
    (net (code "382") (name "unconnected-(U5-~{DCD}-Pad7)") (class "Default")
      (node (ref "U5") (pin "7") (pinfunction "~{DCD}_7") (pintype "input"))
    )
    (net (code "383") (name "unconnected-(U5-~{DSR}-Pad6)") (class "Default")
      (node (ref "U5") (pin "6") (pinfunction "~{DSR}_6") (pintype "input"))
    )
    (net (code "384") (name "unconnected-(U5-~{DTR}-Pad31)") (class "Default")
      (node (ref "U5") (pin "31") (pinfunction "~{DTR}_31") (pintype "output"))
    )
    (net (code "385") (name "unconnected-(U5-~{RI}-Pad3)") (class "Default")
      (node (ref "U5") (pin "3") (pinfunction "~{RI}_3") (pintype "input"))
    )
    (net (code "386") (name "unconnected-(U5-~{RTS}-Pad32)") (class "Default")
      (node (ref "U5") (pin "32") (pinfunction "~{RTS}_32") (pintype "output"))
    )
    (net (code "387") (name "unconnected-(U6-CBUS0-Pad22)") (class "Default")
      (node (ref "U6") (pin "22") (pinfunction "CBUS0_22") (pintype "bidirectional"))
    )
    (net (code "388") (name "unconnected-(U6-CBUS1-Pad21)") (class "Default")
      (node (ref "U6") (pin "21") (pinfunction "CBUS1_21") (pintype "bidirectional"))
    )
    (net (code "389") (name "unconnected-(U6-CBUS2-Pad10)") (class "Default")
      (node (ref "U6") (pin "10") (pinfunction "CBUS2_10") (pintype "bidirectional"))
    )
    (net (code "390") (name "unconnected-(U6-CBUS3-Pad11)") (class "Default")
      (node (ref "U6") (pin "11") (pinfunction "CBUS3_11") (pintype "bidirectional"))
    )
    (net (code "391") (name "unconnected-(U6-CBUS4-Pad9)") (class "Default")
      (node (ref "U6") (pin "9") (pinfunction "CBUS4_9") (pintype "bidirectional"))
    )
    (net (code "392") (name "unconnected-(U6-OSCI-Pad27)") (class "Default")
      (node (ref "U6") (pin "27") (pinfunction "OSCI_27") (pintype "input"))
    )
    (net (code "393") (name "unconnected-(U6-OSCO-Pad28)") (class "Default")
      (node (ref "U6") (pin "28") (pinfunction "OSCO_28") (pintype "output"))
    )
    (net (code "394") (name "unconnected-(U6-~{CTS}-Pad8)") (class "Default")
      (node (ref "U6") (pin "8") (pinfunction "~{CTS}_8") (pintype "input"))
    )
    (net (code "395") (name "unconnected-(U6-~{DCD}-Pad7)") (class "Default")
      (node (ref "U6") (pin "7") (pinfunction "~{DCD}_7") (pintype "input"))
    )
    (net (code "396") (name "unconnected-(U6-~{DSR}-Pad6)") (class "Default")
      (node (ref "U6") (pin "6") (pinfunction "~{DSR}_6") (pintype "input"))
    )
    (net (code "397") (name "unconnected-(U6-~{DTR}-Pad31)") (class "Default")
      (node (ref "U6") (pin "31") (pinfunction "~{DTR}_31") (pintype "output"))
    )
    (net (code "398") (name "unconnected-(U6-~{RI}-Pad3)") (class "Default")
      (node (ref "U6") (pin "3") (pinfunction "~{RI}_3") (pintype "input"))
    )
    (net (code "399") (name "unconnected-(U6-~{RTS}-Pad32)") (class "Default")
      (node (ref "U6") (pin "32") (pinfunction "~{RTS}_32") (pintype "output"))
    )
    (net (code "400") (name "unconnected-(U17-INT-Pad7)") (class "Default")
      (node (ref "U17") (pin "7") (pinfunction "INT_7") (pintype "bidirectional"))
    )
    (net (code "401") (name "unconnected-(U17-P3-Pad12)") (class "Default")
      (node (ref "U17") (pin "12") (pinfunction "P3_12") (pintype "bidirectional"))
    )
    (net (code "402") (name "unconnected-(U17-P4-Pad13)") (class "Default")
      (node (ref "U17") (pin "13") (pinfunction "P4_13") (pintype "bidirectional"))
    )
    (net (code "403") (name "unconnected-(U17-P5-Pad14)") (class "Default")
      (node (ref "U17") (pin "14") (pinfunction "P5_14") (pintype "bidirectional"))
    )
    (net (code "404") (name "unconnected-(U17-P6-Pad15)") (class "Default")
      (node (ref "U17") (pin "15") (pinfunction "P6_15") (pintype "bidirectional"))
    )
    (net (code "405") (name "unconnected-(U17-P7-Pad16)") (class "Default")
      (node (ref "U17") (pin "16") (pinfunction "P7_16") (pintype "bidirectional"))
    )
    (net (code "406") (name "unconnected-(U18-INT-Pad7)") (class "Default")
      (node (ref "U18") (pin "7") (pinfunction "INT_7") (pintype "bidirectional"))
    )
    (net (code "407") (name "unconnected-(U18-P3-Pad12)") (class "Default")
      (node (ref "U18") (pin "12") (pinfunction "P3_12") (pintype "bidirectional"))
    )
    (net (code "408") (name "unconnected-(U18-P4-Pad13)") (class "Default")
      (node (ref "U18") (pin "13") (pinfunction "P4_13") (pintype "bidirectional"))
    )
    (net (code "409") (name "unconnected-(U18-P5-Pad14)") (class "Default")
      (node (ref "U18") (pin "14") (pinfunction "P5_14") (pintype "bidirectional"))
    )
    (net (code "410") (name "unconnected-(U18-P6-Pad15)") (class "Default")
      (node (ref "U18") (pin "15") (pinfunction "P6_15") (pintype "bidirectional"))
    )
    (net (code "411") (name "unconnected-(U18-P7-Pad16)") (class "Default")
      (node (ref "U18") (pin "16") (pinfunction "P7_16") (pintype "bidirectional"))
    )
    (net (code "412") (name "unconnected-(U19-INT-Pad7)") (class "Default")
      (node (ref "U19") (pin "7") (pinfunction "INT_7") (pintype "bidirectional"))
    )
    (net (code "413") (name "unconnected-(U19-P4-Pad13)") (class "Default")
      (node (ref "U19") (pin "13") (pinfunction "P4_13") (pintype "bidirectional"))
    )
    (net (code "414") (name "unconnected-(U19-P5-Pad14)") (class "Default")
      (node (ref "U19") (pin "14") (pinfunction "P5_14") (pintype "bidirectional"))
    )
    (net (code "415") (name "unconnected-(U19-P6-Pad15)") (class "Default")
      (node (ref "U19") (pin "15") (pinfunction "P6_15") (pintype "bidirectional"))
    )
    (net (code "416") (name "unconnected-(U19-P7-Pad16)") (class "Default")
      (node (ref "U19") (pin "16") (pinfunction "P7_16") (pintype "bidirectional"))
    )
    (net (code "417") (name "unconnected-(U23-ADVREFP-Pad18)") (class "Default")
      (node (ref "U23") (pin "18") (pinfunction "ADVREFP_18") (pintype "bidirectional"))
    )
    (net (code "418") (name "unconnected-(U23-PA04-Pad11)") (class "Default")
      (node (ref "U23") (pin "11") (pinfunction "PA04_11") (pintype "bidirectional"))
    )
    (net (code "419") (name "unconnected-(U23-PA05-Pad12)") (class "Default")
      (node (ref "U23") (pin "12") (pinfunction "PA05_12") (pintype "bidirectional"))
    )
    (net (code "420") (name "unconnected-(U23-PA06-Pad15)") (class "Default")
      (node (ref "U23") (pin "15") (pinfunction "PA06_15") (pintype "bidirectional"))
    )
    (net (code "421") (name "unconnected-(U23-PA07-Pad16)") (class "Default")
      (node (ref "U23") (pin "16") (pinfunction "PA07_16") (pintype "bidirectional"))
    )
    (net (code "422") (name "unconnected-(U23-PA08-Pad20)") (class "Default")
      (node (ref "U23") (pin "20") (pinfunction "PA08_20") (pintype "bidirectional"))
    )
    (net (code "423") (name "unconnected-(U23-PA09-Pad21)") (class "Default")
      (node (ref "U23") (pin "21") (pinfunction "PA09_21") (pintype "bidirectional"))
    )
    (net (code "424") (name "unconnected-(U23-PA10-Pad22)") (class "Default")
      (node (ref "U23") (pin "22") (pinfunction "PA10_22") (pintype "bidirectional"))
    )
    (net (code "425") (name "unconnected-(U23-PA13-Pad32)") (class "Default")
      (node (ref "U23") (pin "32") (pinfunction "PA13_32") (pintype "bidirectional"))
    )
    (net (code "426") (name "unconnected-(U23-PA14-Pad33)") (class "Default")
      (node (ref "U23") (pin "33") (pinfunction "PA14_33") (pintype "bidirectional"))
    )
    (net (code "427") (name "unconnected-(U23-PA17-Pad36)") (class "Default")
      (node (ref "U23") (pin "36") (pinfunction "PA17_36") (pintype "bidirectional"))
    )
    (net (code "428") (name "unconnected-(U23-XIN32-Pad13)") (class "Default")
      (node (ref "U23") (pin "13") (pinfunction "XIN32_13") (pintype "bidirectional"))
    )
    (net (code "429") (name "unconnected-(U23-XOUT32-Pad14)") (class "Default")
      (node (ref "U23") (pin "14") (pinfunction "XOUT32_14") (pintype "bidirectional"))
    )
    (net (code "430") (name "unconnected-(U26-A2-Pad3)") (class "Default")
      (node (ref "U26") (pin "3") (pinfunction "A2_3") (pintype "bidirectional"))
    )
    (net (code "431") (name "unconnected-(U26-B2-Pad6)") (class "Default")
      (node (ref "U26") (pin "6") (pinfunction "B2_6") (pintype "bidirectional"))
    )
    (net (code "432") (name "unconnected-(U27-A2-Pad3)") (class "Default")
      (node (ref "U27") (pin "3") (pinfunction "A2_3") (pintype "bidirectional"))
    )
    (net (code "433") (name "unconnected-(U27-B2-Pad6)") (class "Default")
      (node (ref "U27") (pin "6") (pinfunction "B2_6") (pintype "bidirectional"))
    )
    (net (code "434") (name "unconnected-(U31-EECLK-Pad7)") (class "Default")
      (node (ref "U31") (pin "7") (pinfunction "EECLK_7") (pintype "bidirectional"))
    )
    (net (code "435") (name "unconnected-(U32-EECLK-Pad7)") (class "Default")
      (node (ref "U32") (pin "7") (pinfunction "EECLK_7") (pintype "bidirectional"))
    )
    (net (code "436") (name "unconnected-(U32-SUSPND-Pad1)") (class "Default")
      (node (ref "U32") (pin "1") (pinfunction "SUSPND_1") (pintype "bidirectional"))
    )
    (net (code "437") (name "unconnected-(U32-~{PWRON2}-Pad15)") (class "Default")
      (node (ref "U32") (pin "15") (pinfunction "~{PWRON2}_15") (pintype "bidirectional"))
    )
    (net (code "438") (name "unconnected-(U32-~{PWRON3}-Pad19)") (class "Default")
      (node (ref "U32") (pin "19") (pinfunction "~{PWRON3}_19") (pintype "bidirectional"))
    )
    (net (code "439") (name "unconnected-(U32-~{PWRON4}-Pad23)") (class "Default")
      (node (ref "U32") (pin "23") (pinfunction "~{PWRON4}_23") (pintype "bidirectional"))
    )
    (net (code "440") (name "unconnected-(U32-~{PWRON5}-Pad28)") (class "Default")
      (node (ref "U32") (pin "28") (pinfunction "~{PWRON5}_28") (pintype "bidirectional"))
    )
    (net (code "441") (name "unconnected-(U32-~{PWRON6}-Pad32)") (class "Default")
      (node (ref "U32") (pin "32") (pinfunction "~{PWRON6}_32") (pintype "bidirectional"))
    )
    (net (code "442") (name "unconnected-(U32-~{PWRON7}-Pad36)") (class "Default")
      (node (ref "U32") (pin "36") (pinfunction "~{PWRON7}_36") (pintype "bidirectional"))
    )
    (net (code "443") (name "~{BACKPLANE_RESET}") (class "Default")
      (node (ref "D2") (pin "4A") (pinfunction "ANODE_4A") (pintype "bidirectional"))
      (node (ref "J1") (pin "22") (pinfunction "~{BACKPLANE_RESET}_22") (pintype "bidirectional"))
      (node (ref "JP14") (pin "2") (pinfunction "2_2") (pintype "passive"))
      (node (ref "R42") (pin "1") (pinfunction "1_1") (pintype "passive"))
      (node (ref "U17") (pin "4") (pinfunction "~{RESET}_4") (pintype "bidirectional"))
      (node (ref "U18") (pin "4") (pinfunction "~{RESET}_4") (pintype "bidirectional"))
      (node (ref "U19") (pin "4") (pinfunction "~{RESET}_4") (pintype "bidirectional"))
    )
    (net (code "444") (name "~{POWER_ON_RESET}") (class "Default")
      (node (ref "R52") (pin "1") (pinfunction "1_1") (pintype "passive"))
      (node (ref "U20") (pin "1") (pinfunction "~{RST}_1") (pintype "bidirectional"))
      (node (ref "U32") (pin "6") (pinfunction "~{RESET}_6") (pintype "bidirectional"))
    )
    (net (code "445") (name "~{SMBALERT}") (class "Default")
      (node (ref "J1") (pin "6") (pinfunction "~{SMBALERT}_6") (pintype "bidirectional"))
      (node (ref "JP11") (pin "10") (pinfunction "10_10") (pintype "passive"))
      (node (ref "JP12") (pin "6") (pinfunction "6_6") (pintype "passive"))
      (node (ref "R45") (pin "1") (pinfunction "1_1") (pintype "passive"))
      (node (ref "U22") (pin "17") (pinfunction "~{INT}_17") (pintype "bidirectional"))
    )
    (net (code "446") (name "~{WATCHDOG}") (class "Default")
      (node (ref "J1") (pin "7") (pinfunction "~{WATCHDOG}_7") (pintype "bidirectional"))
      (node (ref "JP12") (pin "7") (pinfunction "7_7") (pintype "passive"))
      (node (ref "U15") (pin "6") (pinfunction "WDI_6") (pintype "bidirectional"))
    )
  )
)
